# BSC_mini.net
KiCad netlist of a schematic drawn in EAGLE
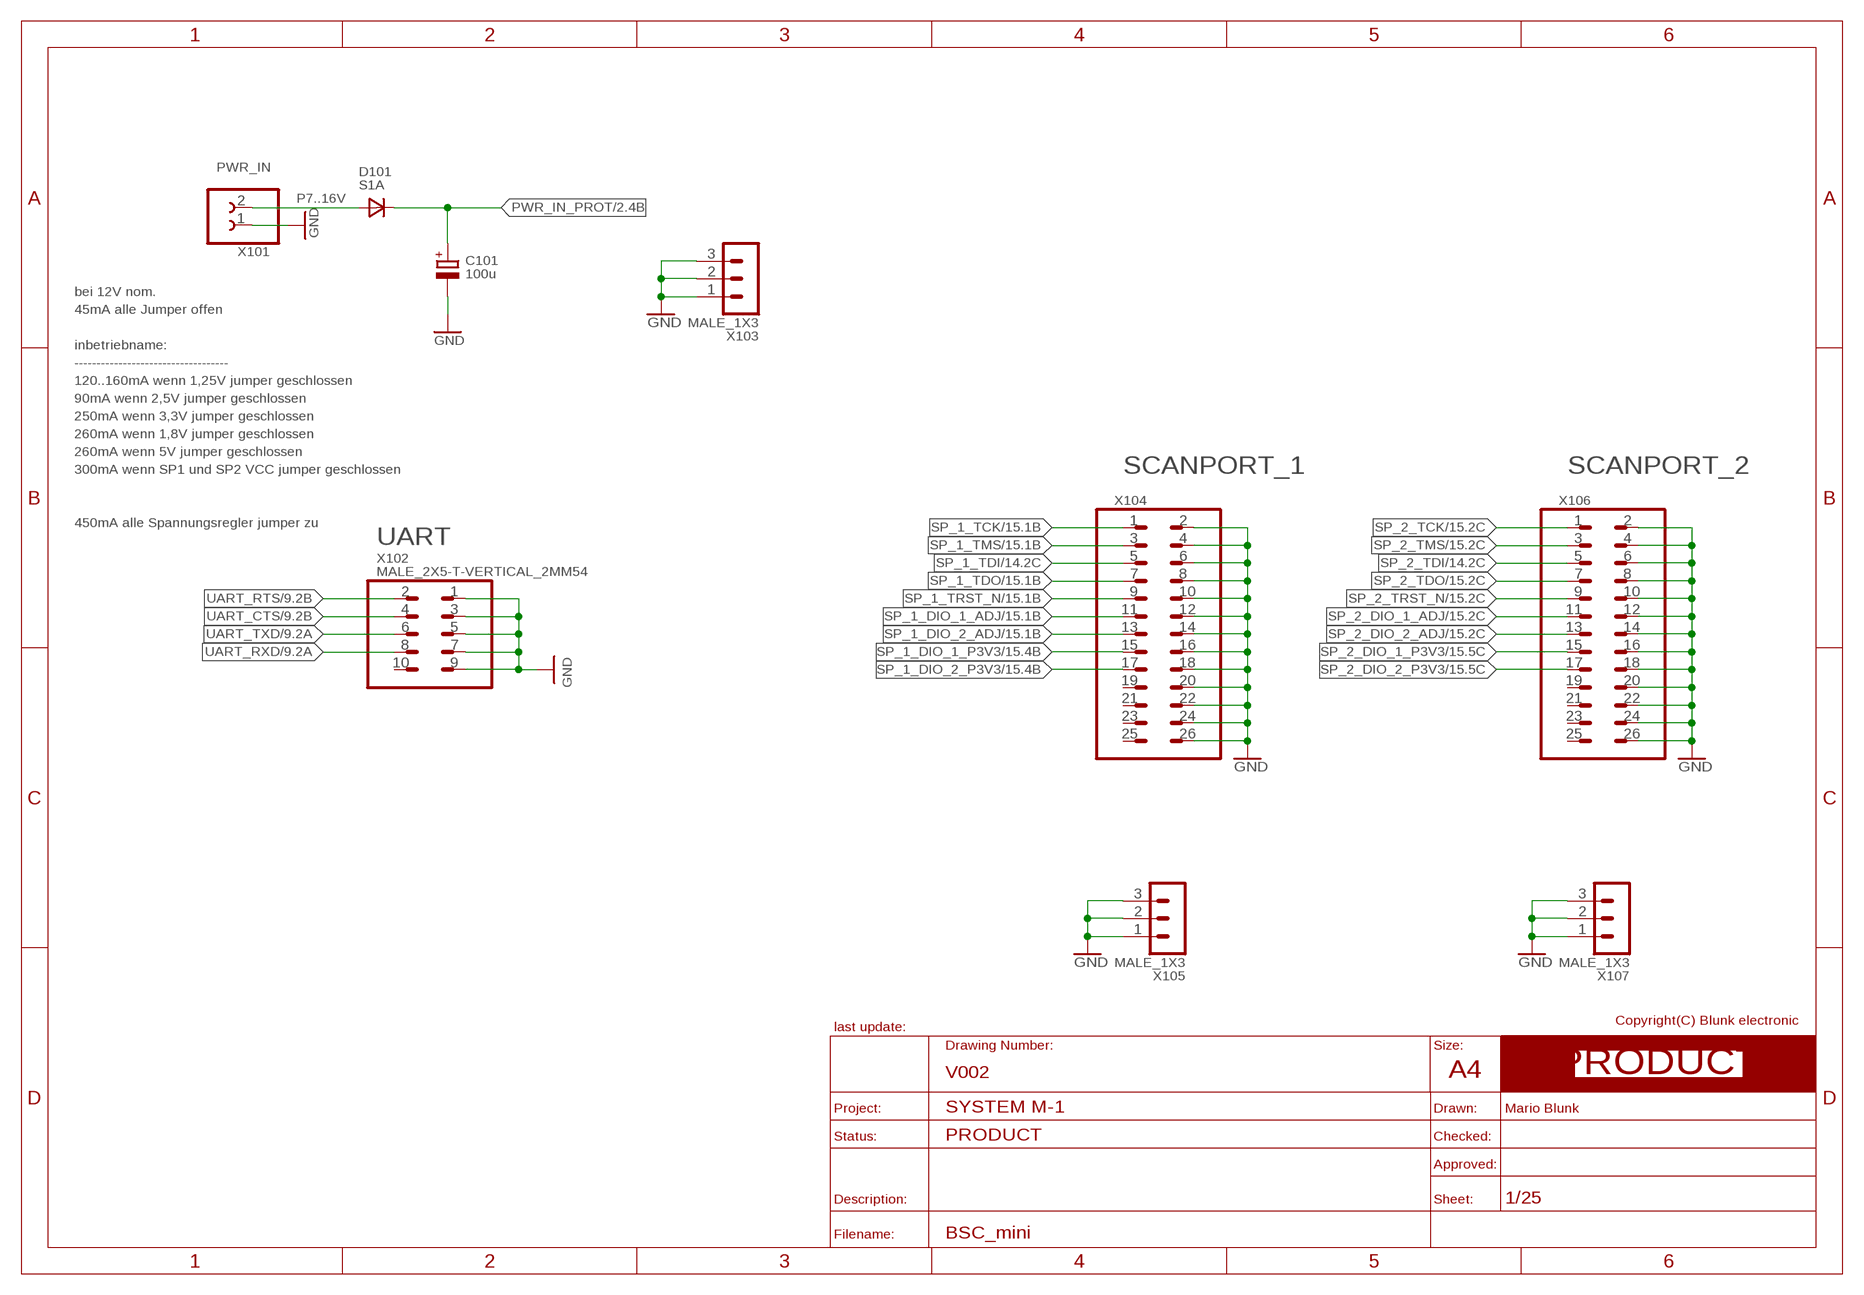
[diagram p0: schematic, sheet 1]
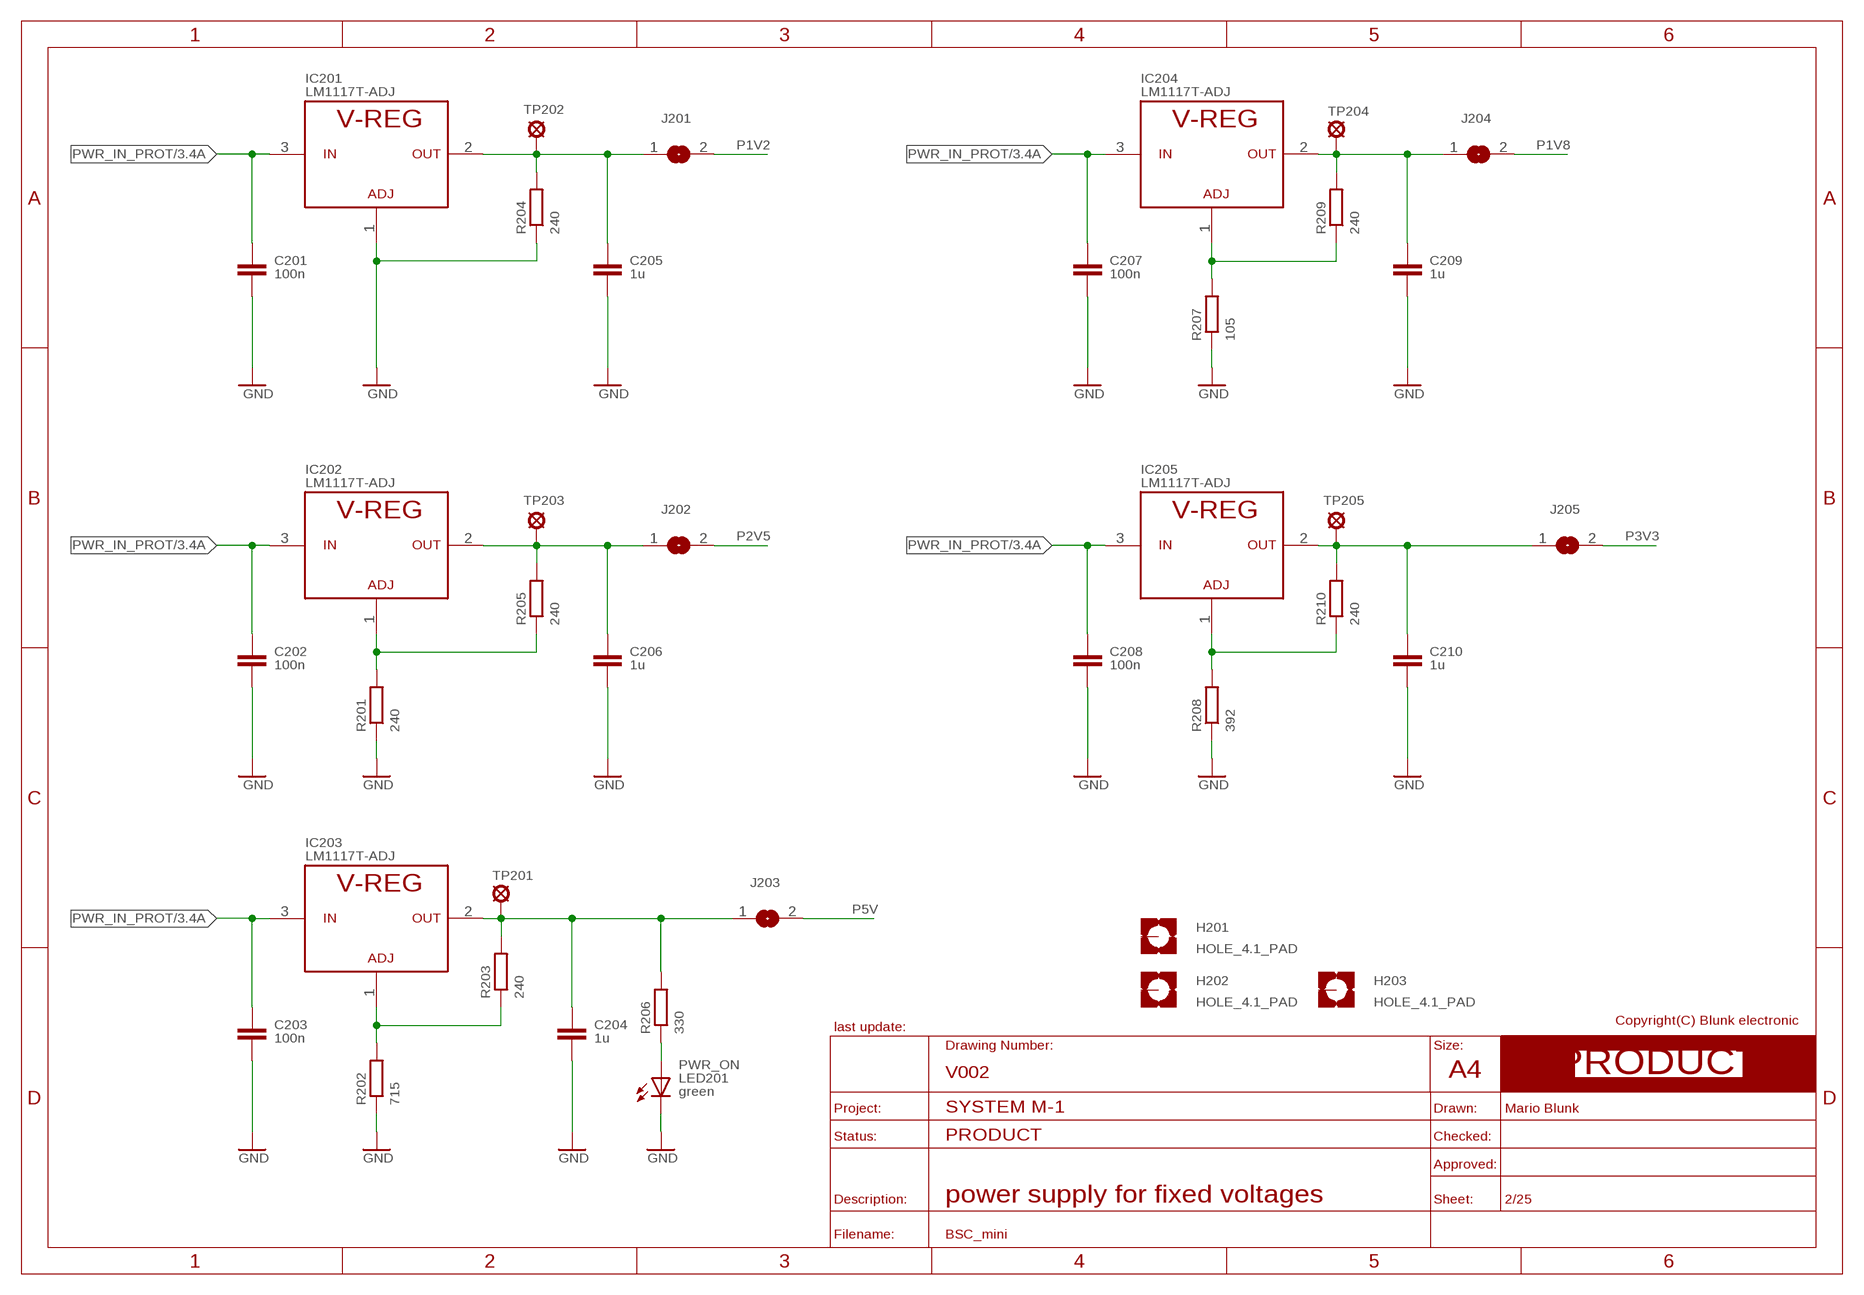
[diagram p1: schematic, sheet 2]
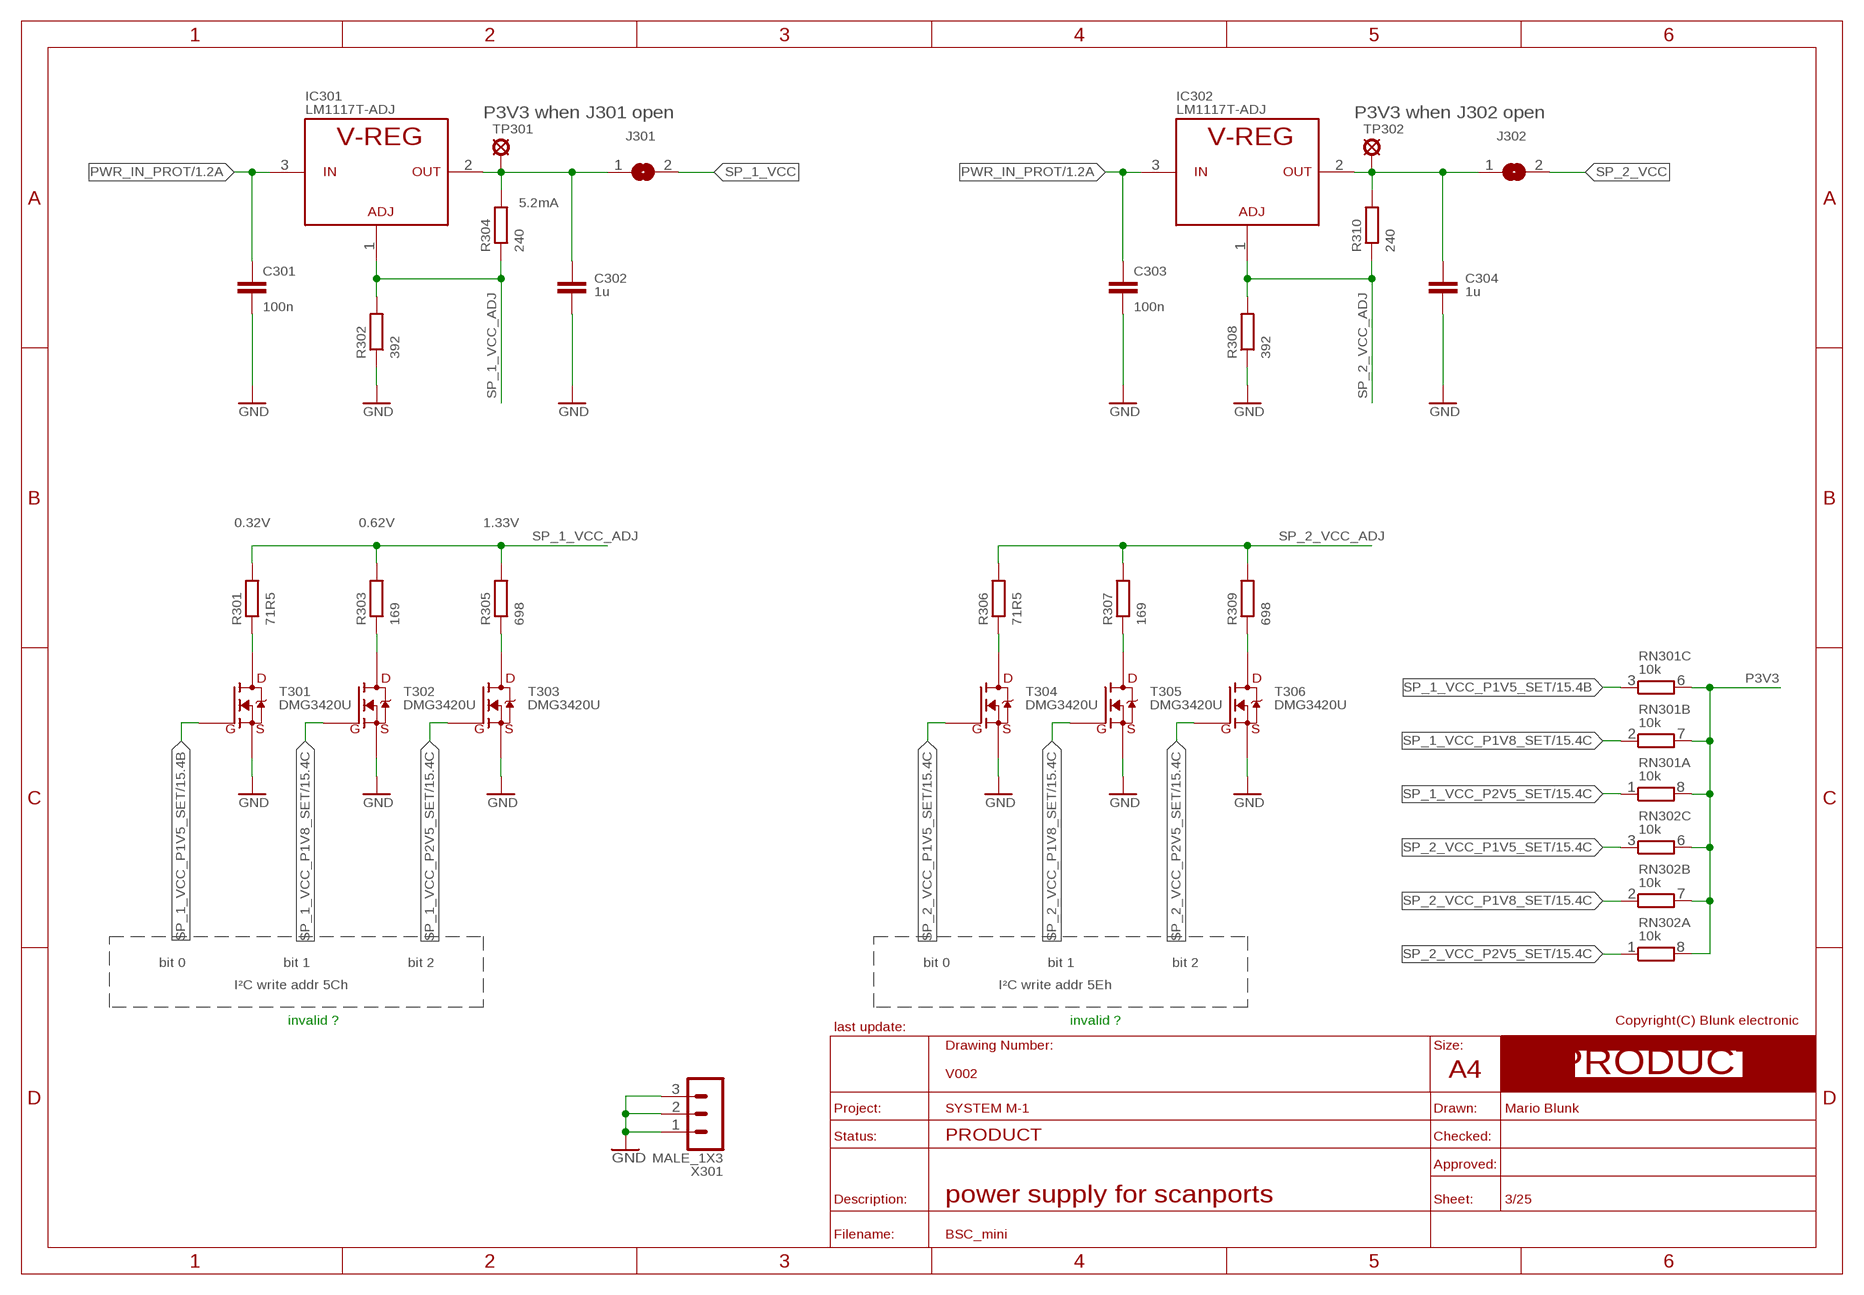
[diagram p2: schematic, sheet 3]
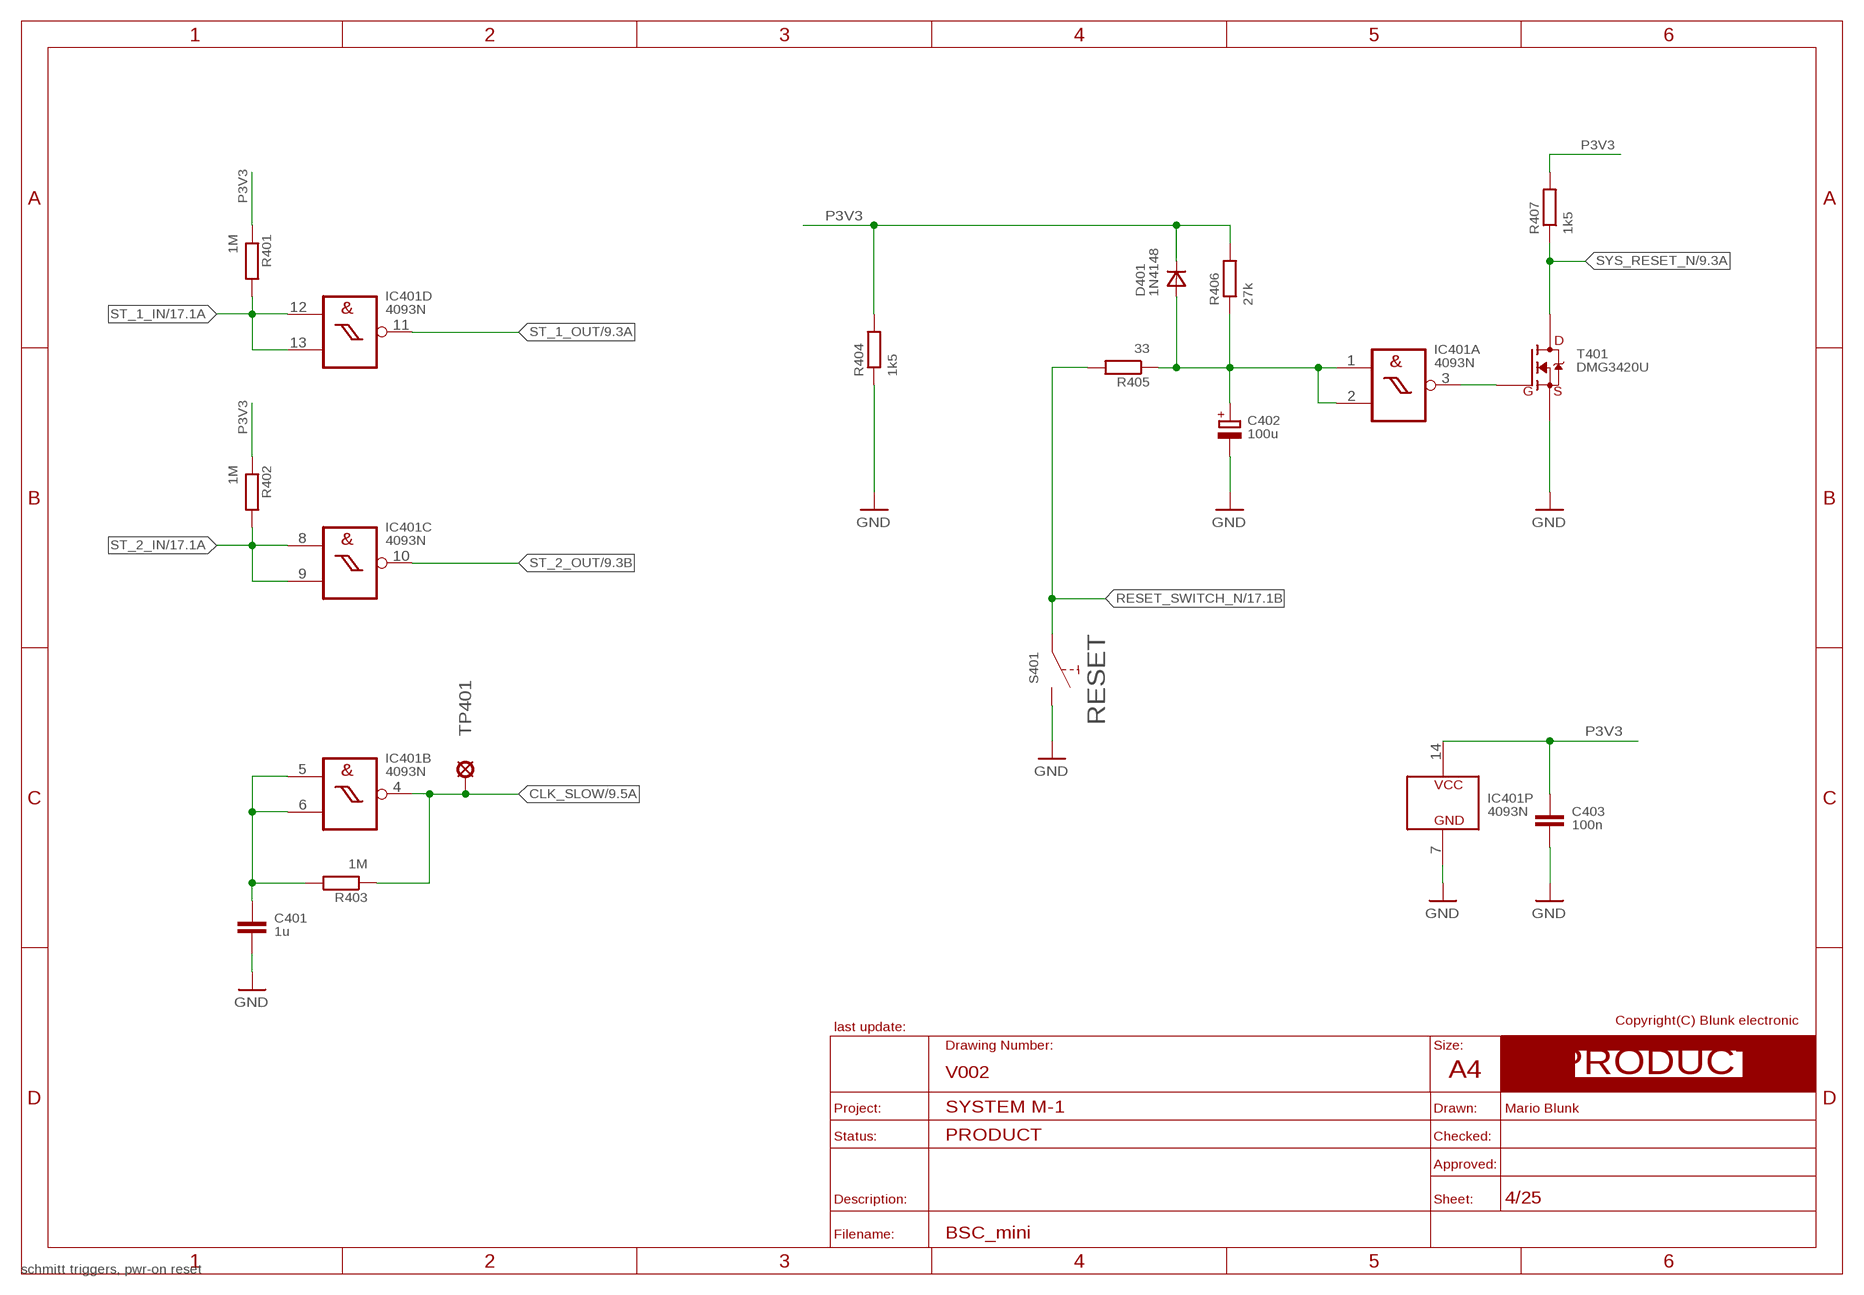
[diagram p3: schematic, sheet 4]
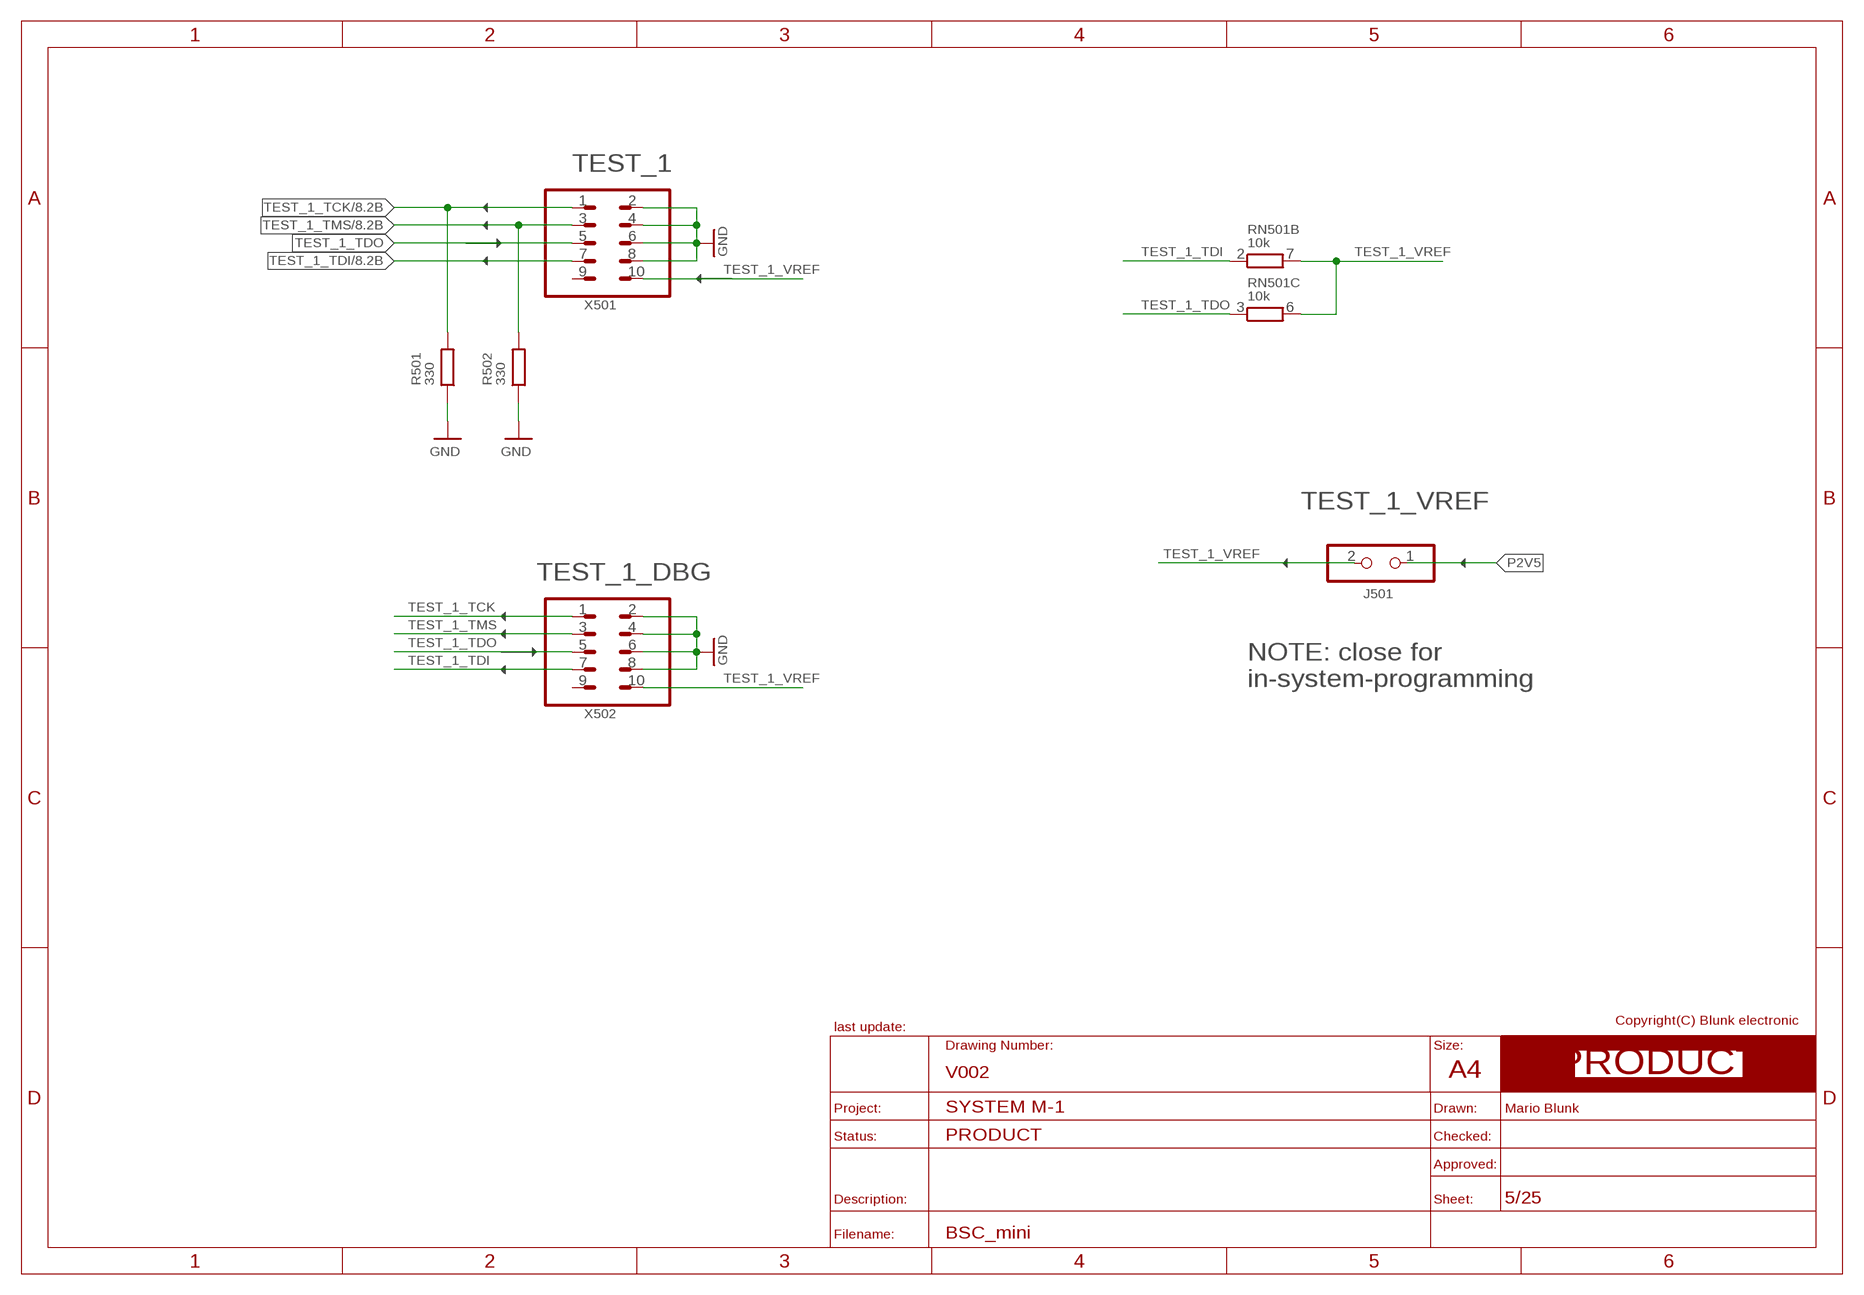
[diagram p4: schematic, sheet 5]
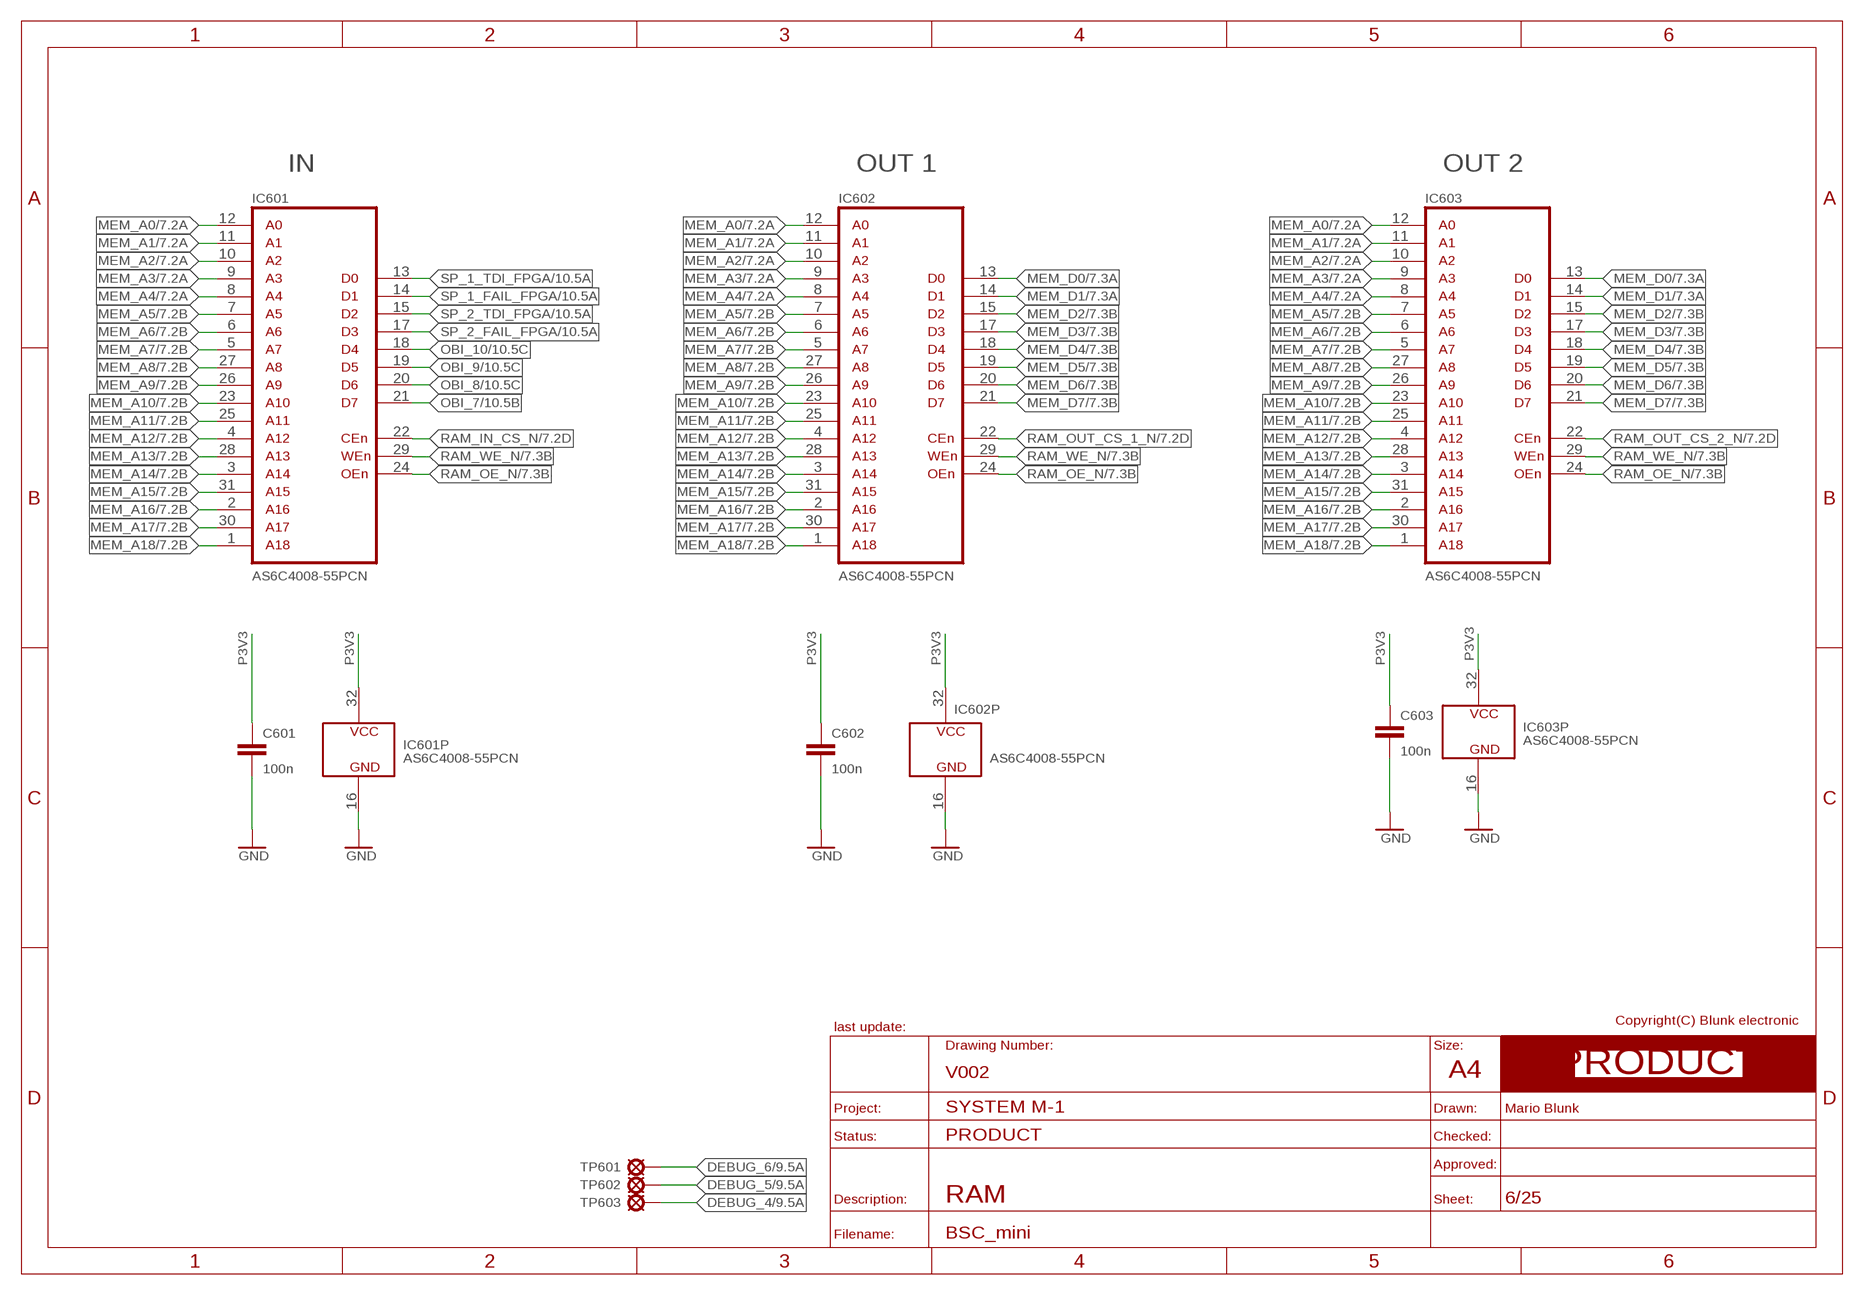
[diagram p5: schematic, sheet 6]
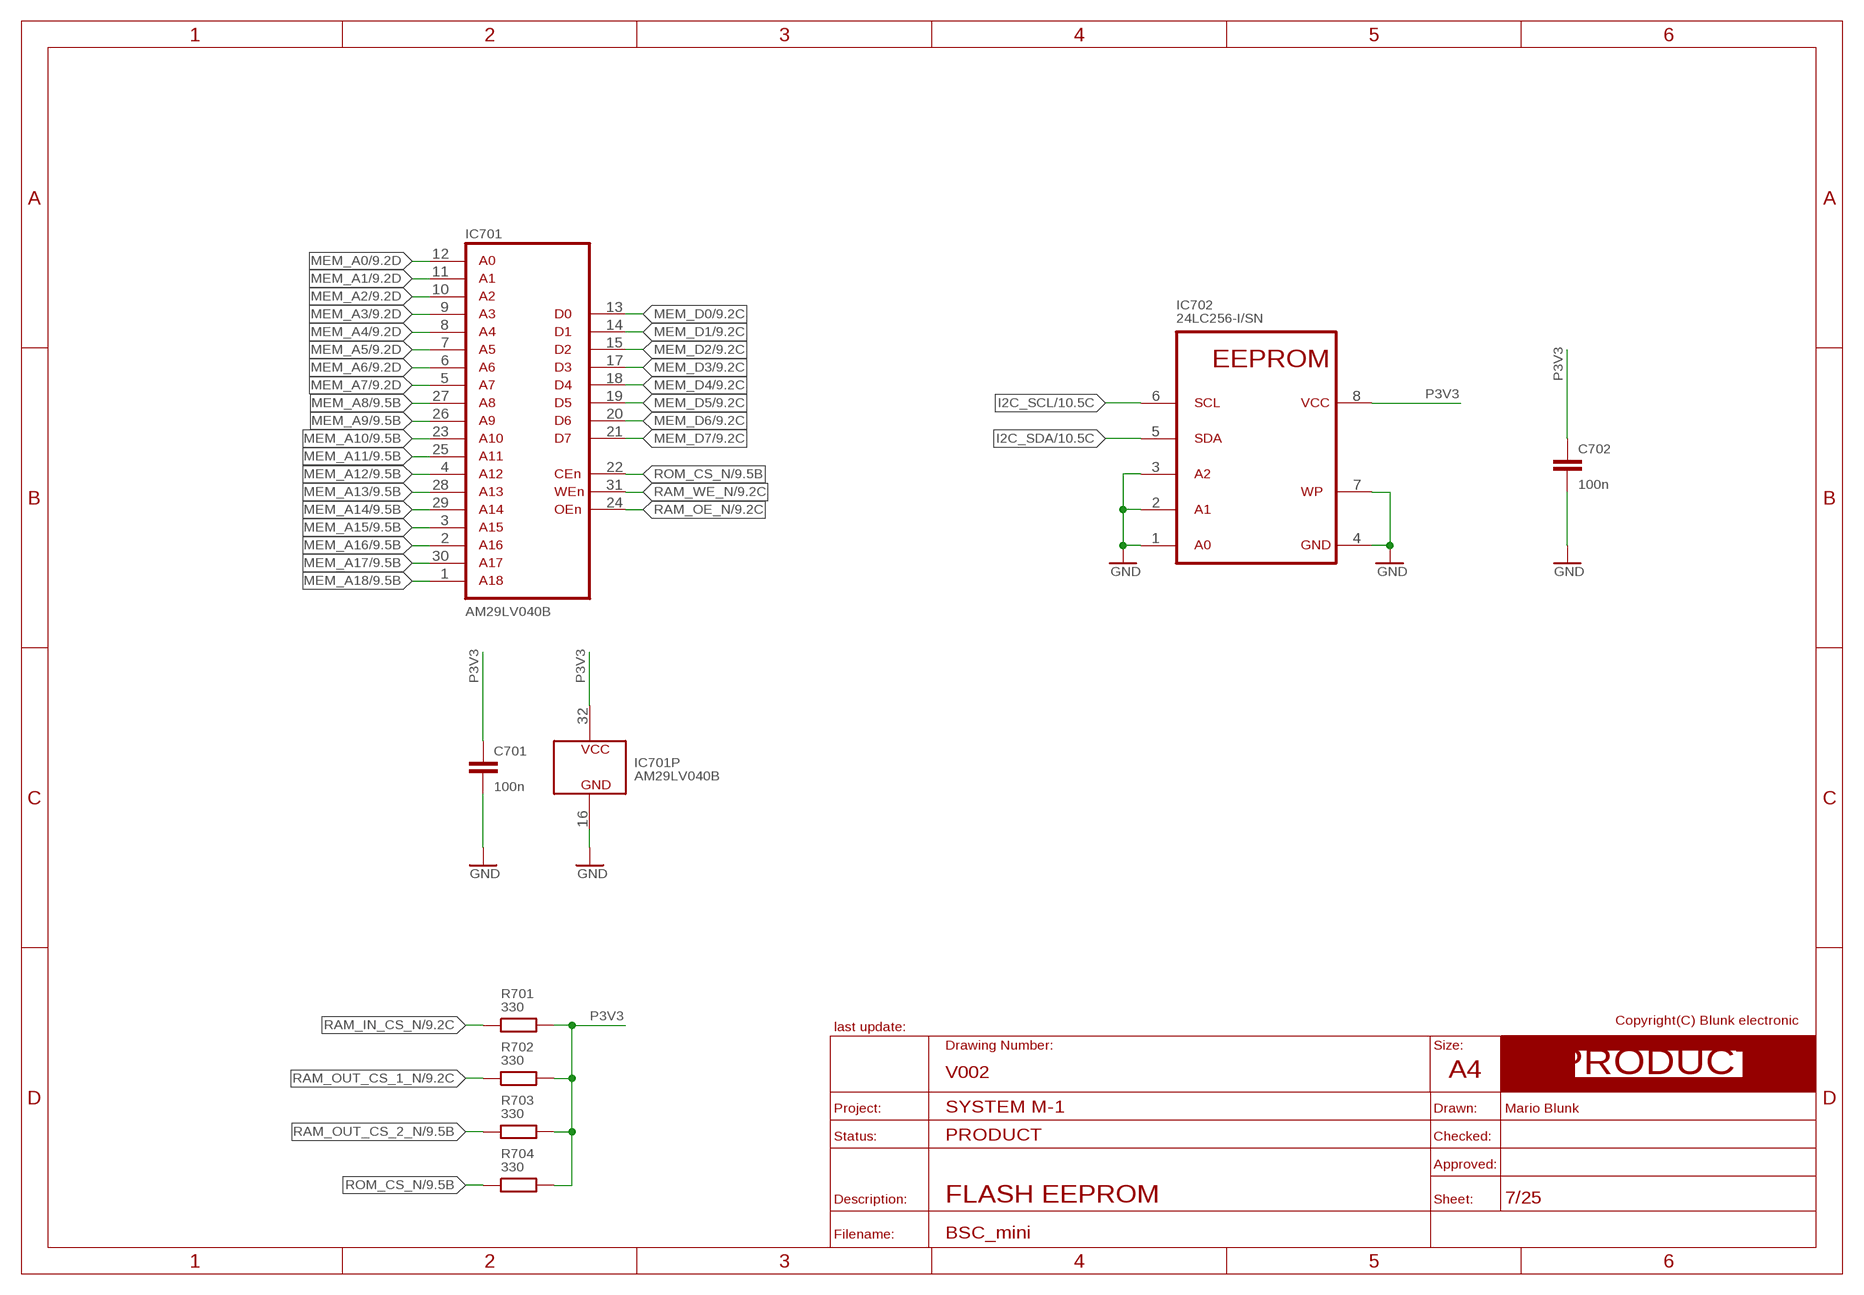
[diagram p6: schematic, sheet 7]
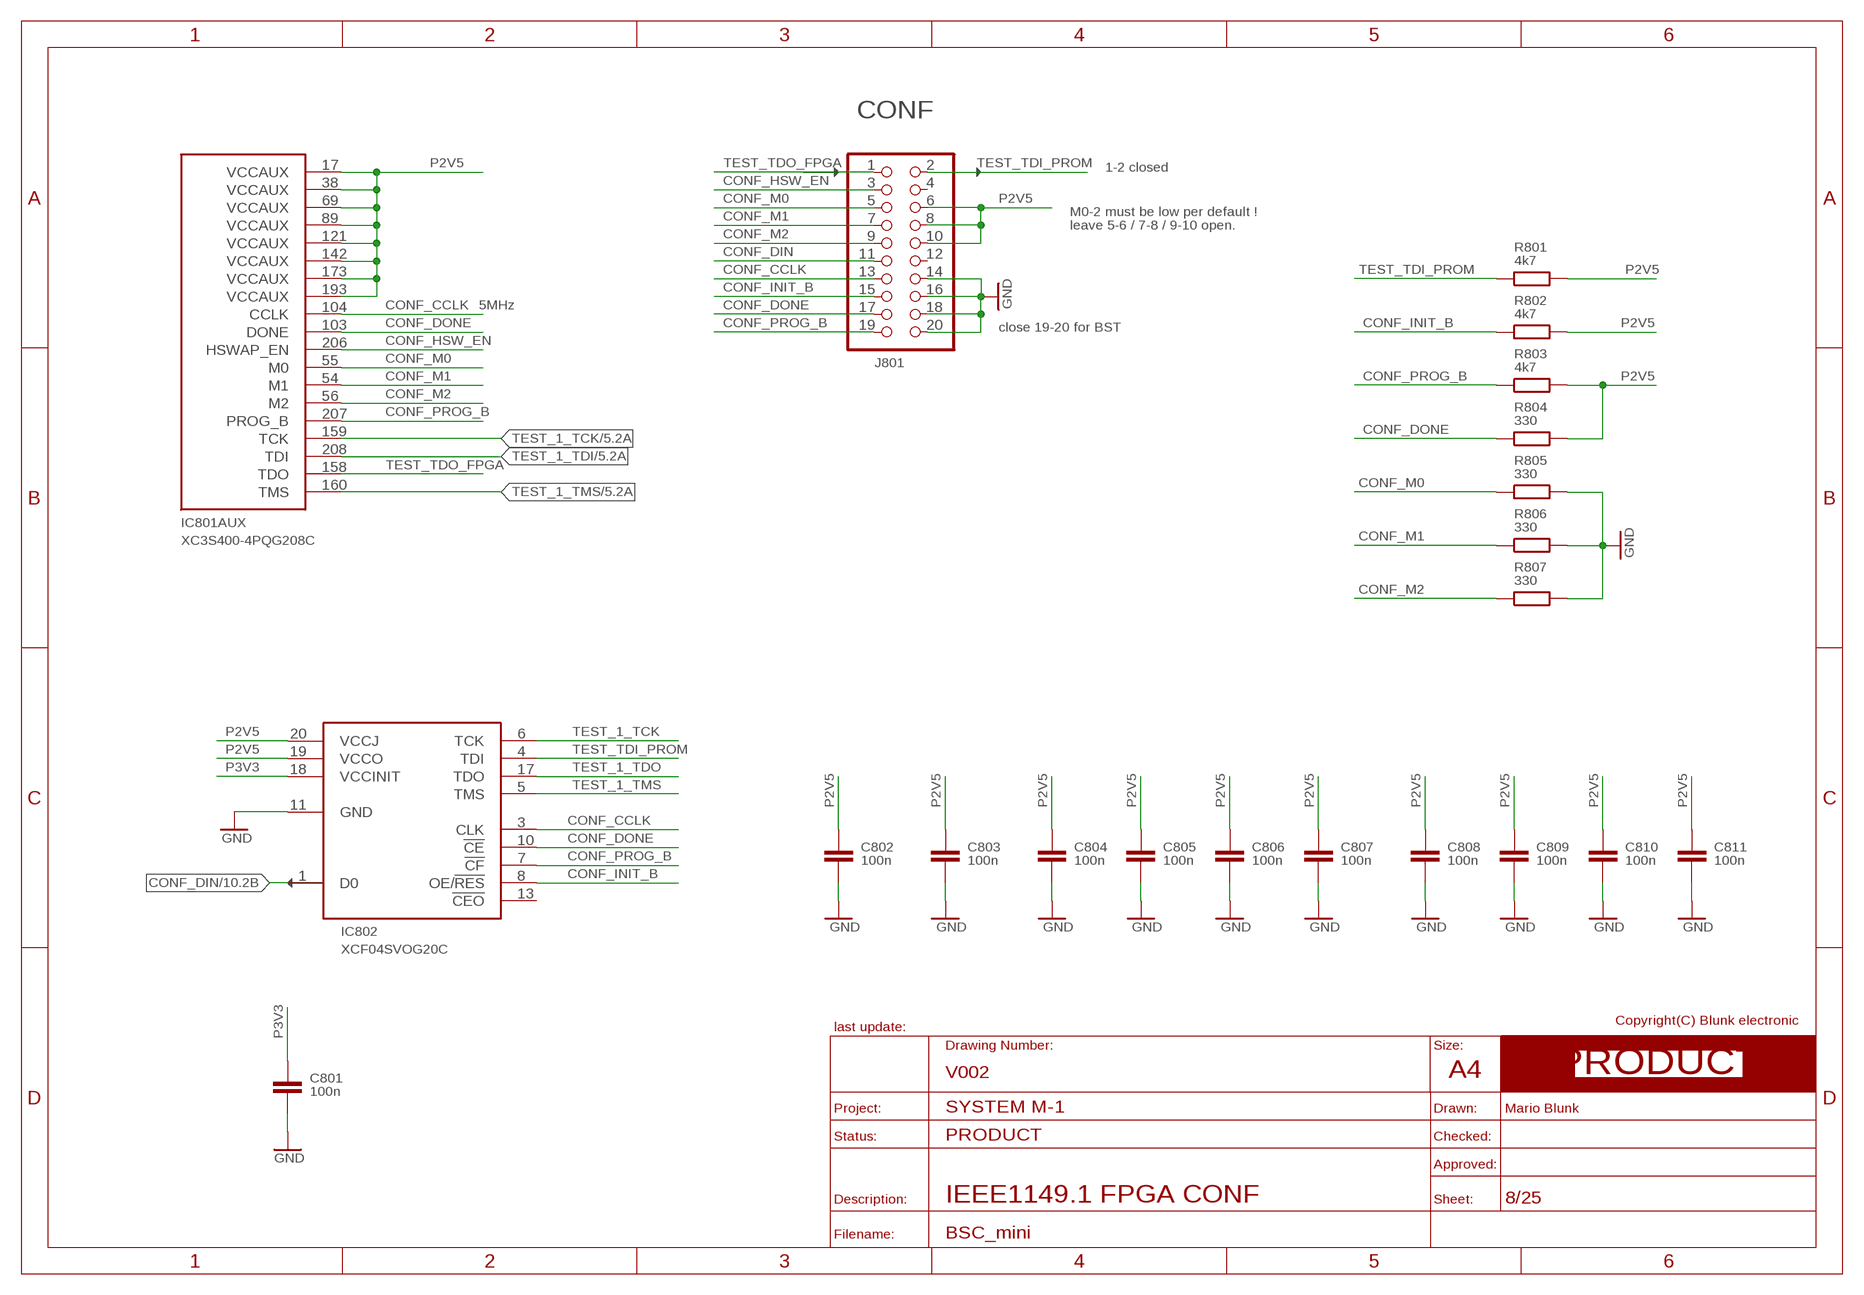
[diagram p7: schematic, sheet 8]
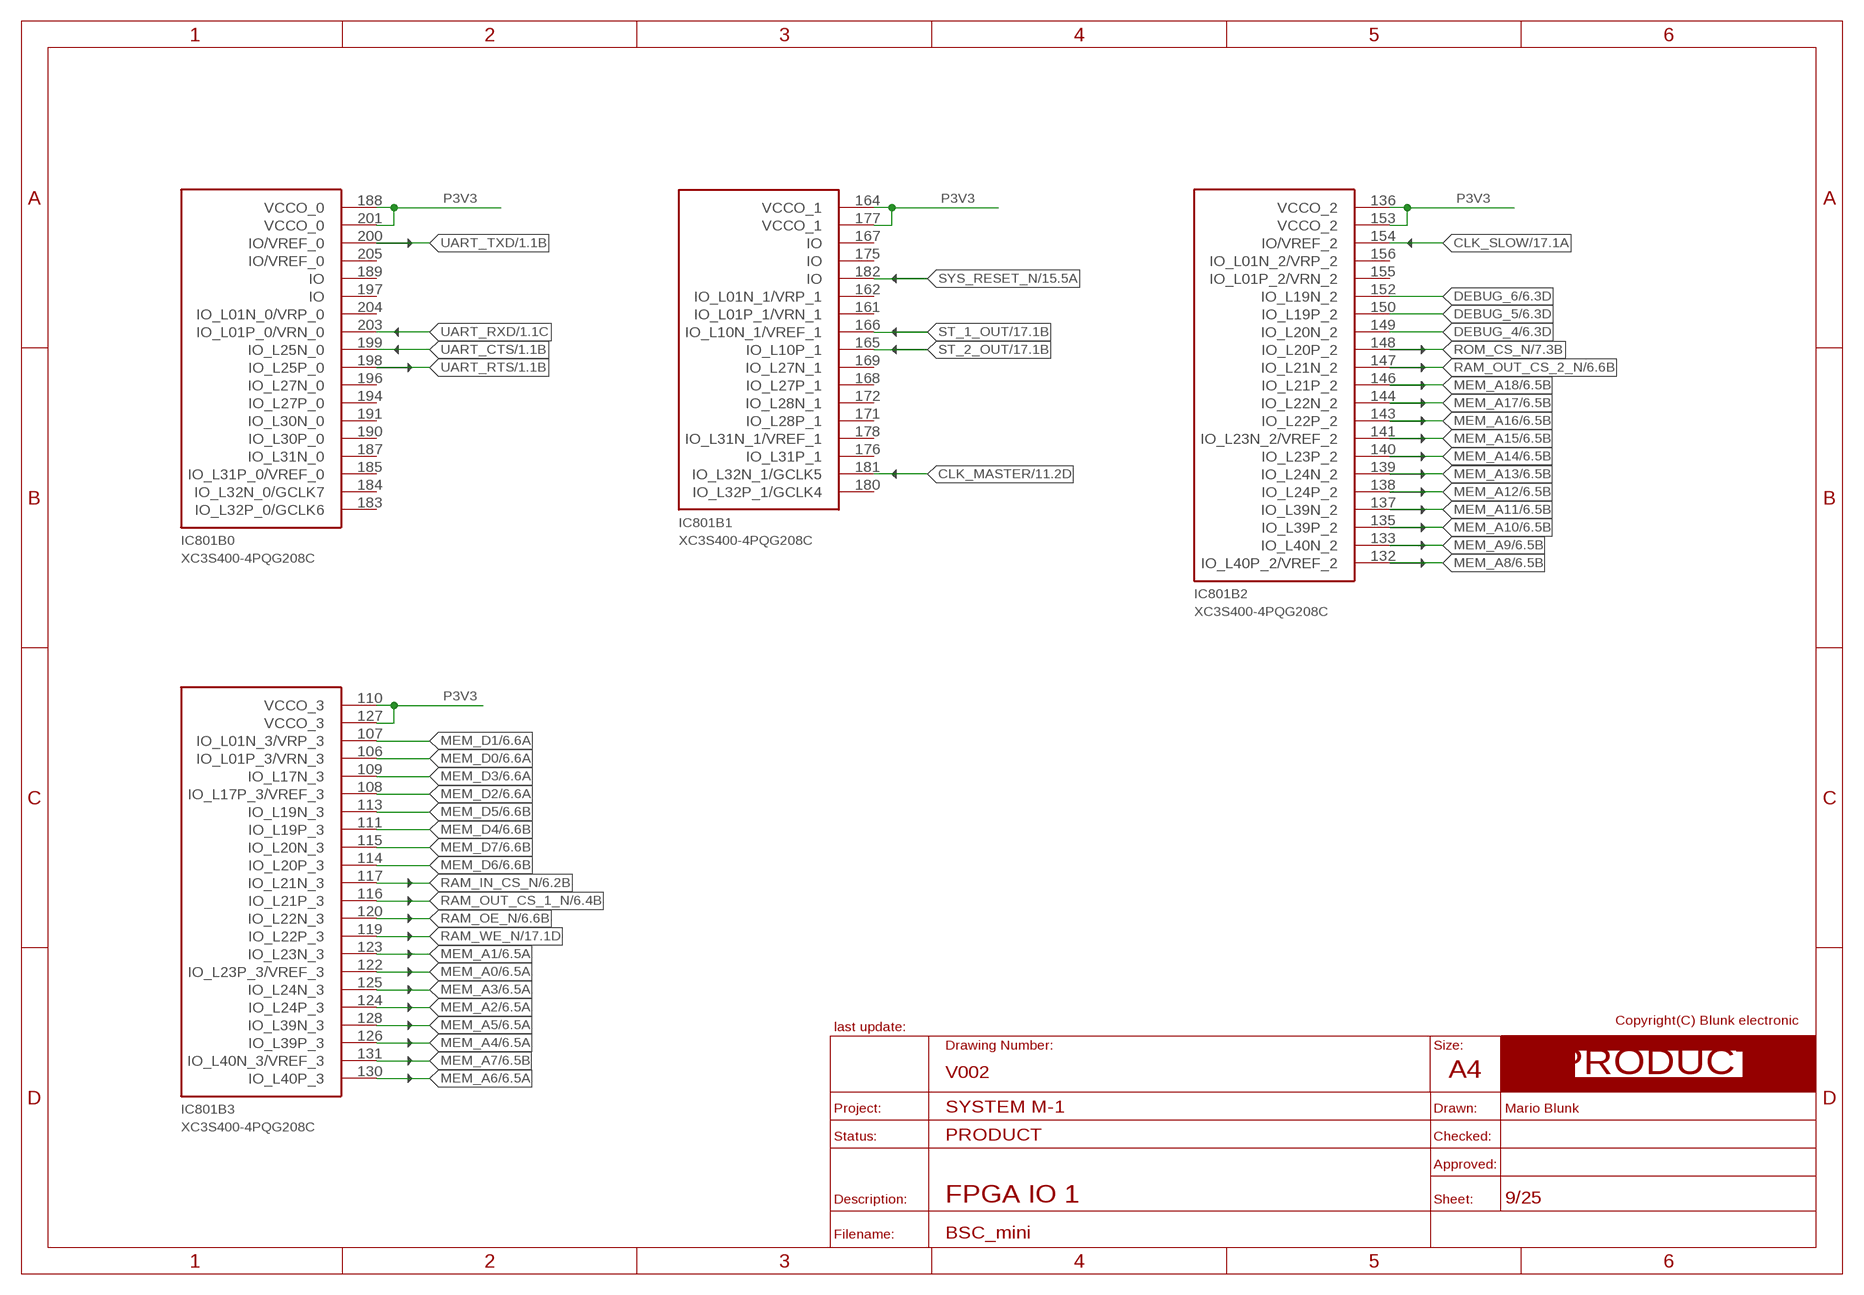
[diagram p8: schematic, sheet 9]
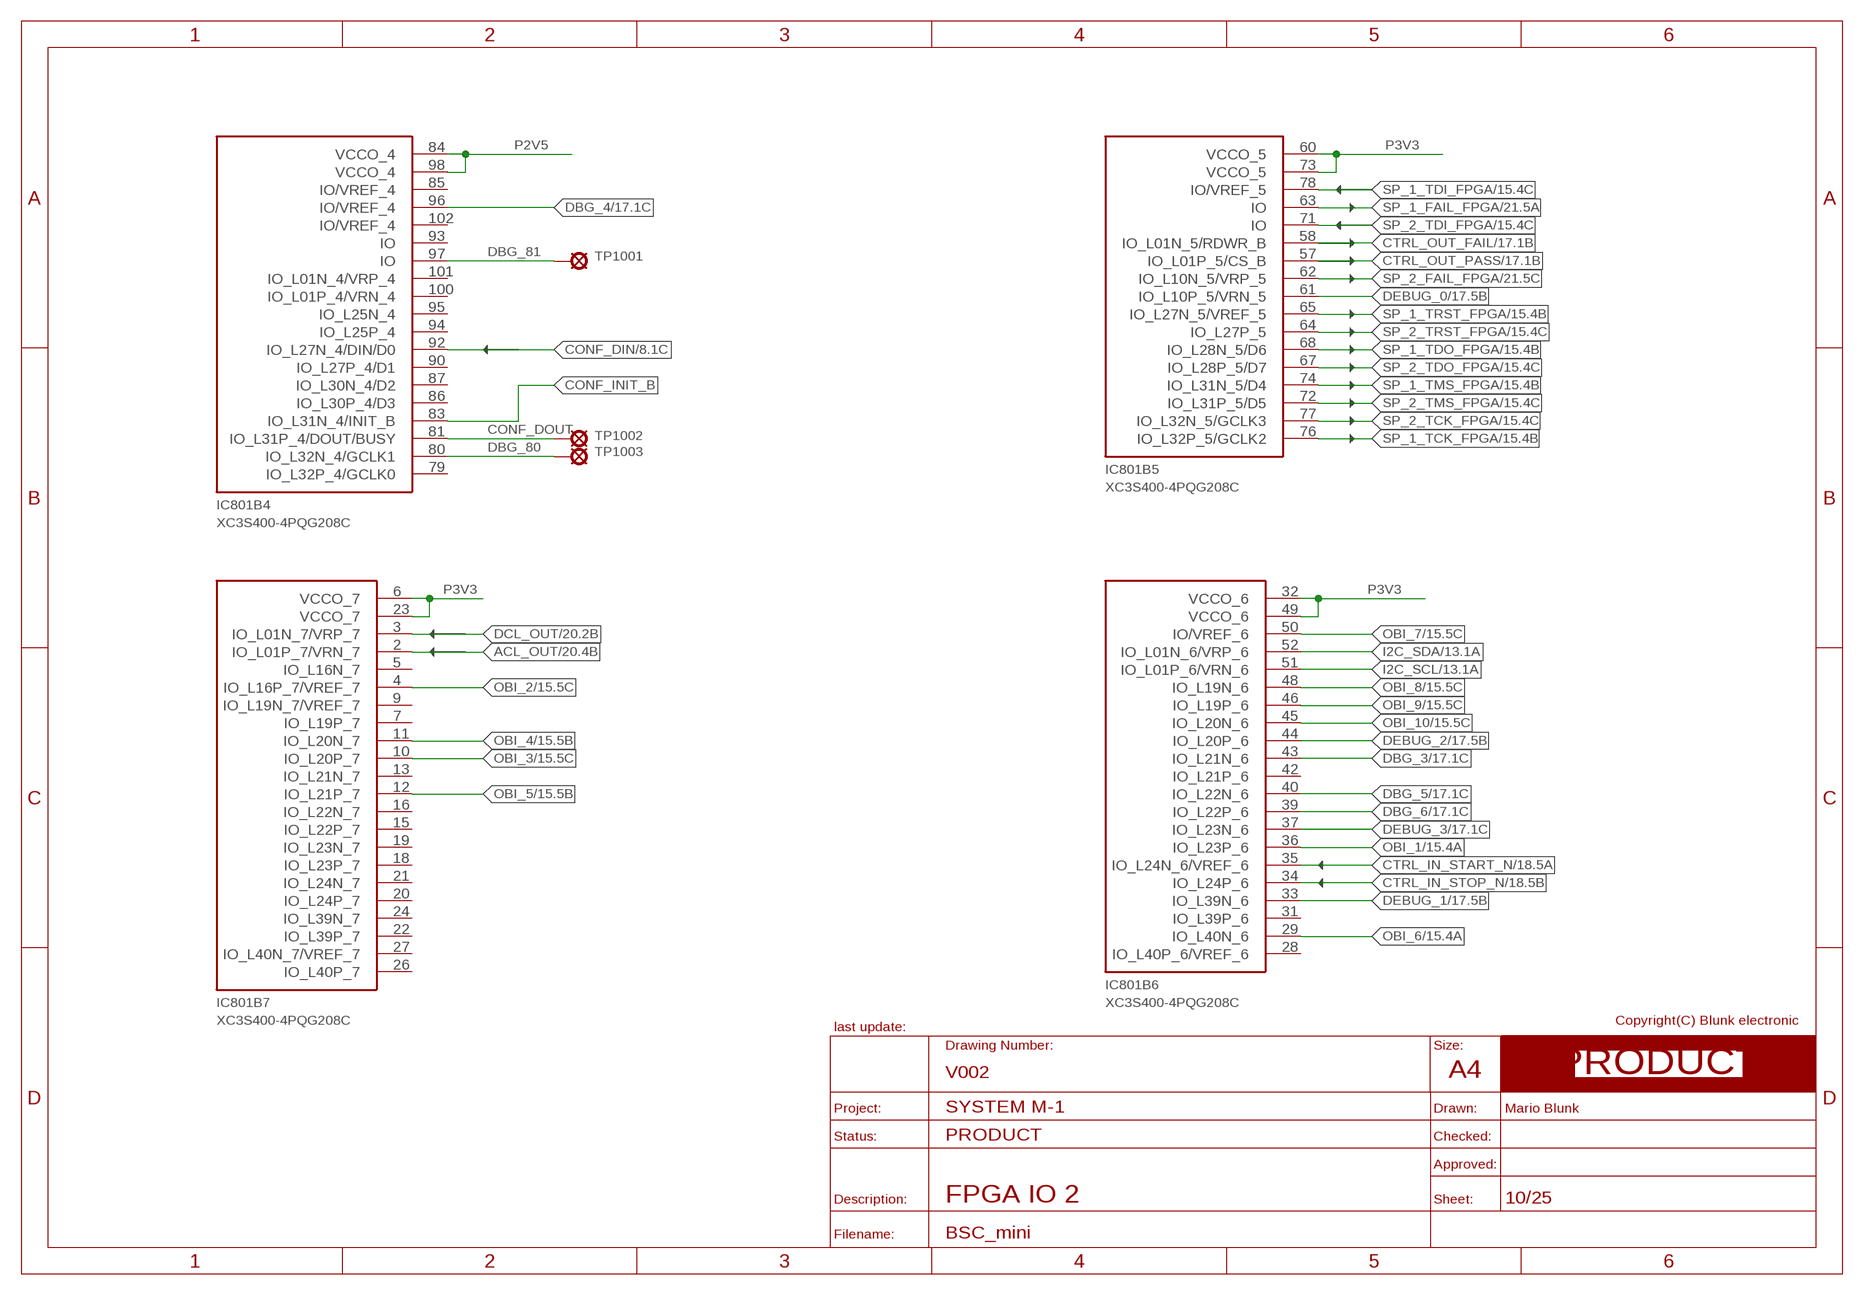
[diagram p9: schematic, sheet 10]
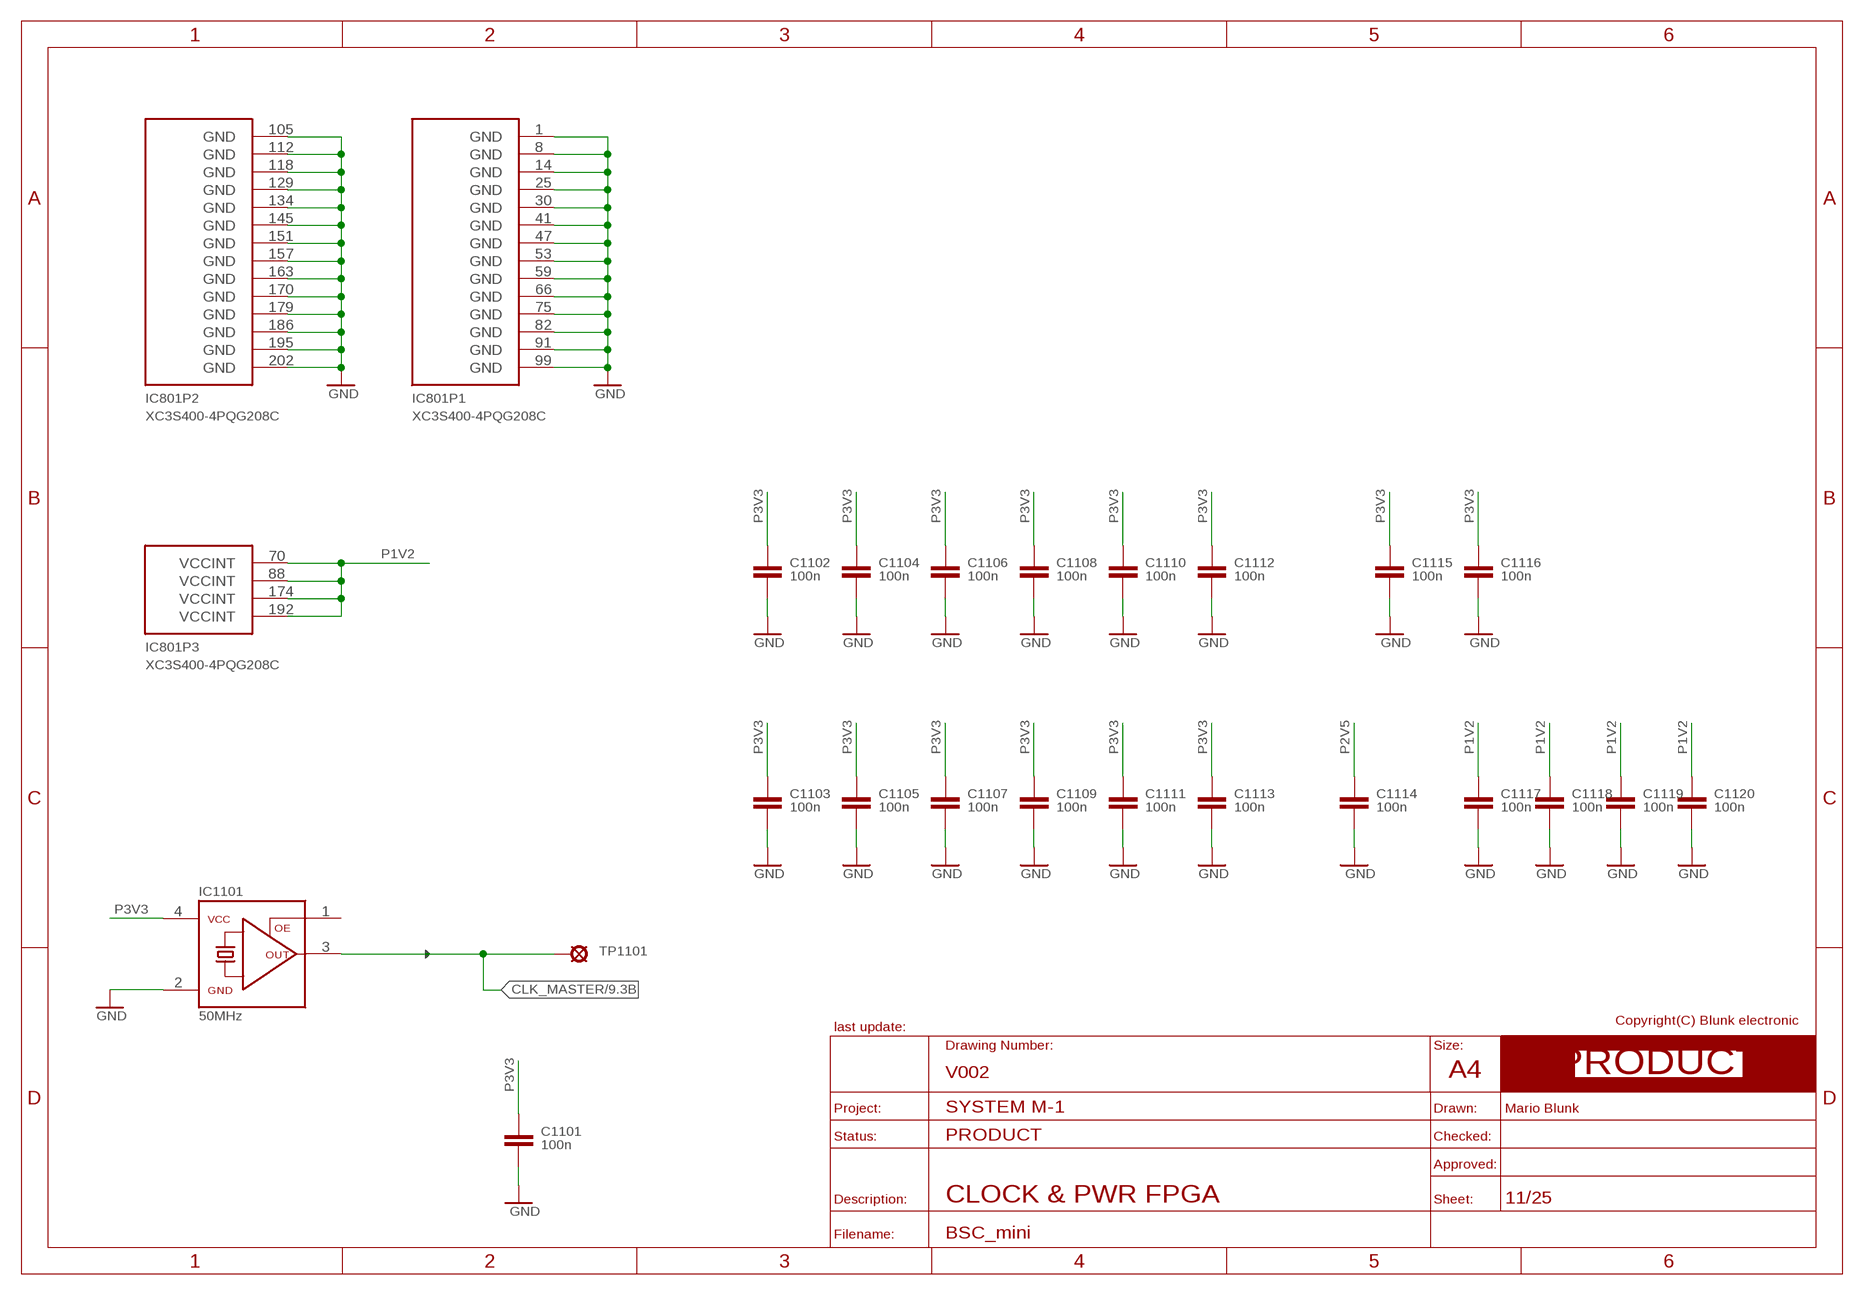
[diagram p10: schematic, sheet 11]
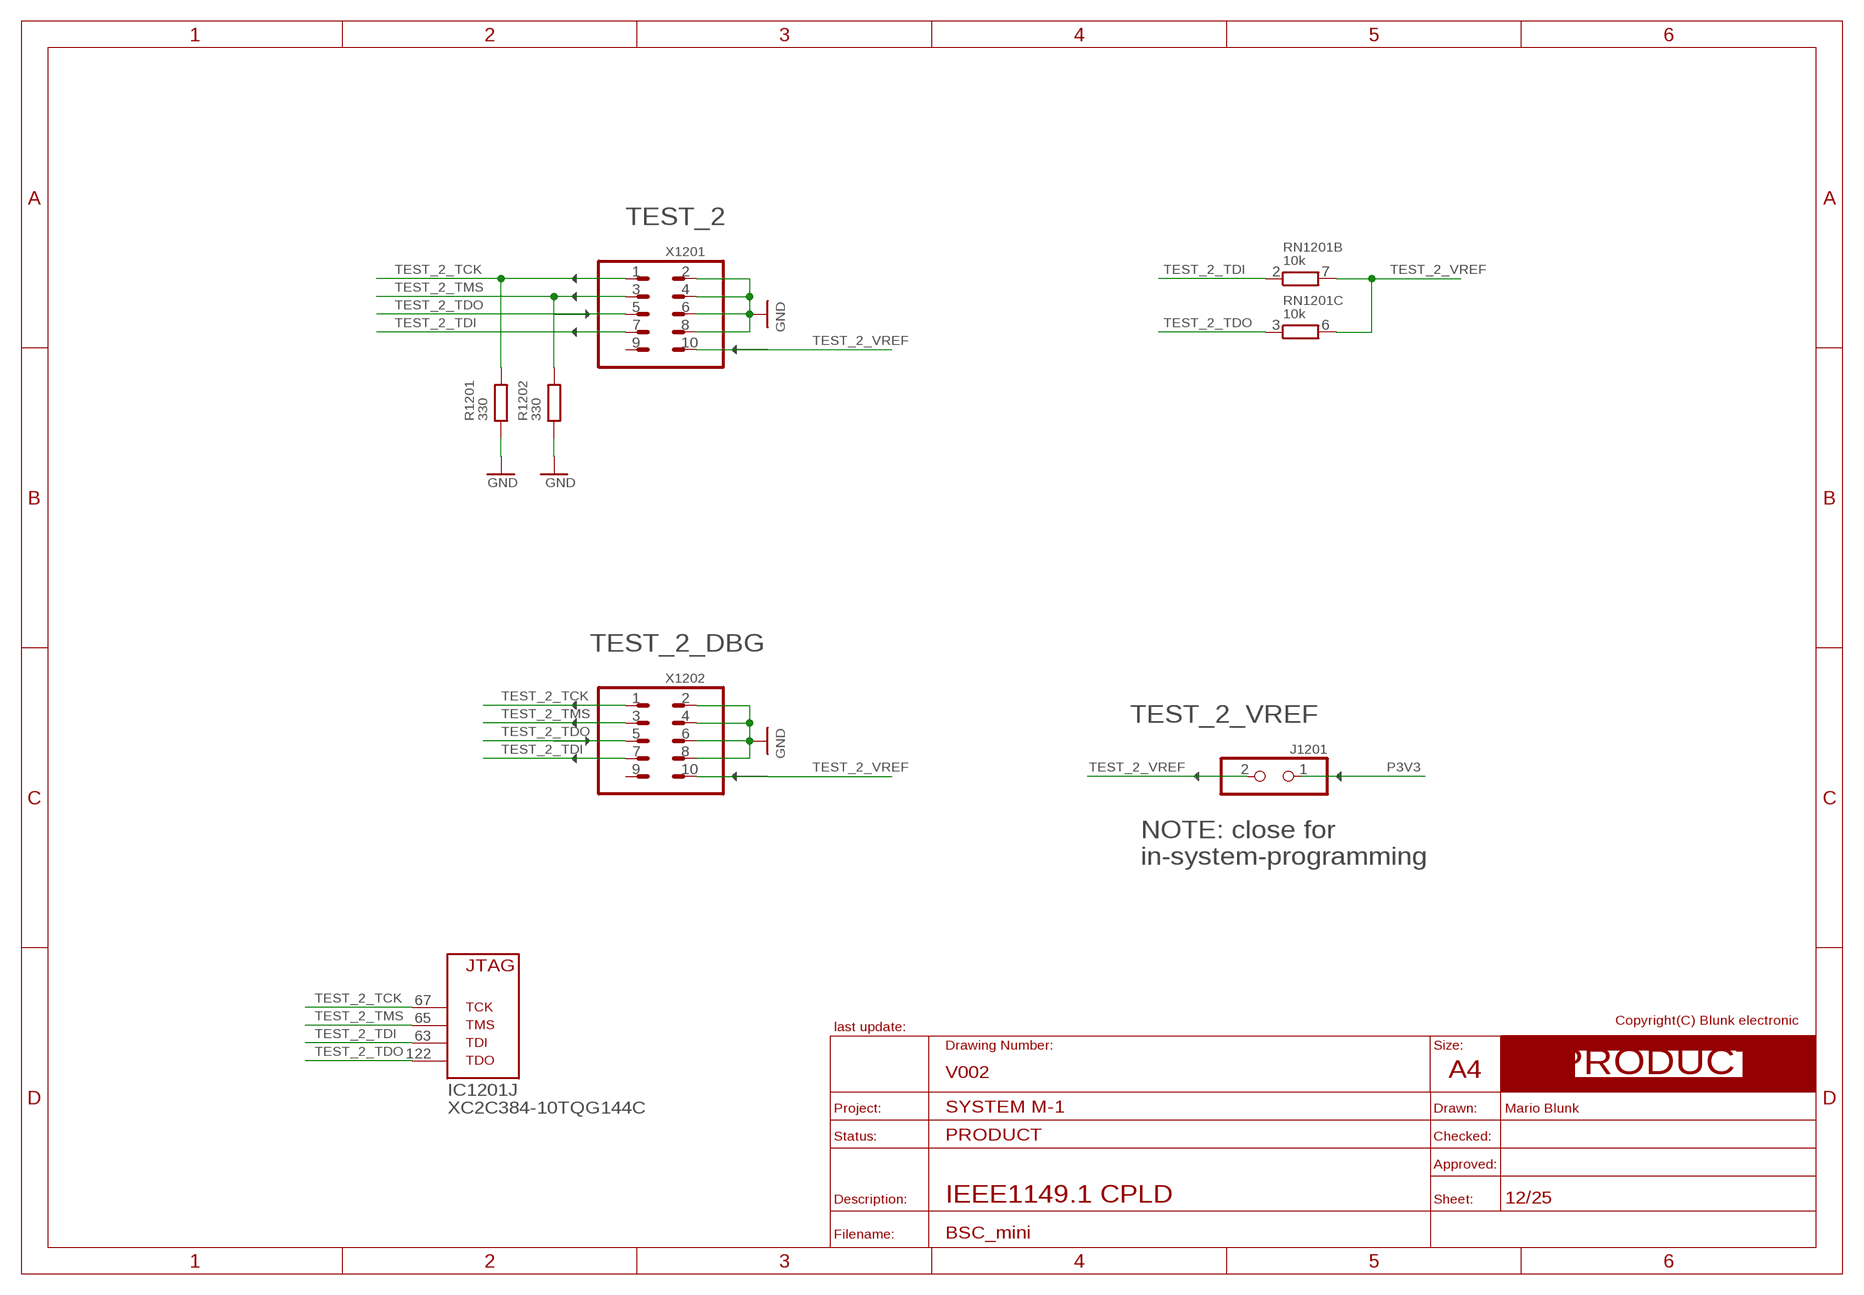
[diagram p11: schematic, sheet 12]
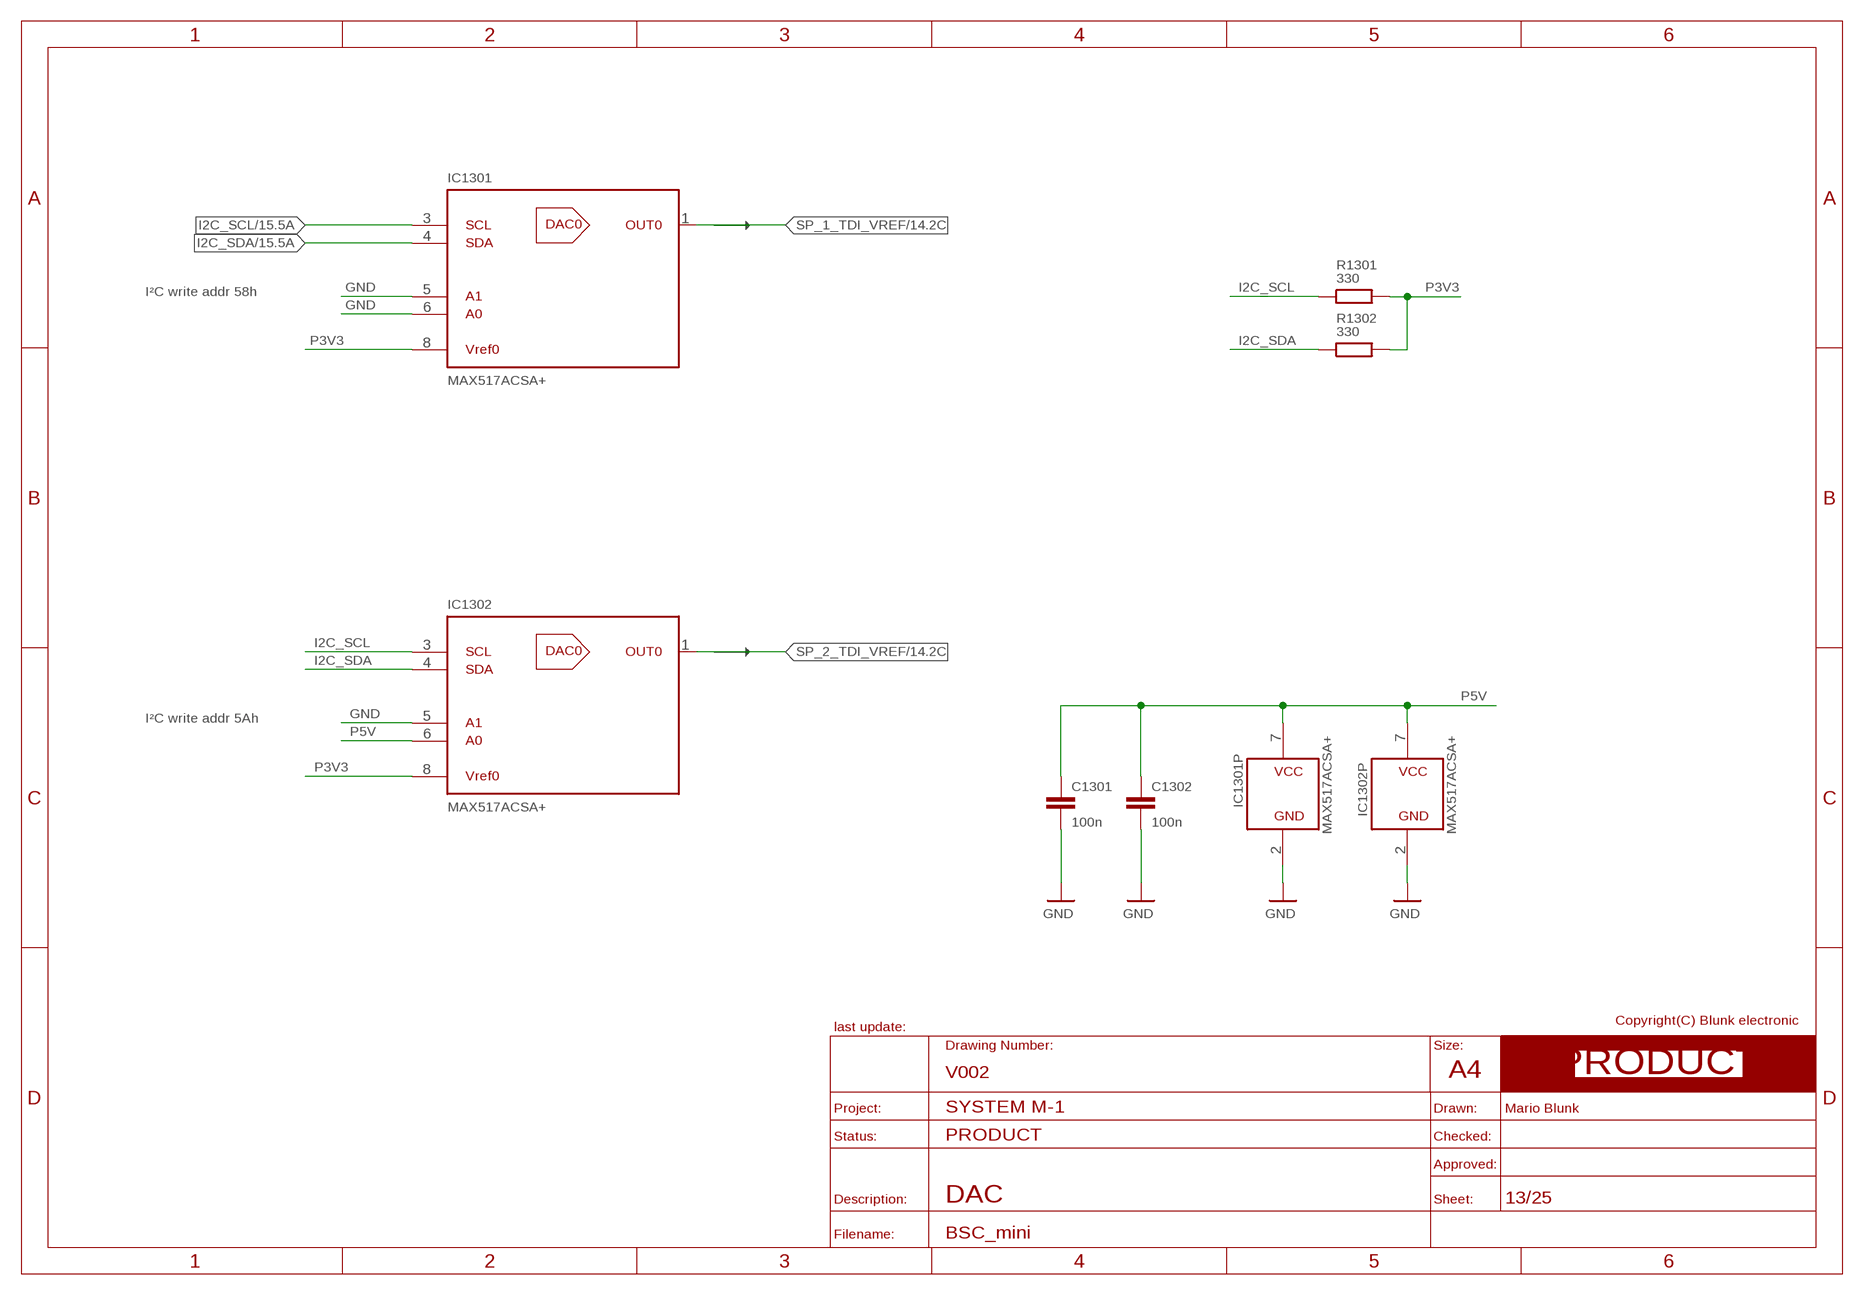
[diagram p12: schematic, sheet 13]
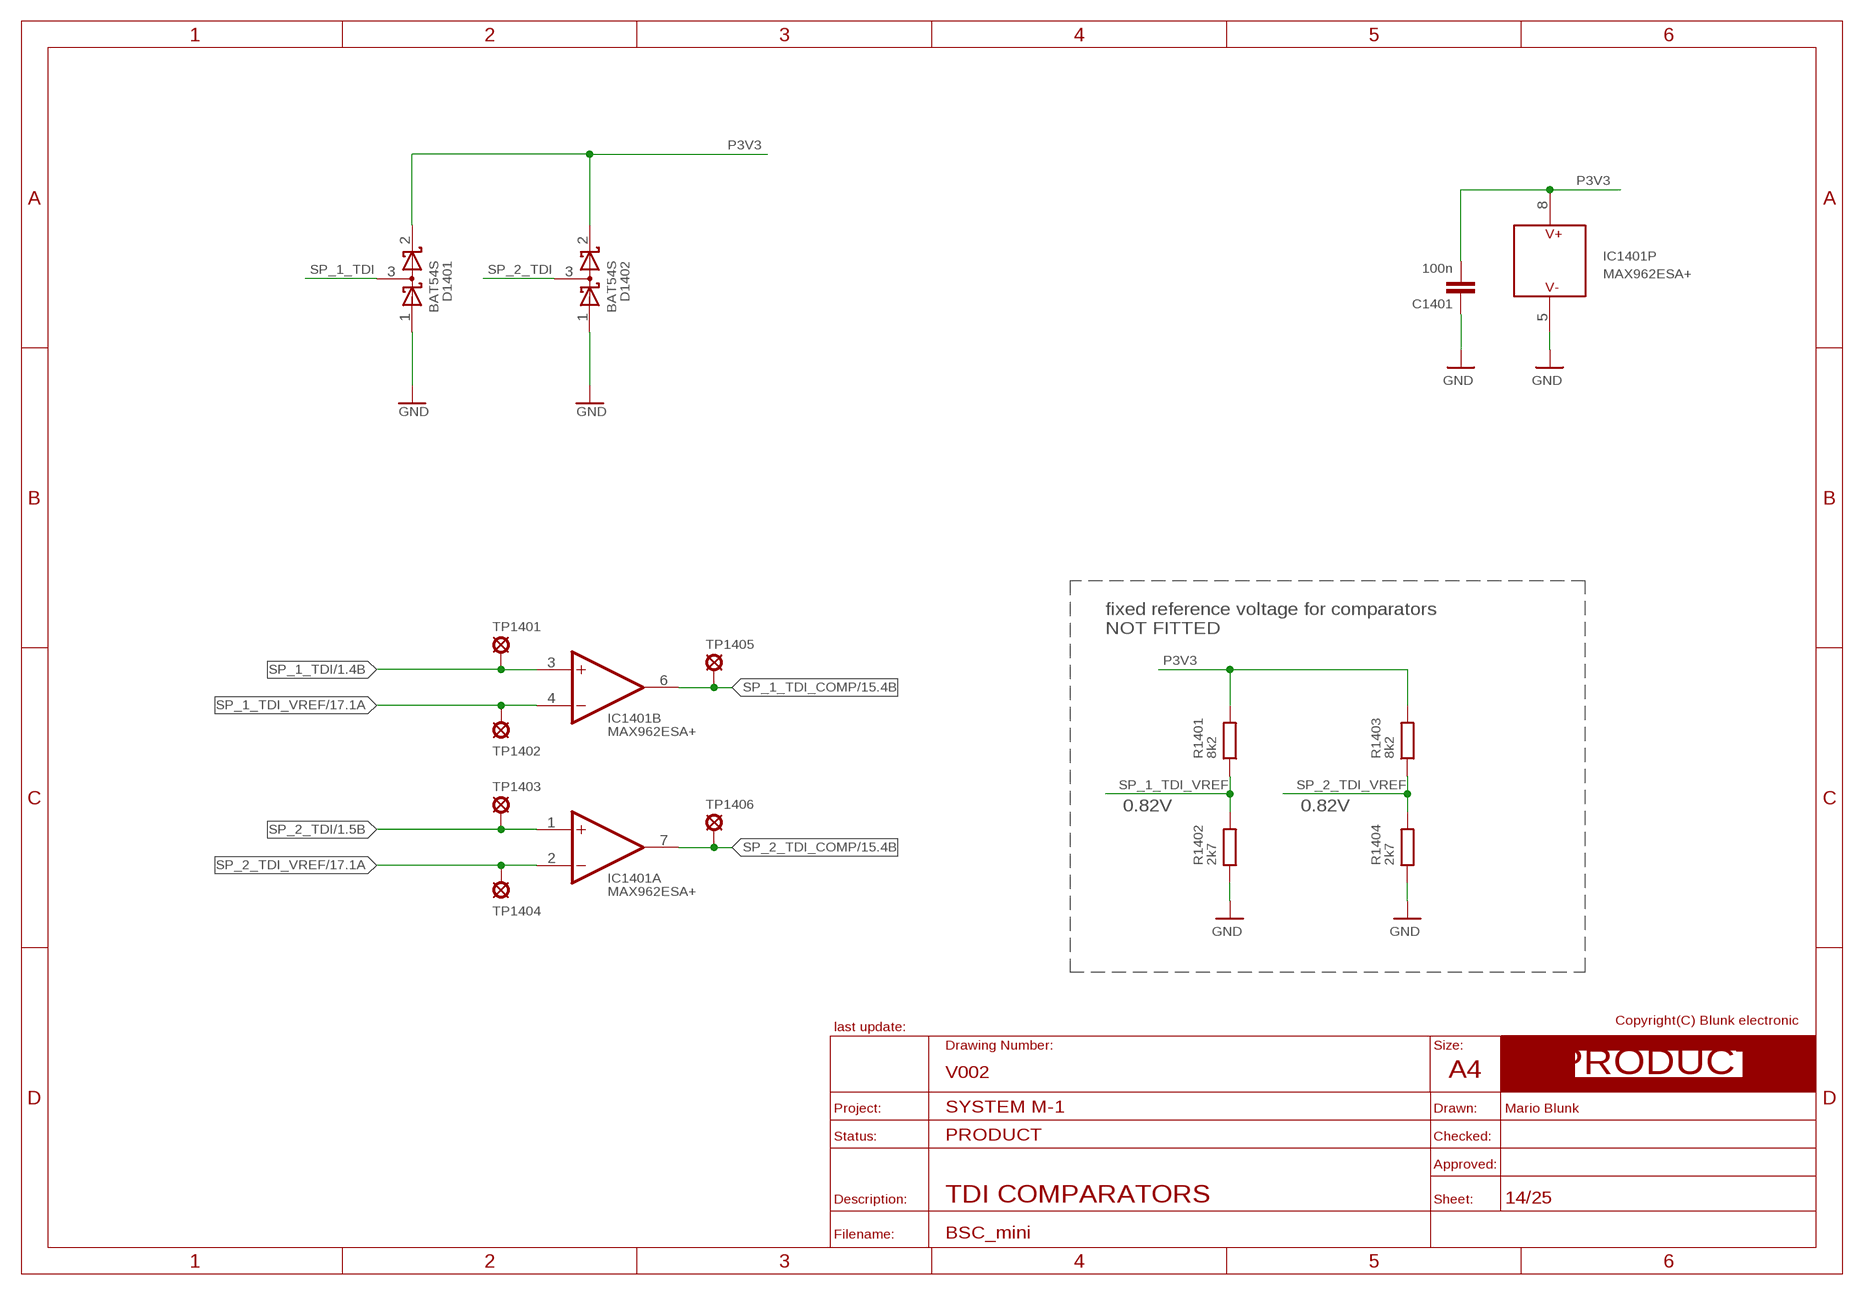
[diagram p13: schematic, sheet 14]
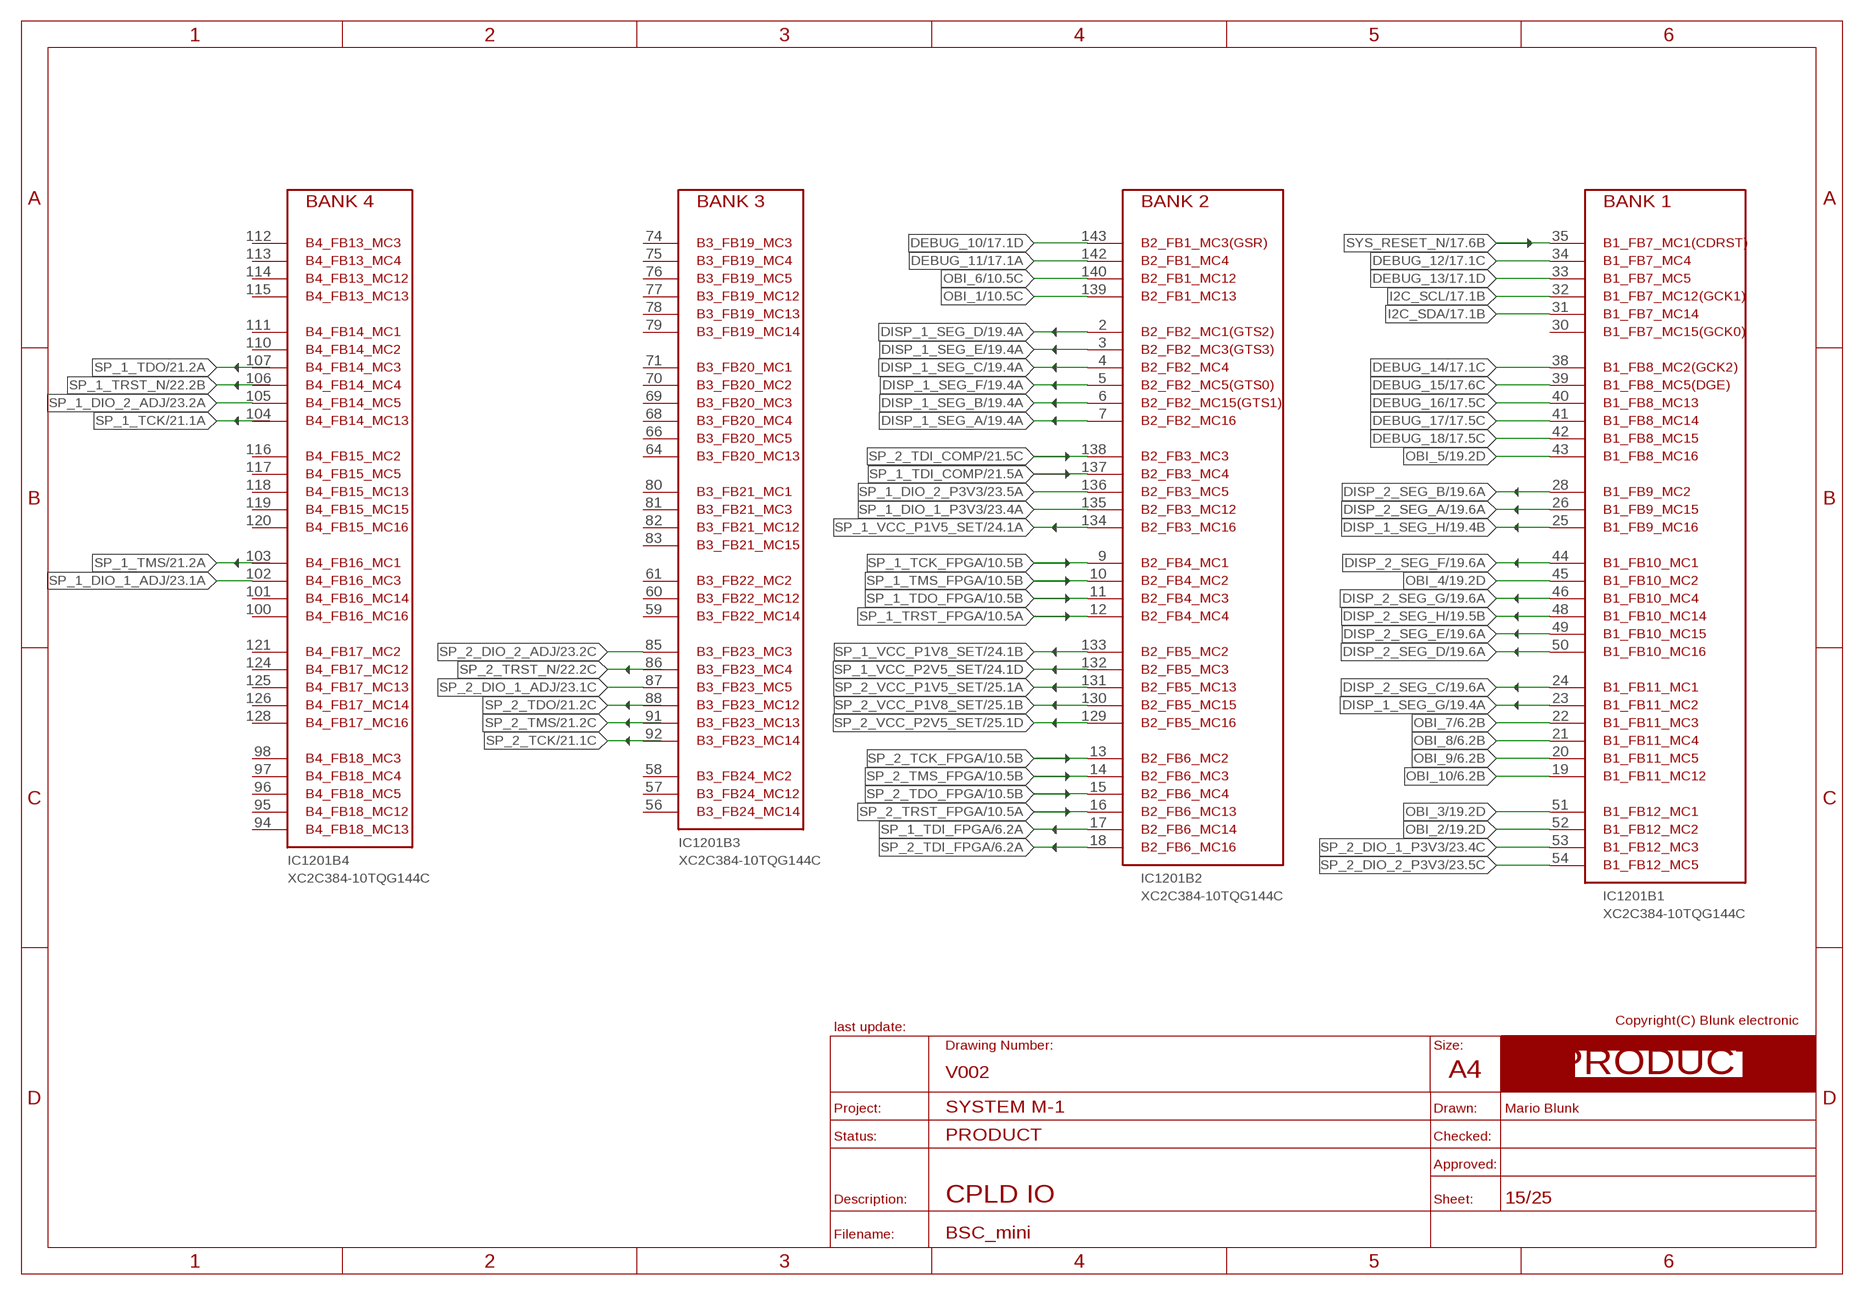
[diagram p14: schematic, sheet 15]
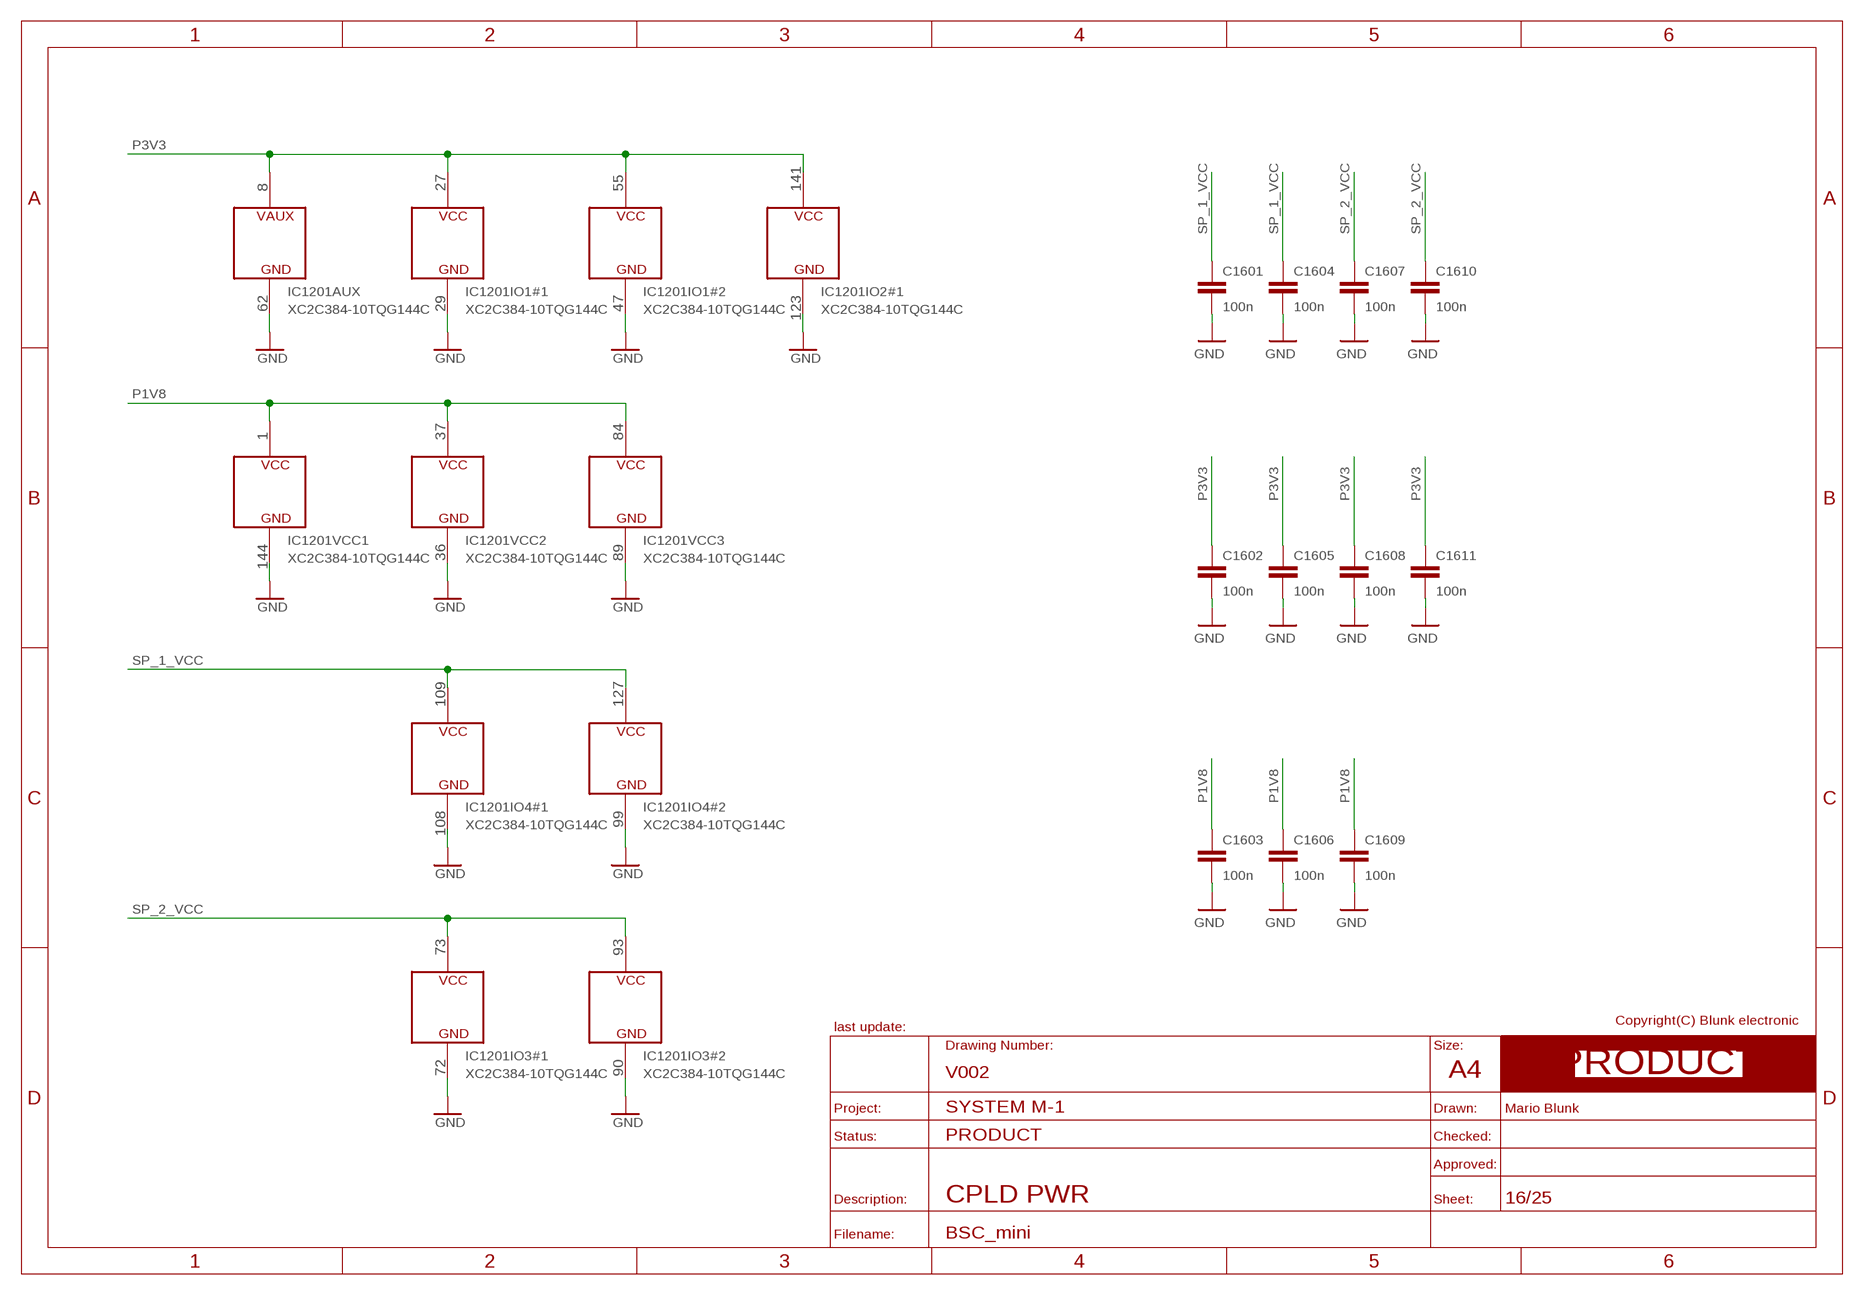
[diagram p15: schematic, sheet 16]
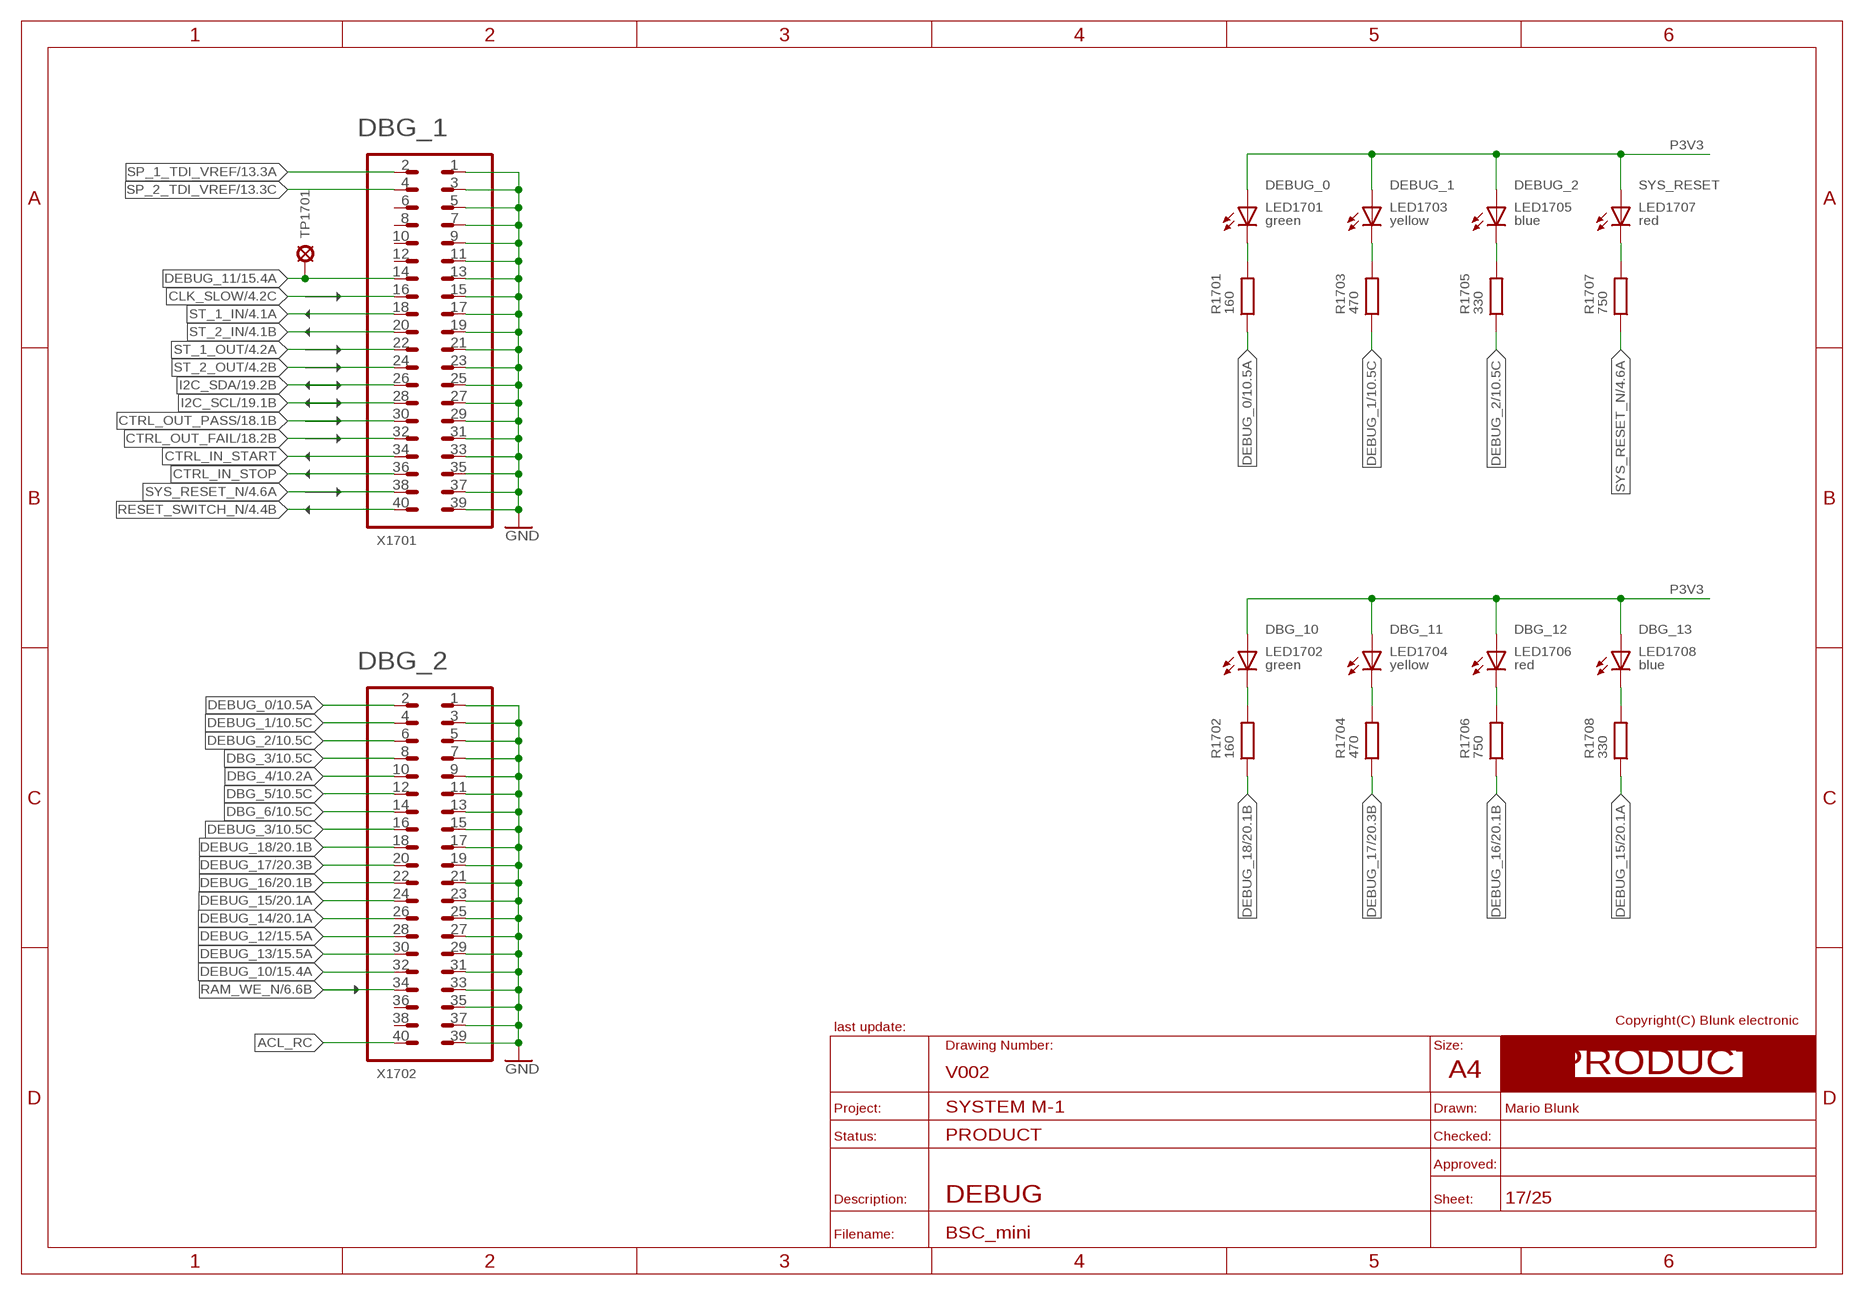
[diagram p16: schematic, sheet 17]
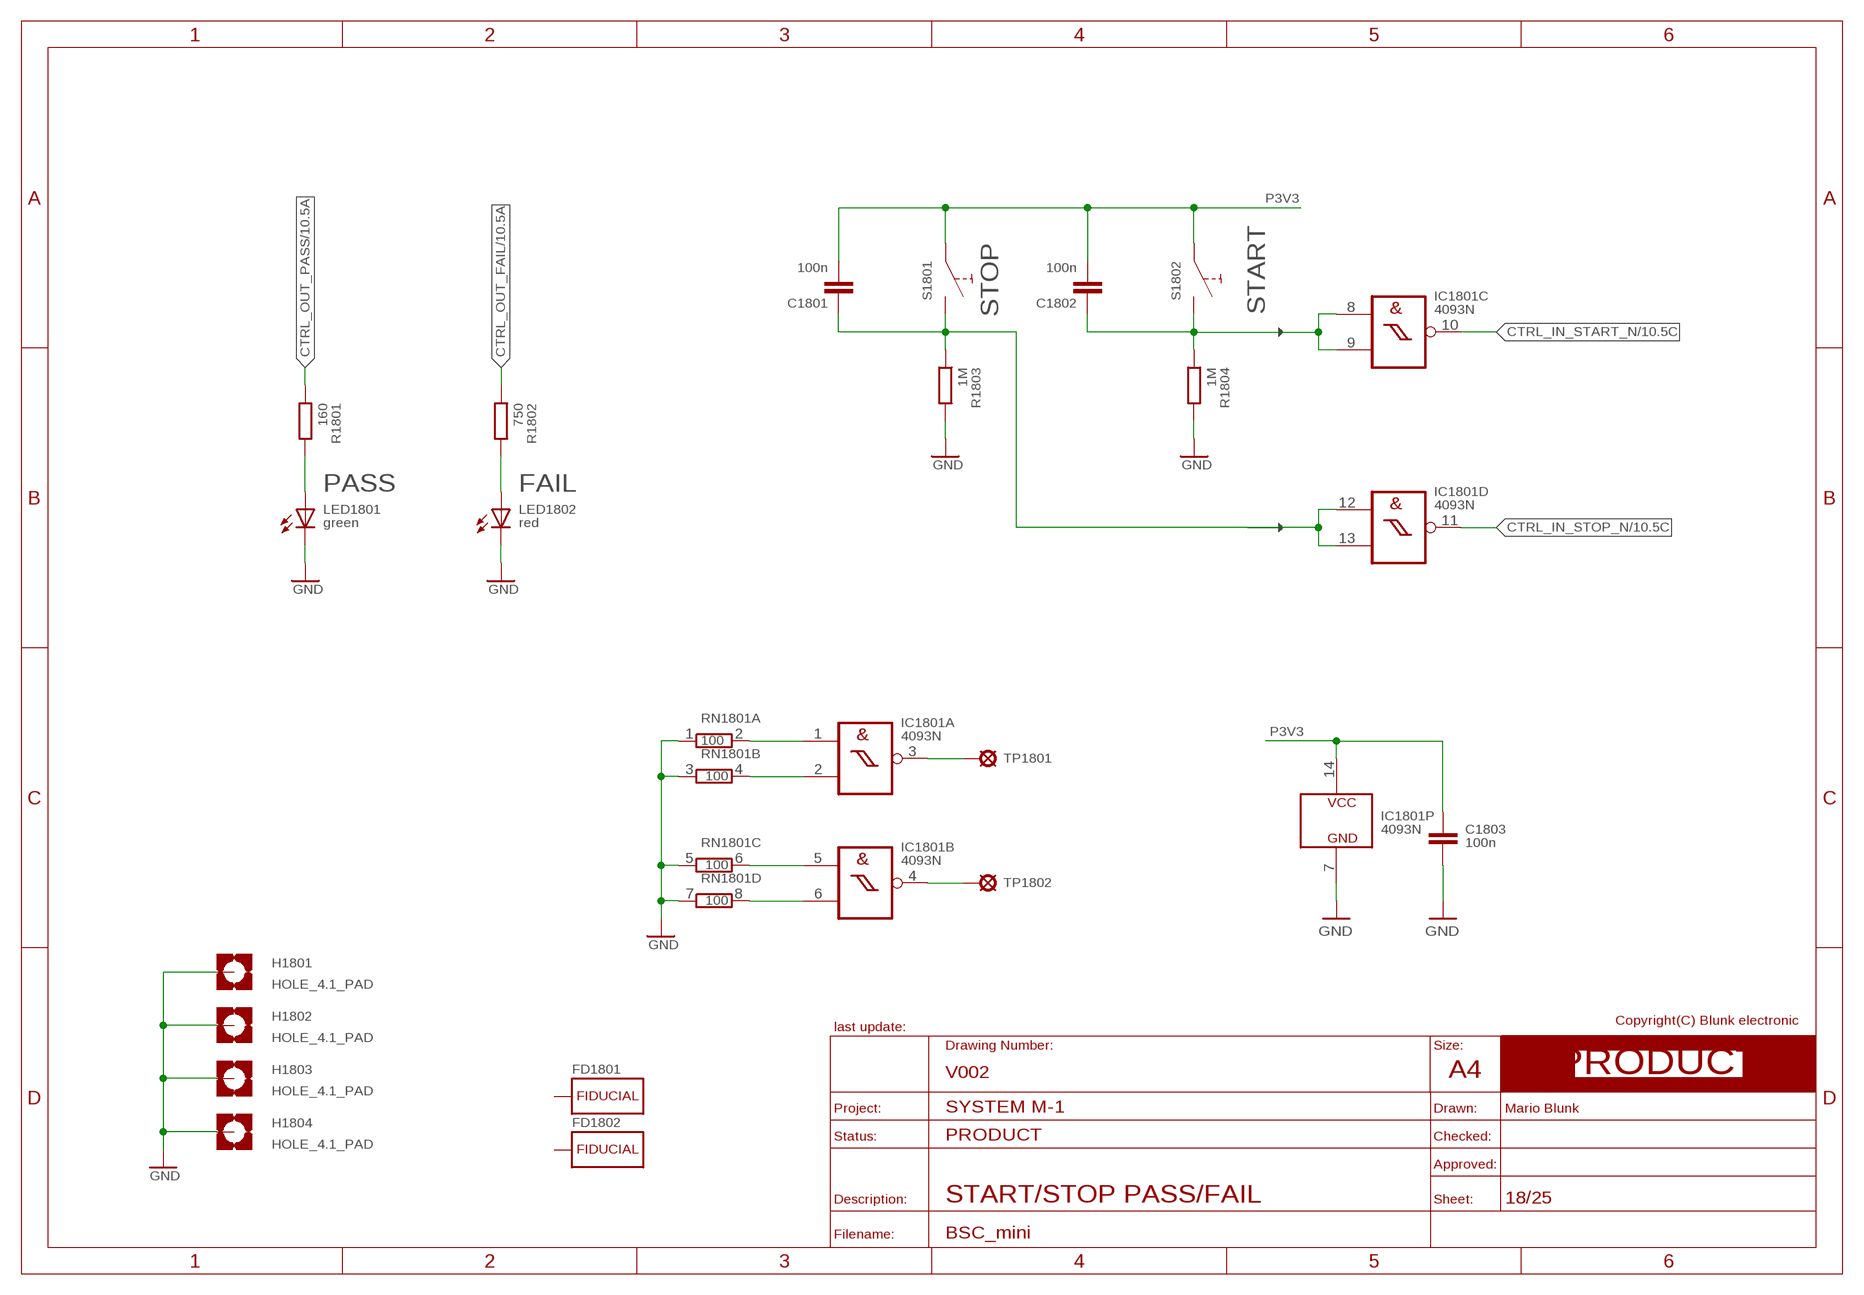
[diagram p17: schematic, sheet 18]
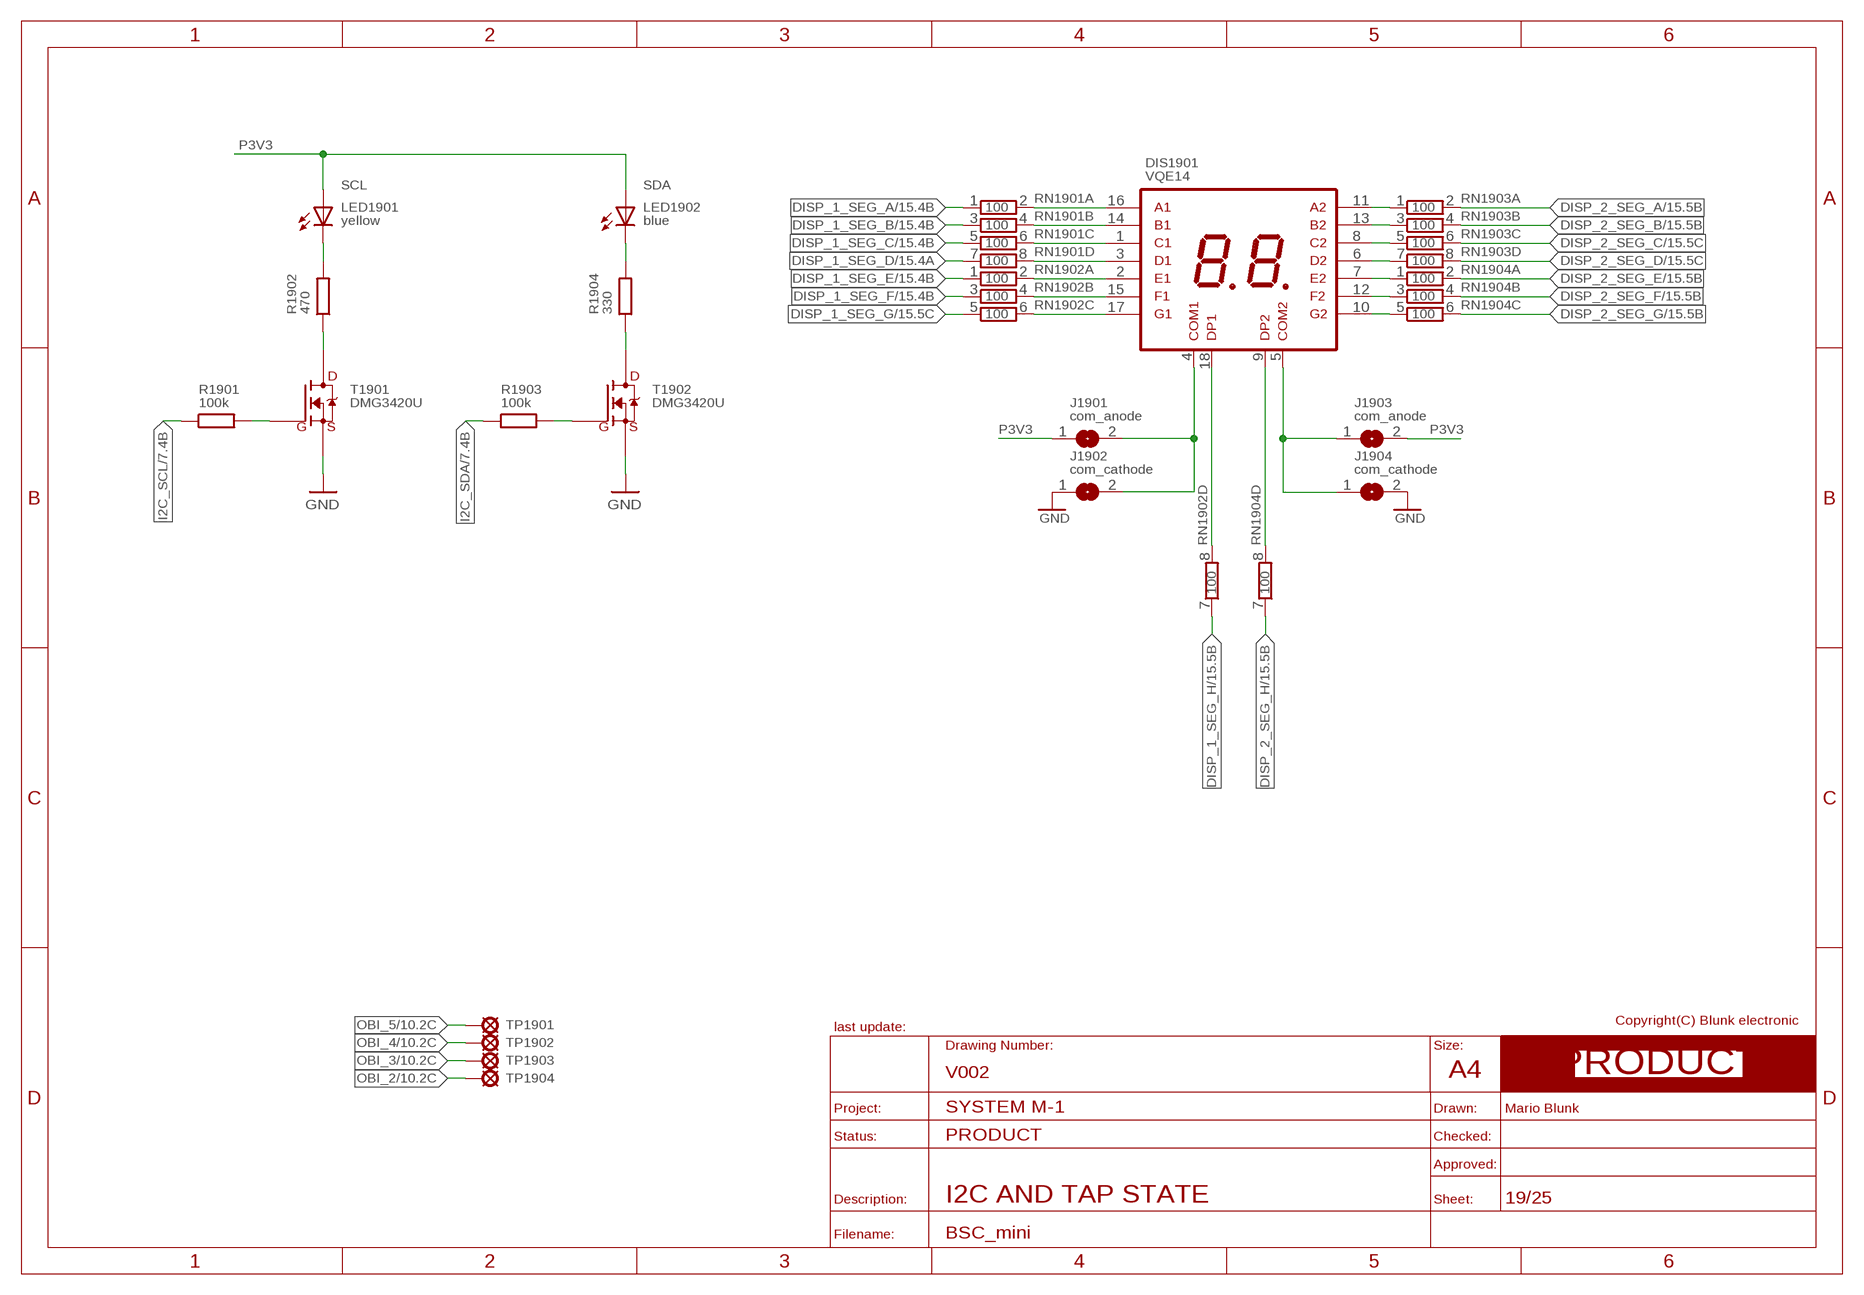
[diagram p18: schematic, sheet 19]
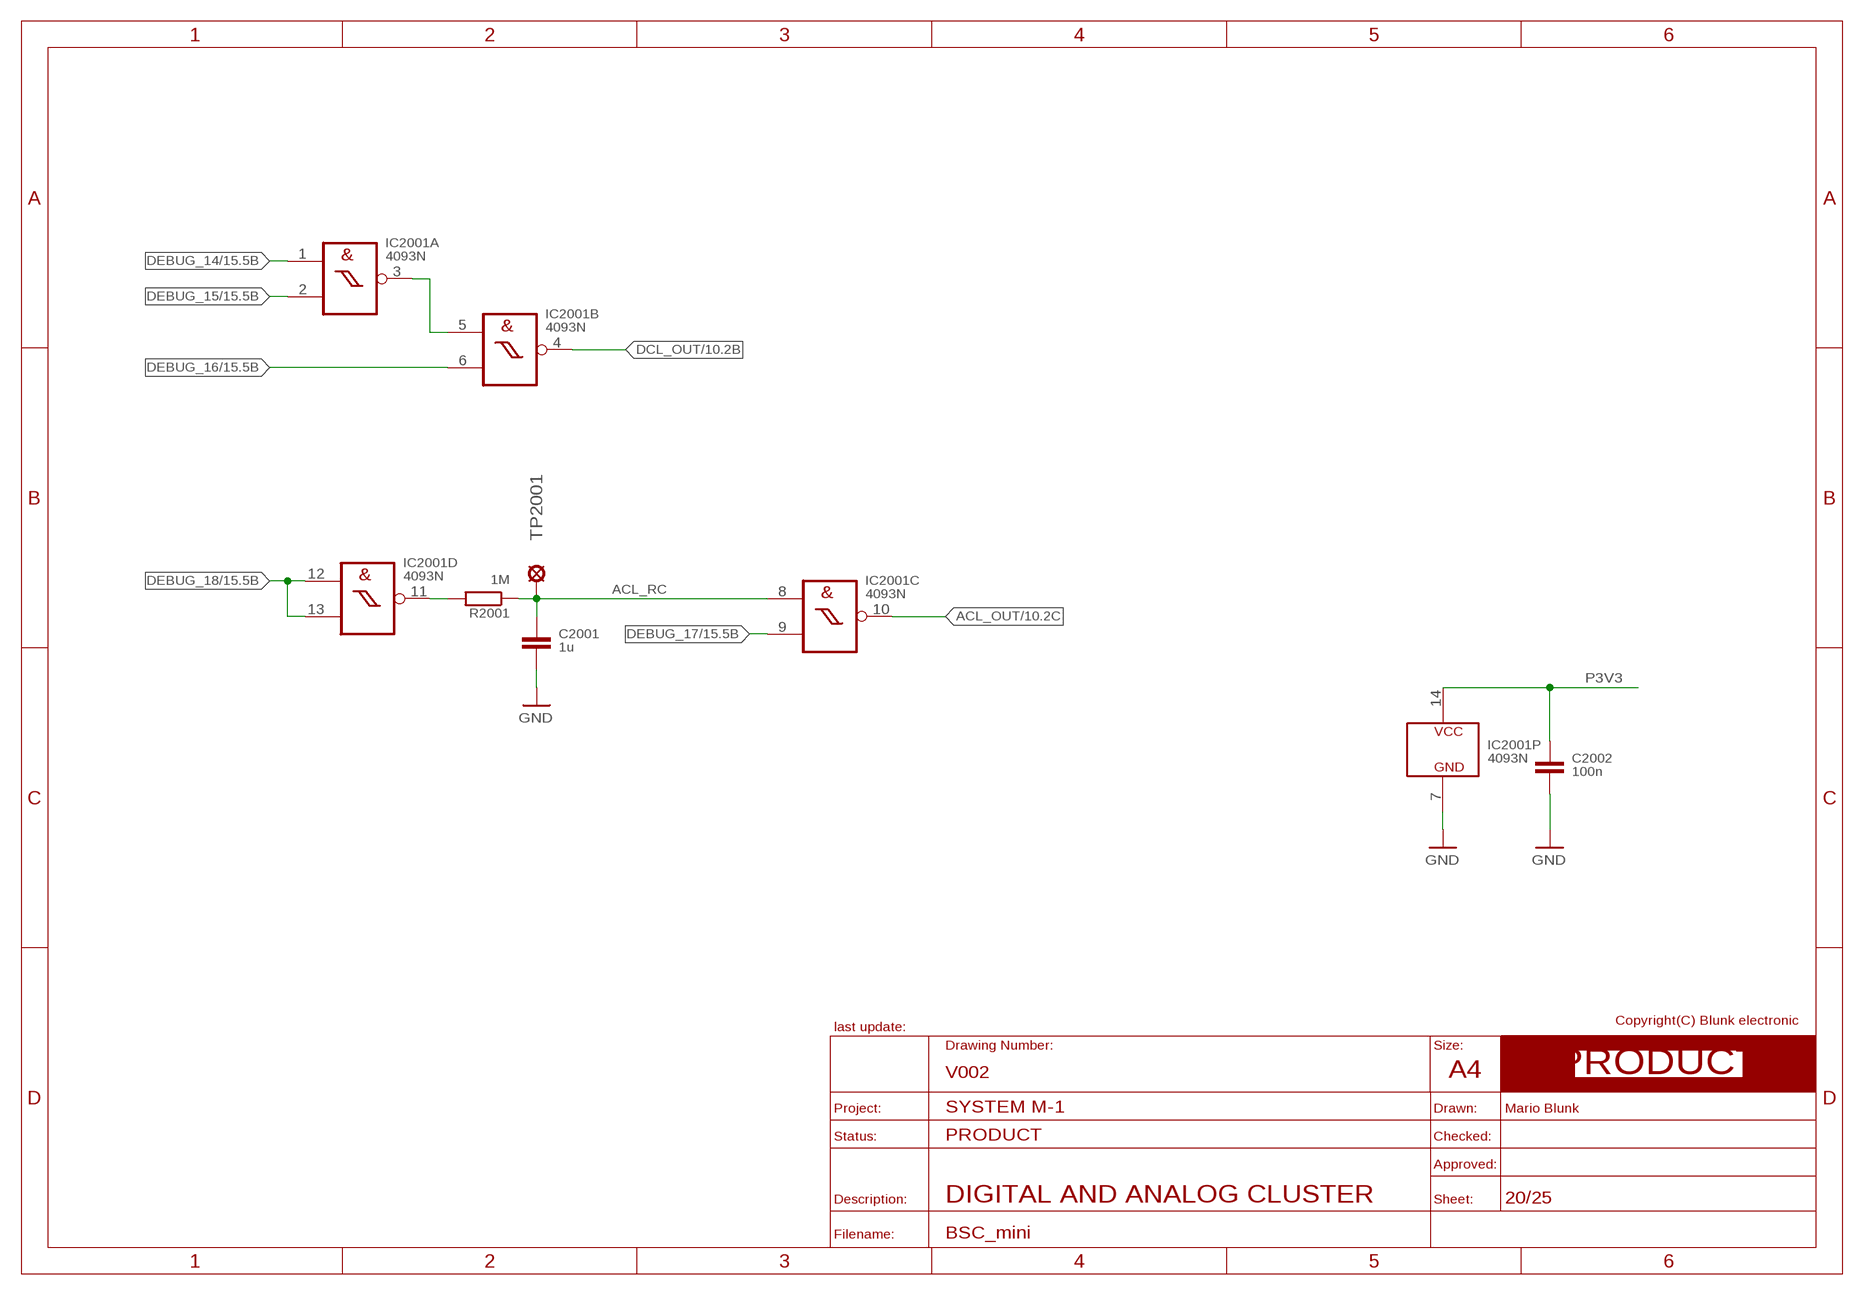
[diagram p19: schematic, sheet 20]
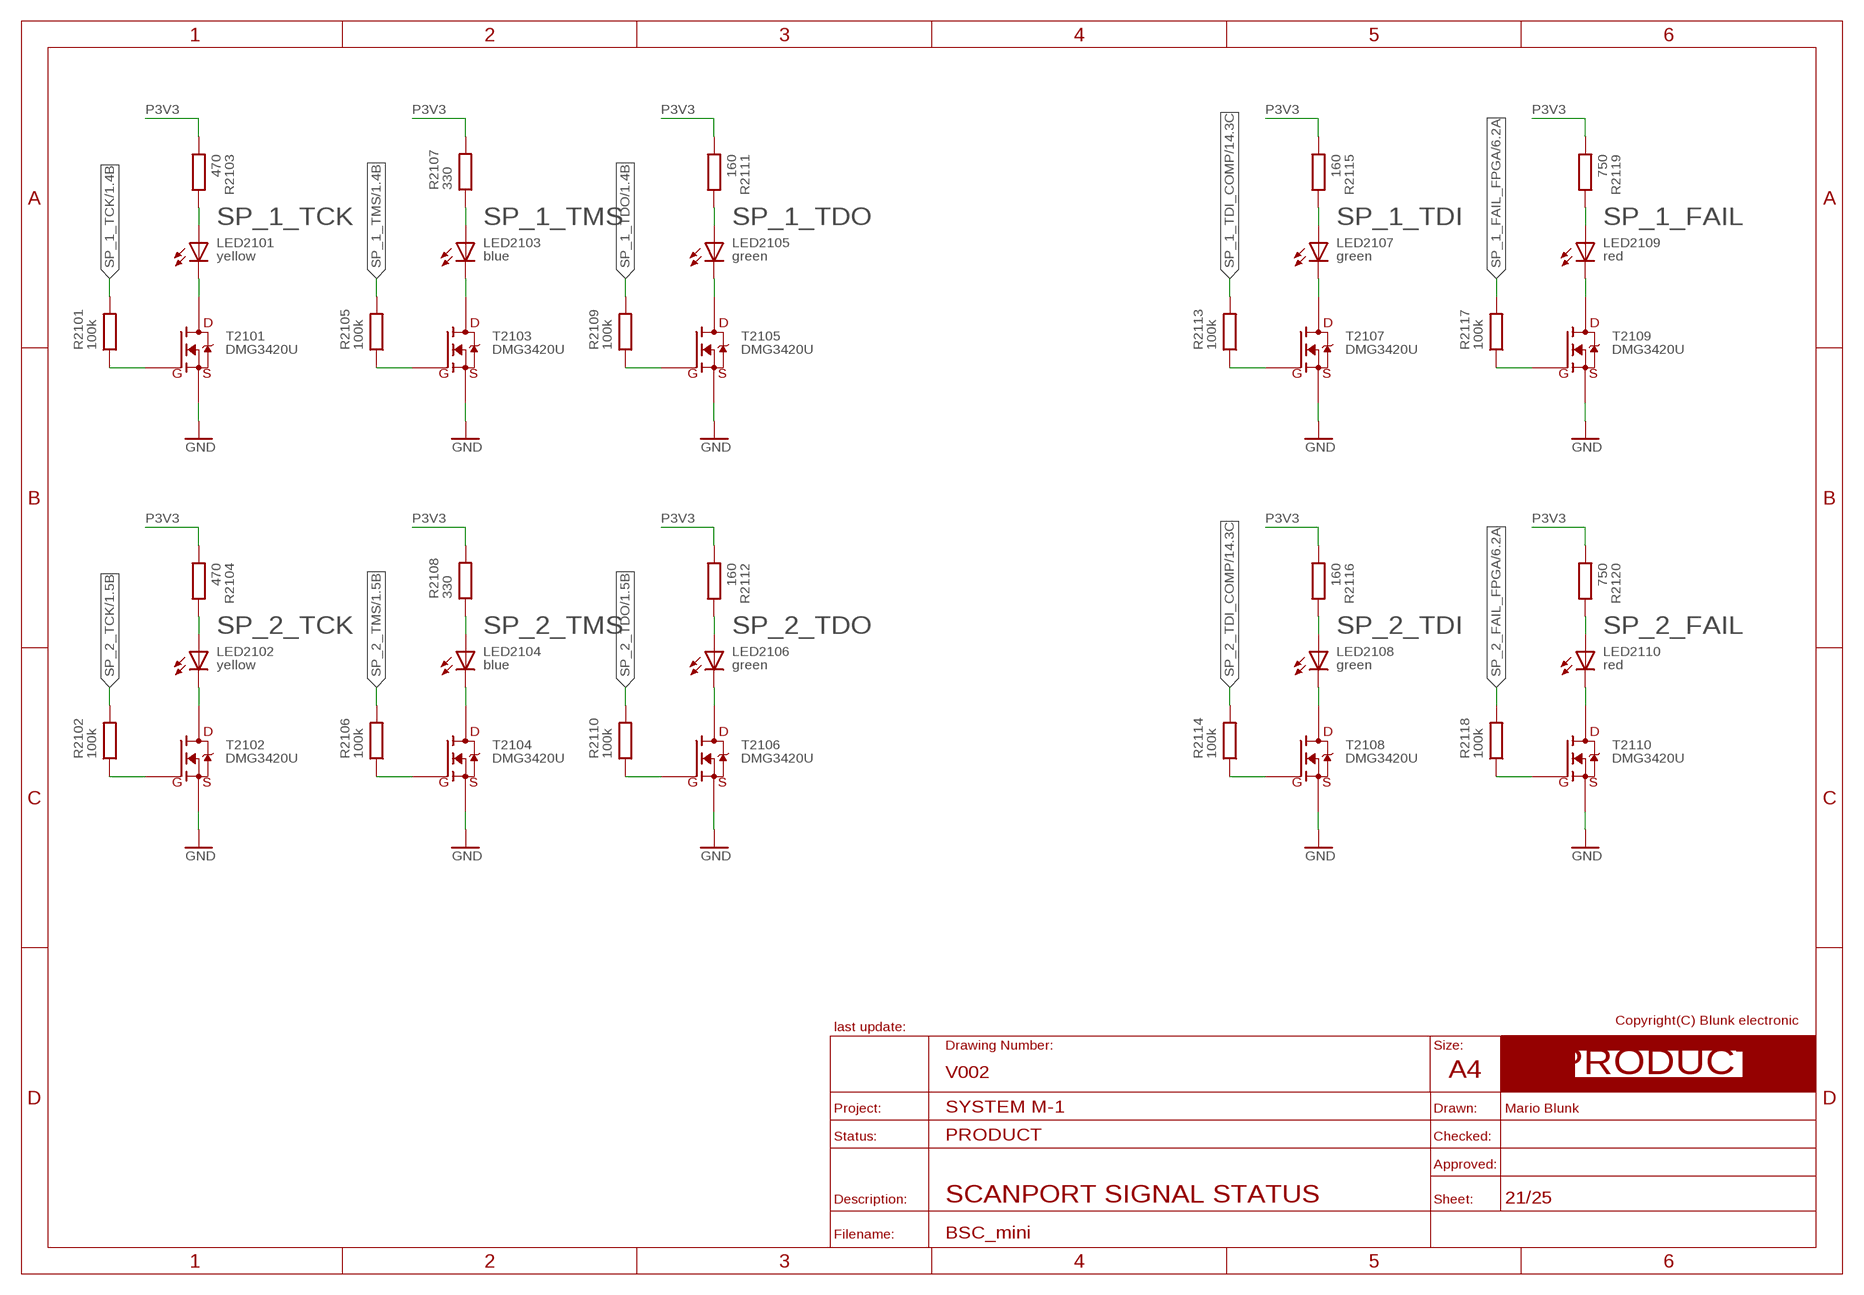
[diagram p20: schematic, sheet 21]
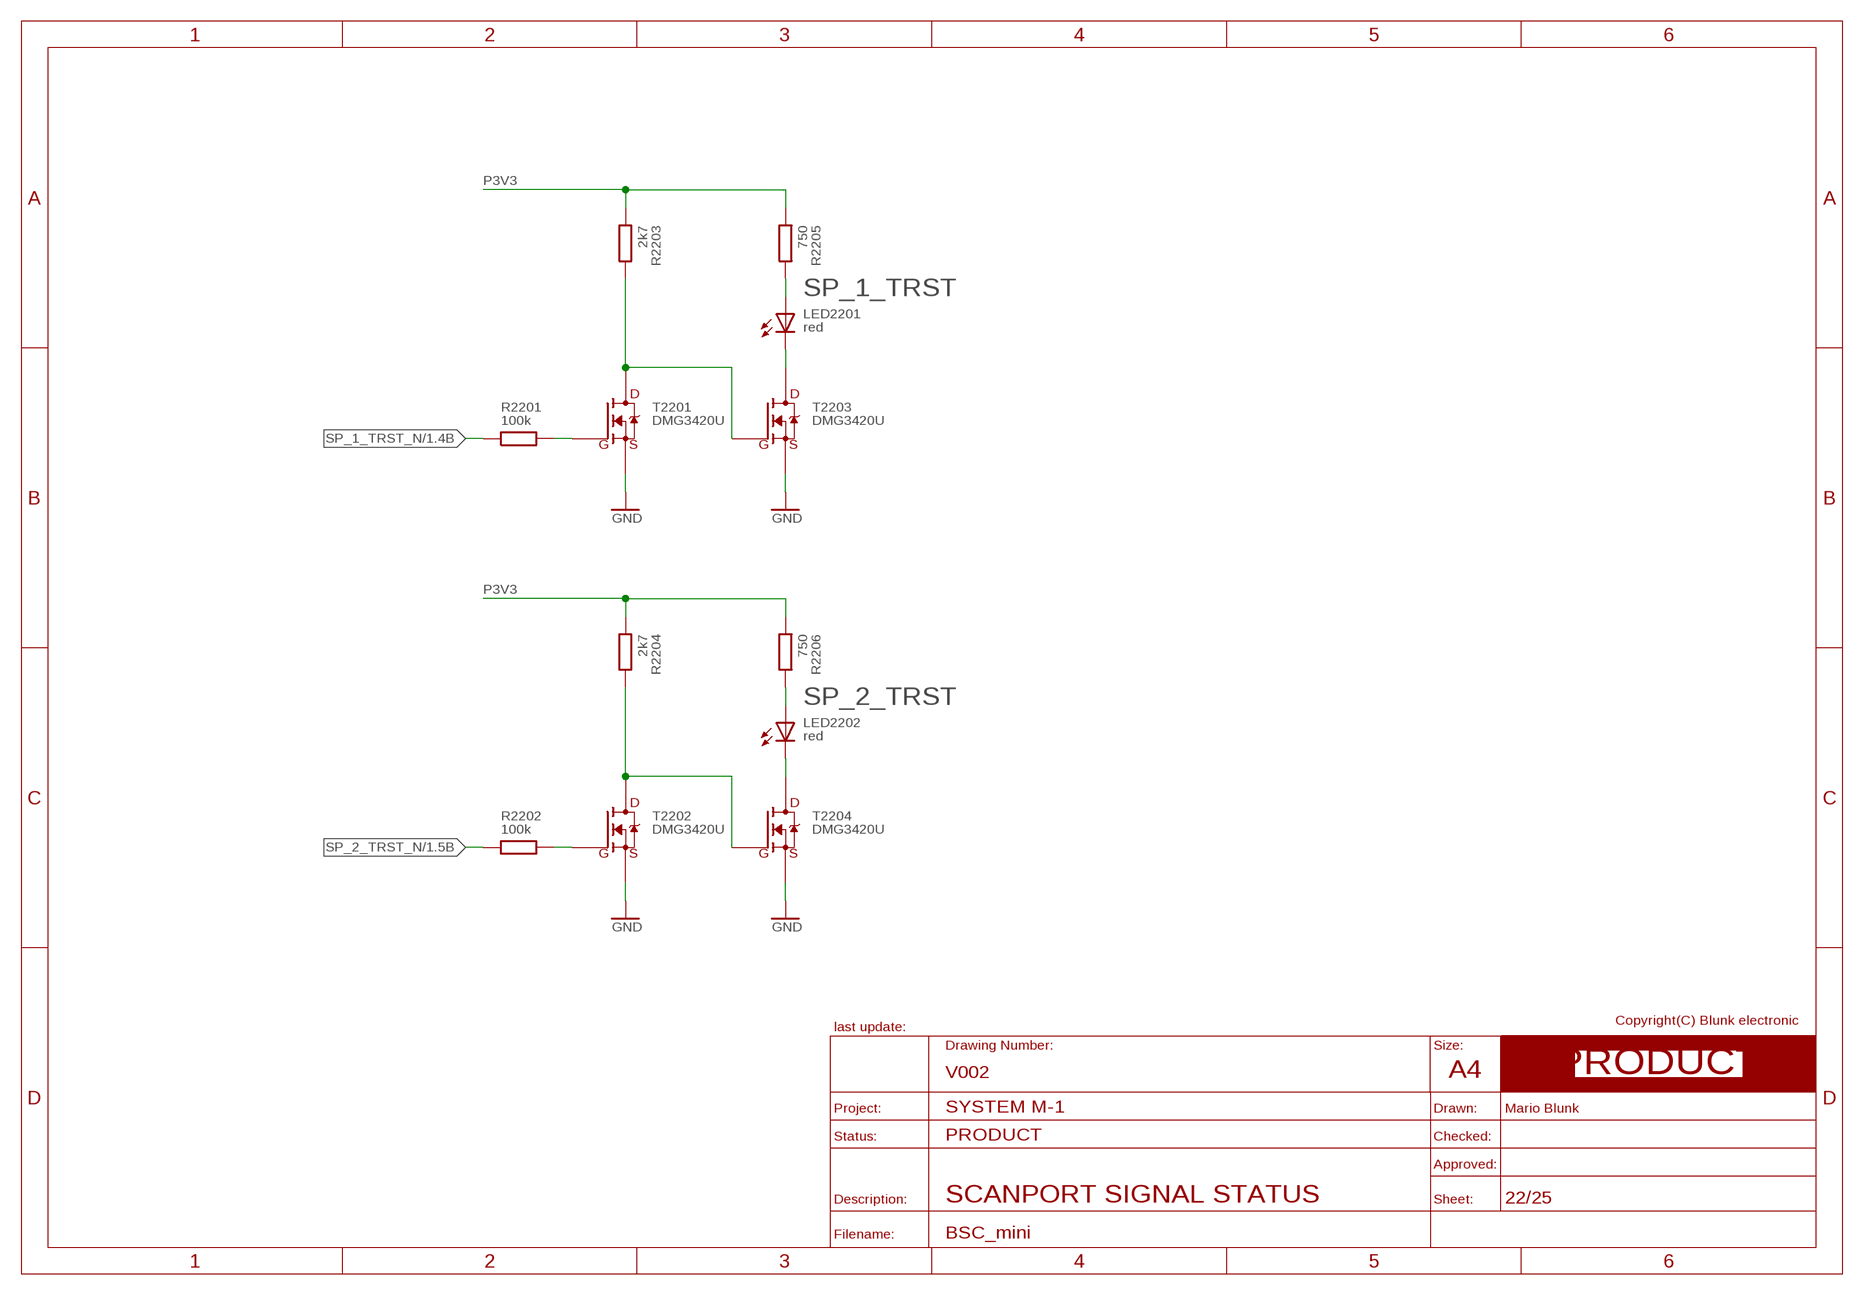
[diagram p21: schematic, sheet 22]
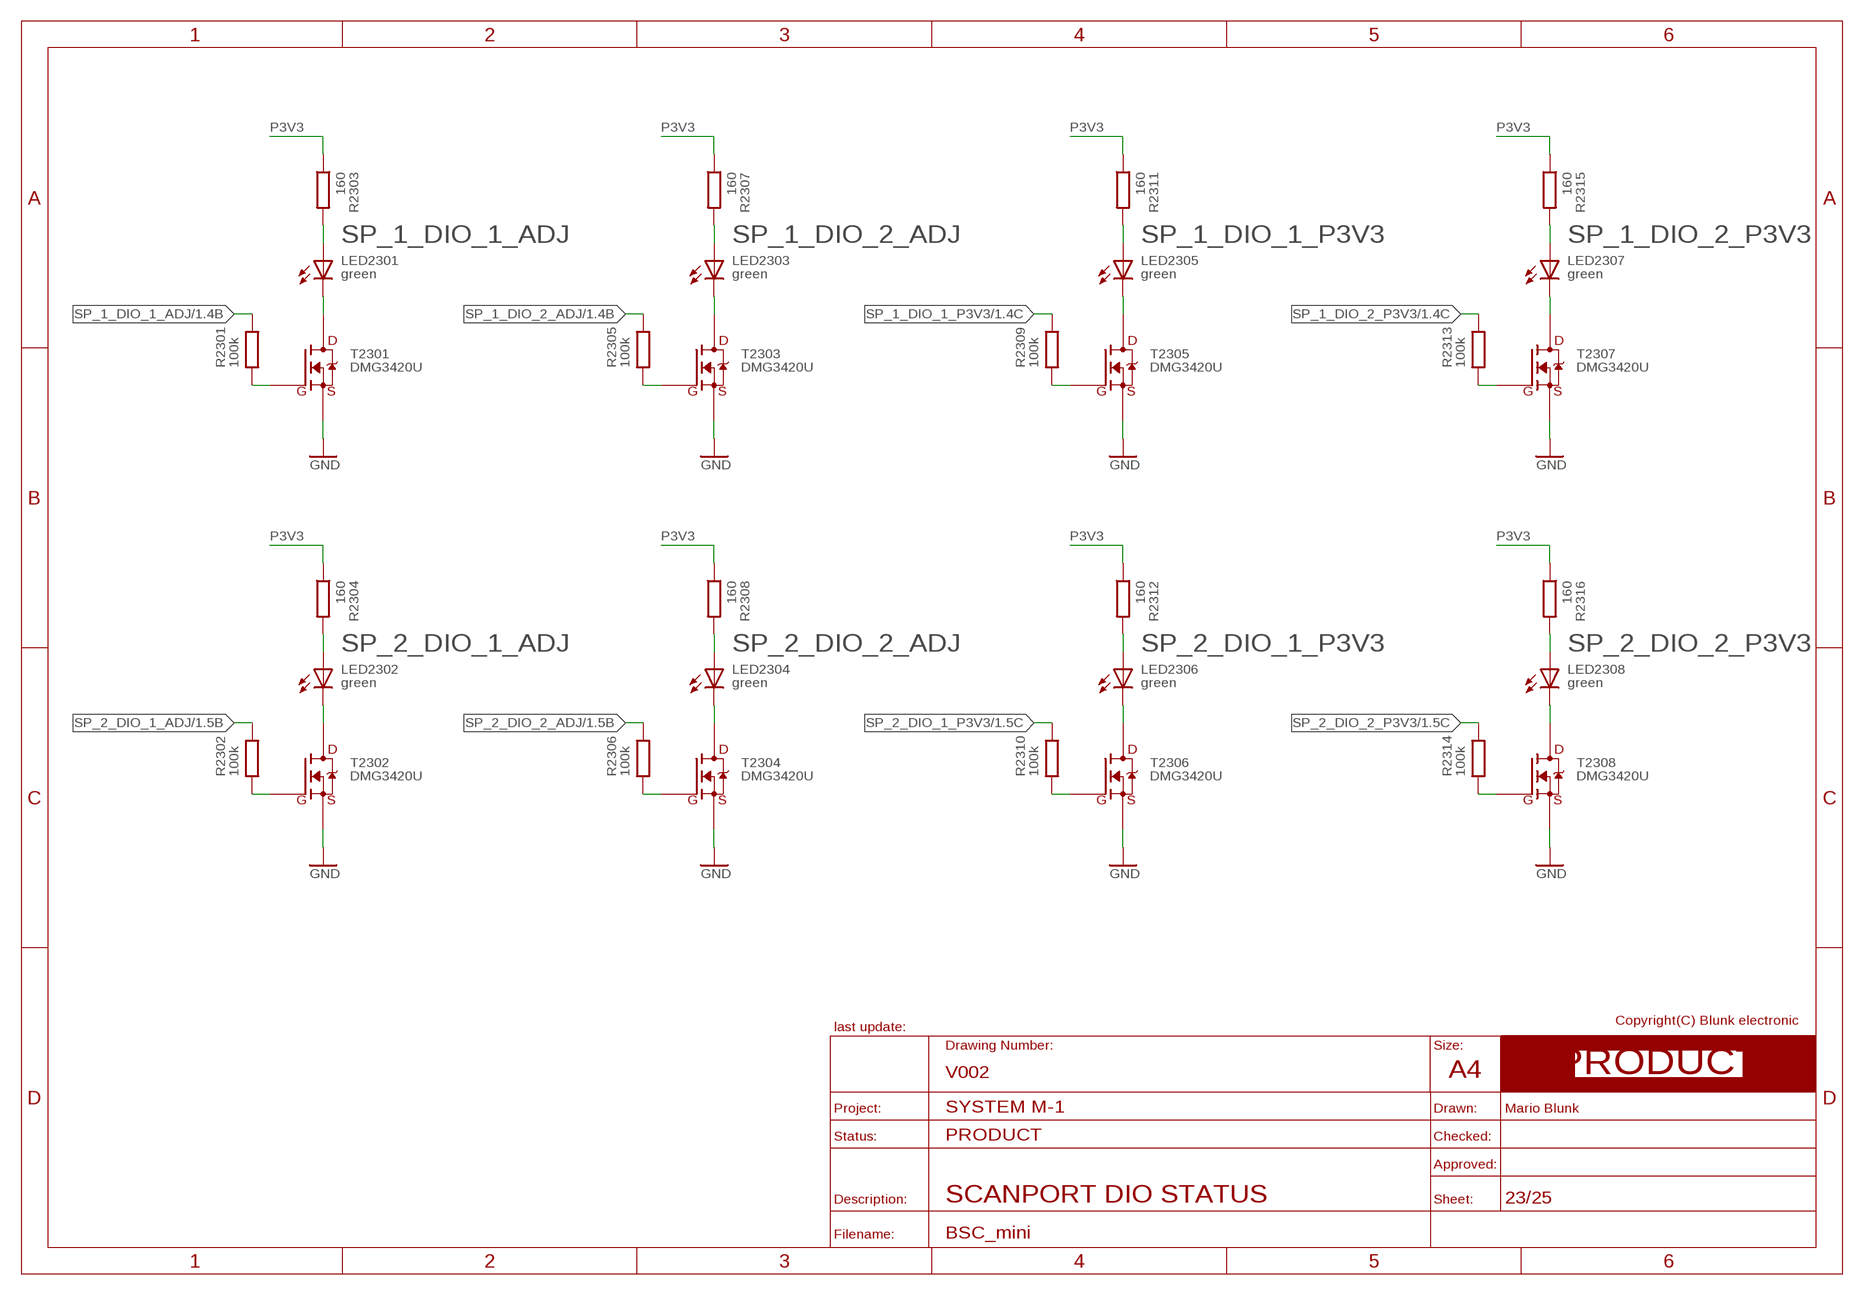
[diagram p22: schematic, sheet 23]
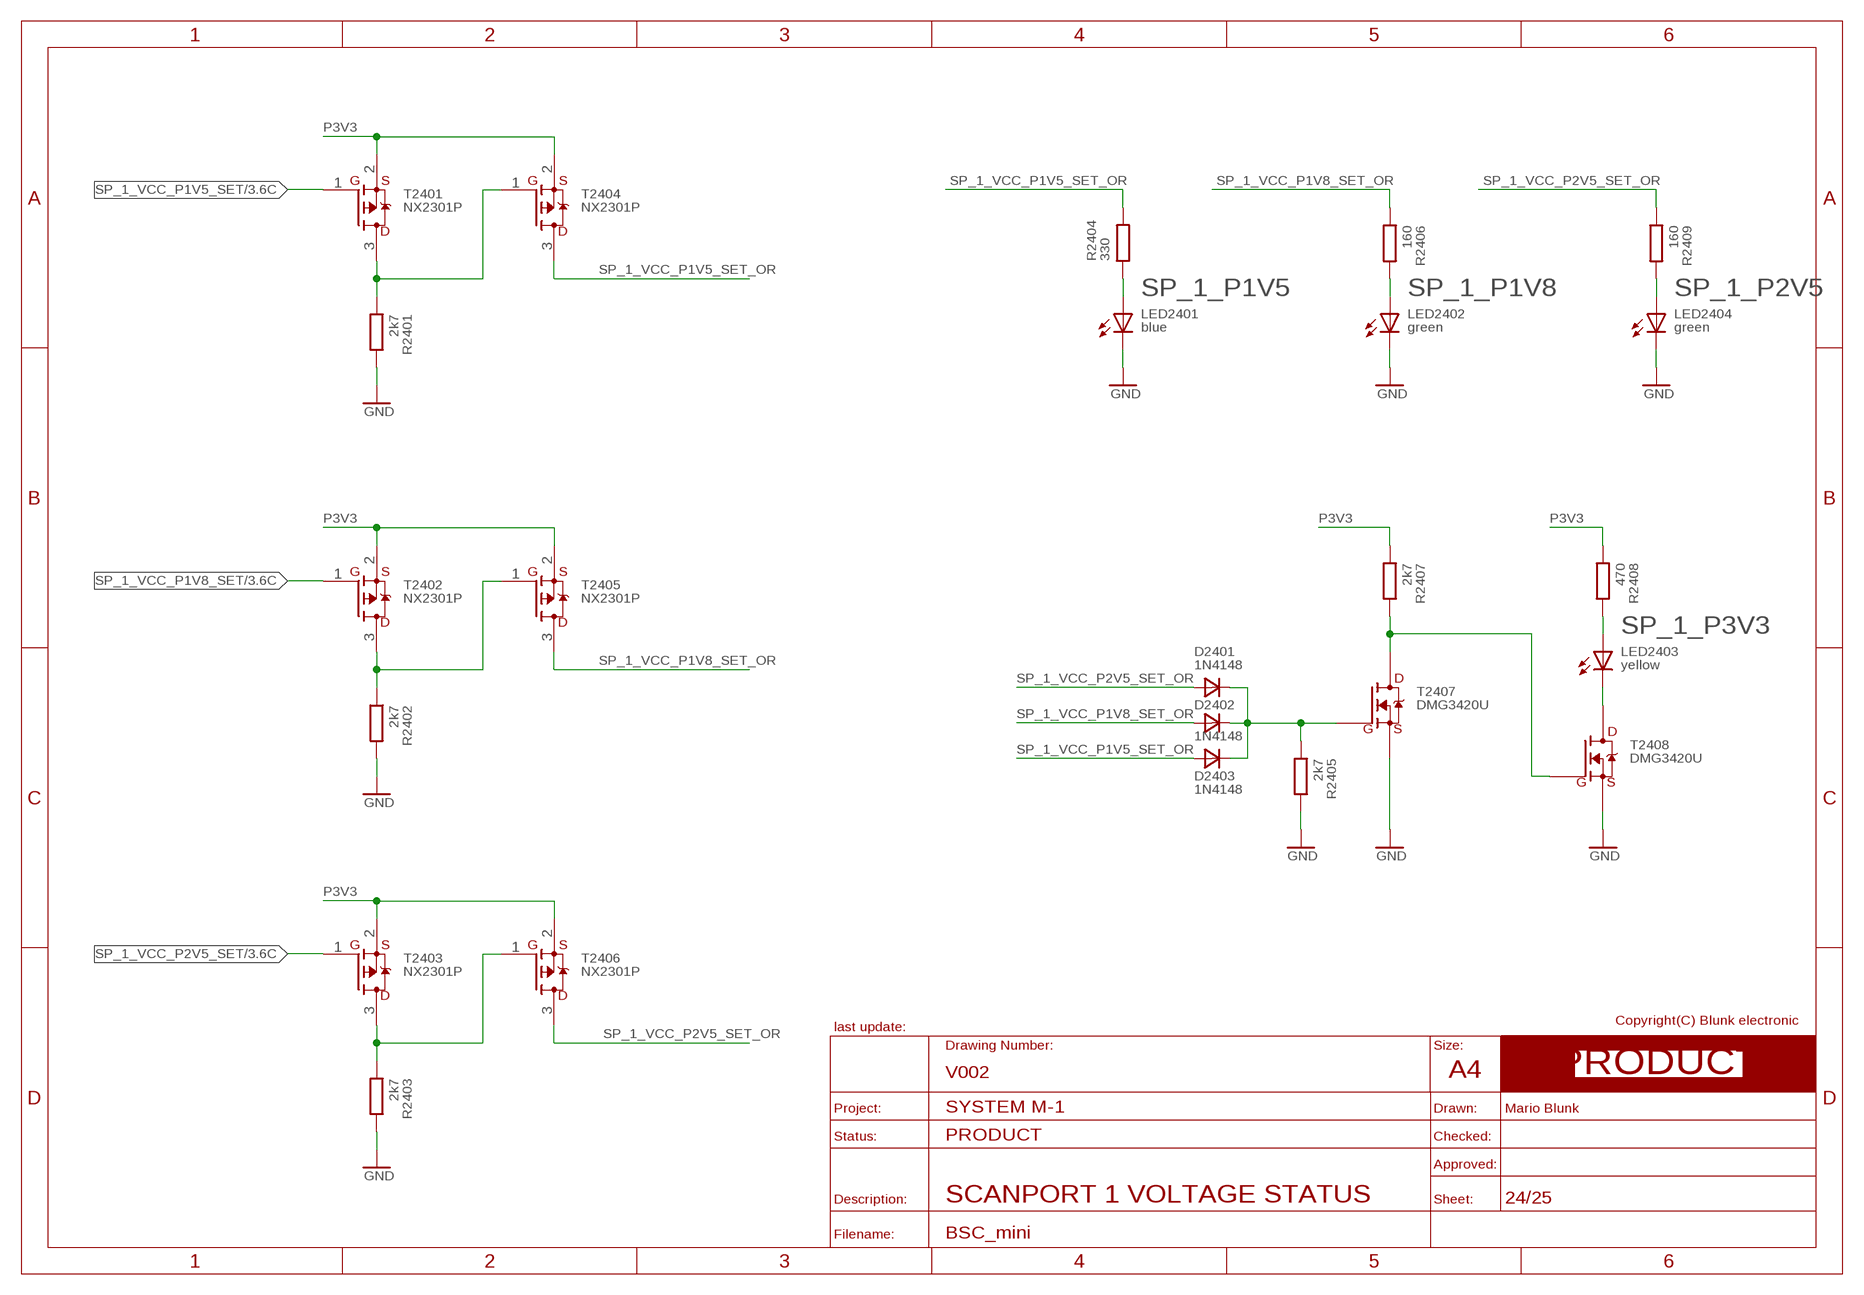
[diagram p23: schematic, sheet 24]
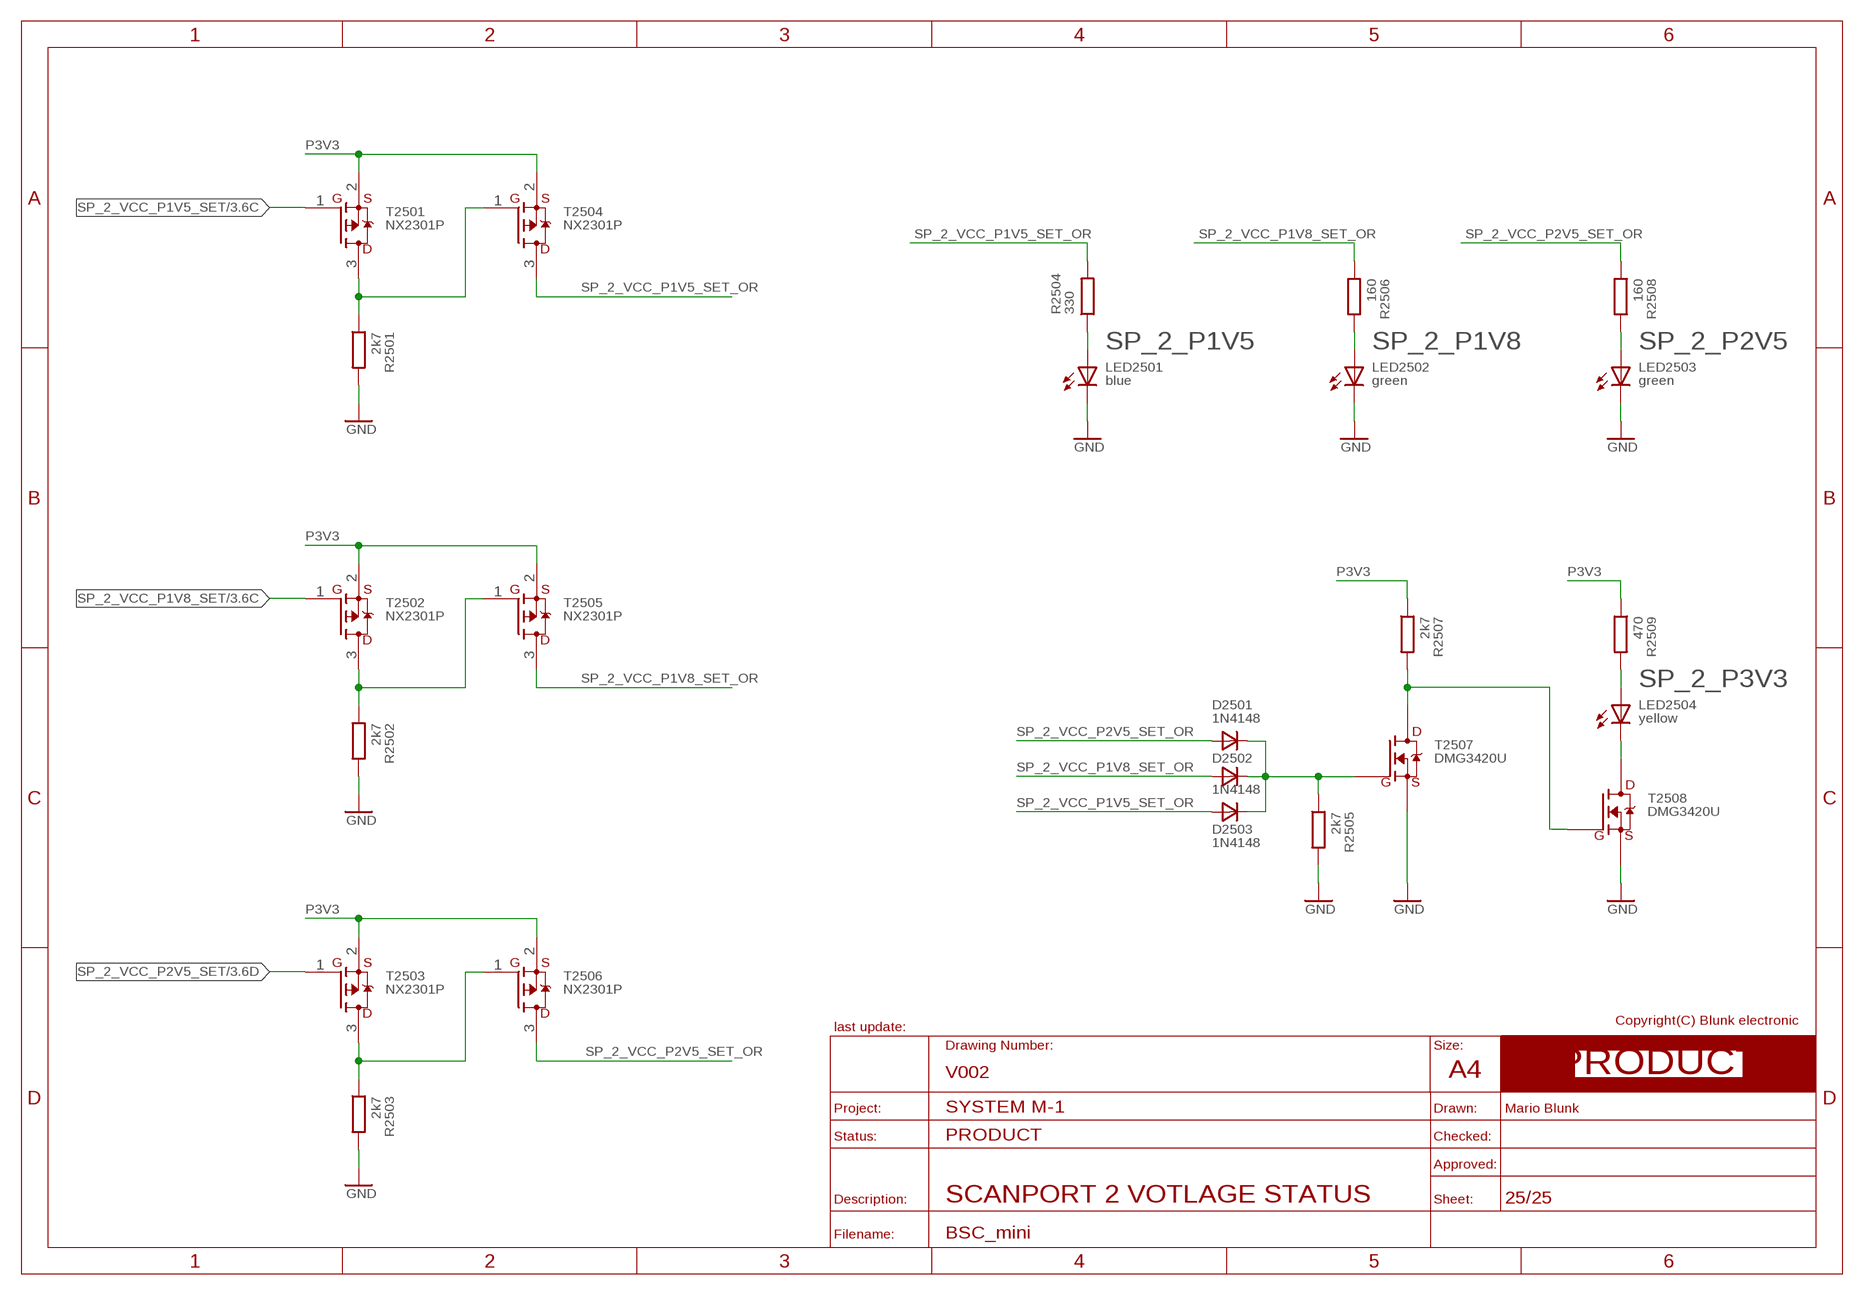
[diagram p24: schematic, sheet 25]

(export (version "E")
  (design (tool "Eeschema 10.0.6"))
  (components
    (comp (ref "IC801")
      (value "XC3S400-4PQG208C")
      (footprint "eagle-import:S_PQ208")
      (libsource (lib "eagle-import") (part "XC3S400-XPQ208C"))
    )
    (comp (ref "C101")
      (value "100u")
      (footprint "eagle-import:S_RADIAL_10MM")
      (fields (field (name "PART_CODE_BEL") "C_PAC_S_RADIAL_10mm_VAL_100u_Vmax_50V"))
      (libsource (lib "eagle-import") (part "C_POL_S_RAD_10MM"))
    )
    (comp (ref "D101")
      (value "S1A")
      (footprint "eagle-import:S_DO214AC")
      (fields (field (name "PART_CODE_BEL") "D_PAC_S_DO214AC_VAL_S1A"))
      (libsource (lib "eagle-import") (part "SINGLE_S_DO214AC"))
    )
    (comp (ref "X101")
      (value "CLAMP_1X2-T-2.5MM")
      (footprint "eagle-import:T_WIRE_CLAMP_1X2_PITCH_2MM5")
      (fields (field (name "FUNCTION") "PWR_IN"))
      (libsource (lib "eagle-import") (part "CLAMP_1X2-T-2.5MM"))
    )
    (comp (ref "X102")
      (value "MALE_2X5-T-VERTICAL_2MM54")
      (footprint "eagle-import:T_MALE_2X5_VERTICAL_PITCH_2MM54")
      (fields (field (name "FUNCTION") "UART"))
      (libsource (lib "eagle-import") (part "MALE_2X5-T-VERTICAL_2MM54"))
    )
    (comp (ref "X103")
      (value "MALE_1X3")
      (footprint "eagle-import:T_MALE_3X1_VERTICAL")
      (fields (field (name "FUNCTION") "GND"))
      (libsource (lib "eagle-import") (part "MALE_1X3"))
    )
    (comp (ref "X104")
      (value "MALE_2X13-T-VERTICAL_PITCH_2MM54")
      (footprint "eagle-import:T_MALE_2X13_VERTICAL_PITCH_2MM54")
      (fields (field (name "FUNCTION") "SCANPORT_1"))
      (libsource (lib "eagle-import") (part "MALE_2X13-T-VERTICAL_PITCH_2MM54"))
    )
    (comp (ref "X105")
      (value "MALE_1X3")
      (footprint "eagle-import:T_MALE_3X1_VERTICAL")
      (fields (field (name "FUNCTION") "GND"))
      (libsource (lib "eagle-import") (part "MALE_1X3"))
    )
    (comp (ref "X106")
      (value "MALE_2X13-T-VERTICAL_PITCH_2MM54")
      (footprint "eagle-import:T_MALE_2X13_VERTICAL_PITCH_2MM54")
      (fields (field (name "FUNCTION") "SCANPORT_2"))
      (libsource (lib "eagle-import") (part "MALE_2X13-T-VERTICAL_PITCH_2MM54"))
    )
    (comp (ref "X107")
      (value "MALE_1X3")
      (footprint "eagle-import:T_MALE_3X1_VERTICAL")
      (fields (field (name "FUNCTION") "GND"))
      (libsource (lib "eagle-import") (part "MALE_1X3"))
    )
    (comp (ref "IC1201")
      (value "XC2C384-10TQG144C")
      (footprint "eagle-import:S_TQFP144")
      (fields (field (name "PART_CODE_BEL") "IC_PAC_S_TQFP144_VAL_XC2C384-10TQG144C"))
      (libsource (lib "eagle-import") (part "XC2C384-XXTQG144X"))
    )
    (comp (ref "C801")
      (value "100n")
      (footprint "eagle-import:S_0805")
      (fields (field (name "PART_CODE_BEL") "C_PAC_S_0805_VAL_100n"))
      (libsource (lib "eagle-import") (part "C_S_0805"))
    )
    (comp (ref "C802")
      (value "100n")
      (footprint "eagle-import:S_0805")
      (fields (field (name "PART_CODE_BEL") "C_PAC_S_0805_VAL_100n"))
      (libsource (lib "eagle-import") (part "C_S_0805"))
    )
    (comp (ref "C803")
      (value "100n")
      (footprint "eagle-import:S_0805")
      (fields (field (name "PART_CODE_BEL") "C_PAC_S_0805_VAL_100n"))
      (libsource (lib "eagle-import") (part "C_S_0805"))
    )
    (comp (ref "C804")
      (value "100n")
      (footprint "eagle-import:S_0805")
      (fields (field (name "PART_CODE_BEL") "C_PAC_S_0805_VAL_100n"))
      (libsource (lib "eagle-import") (part "C_S_0805"))
    )
    (comp (ref "C805")
      (value "100n")
      (footprint "eagle-import:S_0805")
      (fields (field (name "PART_CODE_BEL") "C_PAC_S_0805_VAL_100n"))
      (libsource (lib "eagle-import") (part "C_S_0805"))
    )
    (comp (ref "C806")
      (value "100n")
      (footprint "eagle-import:S_0805")
      (fields (field (name "PART_CODE_BEL") "C_PAC_S_0805_VAL_100n"))
      (libsource (lib "eagle-import") (part "C_S_0805"))
    )
    (comp (ref "C807")
      (value "100n")
      (footprint "eagle-import:S_0805")
      (fields (field (name "PART_CODE_BEL") "C_PAC_S_0805_VAL_100n"))
      (libsource (lib "eagle-import") (part "C_S_0805"))
    )
    (comp (ref "C808")
      (value "100n")
      (footprint "eagle-import:S_0805")
      (fields (field (name "PART_CODE_BEL") "C_PAC_S_0805_VAL_100n"))
      (libsource (lib "eagle-import") (part "C_S_0805"))
    )
    (comp (ref "C809")
      (value "100n")
      (footprint "eagle-import:S_0805")
      (fields (field (name "PART_CODE_BEL") "C_PAC_S_0805_VAL_100n"))
      (libsource (lib "eagle-import") (part "C_S_0805"))
    )
    (comp (ref "C810")
      (value "100n")
      (footprint "eagle-import:S_0805")
      (fields (field (name "PART_CODE_BEL") "C_PAC_S_0805_VAL_100n"))
      (libsource (lib "eagle-import") (part "C_S_0805"))
    )
    (comp (ref "C811")
      (value "100n")
      (footprint "eagle-import:S_0805")
      (fields (field (name "PART_CODE_BEL") "C_PAC_S_0805_VAL_100n"))
      (libsource (lib "eagle-import") (part "C_S_0805"))
    )
    (comp (ref "IC802")
      (value "XCF04SVOG20C")
      (footprint "eagle-import:S_TSSOP20")
      (libsource (lib "eagle-import") (part "XCFXXSVOG20C"))
    )
    (comp (ref "J801")
      (value "JUMPER_2X10-T-VERTICAL")
      (footprint "eagle-import:T_MALE_2X10_VERTICAL_GRID_2.54MM")
      (fields
        (field (name "FUNCTION") "CONF")
        (field (name "PART_CODE_BEL") "J_PAC_T_MALE_2X10_VERTICAL_PITCH_2mm54")
      )
      (libsource (lib "eagle-import") (part "JUMPER_2X10-T-VERTICAL"))
    )
    (comp (ref "R801")
      (value "4k7")
      (footprint "eagle-import:S_0805")
      (fields (field (name "PART_CODE_BEL") "R_PAC_S_0805_VAL_4k7"))
      (libsource (lib "eagle-import") (part "R_S_0805"))
    )
    (comp (ref "R802")
      (value "4k7")
      (footprint "eagle-import:S_0805")
      (fields (field (name "PART_CODE_BEL") "R_PAC_S_0805_VAL_4k7"))
      (libsource (lib "eagle-import") (part "R_S_0805"))
    )
    (comp (ref "R803")
      (value "4k7")
      (footprint "eagle-import:S_0805")
      (fields (field (name "PART_CODE_BEL") "R_PAC_S_0805_VAL_4k7"))
      (libsource (lib "eagle-import") (part "R_S_0805"))
    )
    (comp (ref "R804")
      (value "330")
      (footprint "eagle-import:S_0805")
      (fields (field (name "PART_CODE_BEL") "R_PAC_S_0805_VAL_330"))
      (libsource (lib "eagle-import") (part "R_S_0805"))
    )
    (comp (ref "R805")
      (value "330")
      (footprint "eagle-import:S_0805")
      (fields (field (name "PART_CODE_BEL") "R_PAC_S_0805_VAL_330"))
      (libsource (lib "eagle-import") (part "R_S_0805"))
    )
    (comp (ref "R806")
      (value "330")
      (footprint "eagle-import:S_0805")
      (fields (field (name "PART_CODE_BEL") "R_PAC_S_0805_VAL_330"))
      (libsource (lib "eagle-import") (part "R_S_0805"))
    )
    (comp (ref "R807")
      (value "330")
      (footprint "eagle-import:S_0805")
      (fields (field (name "PART_CODE_BEL") "R_PAC_S_0805_VAL_330"))
      (libsource (lib "eagle-import") (part "R_S_0805"))
    )
    (comp (ref "C2001")
      (value "1u")
      (footprint "eagle-import:S_0805")
      (fields (field (name "PART_CODE_BEL") "C_PAC_S_0805_VAL_1u"))
      (libsource (lib "eagle-import") (part "C_S_0805"))
    )
    (comp (ref "C2002")
      (value "100n")
      (footprint "eagle-import:S_0805")
      (fields (field (name "PART_CODE_BEL") "C_PAC_S_0805_VAL_100n"))
      (libsource (lib "eagle-import") (part "C_S_0805"))
    )
    (comp (ref "IC2001")
      (value "4093N")
      (footprint "eagle-import:T_NDIP14")
      (libsource (lib "eagle-import") (part "4093N"))
    )
    (comp (ref "R2001")
      (value "1M")
      (footprint "eagle-import:S_0805")
      (fields (field (name "PART_CODE_BEL") "R_PAC_S_0805_VAL_1M"))
      (libsource (lib "eagle-import") (part "R_S_0805"))
    )
    (comp (ref "TP2001")
      (value "clk_slow")
      (footprint "eagle-import:T_TEST_POINT_SMALL")
      (libsource (lib "eagle-import") (part "TEST_POINT_T_SMALL"))
    )
    (comp (ref "J501")
      (value "JUMPER_1X2-T-VERTICAL_GRID_2.54MM")
      (footprint "eagle-import:T_MALE_2X1_VERTICAL_PITCH_2MM54")
      (fields (field (name "FUNCTION") "TEST_1_VREF"))
      (libsource (lib "eagle-import") (part "JUMPER_1X2-T-VERTICAL_GRID_2.54MM"))
    )
    (comp (ref "R501")
      (value "330")
      (footprint "eagle-import:S_0805")
      (fields (field (name "PART_CODE_BEL") "R_PAC_S_0805_VAL_330"))
      (libsource (lib "eagle-import") (part "R_S_0805"))
    )
    (comp (ref "R502")
      (value "330")
      (footprint "eagle-import:S_0805")
      (fields (field (name "PART_CODE_BEL") "R_PAC_S_0805_VAL_330"))
      (libsource (lib "eagle-import") (part "R_S_0805"))
    )
    (comp (ref "RN501")
      (value "10k")
      (footprint "eagle-import:S_1206_4X")
      (fields (field (name "PART_CODE_BEL") "RN_PAC_S_1206_4X_VAL_10k"))
      (libsource (lib "eagle-import") (part "RN_4S_1206"))
    )
    (comp (ref "X501")
      (value "MALE_2X5-T-VERTICAL_2MM54")
      (footprint "eagle-import:T_MALE_2X5_VERTICAL_PITCH_2MM54")
      (fields (field (name "FUNCTION") "TEST_1"))
      (libsource (lib "eagle-import") (part "MALE_2X5-T-VERTICAL_2MM54"))
    )
    (comp (ref "X502")
      (value "MALE_2X5-T-VERTICAL_2MM54")
      (footprint "eagle-import:T_MALE_2X5_VERTICAL_PITCH_2MM54")
      (fields (field (name "FUNCTION") "TEST_1_DBG"))
      (libsource (lib "eagle-import") (part "MALE_2X5-T-VERTICAL_2MM54"))
    )
    (comp (ref "C1601")
      (value "100n")
      (footprint "eagle-import:S_0805")
      (fields (field (name "PART_CODE_BEL") "C_PAC_S_0805_VAL_100n"))
      (libsource (lib "eagle-import") (part "C_S_0805"))
    )
    (comp (ref "C1602")
      (value "100n")
      (footprint "eagle-import:S_0805")
      (fields (field (name "PART_CODE_BEL") "C_PAC_S_0805_VAL_100n"))
      (libsource (lib "eagle-import") (part "C_S_0805"))
    )
    (comp (ref "C1603")
      (value "100n")
      (footprint "eagle-import:S_0805")
      (fields (field (name "PART_CODE_BEL") "C_PAC_S_0805_VAL_100n"))
      (libsource (lib "eagle-import") (part "C_S_0805"))
    )
    (comp (ref "C1604")
      (value "100n")
      (footprint "eagle-import:S_0805")
      (fields (field (name "PART_CODE_BEL") "C_PAC_S_0805_VAL_100n"))
      (libsource (lib "eagle-import") (part "C_S_0805"))
    )
    (comp (ref "C1605")
      (value "100n")
      (footprint "eagle-import:S_0805")
      (fields (field (name "PART_CODE_BEL") "C_PAC_S_0805_VAL_100n"))
      (libsource (lib "eagle-import") (part "C_S_0805"))
    )
    (comp (ref "C1606")
      (value "100n")
      (footprint "eagle-import:S_0805")
      (fields (field (name "PART_CODE_BEL") "C_PAC_S_0805_VAL_100n"))
      (libsource (lib "eagle-import") (part "C_S_0805"))
    )
    (comp (ref "C1607")
      (value "100n")
      (footprint "eagle-import:S_0805")
      (fields (field (name "PART_CODE_BEL") "C_PAC_S_0805_VAL_100n"))
      (libsource (lib "eagle-import") (part "C_S_0805"))
    )
    (comp (ref "C1608")
      (value "100n")
      (footprint "eagle-import:S_0805")
      (fields (field (name "PART_CODE_BEL") "C_PAC_S_0805_VAL_100n"))
      (libsource (lib "eagle-import") (part "C_S_0805"))
    )
    (comp (ref "C1609")
      (value "100n")
      (footprint "eagle-import:S_0805")
      (fields (field (name "PART_CODE_BEL") "C_PAC_S_0805_VAL_100n"))
      (libsource (lib "eagle-import") (part "C_S_0805"))
    )
    (comp (ref "C1610")
      (value "100n")
      (footprint "eagle-import:S_0805")
      (fields (field (name "PART_CODE_BEL") "C_PAC_S_0805_VAL_100n"))
      (libsource (lib "eagle-import") (part "C_S_0805"))
    )
    (comp (ref "C1611")
      (value "100n")
      (footprint "eagle-import:S_0805")
      (fields (field (name "PART_CODE_BEL") "C_PAC_S_0805_VAL_100n"))
      (libsource (lib "eagle-import") (part "C_S_0805"))
    )
    (comp (ref "C1101")
      (value "100n")
      (footprint "eagle-import:S_0805")
      (fields (field (name "PART_CODE_BEL") "C_PAC_S_0805_VAL_100n"))
      (libsource (lib "eagle-import") (part "C_S_0805"))
    )
    (comp (ref "C1102")
      (value "100n")
      (footprint "eagle-import:S_0805")
      (fields (field (name "PART_CODE_BEL") "C_PAC_S_0805_VAL_100n"))
      (libsource (lib "eagle-import") (part "C_S_0805"))
    )
    (comp (ref "C1103")
      (value "100n")
      (footprint "eagle-import:S_0805")
      (fields (field (name "PART_CODE_BEL") "C_PAC_S_0805_VAL_100n"))
      (libsource (lib "eagle-import") (part "C_S_0805"))
    )
    (comp (ref "C1104")
      (value "100n")
      (footprint "eagle-import:S_0805")
      (fields (field (name "PART_CODE_BEL") "C_PAC_S_0805_VAL_100n"))
      (libsource (lib "eagle-import") (part "C_S_0805"))
    )
    (comp (ref "C1105")
      (value "100n")
      (footprint "eagle-import:S_0805")
      (fields (field (name "PART_CODE_BEL") "C_PAC_S_0805_VAL_100n"))
      (libsource (lib "eagle-import") (part "C_S_0805"))
    )
    (comp (ref "C1106")
      (value "100n")
      (footprint "eagle-import:S_0805")
      (fields (field (name "PART_CODE_BEL") "C_PAC_S_0805_VAL_100n"))
      (libsource (lib "eagle-import") (part "C_S_0805"))
    )
    (comp (ref "C1107")
      (value "100n")
      (footprint "eagle-import:S_0805")
      (fields (field (name "PART_CODE_BEL") "C_PAC_S_0805_VAL_100n"))
      (libsource (lib "eagle-import") (part "C_S_0805"))
    )
    (comp (ref "C1108")
      (value "100n")
      (footprint "eagle-import:S_0805")
      (fields (field (name "PART_CODE_BEL") "C_PAC_S_0805_VAL_100n"))
      (libsource (lib "eagle-import") (part "C_S_0805"))
    )
    (comp (ref "C1109")
      (value "100n")
      (footprint "eagle-import:S_0805")
      (fields (field (name "PART_CODE_BEL") "C_PAC_S_0805_VAL_100n"))
      (libsource (lib "eagle-import") (part "C_S_0805"))
    )
    (comp (ref "C1110")
      (value "100n")
      (footprint "eagle-import:S_0805")
      (fields (field (name "PART_CODE_BEL") "C_PAC_S_0805_VAL_100n"))
      (libsource (lib "eagle-import") (part "C_S_0805"))
    )
    (comp (ref "C1111")
      (value "100n")
      (footprint "eagle-import:S_0805")
      (fields (field (name "PART_CODE_BEL") "C_PAC_S_0805_VAL_100n"))
      (libsource (lib "eagle-import") (part "C_S_0805"))
    )
    (comp (ref "C1112")
      (value "100n")
      (footprint "eagle-import:S_0805")
      (fields (field (name "PART_CODE_BEL") "C_PAC_S_0805_VAL_100n"))
      (libsource (lib "eagle-import") (part "C_S_0805"))
    )
    (comp (ref "C1113")
      (value "100n")
      (footprint "eagle-import:S_0805")
      (fields (field (name "PART_CODE_BEL") "C_PAC_S_0805_VAL_100n"))
      (libsource (lib "eagle-import") (part "C_S_0805"))
    )
    (comp (ref "C1114")
      (value "100n")
      (footprint "eagle-import:S_0805")
      (fields (field (name "PART_CODE_BEL") "C_PAC_S_0805_VAL_100n"))
      (libsource (lib "eagle-import") (part "C_S_0805"))
    )
    (comp (ref "C1115")
      (value "100n")
      (footprint "eagle-import:S_0805")
      (fields (field (name "PART_CODE_BEL") "C_PAC_S_0805_VAL_100n"))
      (libsource (lib "eagle-import") (part "C_S_0805"))
    )
    (comp (ref "C1116")
      (value "100n")
      (footprint "eagle-import:S_0805")
      (fields (field (name "PART_CODE_BEL") "C_PAC_S_0805_VAL_100n"))
      (libsource (lib "eagle-import") (part "C_S_0805"))
    )
    (comp (ref "C1117")
      (value "100n")
      (footprint "eagle-import:S_0805")
      (fields (field (name "PART_CODE_BEL") "C_PAC_S_0805_VAL_100n"))
      (libsource (lib "eagle-import") (part "C_S_0805"))
    )
    (comp (ref "C1118")
      (value "100n")
      (footprint "eagle-import:S_0805")
      (fields (field (name "PART_CODE_BEL") "C_PAC_S_0805_VAL_100n"))
      (libsource (lib "eagle-import") (part "C_S_0805"))
    )
    (comp (ref "C1119")
      (value "100n")
      (footprint "eagle-import:S_0805")
      (fields (field (name "PART_CODE_BEL") "C_PAC_S_0805_VAL_100n"))
      (libsource (lib "eagle-import") (part "C_S_0805"))
    )
    (comp (ref "C1120")
      (value "100n")
      (footprint "eagle-import:S_0805")
      (fields (field (name "PART_CODE_BEL") "C_PAC_S_0805_VAL_100n"))
      (libsource (lib "eagle-import") (part "C_S_0805"))
    )
    (comp (ref "IC1101")
      (value "50MHz")
      (footprint "eagle-import:S_XO91")
      (fields (field (name "PART_CODE_BEL") "IC_PAC_S_XO91_7x5mm_VAL_50MHz"))
      (libsource (lib "eagle-import") (part "OSC_S_XO91"))
    )
    (comp (ref "TP1101")
      (value "TEST_POINT_T_SMALL")
      (footprint "eagle-import:T_TEST_POINT_SMALL")
      (libsource (lib "eagle-import") (part "TEST_POINT_T_SMALL"))
    )
    (comp (ref "LED2301")
      (value "green")
      (footprint "eagle-import:S_0805")
      (fields
        (field (name "FUNCTION") "SP_1_DIO_1_ADJ")
        (field (name "PART_CODE_BEL") "LED_PAC_S_0805_VAL_green")
      )
      (libsource (lib "eagle-import") (part "LED_S_0805"))
    )
    (comp (ref "LED2302")
      (value "green")
      (footprint "eagle-import:S_0805")
      (fields
        (field (name "FUNCTION") "SP_2_DIO_1_ADJ")
        (field (name "PART_CODE_BEL") "LED_PAC_S_0805_VAL_green")
      )
      (libsource (lib "eagle-import") (part "LED_S_0805"))
    )
    (comp (ref "LED2303")
      (value "green")
      (footprint "eagle-import:S_0805")
      (fields
        (field (name "FUNCTION") "SP_1_DIO_2_ADJ")
        (field (name "PART_CODE_BEL") "LED_PAC_S_0805_VAL_green")
      )
      (libsource (lib "eagle-import") (part "LED_S_0805"))
    )
    (comp (ref "LED2304")
      (value "green")
      (footprint "eagle-import:S_0805")
      (fields
        (field (name "FUNCTION") "SP_2_DIO_2_ADJ")
        (field (name "PART_CODE_BEL") "LED_PAC_S_0805_VAL_green")
      )
      (libsource (lib "eagle-import") (part "LED_S_0805"))
    )
    (comp (ref "LED2305")
      (value "green")
      (footprint "eagle-import:S_0805")
      (fields
        (field (name "FUNCTION") "SP_1_DIO_1_P3V3")
        (field (name "PART_CODE_BEL") "LED_PAC_S_0805_VAL_green")
      )
      (libsource (lib "eagle-import") (part "LED_S_0805"))
    )
    (comp (ref "LED2306")
      (value "green")
      (footprint "eagle-import:S_0805")
      (fields
        (field (name "FUNCTION") "SP_2_DIO_1_P3V3")
        (field (name "PART_CODE_BEL") "LED_PAC_S_0805_VAL_green")
      )
      (libsource (lib "eagle-import") (part "LED_S_0805"))
    )
    (comp (ref "LED2307")
      (value "green")
      (footprint "eagle-import:S_0805")
      (fields
        (field (name "FUNCTION") "SP_1_DIO_2_P3V3")
        (field (name "PART_CODE_BEL") "LED_PAC_S_0805_VAL_green")
      )
      (libsource (lib "eagle-import") (part "LED_S_0805"))
    )
    (comp (ref "LED2308")
      (value "green")
      (footprint "eagle-import:S_0805")
      (fields
        (field (name "FUNCTION") "SP_2_DIO_2_P3V3")
        (field (name "PART_CODE_BEL") "LED_PAC_S_0805_VAL_green")
      )
      (libsource (lib "eagle-import") (part "LED_S_0805"))
    )
    (comp (ref "R2301")
      (value "100k")
      (footprint "eagle-import:S_0805")
      (fields (field (name "PART_CODE_BEL") "R_PAC_S_0805_VAL_100k"))
      (libsource (lib "eagle-import") (part "R_S_0805"))
    )
    (comp (ref "R2302")
      (value "100k")
      (footprint "eagle-import:S_0805")
      (fields (field (name "PART_CODE_BEL") "R_PAC_S_0805_VAL_100k"))
      (libsource (lib "eagle-import") (part "R_S_0805"))
    )
    (comp (ref "R2303")
      (value "160")
      (footprint "eagle-import:S_0805")
      (fields (field (name "PART_CODE_BEL") "R_PAC_S_0805_VAL_160"))
      (libsource (lib "eagle-import") (part "R_S_0805"))
    )
    (comp (ref "R2304")
      (value "160")
      (footprint "eagle-import:S_0805")
      (fields (field (name "PART_CODE_BEL") "R_PAC_S_0805_VAL_160"))
      (libsource (lib "eagle-import") (part "R_S_0805"))
    )
    (comp (ref "R2305")
      (value "100k")
      (footprint "eagle-import:S_0805")
      (fields (field (name "PART_CODE_BEL") "R_PAC_S_0805_VAL_100k"))
      (libsource (lib "eagle-import") (part "R_S_0805"))
    )
    (comp (ref "R2306")
      (value "100k")
      (footprint "eagle-import:S_0805")
      (fields (field (name "PART_CODE_BEL") "R_PAC_S_0805_VAL_100k"))
      (libsource (lib "eagle-import") (part "R_S_0805"))
    )
    (comp (ref "R2307")
      (value "160")
      (footprint "eagle-import:S_0805")
      (fields (field (name "PART_CODE_BEL") "R_PAC_S_0805_VAL_160"))
      (libsource (lib "eagle-import") (part "R_S_0805"))
    )
    (comp (ref "R2308")
      (value "160")
      (footprint "eagle-import:S_0805")
      (fields (field (name "PART_CODE_BEL") "R_PAC_S_0805_VAL_160"))
      (libsource (lib "eagle-import") (part "R_S_0805"))
    )
    (comp (ref "R2309")
      (value "100k")
      (footprint "eagle-import:S_0805")
      (fields (field (name "PART_CODE_BEL") "R_PAC_S_0805_VAL_100k"))
      (libsource (lib "eagle-import") (part "R_S_0805"))
    )
    (comp (ref "R2310")
      (value "100k")
      (footprint "eagle-import:S_0805")
      (fields (field (name "PART_CODE_BEL") "R_PAC_S_0805_VAL_100k"))
      (libsource (lib "eagle-import") (part "R_S_0805"))
    )
    (comp (ref "R2311")
      (value "160")
      (footprint "eagle-import:S_0805")
      (fields (field (name "PART_CODE_BEL") "R_PAC_S_0805_VAL_160"))
      (libsource (lib "eagle-import") (part "R_S_0805"))
    )
    (comp (ref "R2312")
      (value "160")
      (footprint "eagle-import:S_0805")
      (fields (field (name "PART_CODE_BEL") "R_PAC_S_0805_VAL_160"))
      (libsource (lib "eagle-import") (part "R_S_0805"))
    )
    (comp (ref "R2313")
      (value "100k")
      (footprint "eagle-import:S_0805")
      (fields (field (name "PART_CODE_BEL") "R_PAC_S_0805_VAL_100k"))
      (libsource (lib "eagle-import") (part "R_S_0805"))
    )
    (comp (ref "R2314")
      (value "100k")
      (footprint "eagle-import:S_0805")
      (fields (field (name "PART_CODE_BEL") "R_PAC_S_0805_VAL_100k"))
      (libsource (lib "eagle-import") (part "R_S_0805"))
    )
    (comp (ref "R2315")
      (value "160")
      (footprint "eagle-import:S_0805")
      (fields (field (name "PART_CODE_BEL") "R_PAC_S_0805_VAL_160"))
      (libsource (lib "eagle-import") (part "R_S_0805"))
    )
    (comp (ref "R2316")
      (value "160")
      (footprint "eagle-import:S_0805")
      (fields (field (name "PART_CODE_BEL") "R_PAC_S_0805_VAL_160"))
      (libsource (lib "eagle-import") (part "R_S_0805"))
    )
    (comp (ref "T2301")
      (value "DMG3420U")
      (footprint "eagle-import:S_SOT23")
      (fields (field (name "PART_CODE_BEL") "T_PAC_S_SOT23_VAL_DMG3420U"))
      (libsource (lib "eagle-import") (part "N-MOSFET_S_SOT23"))
    )
    (comp (ref "T2302")
      (value "DMG3420U")
      (footprint "eagle-import:S_SOT23")
      (fields (field (name "PART_CODE_BEL") "T_PAC_S_SOT23_VAL_DMG3420U"))
      (libsource (lib "eagle-import") (part "N-MOSFET_S_SOT23"))
    )
    (comp (ref "T2303")
      (value "DMG3420U")
      (footprint "eagle-import:S_SOT23")
      (fields (field (name "PART_CODE_BEL") "T_PAC_S_SOT23_VAL_DMG3420U"))
      (libsource (lib "eagle-import") (part "N-MOSFET_S_SOT23"))
    )
    (comp (ref "T2304")
      (value "DMG3420U")
      (footprint "eagle-import:S_SOT23")
      (fields (field (name "PART_CODE_BEL") "T_PAC_S_SOT23_VAL_DMG3420U"))
      (libsource (lib "eagle-import") (part "N-MOSFET_S_SOT23"))
    )
    (comp (ref "T2305")
      (value "DMG3420U")
      (footprint "eagle-import:S_SOT23")
      (fields (field (name "PART_CODE_BEL") "T_PAC_S_SOT23_VAL_DMG3420U"))
      (libsource (lib "eagle-import") (part "N-MOSFET_S_SOT23"))
    )
    (comp (ref "T2306")
      (value "DMG3420U")
      (footprint "eagle-import:S_SOT23")
      (fields (field (name "PART_CODE_BEL") "T_PAC_S_SOT23_VAL_DMG3420U"))
      (libsource (lib "eagle-import") (part "N-MOSFET_S_SOT23"))
    )
    (comp (ref "T2307")
      (value "DMG3420U")
      (footprint "eagle-import:S_SOT23")
      (fields (field (name "PART_CODE_BEL") "T_PAC_S_SOT23_VAL_DMG3420U"))
      (libsource (lib "eagle-import") (part "N-MOSFET_S_SOT23"))
    )
    (comp (ref "T2308")
      (value "DMG3420U")
      (footprint "eagle-import:S_SOT23")
      (fields (field (name "PART_CODE_BEL") "T_PAC_S_SOT23_VAL_DMG3420U"))
      (libsource (lib "eagle-import") (part "N-MOSFET_S_SOT23"))
    )
    (comp (ref "DIS1901")
      (value "VQE14")
      (footprint "eagle-import:T_VQEXX_2DIGIT")
      (fields
        (field (name "FUNCTION") "TAP_STATES")
        (field (name "PART_CODE_BEL") "DIS_PAC_T_VQExx_2DIGIT_VAL_VQE14")
      )
      (libsource (lib "eagle-import") (part "VQEXX_2DIGIT_T_VQEXX_2DIGIT"))
    )
    (comp (ref "J1901")
      (value "SOLDER_JUMPER-N")
      (footprint "eagle-import:S_SOLDER_JUMPER_NARROW")
      (fields (field (name "FUNCTION") "com_anode"))
      (libsource (lib "eagle-import") (part "SOLDER_JUMPER-N"))
    )
    (comp (ref "J1902")
      (value "SOLDER_JUMPER-N")
      (footprint "eagle-import:S_SOLDER_JUMPER_NARROW")
      (fields (field (name "FUNCTION") "com_cathode"))
      (libsource (lib "eagle-import") (part "SOLDER_JUMPER-N"))
    )
    (comp (ref "J1903")
      (value "SOLDER_JUMPER-N")
      (footprint "eagle-import:S_SOLDER_JUMPER_NARROW")
      (fields (field (name "FUNCTION") "com_anode"))
      (libsource (lib "eagle-import") (part "SOLDER_JUMPER-N"))
    )
    (comp (ref "J1904")
      (value "SOLDER_JUMPER-N")
      (footprint "eagle-import:S_SOLDER_JUMPER_NARROW")
      (fields (field (name "FUNCTION") "com_cathode"))
      (libsource (lib "eagle-import") (part "SOLDER_JUMPER-N"))
    )
    (comp (ref "LED1901")
      (value "yellow")
      (footprint "eagle-import:S_0805")
      (fields (field (name "FUNCTION") "SCL") (field (name "PART_CODE_BEL") "LED_PAC_S_0805_VAL_yellow"))
      (libsource (lib "eagle-import") (part "LED_S_0805"))
    )
    (comp (ref "LED1902")
      (value "blue")
      (footprint "eagle-import:S_0805")
      (fields (field (name "FUNCTION") "SDA") (field (name "PART_CODE_BEL") "LED_PAC_S_0805_VAL_blue"))
      (libsource (lib "eagle-import") (part "LED_S_0805"))
    )
    (comp (ref "R1901")
      (value "100k")
      (footprint "eagle-import:S_0805")
      (fields (field (name "PART_CODE_BEL") "R_PAC_S_0805_VAL_100k"))
      (libsource (lib "eagle-import") (part "R_S_0805"))
    )
    (comp (ref "R1902")
      (value "470")
      (footprint "eagle-import:S_0805")
      (fields (field (name "PART_CODE_BEL") "R_PAC_S_0805_VAL_470"))
      (libsource (lib "eagle-import") (part "R_S_0805"))
    )
    (comp (ref "R1903")
      (value "100k")
      (footprint "eagle-import:S_0805")
      (fields (field (name "PART_CODE_BEL") "R_PAC_S_0805_VAL_100k"))
      (libsource (lib "eagle-import") (part "R_S_0805"))
    )
    (comp (ref "R1904")
      (value "330")
      (footprint "eagle-import:S_0805")
      (fields (field (name "PART_CODE_BEL") "R_PAC_S_0805_VAL_330"))
      (libsource (lib "eagle-import") (part "R_S_0805"))
    )
    (comp (ref "RN1901")
      (value "100")
      (footprint "eagle-import:T_SIL8")
      (fields (field (name "PART_CODE_BEL") "RN_PAC_T_SIL8_VAL_100"))
      (libsource (lib "eagle-import") (part "RN_4T_SIL8"))
    )
    (comp (ref "RN1902")
      (value "100")
      (footprint "eagle-import:T_SIL8")
      (fields (field (name "PART_CODE_BEL") "RN_PAC_T_SIL8_VAL_100"))
      (libsource (lib "eagle-import") (part "RN_4T_SIL8"))
    )
    (comp (ref "RN1903")
      (value "100")
      (footprint "eagle-import:T_SIL8")
      (fields (field (name "PART_CODE_BEL") "RN_PAC_T_SIL8_VAL_100"))
      (libsource (lib "eagle-import") (part "RN_4T_SIL8"))
    )
    (comp (ref "RN1904")
      (value "100")
      (footprint "eagle-import:T_SIL8")
      (fields (field (name "PART_CODE_BEL") "RN_PAC_T_SIL8_VAL_100"))
      (libsource (lib "eagle-import") (part "RN_4T_SIL8"))
    )
    (comp (ref "T1901")
      (value "DMG3420U")
      (footprint "eagle-import:S_SOT23")
      (fields (field (name "PART_CODE_BEL") "T_PAC_S_SOT23_VAL_DMG3420U"))
      (libsource (lib "eagle-import") (part "N-MOSFET_S_SOT23"))
    )
    (comp (ref "T1902")
      (value "DMG3420U")
      (footprint "eagle-import:S_SOT23")
      (fields (field (name "PART_CODE_BEL") "T_PAC_S_SOT23_VAL_DMG3420U"))
      (libsource (lib "eagle-import") (part "N-MOSFET_S_SOT23"))
    )
    (comp (ref "TP1901")
      (value "TEST_POINT_T_SMALL")
      (footprint "eagle-import:T_TEST_POINT_SMALL")
      (libsource (lib "eagle-import") (part "TEST_POINT_T_SMALL"))
    )
    (comp (ref "TP1902")
      (value "TEST_POINT_T_SMALL")
      (footprint "eagle-import:T_TEST_POINT_SMALL")
      (libsource (lib "eagle-import") (part "TEST_POINT_T_SMALL"))
    )
    (comp (ref "TP1903")
      (value "TEST_POINT_T_SMALL")
      (footprint "eagle-import:T_TEST_POINT_SMALL")
      (libsource (lib "eagle-import") (part "TEST_POINT_T_SMALL"))
    )
    (comp (ref "TP1904")
      (value "TEST_POINT_T_SMALL")
      (footprint "eagle-import:T_TEST_POINT_SMALL")
      (libsource (lib "eagle-import") (part "TEST_POINT_T_SMALL"))
    )
    (comp (ref "D2501")
      (value "1N4148")
      (footprint "eagle-import:S_SOD123")
      (libsource (lib "eagle-import") (part "SINGLES_SOD123"))
    )
    (comp (ref "D2502")
      (value "1N4148")
      (footprint "eagle-import:S_SOD123")
      (libsource (lib "eagle-import") (part "SINGLES_SOD123"))
    )
    (comp (ref "D2503")
      (value "1N4148")
      (footprint "eagle-import:S_SOD123")
      (libsource (lib "eagle-import") (part "SINGLES_SOD123"))
    )
    (comp (ref "LED2501")
      (value "blue")
      (footprint "eagle-import:S_0805")
      (fields (field (name "FUNCTION") "SP_2_P1V5") (field (name "PART_CODE_BEL") "LED_PAC_S_0805_VAL_blue"))
      (libsource (lib "eagle-import") (part "LED_S_0805"))
    )
    (comp (ref "LED2502")
      (value "green")
      (footprint "eagle-import:S_0805")
      (fields (field (name "FUNCTION") "SP_2_P1V8") (field (name "PART_CODE_BEL") "LED_PAC_S_0805_VAL_green"))
      (libsource (lib "eagle-import") (part "LED_S_0805"))
    )
    (comp (ref "LED2503")
      (value "green")
      (footprint "eagle-import:S_0805")
      (fields (field (name "FUNCTION") "SP_2_P2V5") (field (name "PART_CODE_BEL") "LED_PAC_S_0805_VAL_green"))
      (libsource (lib "eagle-import") (part "LED_S_0805"))
    )
    (comp (ref "LED2504")
      (value "yellow")
      (footprint "eagle-import:S_0805")
      (fields
        (field (name "FUNCTION") "SP_2_P3V3")
        (field (name "PART_CODE_BEL") "LED_PAC_S_0805_VAL_yellow")
      )
      (libsource (lib "eagle-import") (part "LED_S_0805"))
    )
    (comp (ref "R2501")
      (value "2k7")
      (footprint "eagle-import:S_0805")
      (fields (field (name "PART_CODE_BEL") "R_PAC_S_0805_VAL_2k7"))
      (libsource (lib "eagle-import") (part "R_S_0805"))
    )
    (comp (ref "R2502")
      (value "2k7")
      (footprint "eagle-import:S_0805")
      (fields (field (name "PART_CODE_BEL") "R_PAC_S_0805_VAL_2k7"))
      (libsource (lib "eagle-import") (part "R_S_0805"))
    )
    (comp (ref "R2503")
      (value "2k7")
      (footprint "eagle-import:S_0805")
      (fields (field (name "PART_CODE_BEL") "R_PAC_S_0805_VAL_2k7"))
      (libsource (lib "eagle-import") (part "R_S_0805"))
    )
    (comp (ref "R2504")
      (value "330")
      (footprint "eagle-import:S_0805")
      (fields (field (name "PART_CODE_BEL") "R_PAC_S_0805_VAL_330"))
      (libsource (lib "eagle-import") (part "R_S_0805"))
    )
    (comp (ref "R2505")
      (value "2k7")
      (footprint "eagle-import:S_0805")
      (fields (field (name "PART_CODE_BEL") "R_PAC_S_0805_VAL_2k7"))
      (libsource (lib "eagle-import") (part "R_S_0805"))
    )
    (comp (ref "R2506")
      (value "160")
      (footprint "eagle-import:S_0805")
      (fields (field (name "PART_CODE_BEL") "R_PAC_S_0805_VAL_160"))
      (libsource (lib "eagle-import") (part "R_S_0805"))
    )
    (comp (ref "R2507")
      (value "2k7")
      (footprint "eagle-import:S_0805")
      (fields (field (name "PART_CODE_BEL") "R_PAC_S_0805_VAL_2k7"))
      (libsource (lib "eagle-import") (part "R_S_0805"))
    )
    (comp (ref "R2508")
      (value "160")
      (footprint "eagle-import:S_0805")
      (fields (field (name "PART_CODE_BEL") "R_PAC_S_0805_VAL_160"))
      (libsource (lib "eagle-import") (part "R_S_0805"))
    )
    (comp (ref "R2509")
      (value "470")
      (footprint "eagle-import:S_0805")
      (fields (field (name "PART_CODE_BEL") "R_PAC_S_0805_VAL_470"))
      (libsource (lib "eagle-import") (part "R_S_0805"))
    )
    (comp (ref "T2501")
      (value "NX2301P")
      (footprint "eagle-import:S_SOT23")
      (fields (field (name "PART_CODE_BEL") "T_PAC_S_SOT23_VAL_NX2301P"))
      (libsource (lib "eagle-import") (part "P-MOSFET"))
    )
    (comp (ref "T2502")
      (value "NX2301P")
      (footprint "eagle-import:S_SOT23")
      (fields (field (name "PART_CODE_BEL") "T_PAC_S_SOT23_VAL_NX2301P"))
      (libsource (lib "eagle-import") (part "P-MOSFET"))
    )
    (comp (ref "T2503")
      (value "NX2301P")
      (footprint "eagle-import:S_SOT23")
      (fields (field (name "PART_CODE_BEL") "T_PAC_S_SOT23_VAL_NX2301P"))
      (libsource (lib "eagle-import") (part "P-MOSFET"))
    )
    (comp (ref "T2504")
      (value "NX2301P")
      (footprint "eagle-import:S_SOT23")
      (fields (field (name "PART_CODE_BEL") "T_PAC_S_SOT23_VAL_NX2301P"))
      (libsource (lib "eagle-import") (part "P-MOSFET"))
    )
    (comp (ref "T2505")
      (value "NX2301P")
      (footprint "eagle-import:S_SOT23")
      (fields (field (name "PART_CODE_BEL") "T_PAC_S_SOT23_VAL_NX2301P"))
      (libsource (lib "eagle-import") (part "P-MOSFET"))
    )
    (comp (ref "T2506")
      (value "NX2301P")
      (footprint "eagle-import:S_SOT23")
      (fields (field (name "PART_CODE_BEL") "T_PAC_S_SOT23_VAL_NX2301P"))
      (libsource (lib "eagle-import") (part "P-MOSFET"))
    )
    (comp (ref "T2507")
      (value "DMG3420U")
      (footprint "eagle-import:S_SOT23")
      (fields (field (name "PART_CODE_BEL") "T_PAC_S_SOT23_VAL_DMG3420U"))
      (libsource (lib "eagle-import") (part "N-MOSFET_S_SOT23"))
    )
    (comp (ref "T2508")
      (value "DMG3420U")
      (footprint "eagle-import:S_SOT23")
      (fields (field (name "PART_CODE_BEL") "T_PAC_S_SOT23_VAL_DMG3420U"))
      (libsource (lib "eagle-import") (part "N-MOSFET_S_SOT23"))
    )
    (comp (ref "LED1701")
      (value "green")
      (footprint "eagle-import:S_0805")
      (fields (field (name "FUNCTION") "DEBUG_0") (field (name "PART_CODE_BEL") "LED_PAC_S_0805_VAL_green"))
      (libsource (lib "eagle-import") (part "LED_S_0805"))
    )
    (comp (ref "LED1702")
      (value "green")
      (footprint "eagle-import:S_0805")
      (fields (field (name "FUNCTION") "DBG_10") (field (name "PART_CODE_BEL") "LED_PAC_S_0805_VAL_green"))
      (libsource (lib "eagle-import") (part "LED_S_0805"))
    )
    (comp (ref "LED1703")
      (value "yellow")
      (footprint "eagle-import:S_0805")
      (fields (field (name "FUNCTION") "DEBUG_1") (field (name "PART_CODE_BEL") "LED_PAC_S_0805_VAL_yellow"))
      (libsource (lib "eagle-import") (part "LED_S_0805"))
    )
    (comp (ref "LED1704")
      (value "yellow")
      (footprint "eagle-import:S_0805")
      (fields (field (name "FUNCTION") "DBG_11") (field (name "PART_CODE_BEL") "LED_PAC_S_0805_VAL_yellow"))
      (libsource (lib "eagle-import") (part "LED_S_0805"))
    )
    (comp (ref "LED1705")
      (value "blue")
      (footprint "eagle-import:S_0805")
      (fields (field (name "FUNCTION") "DEBUG_2") (field (name "PART_CODE_BEL") "LED_PAC_S_0805_VAL_blue"))
      (libsource (lib "eagle-import") (part "LED_S_0805"))
    )
    (comp (ref "LED1706")
      (value "red")
      (footprint "eagle-import:S_0805")
      (fields (field (name "FUNCTION") "DBG_12") (field (name "PART_CODE_BEL") "LED_PAC_S_0805_VAL_red"))
      (libsource (lib "eagle-import") (part "LED_S_0805"))
    )
    (comp (ref "LED1707")
      (value "red")
      (footprint "eagle-import:S_0805")
      (fields (field (name "FUNCTION") "SYS_RESET") (field (name "PART_CODE_BEL") "LED_PAC_S_0805_VAL_red"))
      (libsource (lib "eagle-import") (part "LED_S_0805"))
    )
    (comp (ref "LED1708")
      (value "blue")
      (footprint "eagle-import:S_0805")
      (fields (field (name "FUNCTION") "DBG_13") (field (name "PART_CODE_BEL") "LED_PAC_S_0805_VAL_blue"))
      (libsource (lib "eagle-import") (part "LED_S_0805"))
    )
    (comp (ref "R1701")
      (value "160")
      (footprint "eagle-import:S_0805")
      (fields (field (name "PART_CODE_BEL") "R_PAC_S_0805_VAL_160"))
      (libsource (lib "eagle-import") (part "R_S_0805"))
    )
    (comp (ref "R1702")
      (value "160")
      (footprint "eagle-import:S_0805")
      (fields (field (name "PART_CODE_BEL") "R_PAC_S_0805_VAL_160"))
      (libsource (lib "eagle-import") (part "R_S_0805"))
    )
    (comp (ref "R1703")
      (value "470")
      (footprint "eagle-import:S_0805")
      (fields (field (name "PART_CODE_BEL") "R_PAC_S_0805_VAL_470"))
      (libsource (lib "eagle-import") (part "R_S_0805"))
    )
    (comp (ref "R1704")
      (value "470")
      (footprint "eagle-import:S_0805")
      (fields (field (name "PART_CODE_BEL") "R_PAC_S_0805_VAL_470"))
      (libsource (lib "eagle-import") (part "R_S_0805"))
    )
    (comp (ref "R1705")
      (value "330")
      (footprint "eagle-import:S_0805")
      (fields (field (name "PART_CODE_BEL") "R_PAC_S_0805_VAL_330"))
      (libsource (lib "eagle-import") (part "R_S_0805"))
    )
    (comp (ref "R1706")
      (value "750")
      (footprint "eagle-import:S_0805")
      (fields (field (name "PART_CODE_BEL") "R_PAC_S_0805_VAL_750"))
      (libsource (lib "eagle-import") (part "R_S_0805"))
    )
    (comp (ref "R1707")
      (value "750")
      (footprint "eagle-import:S_0805")
      (fields (field (name "PART_CODE_BEL") "R_PAC_S_0805_VAL_750"))
      (libsource (lib "eagle-import") (part "R_S_0805"))
    )
    (comp (ref "R1708")
      (value "330")
      (footprint "eagle-import:S_0805")
      (fields (field (name "PART_CODE_BEL") "R_PAC_S_0805_VAL_330"))
      (libsource (lib "eagle-import") (part "R_S_0805"))
    )
    (comp (ref "TP1701")
      (value "TEST_POINT_T_SMALL")
      (footprint "eagle-import:T_TEST_POINT_SMALL")
      (libsource (lib "eagle-import") (part "TEST_POINT_T_SMALL"))
    )
    (comp (ref "X1701")
      (value "MALE_2X20-T-VERTICAL")
      (footprint "eagle-import:T_MALE_2X20_VERTICAL_GRID_2.54MM")
      (fields (field (name "FUNCTION") "DBG_1"))
      (libsource (lib "eagle-import") (part "MALE_2X20-T-VERTICAL"))
    )
    (comp (ref "X1702")
      (value "MALE_2X20-T-VERTICAL")
      (footprint "eagle-import:T_MALE_2X20_VERTICAL_GRID_2.54MM")
      (fields (field (name "FUNCTION") "DBG_2"))
      (libsource (lib "eagle-import") (part "MALE_2X20-T-VERTICAL"))
    )
    (comp (ref "C301")
      (value "100n")
      (footprint "eagle-import:S_0805")
      (fields (field (name "PART_CODE_BEL") "C_PAC_S_0805_VAL_100n"))
      (libsource (lib "eagle-import") (part "C_S_0805"))
    )
    (comp (ref "C302")
      (value "1u")
      (footprint "eagle-import:S_0805")
      (fields (field (name "PART_CODE_BEL") "C_PAC_S_0805_VAL_1u"))
      (libsource (lib "eagle-import") (part "C_S_0805"))
    )
    (comp (ref "C303")
      (value "100n")
      (footprint "eagle-import:S_0805")
      (fields (field (name "PART_CODE_BEL") "C_PAC_S_0805_VAL_100n"))
      (libsource (lib "eagle-import") (part "C_S_0805"))
    )
    (comp (ref "C304")
      (value "1u")
      (footprint "eagle-import:S_0805")
      (fields (field (name "PART_CODE_BEL") "C_PAC_S_0805_VAL_1u"))
      (libsource (lib "eagle-import") (part "C_S_0805"))
    )
    (comp (ref "IC301")
      (value "LM1117T-ADJ")
      (footprint "eagle-import:T_TO220-3_VERTICAL")
      (fields (field (name "PART_CODE_BEL") "IC_PAC_T_TO220-3_VERTICAL_VAL_LM1117T-ADJ"))
      (libsource (lib "eagle-import") (part "LMXX17-T_VERTICAL"))
    )
    (comp (ref "IC302")
      (value "LM1117T-ADJ")
      (footprint "eagle-import:T_TO220-3_VERTICAL")
      (fields (field (name "PART_CODE_BEL") "IC_PAC_T_TO220-3_VERTICAL_VAL_LM1117T-ADJ"))
      (libsource (lib "eagle-import") (part "LMXX17-T_VERTICAL"))
    )
    (comp (ref "J301")
      (value "SOLDER_JUMPER-N")
      (footprint "eagle-import:S_SOLDER_JUMPER_NARROW")
      (libsource (lib "eagle-import") (part "SOLDER_JUMPER-N"))
    )
    (comp (ref "J302")
      (value "SOLDER_JUMPER-N")
      (footprint "eagle-import:S_SOLDER_JUMPER_NARROW")
      (libsource (lib "eagle-import") (part "SOLDER_JUMPER-N"))
    )
    (comp (ref "R301")
      (value "71R5")
      (footprint "eagle-import:S_0805")
      (fields (field (name "PART_CODE_BEL") "R_PAC_S_0805_VAL_71R5"))
      (libsource (lib "eagle-import") (part "R_S_0805"))
    )
    (comp (ref "R302")
      (value "392")
      (footprint "eagle-import:S_0805")
      (fields (field (name "PART_CODE_BEL") "R_PAC_S_0805_VAL_392"))
      (libsource (lib "eagle-import") (part "R_S_0805"))
    )
    (comp (ref "R303")
      (value "169")
      (footprint "eagle-import:S_0805")
      (fields (field (name "PART_CODE_BEL") "R_PAC_S_0805_VAL_169"))
      (libsource (lib "eagle-import") (part "R_S_0805"))
    )
    (comp (ref "R304")
      (value "240")
      (footprint "eagle-import:S_0805")
      (fields (field (name "PART_CODE_BEL") "R_PAC_S_0805_VAL_240"))
      (libsource (lib "eagle-import") (part "R_S_0805"))
    )
    (comp (ref "R305")
      (value "698")
      (footprint "eagle-import:S_0805")
      (fields (field (name "PART_CODE_BEL") "R_PAC_S_0805_VAL_698"))
      (libsource (lib "eagle-import") (part "R_S_0805"))
    )
    (comp (ref "R306")
      (value "71R5")
      (footprint "eagle-import:S_0805")
      (fields (field (name "PART_CODE_BEL") "R_PAC_S_0805_VAL_71R5"))
      (libsource (lib "eagle-import") (part "R_S_0805"))
    )
    (comp (ref "R307")
      (value "169")
      (footprint "eagle-import:S_0805")
      (fields (field (name "PART_CODE_BEL") "R_PAC_S_0805_VAL_169"))
      (libsource (lib "eagle-import") (part "R_S_0805"))
    )
    (comp (ref "R308")
      (value "392")
      (footprint "eagle-import:S_0805")
      (fields (field (name "PART_CODE_BEL") "R_PAC_S_0805_VAL_392"))
      (libsource (lib "eagle-import") (part "R_S_0805"))
    )
    (comp (ref "R309")
      (value "698")
      (footprint "eagle-import:S_0805")
      (fields (field (name "PART_CODE_BEL") "R_PAC_S_0805_VAL_698"))
      (libsource (lib "eagle-import") (part "R_S_0805"))
    )
    (comp (ref "R310")
      (value "240")
      (footprint "eagle-import:S_0805")
      (fields (field (name "PART_CODE_BEL") "R_PAC_S_0805_VAL_240"))
      (libsource (lib "eagle-import") (part "R_S_0805"))
    )
    (comp (ref "RN301")
      (value "10k")
      (footprint "eagle-import:S_1206_4X")
      (fields (field (name "PART_CODE_BEL") "RN_PAC_S_1206_4X_VAL_10k"))
      (libsource (lib "eagle-import") (part "RN_4S_1206"))
    )
    (comp (ref "RN302")
      (value "10k")
      (footprint "eagle-import:S_1206_4X")
      (fields (field (name "PART_CODE_BEL") "RN_PAC_S_1206_4X_VAL_10k"))
      (libsource (lib "eagle-import") (part "RN_4S_1206"))
    )
    (comp (ref "T301")
      (value "DMG3420U")
      (footprint "eagle-import:S_SOT23")
      (fields (field (name "PART_CODE_BEL") "T_PAC_S_SOT23_VAL_DMG3420U"))
      (libsource (lib "eagle-import") (part "N-MOSFET_S_SOT23"))
    )
    (comp (ref "T302")
      (value "DMG3420U")
      (footprint "eagle-import:S_SOT23")
      (fields (field (name "PART_CODE_BEL") "T_PAC_S_SOT23_VAL_DMG3420U"))
      (libsource (lib "eagle-import") (part "N-MOSFET_S_SOT23"))
    )
    (comp (ref "T303")
      (value "DMG3420U")
      (footprint "eagle-import:S_SOT23")
      (fields (field (name "PART_CODE_BEL") "T_PAC_S_SOT23_VAL_DMG3420U"))
      (libsource (lib "eagle-import") (part "N-MOSFET_S_SOT23"))
    )
    (comp (ref "T304")
      (value "DMG3420U")
      (footprint "eagle-import:S_SOT23")
      (fields (field (name "PART_CODE_BEL") "T_PAC_S_SOT23_VAL_DMG3420U"))
      (libsource (lib "eagle-import") (part "N-MOSFET_S_SOT23"))
    )
    (comp (ref "T305")
      (value "DMG3420U")
      (footprint "eagle-import:S_SOT23")
      (fields (field (name "PART_CODE_BEL") "T_PAC_S_SOT23_VAL_DMG3420U"))
      (libsource (lib "eagle-import") (part "N-MOSFET_S_SOT23"))
    )
    (comp (ref "T306")
      (value "DMG3420U")
      (footprint "eagle-import:S_SOT23")
      (fields (field (name "PART_CODE_BEL") "T_PAC_S_SOT23_VAL_DMG3420U"))
      (libsource (lib "eagle-import") (part "N-MOSFET_S_SOT23"))
    )
    (comp (ref "TP301")
      (value "TEST_POINT_T_SMALL")
      (footprint "eagle-import:T_TEST_POINT_SMALL")
      (libsource (lib "eagle-import") (part "TEST_POINT_T_SMALL"))
    )
    (comp (ref "TP302")
      (value "TEST_POINT_T_SMALL")
      (footprint "eagle-import:T_TEST_POINT_SMALL")
      (libsource (lib "eagle-import") (part "TEST_POINT_T_SMALL"))
    )
    (comp (ref "X301")
      (value "MALE_1X3")
      (footprint "eagle-import:T_MALE_3X1_VERTICAL")
      (fields (field (name "FUNCTION") "GND"))
      (libsource (lib "eagle-import") (part "MALE_1X3"))
    )
    (comp (ref "C1301")
      (value "100n")
      (footprint "eagle-import:S_0805")
      (fields (field (name "PART_CODE_BEL") "C_PAC_S_0805_VAL_100n"))
      (libsource (lib "eagle-import") (part "C_S_0805"))
    )
    (comp (ref "C1302")
      (value "100n")
      (footprint "eagle-import:S_0805")
      (fields (field (name "PART_CODE_BEL") "C_PAC_S_0805_VAL_100n"))
      (libsource (lib "eagle-import") (part "C_S_0805"))
    )
    (comp (ref "IC1301")
      (value "MAX517ACSA+")
      (footprint "eagle-import:S_SO8")
      (fields (field (name "PART_CODE_BEL") "IC_PAC_S_SO8_VAL_MAX517ACSA+"))
      (libsource (lib "eagle-import") (part "MAX517XXSA"))
    )
    (comp (ref "IC1302")
      (value "MAX517ACSA+")
      (footprint "eagle-import:S_SO8")
      (fields (field (name "PART_CODE_BEL") "IC_PAC_S_SO8_VAL_MAX517ACSA+"))
      (libsource (lib "eagle-import") (part "MAX517XXSA"))
    )
    (comp (ref "R1301")
      (value "330")
      (footprint "eagle-import:S_0805")
      (fields (field (name "PART_CODE_BEL") "R_PAC_S_0805_VAL_330"))
      (libsource (lib "eagle-import") (part "R_S_0805"))
    )
    (comp (ref "R1302")
      (value "330")
      (footprint "eagle-import:S_0805")
      (fields (field (name "PART_CODE_BEL") "R_PAC_S_0805_VAL_330"))
      (libsource (lib "eagle-import") (part "R_S_0805"))
    )
    (comp (ref "C701")
      (value "100n")
      (footprint "eagle-import:S_0805")
      (fields (field (name "PART_CODE_BEL") "C_PAC_S_0805_VAL_100n"))
      (libsource (lib "eagle-import") (part "C_S_0805"))
    )
    (comp (ref "C702")
      (value "100n")
      (footprint "eagle-import:S_0805")
      (fields (field (name "PART_CODE_BEL") "C_PAC_S_0805_VAL_100n"))
      (libsource (lib "eagle-import") (part "C_S_0805"))
    )
    (comp (ref "IC701")
      (value "AM29LV040B")
      (footprint "eagle-import:T_PLCC32")
      (fields (field (name "PART_CODE_BEL") "IC_PAC_T_PLCC32_VAL_AM29LV040B-120JC"))
      (libsource (lib "eagle-import") (part "512K_X_8T_PLCC32"))
    )
    (comp (ref "IC702")
      (value "24LC256-I/SN")
      (footprint "eagle-import:S_SOIC8")
      (fields (field (name "PART_CODE_BEL") "IC_PAC_S_SOIC8_VAL_24LC256-I/SN"))
      (libsource (lib "eagle-import") (part "24XXXSN"))
    )
    (comp (ref "R701")
      (value "330")
      (footprint "eagle-import:S_0805")
      (fields (field (name "PART_CODE_BEL") "R_PAC_S_0805_VAL_330"))
      (libsource (lib "eagle-import") (part "R_S_0805"))
    )
    (comp (ref "R702")
      (value "330")
      (footprint "eagle-import:S_0805")
      (fields (field (name "PART_CODE_BEL") "R_PAC_S_0805_VAL_330"))
      (libsource (lib "eagle-import") (part "R_S_0805"))
    )
    (comp (ref "R703")
      (value "330")
      (footprint "eagle-import:S_0805")
      (fields (field (name "PART_CODE_BEL") "R_PAC_S_0805_VAL_330"))
      (libsource (lib "eagle-import") (part "R_S_0805"))
    )
    (comp (ref "R704")
      (value "330")
      (footprint "eagle-import:S_0805")
      (fields (field (name "PART_CODE_BEL") "R_PAC_S_0805_VAL_330"))
      (libsource (lib "eagle-import") (part "R_S_0805"))
    )
    (comp (ref "D2401")
      (value "1N4148")
      (footprint "eagle-import:S_SOD123")
      (libsource (lib "eagle-import") (part "SINGLES_SOD123"))
    )
    (comp (ref "D2402")
      (value "1N4148")
      (footprint "eagle-import:S_SOD123")
      (libsource (lib "eagle-import") (part "SINGLES_SOD123"))
    )
    (comp (ref "D2403")
      (value "1N4148")
      (footprint "eagle-import:S_SOD123")
      (libsource (lib "eagle-import") (part "SINGLES_SOD123"))
    )
    (comp (ref "LED2401")
      (value "blue")
      (footprint "eagle-import:S_0805")
      (fields (field (name "FUNCTION") "SP_1_P1V5") (field (name "PART_CODE_BEL") "LED_PAC_S_0805_VAL_blue"))
      (libsource (lib "eagle-import") (part "LED_S_0805"))
    )
    (comp (ref "LED2402")
      (value "green")
      (footprint "eagle-import:S_0805")
      (fields (field (name "FUNCTION") "SP_1_P1V8") (field (name "PART_CODE_BEL") "LED_PAC_S_0805_VAL_green"))
      (libsource (lib "eagle-import") (part "LED_S_0805"))
    )
    (comp (ref "LED2403")
      (value "yellow")
      (footprint "eagle-import:S_0805")
      (fields
        (field (name "FUNCTION") "SP_1_P3V3")
        (field (name "PART_CODE_BEL") "LED_PAC_S_0805_VAL_yellow")
      )
      (libsource (lib "eagle-import") (part "LED_S_0805"))
    )
    (comp (ref "LED2404")
      (value "green")
      (footprint "eagle-import:S_0805")
      (fields (field (name "FUNCTION") "SP_1_P2V5") (field (name "PART_CODE_BEL") "LED_PAC_S_0805_VAL_green"))
      (libsource (lib "eagle-import") (part "LED_S_0805"))
    )
    (comp (ref "R2401")
      (value "2k7")
      (footprint "eagle-import:S_0805")
      (fields (field (name "PART_CODE_BEL") "R_PAC_S_0805_VAL_2k7"))
      (libsource (lib "eagle-import") (part "R_S_0805"))
    )
    (comp (ref "R2402")
      (value "2k7")
      (footprint "eagle-import:S_0805")
      (fields (field (name "PART_CODE_BEL") "R_PAC_S_0805_VAL_2k7"))
      (libsource (lib "eagle-import") (part "R_S_0805"))
    )
    (comp (ref "R2403")
      (value "2k7")
      (footprint "eagle-import:S_0805")
      (fields (field (name "PART_CODE_BEL") "R_PAC_S_0805_VAL_2k7"))
      (libsource (lib "eagle-import") (part "R_S_0805"))
    )
    (comp (ref "R2404")
      (value "330")
      (footprint "eagle-import:S_0805")
      (fields (field (name "PART_CODE_BEL") "R_PAC_S_0805_VAL_330"))
      (libsource (lib "eagle-import") (part "R_S_0805"))
    )
    (comp (ref "R2405")
      (value "2k7")
      (footprint "eagle-import:S_0805")
      (fields (field (name "PART_CODE_BEL") "R_PAC_S_0805_VAL_2k7"))
      (libsource (lib "eagle-import") (part "R_S_0805"))
    )
    (comp (ref "R2406")
      (value "160")
      (footprint "eagle-import:S_0805")
      (fields (field (name "PART_CODE_BEL") "R_PAC_S_0805_VAL_160"))
      (libsource (lib "eagle-import") (part "R_S_0805"))
    )
    (comp (ref "R2407")
      (value "2k7")
      (footprint "eagle-import:S_0805")
      (fields (field (name "PART_CODE_BEL") "R_PAC_S_0805_VAL_2k7"))
      (libsource (lib "eagle-import") (part "R_S_0805"))
    )
    (comp (ref "R2408")
      (value "470")
      (footprint "eagle-import:S_0805")
      (fields (field (name "PART_CODE_BEL") "R_PAC_S_0805_VAL_470"))
      (libsource (lib "eagle-import") (part "R_S_0805"))
    )
    (comp (ref "R2409")
      (value "160")
      (footprint "eagle-import:S_0805")
      (fields (field (name "PART_CODE_BEL") "R_PAC_S_0805_VAL_160"))
      (libsource (lib "eagle-import") (part "R_S_0805"))
    )
    (comp (ref "T2401")
      (value "NX2301P")
      (footprint "eagle-import:S_SOT23")
      (fields (field (name "PART_CODE_BEL") "T_PAC_S_SOT23_VAL_NX2301P"))
      (libsource (lib "eagle-import") (part "P-MOSFET"))
    )
    (comp (ref "T2402")
      (value "NX2301P")
      (footprint "eagle-import:S_SOT23")
      (fields (field (name "PART_CODE_BEL") "T_PAC_S_SOT23_VAL_NX2301P"))
      (libsource (lib "eagle-import") (part "P-MOSFET"))
    )
    (comp (ref "T2403")
      (value "NX2301P")
      (footprint "eagle-import:S_SOT23")
      (fields (field (name "PART_CODE_BEL") "T_PAC_S_SOT23_VAL_NX2301P"))
      (libsource (lib "eagle-import") (part "P-MOSFET"))
    )
    (comp (ref "T2404")
      (value "NX2301P")
      (footprint "eagle-import:S_SOT23")
      (fields (field (name "PART_CODE_BEL") "T_PAC_S_SOT23_VAL_NX2301P"))
      (libsource (lib "eagle-import") (part "P-MOSFET"))
    )
    (comp (ref "T2405")
      (value "NX2301P")
      (footprint "eagle-import:S_SOT23")
      (fields (field (name "PART_CODE_BEL") "T_PAC_S_SOT23_VAL_NX2301P"))
      (libsource (lib "eagle-import") (part "P-MOSFET"))
    )
    (comp (ref "T2406")
      (value "NX2301P")
      (footprint "eagle-import:S_SOT23")
      (fields (field (name "PART_CODE_BEL") "T_PAC_S_SOT23_VAL_NX2301P"))
      (libsource (lib "eagle-import") (part "P-MOSFET"))
    )
    (comp (ref "T2407")
      (value "DMG3420U")
      (footprint "eagle-import:S_SOT23")
      (fields (field (name "PART_CODE_BEL") "T_PAC_S_SOT23_VAL_DMG3420U"))
      (libsource (lib "eagle-import") (part "N-MOSFET_S_SOT23"))
    )
    (comp (ref "T2408")
      (value "DMG3420U")
      (footprint "eagle-import:S_SOT23")
      (fields (field (name "PART_CODE_BEL") "T_PAC_S_SOT23_VAL_DMG3420U"))
      (libsource (lib "eagle-import") (part "N-MOSFET_S_SOT23"))
    )
    (comp (ref "C601")
      (value "100n")
      (footprint "eagle-import:S_0805")
      (fields (field (name "PART_CODE_BEL") "C_PAC_S_0805_VAL_100n"))
      (libsource (lib "eagle-import") (part "C_S_0805"))
    )
    (comp (ref "C602")
      (value "100n")
      (footprint "eagle-import:S_0805")
      (fields (field (name "PART_CODE_BEL") "C_PAC_S_0805_VAL_100n"))
      (libsource (lib "eagle-import") (part "C_S_0805"))
    )
    (comp (ref "C603")
      (value "100n")
      (footprint "eagle-import:S_0805")
      (fields (field (name "PART_CODE_BEL") "C_PAC_S_0805_VAL_100n"))
      (libsource (lib "eagle-import") (part "C_S_0805"))
    )
    (comp (ref "IC601")
      (value "AS6C4008-55PCN")
      (footprint "eagle-import:T_NDIP32")
      (fields (field (name "PART_CODE_BEL") "IC_PAC_T_NDIP32_VAL_AS6C4008-55PCN"))
      (libsource (lib "eagle-import") (part "512K_X_8_T_NDIP32"))
    )
    (comp (ref "IC602")
      (value "AS6C4008-55PCN")
      (footprint "eagle-import:T_NDIP32")
      (fields (field (name "PART_CODE_BEL") "IC_PAC_T_NDIP32_VAL_AS6C4008-55PCN"))
      (libsource (lib "eagle-import") (part "512K_X_8_T_NDIP32"))
    )
    (comp (ref "IC603")
      (value "AS6C4008-55PCN")
      (footprint "eagle-import:T_NDIP32")
      (fields (field (name "PART_CODE_BEL") "IC_PAC_T_NDIP32_VAL_AS6C4008-55PCN"))
      (libsource (lib "eagle-import") (part "512K_X_8_T_NDIP32"))
    )
    (comp (ref "TP601")
      (value "TEST_POINT_T_SMALL")
      (footprint "eagle-import:T_TEST_POINT_SMALL")
      (libsource (lib "eagle-import") (part "TEST_POINT_T_SMALL"))
    )
    (comp (ref "TP602")
      (value "TEST_POINT_T_SMALL")
      (footprint "eagle-import:T_TEST_POINT_SMALL")
      (libsource (lib "eagle-import") (part "TEST_POINT_T_SMALL"))
    )
    (comp (ref "TP603")
      (value "TEST_POINT_T_SMALL")
      (footprint "eagle-import:T_TEST_POINT_SMALL")
      (libsource (lib "eagle-import") (part "TEST_POINT_T_SMALL"))
    )
    (comp (ref "LED2101")
      (value "yellow")
      (footprint "eagle-import:S_0805")
      (fields (field (name "FUNCTION") "SP_1_TCK") (field (name "PART_CODE_BEL") "LED_PAC_S_0805_VAL_yellow"))
      (libsource (lib "eagle-import") (part "LED_S_0805"))
    )
    (comp (ref "LED2102")
      (value "yellow")
      (footprint "eagle-import:S_0805")
      (fields (field (name "FUNCTION") "SP_2_TCK") (field (name "PART_CODE_BEL") "LED_PAC_S_0805_VAL_yellow"))
      (libsource (lib "eagle-import") (part "LED_S_0805"))
    )
    (comp (ref "LED2103")
      (value "blue")
      (footprint "eagle-import:S_0805")
      (fields (field (name "FUNCTION") "SP_1_TMS") (field (name "PART_CODE_BEL") "LED_PAC_S_0805_VAL_blue"))
      (libsource (lib "eagle-import") (part "LED_S_0805"))
    )
    (comp (ref "LED2104")
      (value "blue")
      (footprint "eagle-import:S_0805")
      (fields (field (name "FUNCTION") "SP_2_TMS") (field (name "PART_CODE_BEL") "LED_PAC_S_0805_VAL_blue"))
      (libsource (lib "eagle-import") (part "LED_S_0805"))
    )
    (comp (ref "LED2105")
      (value "green")
      (footprint "eagle-import:S_0805")
      (fields (field (name "FUNCTION") "SP_1_TDO") (field (name "PART_CODE_BEL") "LED_PAC_S_0805_VAL_green"))
      (libsource (lib "eagle-import") (part "LED_S_0805"))
    )
    (comp (ref "LED2106")
      (value "green")
      (footprint "eagle-import:S_0805")
      (fields (field (name "FUNCTION") "SP_2_TDO") (field (name "PART_CODE_BEL") "LED_PAC_S_0805_VAL_green"))
      (libsource (lib "eagle-import") (part "LED_S_0805"))
    )
    (comp (ref "LED2107")
      (value "green")
      (footprint "eagle-import:S_0805")
      (fields (field (name "FUNCTION") "SP_1_TDI") (field (name "PART_CODE_BEL") "LED_PAC_S_0805_VAL_green"))
      (libsource (lib "eagle-import") (part "LED_S_0805"))
    )
    (comp (ref "LED2108")
      (value "green")
      (footprint "eagle-import:S_0805")
      (fields (field (name "FUNCTION") "SP_2_TDI") (field (name "PART_CODE_BEL") "LED_PAC_S_0805_VAL_green"))
      (libsource (lib "eagle-import") (part "LED_S_0805"))
    )
    (comp (ref "LED2109")
      (value "red")
      (footprint "eagle-import:S_0805")
      (fields (field (name "FUNCTION") "SP_1_FAIL") (field (name "PART_CODE_BEL") "LED_PAC_S_0805_VAL_red"))
      (libsource (lib "eagle-import") (part "LED_S_0805"))
    )
    (comp (ref "LED2110")
      (value "red")
      (footprint "eagle-import:S_0805")
      (fields (field (name "FUNCTION") "SP_2_FAIL") (field (name "PART_CODE_BEL") "LED_PAC_S_0805_VAL_red"))
      (libsource (lib "eagle-import") (part "LED_S_0805"))
    )
    (comp (ref "R2101")
      (value "100k")
      (footprint "eagle-import:S_0805")
      (fields (field (name "PART_CODE_BEL") "R_PAC_S_0805_VAL_100k"))
      (libsource (lib "eagle-import") (part "R_S_0805"))
    )
    (comp (ref "R2102")
      (value "100k")
      (footprint "eagle-import:S_0805")
      (fields (field (name "PART_CODE_BEL") "R_PAC_S_0805_VAL_100k"))
      (libsource (lib "eagle-import") (part "R_S_0805"))
    )
    (comp (ref "R2103")
      (value "470")
      (footprint "eagle-import:S_0805")
      (fields (field (name "PART_CODE_BEL") "R_PAC_S_0805_VAL_470"))
      (libsource (lib "eagle-import") (part "R_S_0805"))
    )
    (comp (ref "R2104")
      (value "470")
      (footprint "eagle-import:S_0805")
      (fields (field (name "PART_CODE_BEL") "R_PAC_S_0805_VAL_470"))
      (libsource (lib "eagle-import") (part "R_S_0805"))
    )
    (comp (ref "R2105")
      (value "100k")
      (footprint "eagle-import:S_0805")
      (fields (field (name "PART_CODE_BEL") "R_PAC_S_0805_VAL_100k"))
      (libsource (lib "eagle-import") (part "R_S_0805"))
    )
    (comp (ref "R2106")
      (value "100k")
      (footprint "eagle-import:S_0805")
      (fields (field (name "PART_CODE_BEL") "R_PAC_S_0805_VAL_100k"))
      (libsource (lib "eagle-import") (part "R_S_0805"))
    )
    (comp (ref "R2107")
      (value "330")
      (footprint "eagle-import:S_0805")
      (fields (field (name "PART_CODE_BEL") "R_PAC_S_0805_VAL_330"))
      (libsource (lib "eagle-import") (part "R_S_0805"))
    )
    (comp (ref "R2108")
      (value "330")
      (footprint "eagle-import:S_0805")
      (fields (field (name "PART_CODE_BEL") "R_PAC_S_0805_VAL_330"))
      (libsource (lib "eagle-import") (part "R_S_0805"))
    )
    (comp (ref "R2109")
      (value "100k")
      (footprint "eagle-import:S_0805")
      (fields (field (name "PART_CODE_BEL") "R_PAC_S_0805_VAL_100k"))
      (libsource (lib "eagle-import") (part "R_S_0805"))
    )
    (comp (ref "R2110")
      (value "100k")
      (footprint "eagle-import:S_0805")
      (fields (field (name "PART_CODE_BEL") "R_PAC_S_0805_VAL_100k"))
      (libsource (lib "eagle-import") (part "R_S_0805"))
    )
    (comp (ref "R2111")
      (value "160")
      (footprint "eagle-import:S_0805")
      (fields (field (name "PART_CODE_BEL") "R_PAC_S_0805_VAL_160"))
      (libsource (lib "eagle-import") (part "R_S_0805"))
    )
    (comp (ref "R2112")
      (value "160")
      (footprint "eagle-import:S_0805")
      (fields (field (name "PART_CODE_BEL") "R_PAC_S_0805_VAL_160"))
      (libsource (lib "eagle-import") (part "R_S_0805"))
    )
    (comp (ref "R2113")
      (value "100k")
      (footprint "eagle-import:S_0805")
      (fields (field (name "PART_CODE_BEL") "R_PAC_S_0805_VAL_100k"))
      (libsource (lib "eagle-import") (part "R_S_0805"))
    )
    (comp (ref "R2114")
      (value "100k")
      (footprint "eagle-import:S_0805")
      (fields (field (name "PART_CODE_BEL") "R_PAC_S_0805_VAL_100k"))
      (libsource (lib "eagle-import") (part "R_S_0805"))
    )
    (comp (ref "R2115")
      (value "160")
      (footprint "eagle-import:S_0805")
      (fields (field (name "PART_CODE_BEL") "R_PAC_S_0805_VAL_160"))
      (libsource (lib "eagle-import") (part "R_S_0805"))
    )
    (comp (ref "R2116")
      (value "160")
      (footprint "eagle-import:S_0805")
      (fields (field (name "PART_CODE_BEL") "R_PAC_S_0805_VAL_160"))
      (libsource (lib "eagle-import") (part "R_S_0805"))
    )
    (comp (ref "R2117")
      (value "100k")
      (footprint "eagle-import:S_0805")
      (fields (field (name "PART_CODE_BEL") "R_PAC_S_0805_VAL_100k"))
      (libsource (lib "eagle-import") (part "R_S_0805"))
    )
    (comp (ref "R2118")
      (value "100k")
      (footprint "eagle-import:S_0805")
      (fields (field (name "PART_CODE_BEL") "R_PAC_S_0805_VAL_100k"))
      (libsource (lib "eagle-import") (part "R_S_0805"))
    )
    (comp (ref "R2119")
      (value "750")
      (footprint "eagle-import:S_0805")
      (fields (field (name "PART_CODE_BEL") "R_PAC_S_0805_VAL_750"))
      (libsource (lib "eagle-import") (part "R_S_0805"))
    )
    (comp (ref "R2120")
      (value "750")
      (footprint "eagle-import:S_0805")
      (fields (field (name "PART_CODE_BEL") "R_PAC_S_0805_VAL_750"))
      (libsource (lib "eagle-import") (part "R_S_0805"))
    )
    (comp (ref "T2101")
      (value "DMG3420U")
      (footprint "eagle-import:S_SOT23")
      (fields (field (name "PART_CODE_BEL") "T_PAC_S_SOT23_VAL_DMG3420U"))
      (libsource (lib "eagle-import") (part "N-MOSFET_S_SOT23"))
    )
    (comp (ref "T2102")
      (value "DMG3420U")
      (footprint "eagle-import:S_SOT23")
      (fields (field (name "PART_CODE_BEL") "T_PAC_S_SOT23_VAL_DMG3420U"))
      (libsource (lib "eagle-import") (part "N-MOSFET_S_SOT23"))
    )
    (comp (ref "T2103")
      (value "DMG3420U")
      (footprint "eagle-import:S_SOT23")
      (fields (field (name "PART_CODE_BEL") "T_PAC_S_SOT23_VAL_DMG3420U"))
      (libsource (lib "eagle-import") (part "N-MOSFET_S_SOT23"))
    )
    (comp (ref "T2104")
      (value "DMG3420U")
      (footprint "eagle-import:S_SOT23")
      (fields (field (name "PART_CODE_BEL") "T_PAC_S_SOT23_VAL_DMG3420U"))
      (libsource (lib "eagle-import") (part "N-MOSFET_S_SOT23"))
    )
    (comp (ref "T2105")
      (value "DMG3420U")
      (footprint "eagle-import:S_SOT23")
      (fields (field (name "PART_CODE_BEL") "T_PAC_S_SOT23_VAL_DMG3420U"))
      (libsource (lib "eagle-import") (part "N-MOSFET_S_SOT23"))
    )
    (comp (ref "T2106")
      (value "DMG3420U")
      (footprint "eagle-import:S_SOT23")
      (fields (field (name "PART_CODE_BEL") "T_PAC_S_SOT23_VAL_DMG3420U"))
      (libsource (lib "eagle-import") (part "N-MOSFET_S_SOT23"))
    )
    (comp (ref "T2107")
      (value "DMG3420U")
      (footprint "eagle-import:S_SOT23")
      (fields (field (name "PART_CODE_BEL") "T_PAC_S_SOT23_VAL_DMG3420U"))
      (libsource (lib "eagle-import") (part "N-MOSFET_S_SOT23"))
    )
    (comp (ref "T2108")
      (value "DMG3420U")
      (footprint "eagle-import:S_SOT23")
      (fields (field (name "PART_CODE_BEL") "T_PAC_S_SOT23_VAL_DMG3420U"))
      (libsource (lib "eagle-import") (part "N-MOSFET_S_SOT23"))
    )
    (comp (ref "T2109")
      (value "DMG3420U")
      (footprint "eagle-import:S_SOT23")
      (fields (field (name "PART_CODE_BEL") "T_PAC_S_SOT23_VAL_DMG3420U"))
      (libsource (lib "eagle-import") (part "N-MOSFET_S_SOT23"))
    )
    (comp (ref "T2110")
      (value "DMG3420U")
      (footprint "eagle-import:S_SOT23")
      (fields (field (name "PART_CODE_BEL") "T_PAC_S_SOT23_VAL_DMG3420U"))
      (libsource (lib "eagle-import") (part "N-MOSFET_S_SOT23"))
    )
    (comp (ref "C201")
      (value "100n")
      (footprint "eagle-import:S_0805")
      (fields (field (name "PART_CODE_BEL") "C_PAC_S_0805_VAL_100n"))
      (libsource (lib "eagle-import") (part "C_S_0805"))
    )
    (comp (ref "C202")
      (value "100n")
      (footprint "eagle-import:S_0805")
      (fields (field (name "PART_CODE_BEL") "C_PAC_S_0805_VAL_100n"))
      (libsource (lib "eagle-import") (part "C_S_0805"))
    )
    (comp (ref "C203")
      (value "100n")
      (footprint "eagle-import:S_0805")
      (fields (field (name "PART_CODE_BEL") "C_PAC_S_0805_VAL_100n"))
      (libsource (lib "eagle-import") (part "C_S_0805"))
    )
    (comp (ref "C204")
      (value "1u")
      (footprint "eagle-import:S_0805")
      (fields (field (name "PART_CODE_BEL") "C_PAC_S_0805_VAL_1u"))
      (libsource (lib "eagle-import") (part "C_S_0805"))
    )
    (comp (ref "C205")
      (value "1u")
      (footprint "eagle-import:S_0805")
      (fields (field (name "PART_CODE_BEL") "C_PAC_S_0805_VAL_1u"))
      (libsource (lib "eagle-import") (part "C_S_0805"))
    )
    (comp (ref "C206")
      (value "1u")
      (footprint "eagle-import:S_0805")
      (fields (field (name "PART_CODE_BEL") "C_PAC_S_0805_VAL_1u"))
      (libsource (lib "eagle-import") (part "C_S_0805"))
    )
    (comp (ref "C207")
      (value "100n")
      (footprint "eagle-import:S_0805")
      (fields (field (name "PART_CODE_BEL") "C_PAC_S_0805_VAL_100n"))
      (libsource (lib "eagle-import") (part "C_S_0805"))
    )
    (comp (ref "C208")
      (value "100n")
      (footprint "eagle-import:S_0805")
      (fields (field (name "PART_CODE_BEL") "C_PAC_S_0805_VAL_100n"))
      (libsource (lib "eagle-import") (part "C_S_0805"))
    )
    (comp (ref "C209")
      (value "1u")
      (footprint "eagle-import:S_0805")
      (fields (field (name "PART_CODE_BEL") "C_PAC_S_0805_VAL_1u"))
      (libsource (lib "eagle-import") (part "C_S_0805"))
    )
    (comp (ref "C210")
      (value "1u")
      (footprint "eagle-import:S_0805")
      (fields (field (name "PART_CODE_BEL") "C_PAC_S_0805_VAL_1u"))
      (libsource (lib "eagle-import") (part "C_S_0805"))
    )
    (comp (ref "H201")
      (value "HOLE_4.1_PAD")
      (footprint "eagle-import:4.1_PAD")
      (libsource (lib "eagle-import") (part "HOLE_4.1_PAD"))
    )
    (comp (ref "H202")
      (value "HOLE_4.1_PAD")
      (footprint "eagle-import:4.1_PAD")
      (libsource (lib "eagle-import") (part "HOLE_4.1_PAD"))
    )
    (comp (ref "H203")
      (value "HOLE_4.1_PAD")
      (footprint "eagle-import:4.1_PAD")
      (libsource (lib "eagle-import") (part "HOLE_4.1_PAD"))
    )
    (comp (ref "IC201")
      (value "LM1117T-ADJ")
      (footprint "eagle-import:T_TO220-3_VERTICAL")
      (fields (field (name "PART_CODE_BEL") "IC_PAC_T_TO220-3_VERTICAL_VAL_LM1117T-ADJ"))
      (libsource (lib "eagle-import") (part "LMXX17-T_VERTICAL"))
    )
    (comp (ref "IC202")
      (value "LM1117T-ADJ")
      (footprint "eagle-import:T_TO220-3_VERTICAL")
      (fields (field (name "PART_CODE_BEL") "IC_PAC_T_TO220-3_VERTICAL_VAL_LM1117T-ADJ"))
      (libsource (lib "eagle-import") (part "LMXX17-T_VERTICAL"))
    )
    (comp (ref "IC203")
      (value "LM1117T-ADJ")
      (footprint "eagle-import:T_TO220-3_VERTICAL")
      (fields (field (name "PART_CODE_BEL") "IC_PAC_T_TO220-3_VERTICAL_VAL_LM1117T-ADJ"))
      (libsource (lib "eagle-import") (part "LMXX17-T_VERTICAL"))
    )
    (comp (ref "IC204")
      (value "LM1117T-ADJ")
      (footprint "eagle-import:T_TO220-3_VERTICAL")
      (fields (field (name "PART_CODE_BEL") "IC_PAC_T_TO220-3_VERTICAL_VAL_LM1117T-ADJ"))
      (libsource (lib "eagle-import") (part "LMXX17-T_VERTICAL"))
    )
    (comp (ref "IC205")
      (value "LM1117T-ADJ")
      (footprint "eagle-import:T_TO220-3_HORIZONTAL")
      (fields (field (name "PART_CODE_BEL") "IC_PAC_T_TO220-3_HORIZONTAL_VAL_LM1117T-ADJ"))
      (libsource (lib "eagle-import") (part "LMXX17-T_HORIZONTAL"))
    )
    (comp (ref "J201")
      (value "SOLDER_JUMPER-N")
      (footprint "eagle-import:S_SOLDER_JUMPER_NARROW")
      (libsource (lib "eagle-import") (part "SOLDER_JUMPER-N"))
    )
    (comp (ref "J202")
      (value "SOLDER_JUMPER-N")
      (footprint "eagle-import:S_SOLDER_JUMPER_NARROW")
      (libsource (lib "eagle-import") (part "SOLDER_JUMPER-N"))
    )
    (comp (ref "J203")
      (value "SOLDER_JUMPER-N")
      (footprint "eagle-import:S_SOLDER_JUMPER_NARROW")
      (libsource (lib "eagle-import") (part "SOLDER_JUMPER-N"))
    )
    (comp (ref "J204")
      (value "SOLDER_JUMPER-N")
      (footprint "eagle-import:S_SOLDER_JUMPER_NARROW")
      (libsource (lib "eagle-import") (part "SOLDER_JUMPER-N"))
    )
    (comp (ref "J205")
      (value "SOLDER_JUMPER-N")
      (footprint "eagle-import:S_SOLDER_JUMPER_NARROW")
      (libsource (lib "eagle-import") (part "SOLDER_JUMPER-N"))
    )
    (comp (ref "LED201")
      (value "green")
      (footprint "eagle-import:S_0805")
      (fields (field (name "FUNCTION") "PWR_ON") (field (name "PART_CODE_BEL") "LED_PAC_S_0805_VAL_green"))
      (libsource (lib "eagle-import") (part "LED_S_0805"))
    )
    (comp (ref "R201")
      (value "240")
      (footprint "eagle-import:S_0805")
      (fields (field (name "PART_CODE_BEL") "R_PAC_S_0805_VAL_240"))
      (libsource (lib "eagle-import") (part "R_S_0805"))
    )
    (comp (ref "R202")
      (value "715")
      (footprint "eagle-import:S_0805")
      (fields (field (name "PART_CODE_BEL") "R_PAC_S_0805_VAL_715"))
      (libsource (lib "eagle-import") (part "R_S_0805"))
    )
    (comp (ref "R203")
      (value "240")
      (footprint "eagle-import:S_0805")
      (fields (field (name "PART_CODE_BEL") "R_PAC_S_0805_VAL_240"))
      (libsource (lib "eagle-import") (part "R_S_0805"))
    )
    (comp (ref "R204")
      (value "240")
      (footprint "eagle-import:S_0805")
      (fields (field (name "PART_CODE_BEL") "R_PAC_S_0805_VAL_240"))
      (libsource (lib "eagle-import") (part "R_S_0805"))
    )
    (comp (ref "R205")
      (value "240")
      (footprint "eagle-import:S_0805")
      (fields (field (name "PART_CODE_BEL") "R_PAC_S_0805_VAL_240"))
      (libsource (lib "eagle-import") (part "R_S_0805"))
    )
    (comp (ref "R206")
      (value "330")
      (footprint "eagle-import:S_0805")
      (fields (field (name "PART_CODE_BEL") "R_PAC_S_0805_VAL_330"))
      (libsource (lib "eagle-import") (part "R_S_0805"))
    )
    (comp (ref "R207")
      (value "105")
      (footprint "eagle-import:S_0805")
      (fields (field (name "PART_CODE_BEL") "R_PAC_S_0805_VAL_105"))
      (libsource (lib "eagle-import") (part "R_S_0805"))
    )
    (comp (ref "R208")
      (value "392")
      (footprint "eagle-import:S_0805")
      (fields (field (name "PART_CODE_BEL") "R_PAC_S_0805_VAL_392"))
      (libsource (lib "eagle-import") (part "R_S_0805"))
    )
    (comp (ref "R209")
      (value "240")
      (footprint "eagle-import:S_0805")
      (fields (field (name "PART_CODE_BEL") "R_PAC_S_0805_VAL_240"))
      (libsource (lib "eagle-import") (part "R_S_0805"))
    )
    (comp (ref "R210")
      (value "240")
      (footprint "eagle-import:S_0805")
      (fields (field (name "PART_CODE_BEL") "R_PAC_S_0805_VAL_240"))
      (libsource (lib "eagle-import") (part "R_S_0805"))
    )
    (comp (ref "TP201")
      (value "TEST_POINT_T_SMALL")
      (footprint "eagle-import:T_TEST_POINT_SMALL")
      (libsource (lib "eagle-import") (part "TEST_POINT_T_SMALL"))
    )
    (comp (ref "TP202")
      (value "+1V2")
      (footprint "eagle-import:T_TEST_POINT_SMALL")
      (libsource (lib "eagle-import") (part "TEST_POINT_T_SMALL"))
    )
    (comp (ref "TP203")
      (value "+2V5")
      (footprint "eagle-import:T_TEST_POINT_SMALL")
      (libsource (lib "eagle-import") (part "TEST_POINT_T_SMALL"))
    )
    (comp (ref "TP204")
      (value "TEST_POINT_T_SMALL")
      (footprint "eagle-import:T_TEST_POINT_SMALL")
      (libsource (lib "eagle-import") (part "TEST_POINT_T_SMALL"))
    )
    (comp (ref "TP205")
      (value "+2V5")
      (footprint "eagle-import:T_TEST_POINT_SMALL")
      (libsource (lib "eagle-import") (part "TEST_POINT_T_SMALL"))
    )
    (comp (ref "C1801")
      (value "100n")
      (footprint "eagle-import:S_0805")
      (fields (field (name "PART_CODE_BEL") "C_PAC_S_0805_VAL_100n"))
      (libsource (lib "eagle-import") (part "C_S_0805"))
    )
    (comp (ref "C1802")
      (value "100n")
      (footprint "eagle-import:S_0805")
      (fields (field (name "PART_CODE_BEL") "C_PAC_S_0805_VAL_100n"))
      (libsource (lib "eagle-import") (part "C_S_0805"))
    )
    (comp (ref "C1803")
      (value "100n")
      (footprint "eagle-import:S_0805")
      (fields (field (name "PART_CODE_BEL") "C_PAC_S_0805_VAL_100n"))
      (libsource (lib "eagle-import") (part "C_S_0805"))
    )
    (comp (ref "FD1801")
      (value "FIDUCIAL_CROSSHAIR")
      (footprint "eagle-import:CROSSHAIR")
      (libsource (lib "eagle-import") (part "FIDUCIAL_CROSSHAIR"))
    )
    (comp (ref "FD1802")
      (value "FIDUCIAL_CROSSHAIR")
      (footprint "eagle-import:CROSSHAIR")
      (libsource (lib "eagle-import") (part "FIDUCIAL_CROSSHAIR"))
    )
    (comp (ref "H1801")
      (value "HOLE_4.1_PAD")
      (footprint "eagle-import:4.1_PAD")
      (libsource (lib "eagle-import") (part "HOLE_4.1_PAD"))
    )
    (comp (ref "H1802")
      (value "HOLE_4.1_PAD")
      (footprint "eagle-import:4.1_PAD")
      (libsource (lib "eagle-import") (part "HOLE_4.1_PAD"))
    )
    (comp (ref "H1803")
      (value "HOLE_4.1_PAD")
      (footprint "eagle-import:4.1_PAD")
      (libsource (lib "eagle-import") (part "HOLE_4.1_PAD"))
    )
    (comp (ref "H1804")
      (value "HOLE_4.1_PAD")
      (footprint "eagle-import:4.1_PAD")
      (libsource (lib "eagle-import") (part "HOLE_4.1_PAD"))
    )
    (comp (ref "IC1801")
      (value "4093N")
      (footprint "eagle-import:T_NDIP14")
      (libsource (lib "eagle-import") (part "4093N"))
    )
    (comp (ref "LED1801")
      (value "green")
      (footprint "eagle-import:S_0805")
      (fields (field (name "FUNCTION") "PASS") (field (name "PART_CODE_BEL") "LED_PAC_S_0805_VAL_green"))
      (libsource (lib "eagle-import") (part "LED_S_0805"))
    )
    (comp (ref "LED1802")
      (value "red")
      (footprint "eagle-import:S_0805")
      (fields (field (name "FUNCTION") "FAIL") (field (name "PART_CODE_BEL") "LED_PAC_S_0805_VAL_red"))
      (libsource (lib "eagle-import") (part "LED_S_0805"))
    )
    (comp (ref "R1801")
      (value "160")
      (footprint "eagle-import:S_0805")
      (fields (field (name "PART_CODE_BEL") "R_PAC_S_0805_VAL_160"))
      (libsource (lib "eagle-import") (part "R_S_0805"))
    )
    (comp (ref "R1802")
      (value "750")
      (footprint "eagle-import:S_0805")
      (fields (field (name "PART_CODE_BEL") "R_PAC_S_0805_VAL_750"))
      (libsource (lib "eagle-import") (part "R_S_0805"))
    )
    (comp (ref "R1803")
      (value "1M")
      (footprint "eagle-import:S_0805")
      (fields (field (name "PART_CODE_BEL") "R_PAC_S_0805_VAL_1M"))
      (libsource (lib "eagle-import") (part "R_S_0805"))
    )
    (comp (ref "R1804")
      (value "1M")
      (footprint "eagle-import:S_0805")
      (fields (field (name "PART_CODE_BEL") "R_PAC_S_0805_VAL_1M"))
      (libsource (lib "eagle-import") (part "R_S_0805"))
    )
    (comp (ref "RN1801")
      (value "100")
      (footprint "eagle-import:T_SIL8")
      (fields (field (name "PART_CODE_BEL") "RN_PAC_T_SIL8_VAL_100"))
      (libsource (lib "eagle-import") (part "RN_4T_SIL8"))
    )
    (comp (ref "S1801")
      (value "PUSH_BUTTON_T_6X6MM")
      (footprint "eagle-import:T_PUSH_BUTTON_6X6")
      (fields (field (name "FUNCTION") "STOP") (field (name "PART_CODE_BEL") "S_PAC_T_PUSH_BUTTON_6X6mm"))
      (libsource (lib "eagle-import") (part "PUSH_BUTTON_T_6X6MM"))
    )
    (comp (ref "S1802")
      (value "PUSH_BUTTON_T_6X6MM")
      (footprint "eagle-import:T_PUSH_BUTTON_6X6")
      (fields (field (name "FUNCTION") "START") (field (name "PART_CODE_BEL") "S_PAC_T_PUSH_BUTTON_6X6mm"))
      (libsource (lib "eagle-import") (part "PUSH_BUTTON_T_6X6MM"))
    )
    (comp (ref "TP1801")
      (value "TEST_POINT_T_SMALL")
      (footprint "eagle-import:T_TEST_POINT_SMALL")
      (libsource (lib "eagle-import") (part "TEST_POINT_T_SMALL"))
    )
    (comp (ref "TP1802")
      (value "TEST_POINT_T_SMALL")
      (footprint "eagle-import:T_TEST_POINT_SMALL")
      (libsource (lib "eagle-import") (part "TEST_POINT_T_SMALL"))
    )
    (comp (ref "TP1001")
      (value "TEST_POINT_T_SMALL")
      (footprint "eagle-import:T_TEST_POINT_SMALL")
      (libsource (lib "eagle-import") (part "TEST_POINT_T_SMALL"))
    )
    (comp (ref "TP1002")
      (value "TEST_POINT_T_SMALL")
      (footprint "eagle-import:T_TEST_POINT_SMALL")
      (libsource (lib "eagle-import") (part "TEST_POINT_T_SMALL"))
    )
    (comp (ref "TP1003")
      (value "TEST_POINT_T_SMALL")
      (footprint "eagle-import:T_TEST_POINT_SMALL")
      (libsource (lib "eagle-import") (part "TEST_POINT_T_SMALL"))
    )
    (comp (ref "C401")
      (value "1u")
      (footprint "eagle-import:S_0805")
      (fields (field (name "PART_CODE_BEL") "C_PAC_S_0805_VAL_1u"))
      (libsource (lib "eagle-import") (part "C_S_0805"))
    )
    (comp (ref "C402")
      (value "100u")
      (footprint "eagle-import:S_6032")
      (fields (field (name "PART_CODE_BEL") "C_PAC_S_6032_VAL_100u_Vmax_16V"))
      (libsource (lib "eagle-import") (part "C_POL_S_6032"))
    )
    (comp (ref "C403")
      (value "100n")
      (footprint "eagle-import:S_0805")
      (fields (field (name "PART_CODE_BEL") "C_PAC_S_0805_VAL_100n"))
      (libsource (lib "eagle-import") (part "C_S_0805"))
    )
    (comp (ref "D401")
      (value "1N4148")
      (footprint "eagle-import:S_SOD123")
      (libsource (lib "eagle-import") (part "SINGLES_SOD123"))
    )
    (comp (ref "IC401")
      (value "4093N")
      (footprint "eagle-import:T_NDIP14")
      (libsource (lib "eagle-import") (part "4093N"))
    )
    (comp (ref "R401")
      (value "1M")
      (footprint "eagle-import:S_0805")
      (fields (field (name "PART_CODE_BEL") "R_PAC_S_0805_VAL_1M"))
      (libsource (lib "eagle-import") (part "R_S_0805"))
    )
    (comp (ref "R402")
      (value "1M")
      (footprint "eagle-import:S_0805")
      (fields (field (name "PART_CODE_BEL") "R_PAC_S_0805_VAL_1M"))
      (libsource (lib "eagle-import") (part "R_S_0805"))
    )
    (comp (ref "R403")
      (value "1M")
      (footprint "eagle-import:S_0805")
      (fields (field (name "PART_CODE_BEL") "R_PAC_S_0805_VAL_1M"))
      (libsource (lib "eagle-import") (part "R_S_0805"))
    )
    (comp (ref "R404")
      (value "1k5")
      (footprint "eagle-import:S_0805")
      (fields (field (name "PART_CODE_BEL") "R_PAC_S_0805_VAL_1k5"))
      (libsource (lib "eagle-import") (part "R_S_0805"))
    )
    (comp (ref "R405")
      (value "33")
      (footprint "eagle-import:S_0805")
      (fields (field (name "PART_CODE_BEL") "R_PAC_S_0805_VAL_33"))
      (libsource (lib "eagle-import") (part "R_S_0805"))
    )
    (comp (ref "R406")
      (value "27k")
      (footprint "eagle-import:S_0805")
      (fields (field (name "PART_CODE_BEL") "R_PAC_S_0805_VAL_27k"))
      (libsource (lib "eagle-import") (part "R_S_0805"))
    )
    (comp (ref "R407")
      (value "1k5")
      (footprint "eagle-import:S_0805")
      (fields (field (name "PART_CODE_BEL") "R_PAC_S_0805_VAL_1k5"))
      (libsource (lib "eagle-import") (part "R_S_0805"))
    )
    (comp (ref "S401")
      (value "PUSH_BUTTON_T_6X6MM")
      (footprint "eagle-import:T_PUSH_BUTTON_6X6")
      (fields (field (name "FUNCTION") "RESET") (field (name "PART_CODE_BEL") "S_PAC_T_PUSH_BUTTON_6X6mm"))
      (libsource (lib "eagle-import") (part "PUSH_BUTTON_T_6X6MM"))
    )
    (comp (ref "T401")
      (value "DMG3420U")
      (footprint "eagle-import:S_SOT23")
      (fields (field (name "PART_CODE_BEL") "T_PAC_S_SOT23_VAL_DMG3420U"))
      (libsource (lib "eagle-import") (part "N-MOSFET_S_SOT23"))
    )
    (comp (ref "TP401")
      (value "clk_slow")
      (footprint "eagle-import:T_TEST_POINT_SMALL")
      (libsource (lib "eagle-import") (part "TEST_POINT_T_SMALL"))
    )
    (comp (ref "C1401")
      (value "100n")
      (footprint "eagle-import:S_0805")
      (fields (field (name "PART_CODE_BEL") "C_PAC_S_0805_VAL_100n"))
      (libsource (lib "eagle-import") (part "C_S_0805"))
    )
    (comp (ref "D1401")
      (value "BAT54S")
      (footprint "eagle-import:S_SOT23")
      (fields (field (name "PART_CODE_BEL") "D_PAC_S_SOT23_VAL_BAT54S"))
      (libsource (lib "eagle-import") (part "DUAL_COMMON_AC_SCHOTTKY"))
    )
    (comp (ref "D1402")
      (value "BAT54S")
      (footprint "eagle-import:S_SOT23")
      (fields (field (name "PART_CODE_BEL") "D_PAC_S_SOT23_VAL_BAT54S"))
      (libsource (lib "eagle-import") (part "DUAL_COMMON_AC_SCHOTTKY"))
    )
    (comp (ref "IC1401")
      (value "MAX962ESA+")
      (footprint "eagle-import:S_SO8")
      (fields (field (name "PART_CODE_BEL") "IC_PAC_S_SO8_VAL_MAX962ESA+"))
      (libsource (lib "eagle-import") (part "MAX962ESA"))
    )
    (comp (ref "R1401")
      (value "8k2")
      (footprint "eagle-import:S_0805")
      (fields (field (name "BOM") "NO") (field (name "PART_CODE_BEL") "R_PAC_S_0805_VAL_8k2"))
      (libsource (lib "eagle-import") (part "R_S_0805"))
    )
    (comp (ref "R1402")
      (value "2k7")
      (footprint "eagle-import:S_0805")
      (fields (field (name "BOM") "NO") (field (name "PART_CODE_BEL") "R_PAC_S_0805_VAL_2k7"))
      (libsource (lib "eagle-import") (part "R_S_0805"))
    )
    (comp (ref "R1403")
      (value "8k2")
      (footprint "eagle-import:S_0805")
      (fields (field (name "BOM") "NO") (field (name "PART_CODE_BEL") "R_PAC_S_0805_VAL_8k2"))
      (libsource (lib "eagle-import") (part "R_S_0805"))
    )
    (comp (ref "R1404")
      (value "2k7")
      (footprint "eagle-import:S_0805")
      (fields (field (name "BOM") "NO") (field (name "PART_CODE_BEL") "R_PAC_S_0805_VAL_2k7"))
      (libsource (lib "eagle-import") (part "R_S_0805"))
    )
    (comp (ref "TP1401")
      (value "TEST_POINT_T_SMALL")
      (footprint "eagle-import:T_TEST_POINT_SMALL")
      (libsource (lib "eagle-import") (part "TEST_POINT_T_SMALL"))
    )
    (comp (ref "TP1402")
      (value "TEST_POINT_T_SMALL")
      (footprint "eagle-import:T_TEST_POINT_SMALL")
      (libsource (lib "eagle-import") (part "TEST_POINT_T_SMALL"))
    )
    (comp (ref "TP1403")
      (value "TEST_POINT_T_SMALL")
      (footprint "eagle-import:T_TEST_POINT_SMALL")
      (libsource (lib "eagle-import") (part "TEST_POINT_T_SMALL"))
    )
    (comp (ref "TP1404")
      (value "TEST_POINT_T_SMALL")
      (footprint "eagle-import:T_TEST_POINT_SMALL")
      (libsource (lib "eagle-import") (part "TEST_POINT_T_SMALL"))
    )
    (comp (ref "TP1405")
      (value "TEST_POINT_T_SMALL")
      (footprint "eagle-import:T_TEST_POINT_SMALL")
      (libsource (lib "eagle-import") (part "TEST_POINT_T_SMALL"))
    )
    (comp (ref "TP1406")
      (value "TEST_POINT_T_SMALL")
      (footprint "eagle-import:T_TEST_POINT_SMALL")
      (libsource (lib "eagle-import") (part "TEST_POINT_T_SMALL"))
    )
    (comp (ref "LED2201")
      (value "red")
      (footprint "eagle-import:S_0805")
      (fields (field (name "FUNCTION") "SP_1_TRST") (field (name "PART_CODE_BEL") "LED_PAC_S_0805_VAL_red"))
      (libsource (lib "eagle-import") (part "LED_S_0805"))
    )
    (comp (ref "LED2202")
      (value "red")
      (footprint "eagle-import:S_0805")
      (fields (field (name "FUNCTION") "SP_2_TRST") (field (name "PART_CODE_BEL") "LED_PAC_S_0805_VAL_red"))
      (libsource (lib "eagle-import") (part "LED_S_0805"))
    )
    (comp (ref "R2201")
      (value "100k")
      (footprint "eagle-import:S_0805")
      (fields (field (name "PART_CODE_BEL") "R_PAC_S_0805_VAL_100k"))
      (libsource (lib "eagle-import") (part "R_S_0805"))
    )
    (comp (ref "R2202")
      (value "100k")
      (footprint "eagle-import:S_0805")
      (fields (field (name "PART_CODE_BEL") "R_PAC_S_0805_VAL_100k"))
      (libsource (lib "eagle-import") (part "R_S_0805"))
    )
    (comp (ref "R2203")
      (value "2k7")
      (footprint "eagle-import:S_0805")
      (fields (field (name "PART_CODE_BEL") "R_PAC_S_0805_VAL_2k7"))
      (libsource (lib "eagle-import") (part "R_S_0805"))
    )
    (comp (ref "R2204")
      (value "2k7")
      (footprint "eagle-import:S_0805")
      (fields (field (name "PART_CODE_BEL") "R_PAC_S_0805_VAL_2k7"))
      (libsource (lib "eagle-import") (part "R_S_0805"))
    )
    (comp (ref "R2205")
      (value "750")
      (footprint "eagle-import:S_0805")
      (fields (field (name "PART_CODE_BEL") "R_PAC_S_0805_VAL_750"))
      (libsource (lib "eagle-import") (part "R_S_0805"))
    )
    (comp (ref "R2206")
      (value "750")
      (footprint "eagle-import:S_0805")
      (fields (field (name "PART_CODE_BEL") "R_PAC_S_0805_VAL_750"))
      (libsource (lib "eagle-import") (part "R_S_0805"))
    )
    (comp (ref "T2201")
      (value "DMG3420U")
      (footprint "eagle-import:S_SOT23")
      (fields (field (name "PART_CODE_BEL") "T_PAC_S_SOT23_VAL_DMG3420U"))
      (libsource (lib "eagle-import") (part "N-MOSFET_S_SOT23"))
    )
    (comp (ref "T2202")
      (value "DMG3420U")
      (footprint "eagle-import:S_SOT23")
      (fields (field (name "PART_CODE_BEL") "T_PAC_S_SOT23_VAL_DMG3420U"))
      (libsource (lib "eagle-import") (part "N-MOSFET_S_SOT23"))
    )
    (comp (ref "T2203")
      (value "DMG3420U")
      (footprint "eagle-import:S_SOT23")
      (fields (field (name "PART_CODE_BEL") "T_PAC_S_SOT23_VAL_DMG3420U"))
      (libsource (lib "eagle-import") (part "N-MOSFET_S_SOT23"))
    )
    (comp (ref "T2204")
      (value "DMG3420U")
      (footprint "eagle-import:S_SOT23")
      (fields (field (name "PART_CODE_BEL") "T_PAC_S_SOT23_VAL_DMG3420U"))
      (libsource (lib "eagle-import") (part "N-MOSFET_S_SOT23"))
    )
    (comp (ref "J1201")
      (value "JUMPER_1X2-T-VERTICAL_GRID_2.54MM")
      (footprint "eagle-import:T_MALE_2X1_VERTICAL_PITCH_2MM54")
      (fields (field (name "FUNCTION") "TEST_2_VREF"))
      (libsource (lib "eagle-import") (part "JUMPER_1X2-T-VERTICAL_GRID_2.54MM"))
    )
    (comp (ref "R1201")
      (value "330")
      (footprint "eagle-import:S_0805")
      (fields (field (name "PART_CODE_BEL") "R_PAC_S_0805_VAL_330"))
      (libsource (lib "eagle-import") (part "R_S_0805"))
    )
    (comp (ref "R1202")
      (value "330")
      (footprint "eagle-import:S_0805")
      (fields (field (name "PART_CODE_BEL") "R_PAC_S_0805_VAL_330"))
      (libsource (lib "eagle-import") (part "R_S_0805"))
    )
    (comp (ref "RN1201")
      (value "10k")
      (footprint "eagle-import:S_1206_4X")
      (fields (field (name "PART_CODE_BEL") "RN_PAC_S_1206_4X_VAL_10k"))
      (libsource (lib "eagle-import") (part "RN_4S_1206"))
    )
    (comp (ref "X1201")
      (value "MALE_2X5-T-VERTICAL_2MM54")
      (footprint "eagle-import:T_MALE_2X5_VERTICAL_PITCH_2MM54")
      (fields (field (name "FUNCTION") "TEST_2"))
      (libsource (lib "eagle-import") (part "MALE_2X5-T-VERTICAL_2MM54"))
    )
    (comp (ref "X1202")
      (value "MALE_2X5-T-VERTICAL_2MM54")
      (footprint "eagle-import:T_MALE_2X5_VERTICAL_PITCH_2MM54")
      (fields (field (name "FUNCTION") "TEST_2_DBG"))
      (libsource (lib "eagle-import") (part "MALE_2X5-T-VERTICAL_2MM54"))
    )
  )
  (nets
    (net (code "1") (name "ACL_OUT") (class "Default")
      (node (ref "IC2001") (pin "10") (pinfunction "O_10") (pintype "output"))
      (node (ref "IC801") (pin "2") (pinfunction "IO_L01P_7/VRN_7_2") (pintype "bidirectional"))
    )
    (net (code "2") (name "ACL_RC") (class "Default")
      (node (ref "C2001") (pin "1") (pinfunction "1_1") (pintype "passive"))
      (node (ref "IC2001") (pin "8") (pinfunction "I0_8") (pintype "input"))
      (node (ref "R2001") (pin "1") (pinfunction "1_1") (pintype "passive"))
      (node (ref "TP2001") (pin "1") (pinfunction "TP_1") (pintype "passive"))
      (node (ref "X1702") (pin "40") (pinfunction "40_40") (pintype "passive"))
    )
    (net (code "3") (name "CLK_MASTER") (class "Default")
      (node (ref "IC1101") (pin "3") (pinfunction "FO_3") (pintype "output"))
      (node (ref "IC801") (pin "181") (pinfunction "IO_L32N_1/GCLK5_181") (pintype "bidirectional"))
      (node (ref "TP1101") (pin "1") (pinfunction "TP_1") (pintype "passive"))
    )
    (net (code "4") (name "CLK_SLOW") (class "Default")
      (node (ref "IC401") (pin "4") (pinfunction "O_4") (pintype "output"))
      (node (ref "IC801") (pin "154") (pinfunction "IO/VREF_2_154") (pintype "bidirectional"))
      (node (ref "R403") (pin "1") (pinfunction "1_1") (pintype "passive"))
      (node (ref "TP401") (pin "1") (pinfunction "TP_1") (pintype "passive"))
      (node (ref "X1701") (pin "16") (pinfunction "16_16") (pintype "passive"))
    )
    (net (code "5") (name "CONF_CCLK") (class "Default")
      (node (ref "IC801") (pin "104") (pinfunction "CCLK_104") (pintype "bidirectional"))
      (node (ref "IC802") (pin "3") (pinfunction "CLK_3") (pintype "input"))
      (node (ref "J801") (pin "13") (pinfunction "13_13") (pintype "passive"))
    )
    (net (code "6") (name "CONF_DIN") (class "Default")
      (node (ref "IC801") (pin "92") (pinfunction "IO_L27N_4/DIN/D0_92") (pintype "bidirectional"))
      (node (ref "IC802") (pin "1") (pinfunction "D0_1") (pintype "output"))
      (node (ref "J801") (pin "11") (pinfunction "11_11") (pintype "passive"))
    )
    (net (code "7") (name "CONF_DONE") (class "Default")
      (node (ref "IC801") (pin "103") (pinfunction "DONE_103") (pintype "bidirectional"))
      (node (ref "IC802") (pin "10") (pinfunction "~{CE}_10") (pintype "input"))
      (node (ref "J801") (pin "17") (pinfunction "17_17") (pintype "passive"))
      (node (ref "R804") (pin "1") (pinfunction "1_1") (pintype "passive"))
    )
    (net (code "8") (name "CONF_DOUT") (class "Default")
      (node (ref "IC801") (pin "81") (pinfunction "IO_L31P_4/DOUT/BUSY_81") (pintype "bidirectional"))
      (node (ref "TP1002") (pin "1") (pinfunction "TP_1") (pintype "passive"))
    )
    (net (code "9") (name "CONF_HSW_EN") (class "Default")
      (node (ref "IC801") (pin "206") (pinfunction "HSWAP_EN_206") (pintype "input"))
      (node (ref "J801") (pin "3") (pinfunction "3_3") (pintype "passive"))
    )
    (net (code "10") (name "CONF_INIT_B") (class "Default")
      (node (ref "IC801") (pin "83") (pinfunction "IO_L31N_4/INIT_B_83") (pintype "bidirectional"))
      (node (ref "IC802") (pin "8") (pinfunction "OE/~{RES}_8") (pintype "bidirectional"))
      (node (ref "J801") (pin "15") (pinfunction "15_15") (pintype "passive"))
      (node (ref "R802") (pin "1") (pinfunction "1_1") (pintype "passive"))
    )
    (net (code "11") (name "CONF_M0") (class "Default")
      (node (ref "IC801") (pin "55") (pinfunction "M0_55") (pintype "input"))
      (node (ref "J801") (pin "5") (pinfunction "5_5") (pintype "passive"))
      (node (ref "R805") (pin "1") (pinfunction "1_1") (pintype "passive"))
    )
    (net (code "12") (name "CONF_M1") (class "Default")
      (node (ref "IC801") (pin "54") (pinfunction "M1_54") (pintype "input"))
      (node (ref "J801") (pin "7") (pinfunction "7_7") (pintype "passive"))
      (node (ref "R806") (pin "1") (pinfunction "1_1") (pintype "passive"))
    )
    (net (code "13") (name "CONF_M2") (class "Default")
      (node (ref "IC801") (pin "56") (pinfunction "M2_56") (pintype "input"))
      (node (ref "J801") (pin "9") (pinfunction "9_9") (pintype "passive"))
      (node (ref "R807") (pin "1") (pinfunction "1_1") (pintype "passive"))
    )
    (net (code "14") (name "CONF_PROG_B") (class "Default")
      (node (ref "IC801") (pin "207") (pinfunction "PROG_B_207") (pintype "input"))
      (node (ref "IC802") (pin "7") (pinfunction "~{CF}_7") (pintype "open_collector"))
      (node (ref "J801") (pin "19") (pinfunction "19_19") (pintype "passive"))
      (node (ref "R803") (pin "1") (pinfunction "1_1") (pintype "passive"))
    )
    (net (code "15") (name "CTRL_IN_START") (class "Default")
      (node (ref "C1802") (pin "1") (pinfunction "1_1") (pintype "passive"))
      (node (ref "IC1801") (pin "8") (pinfunction "I0_8") (pintype "input"))
      (node (ref "IC1801") (pin "9") (pinfunction "I1_9") (pintype "input"))
      (node (ref "R1804") (pin "1") (pinfunction "1_1") (pintype "passive"))
      (node (ref "S1802") (pin "2") (pinfunction "B1_2") (pintype "passive"))
      (node (ref "S1802") (pin "4") (pinfunction "B1_4") (pintype "passive"))
      (node (ref "X1701") (pin "34") (pinfunction "34_34") (pintype "passive"))
    )
    (net (code "16") (name "CTRL_IN_START_N") (class "Default")
      (node (ref "IC1801") (pin "10") (pinfunction "O_10") (pintype "output"))
      (node (ref "IC801") (pin "35") (pinfunction "IO_L24N_6/VREF_6_35") (pintype "bidirectional"))
    )
    (net (code "17") (name "CTRL_IN_STOP") (class "Default")
      (node (ref "C1801") (pin "1") (pinfunction "1_1") (pintype "passive"))
      (node (ref "IC1801") (pin "12") (pinfunction "I0_12") (pintype "input"))
      (node (ref "IC1801") (pin "13") (pinfunction "I1_13") (pintype "input"))
      (node (ref "R1803") (pin "1") (pinfunction "1_1") (pintype "passive"))
      (node (ref "S1801") (pin "2") (pinfunction "B1_2") (pintype "passive"))
      (node (ref "S1801") (pin "4") (pinfunction "B1_4") (pintype "passive"))
      (node (ref "X1701") (pin "36") (pinfunction "36_36") (pintype "passive"))
    )
    (net (code "18") (name "CTRL_IN_STOP_N") (class "Default")
      (node (ref "IC1801") (pin "11") (pinfunction "O_11") (pintype "output"))
      (node (ref "IC801") (pin "34") (pinfunction "IO_L24P_6_34") (pintype "bidirectional"))
    )
    (net (code "19") (name "CTRL_OUT_FAIL") (class "Default")
      (node (ref "IC801") (pin "58") (pinfunction "IO_L01N_5/RDWR_B_58") (pintype "bidirectional"))
      (node (ref "R1802") (pin "1") (pinfunction "1_1") (pintype "passive"))
      (node (ref "X1701") (pin "32") (pinfunction "32_32") (pintype "passive"))
    )
    (net (code "20") (name "CTRL_OUT_PASS") (class "Default")
      (node (ref "IC801") (pin "57") (pinfunction "IO_L01P_5/CS_B_57") (pintype "bidirectional"))
      (node (ref "R1801") (pin "1") (pinfunction "1_1") (pintype "passive"))
      (node (ref "X1701") (pin "30") (pinfunction "30_30") (pintype "passive"))
    )
    (net (code "21") (name "DBG_3") (class "Default")
      (node (ref "IC801") (pin "43") (pinfunction "IO_L21N_6_43") (pintype "bidirectional"))
      (node (ref "X1702") (pin "8") (pinfunction "8_8") (pintype "passive"))
    )
    (net (code "22") (name "DBG_4") (class "Default")
      (node (ref "IC801") (pin "96") (pinfunction "IO/VREF_4_96") (pintype "bidirectional"))
      (node (ref "X1702") (pin "10") (pinfunction "10_10") (pintype "passive"))
    )
    (net (code "23") (name "DBG_5") (class "Default")
      (node (ref "IC801") (pin "40") (pinfunction "IO_L22N_6_40") (pintype "bidirectional"))
      (node (ref "X1702") (pin "12") (pinfunction "12_12") (pintype "passive"))
    )
    (net (code "24") (name "DBG_6") (class "Default")
      (node (ref "IC801") (pin "39") (pinfunction "IO_L22P_6_39") (pintype "bidirectional"))
      (node (ref "X1702") (pin "14") (pinfunction "14_14") (pintype "passive"))
    )
    (net (code "25") (name "DBG_80") (class "Default")
      (node (ref "IC801") (pin "80") (pinfunction "IO_L32N_4/GCLK1_80") (pintype "bidirectional"))
      (node (ref "TP1003") (pin "1") (pinfunction "TP_1") (pintype "passive"))
    )
    (net (code "26") (name "DBG_81") (class "Default")
      (node (ref "IC801") (pin "97") (pinfunction "IO_97") (pintype "bidirectional"))
      (node (ref "TP1001") (pin "1") (pinfunction "TP_1") (pintype "passive"))
    )
    (net (code "27") (name "DCL_OUT") (class "Default")
      (node (ref "IC2001") (pin "4") (pinfunction "O_4") (pintype "output"))
      (node (ref "IC801") (pin "3") (pinfunction "IO_L01N_7/VRP_7_3") (pintype "bidirectional"))
    )
    (net (code "28") (name "DEBUG_0") (class "Default")
      (node (ref "IC801") (pin "61") (pinfunction "IO_L10P_5/VRN_5_61") (pintype "bidirectional"))
      (node (ref "R1701") (pin "1") (pinfunction "1_1") (pintype "passive"))
      (node (ref "X1702") (pin "2") (pinfunction "2_2") (pintype "passive"))
    )
    (net (code "29") (name "DEBUG_1") (class "Default")
      (node (ref "IC801") (pin "33") (pinfunction "IO_L39N_6_33") (pintype "bidirectional"))
      (node (ref "R1703") (pin "1") (pinfunction "1_1") (pintype "passive"))
      (node (ref "X1702") (pin "4") (pinfunction "4_4") (pintype "passive"))
    )
    (net (code "30") (name "DEBUG_2") (class "Default")
      (node (ref "IC801") (pin "44") (pinfunction "IO_L20P_6_44") (pintype "bidirectional"))
      (node (ref "R1705") (pin "1") (pinfunction "1_1") (pintype "passive"))
      (node (ref "X1702") (pin "6") (pinfunction "6_6") (pintype "passive"))
    )
    (net (code "31") (name "DEBUG_3") (class "Default")
      (node (ref "IC801") (pin "37") (pinfunction "IO_L23N_6_37") (pintype "bidirectional"))
      (node (ref "X1702") (pin "16") (pinfunction "16_16") (pintype "passive"))
    )
    (net (code "32") (name "DEBUG_4") (class "Default")
      (node (ref "IC801") (pin "149") (pinfunction "IO_L20N_2_149") (pintype "bidirectional"))
      (node (ref "TP603") (pin "1") (pinfunction "TP_1") (pintype "passive"))
    )
    (net (code "33") (name "DEBUG_5") (class "Default")
      (node (ref "IC801") (pin "150") (pinfunction "IO_L19P_2_150") (pintype "bidirectional"))
      (node (ref "TP602") (pin "1") (pinfunction "TP_1") (pintype "passive"))
    )
    (net (code "34") (name "DEBUG_6") (class "Default")
      (node (ref "IC801") (pin "152") (pinfunction "IO_L19N_2_152") (pintype "bidirectional"))
      (node (ref "TP601") (pin "1") (pinfunction "TP_1") (pintype "passive"))
    )
    (net (code "35") (name "DEBUG_10") (class "Default")
      (node (ref "IC1201") (pin "143") (pinfunction "B2_FB1_MC3(GSR)_143") (pintype "bidirectional"))
      (node (ref "X1702") (pin "32") (pinfunction "32_32") (pintype "passive"))
    )
    (net (code "36") (name "DEBUG_11") (class "Default")
      (node (ref "IC1201") (pin "142") (pinfunction "B2_FB1_MC4_142") (pintype "bidirectional"))
      (node (ref "TP1701") (pin "1") (pinfunction "TP_1") (pintype "passive"))
      (node (ref "X1701") (pin "14") (pinfunction "14_14") (pintype "passive"))
    )
    (net (code "37") (name "DEBUG_12") (class "Default")
      (node (ref "IC1201") (pin "34") (pinfunction "B1_FB7_MC4_34") (pintype "bidirectional"))
      (node (ref "X1702") (pin "28") (pinfunction "28_28") (pintype "passive"))
    )
    (net (code "38") (name "DEBUG_13") (class "Default")
      (node (ref "IC1201") (pin "33") (pinfunction "B1_FB7_MC5_33") (pintype "bidirectional"))
      (node (ref "X1702") (pin "30") (pinfunction "30_30") (pintype "passive"))
    )
    (net (code "39") (name "DEBUG_14") (class "Default")
      (node (ref "IC1201") (pin "38") (pinfunction "B1_FB8_MC2(GCK2)_38") (pintype "bidirectional"))
      (node (ref "IC2001") (pin "1") (pinfunction "I0_1") (pintype "input"))
      (node (ref "X1702") (pin "26") (pinfunction "26_26") (pintype "passive"))
    )
    (net (code "40") (name "DEBUG_15") (class "Default")
      (node (ref "IC1201") (pin "39") (pinfunction "B1_FB8_MC5(DGE)_39") (pintype "bidirectional"))
      (node (ref "IC2001") (pin "2") (pinfunction "I1_2") (pintype "input"))
      (node (ref "R1708") (pin "1") (pinfunction "1_1") (pintype "passive"))
      (node (ref "X1702") (pin "24") (pinfunction "24_24") (pintype "passive"))
    )
    (net (code "41") (name "DEBUG_16") (class "Default")
      (node (ref "IC1201") (pin "40") (pinfunction "B1_FB8_MC13_40") (pintype "bidirectional"))
      (node (ref "IC2001") (pin "6") (pinfunction "I1_6") (pintype "input"))
      (node (ref "R1706") (pin "1") (pinfunction "1_1") (pintype "passive"))
      (node (ref "X1702") (pin "22") (pinfunction "22_22") (pintype "passive"))
    )
    (net (code "42") (name "DEBUG_17") (class "Default")
      (node (ref "IC1201") (pin "41") (pinfunction "B1_FB8_MC14_41") (pintype "bidirectional"))
      (node (ref "IC2001") (pin "9") (pinfunction "I1_9") (pintype "input"))
      (node (ref "R1704") (pin "1") (pinfunction "1_1") (pintype "passive"))
      (node (ref "X1702") (pin "20") (pinfunction "20_20") (pintype "passive"))
    )
    (net (code "43") (name "DEBUG_18") (class "Default")
      (node (ref "IC1201") (pin "42") (pinfunction "B1_FB8_MC15_42") (pintype "bidirectional"))
      (node (ref "IC2001") (pin "12") (pinfunction "I0_12") (pintype "input"))
      (node (ref "IC2001") (pin "13") (pinfunction "I1_13") (pintype "input"))
      (node (ref "R1702") (pin "1") (pinfunction "1_1") (pintype "passive"))
      (node (ref "X1702") (pin "18") (pinfunction "18_18") (pintype "passive"))
    )
    (net (code "44") (name "DISP_1_SEG_A") (class "Default")
      (node (ref "IC1201") (pin "7") (pinfunction "B2_FB2_MC16_7") (pintype "bidirectional"))
      (node (ref "RN1901") (pin "1") (pinfunction "1_1") (pintype "passive"))
    )
    (net (code "45") (name "DISP_1_SEG_B") (class "Default")
      (node (ref "IC1201") (pin "6") (pinfunction "B2_FB2_MC15(GTS1)_6") (pintype "bidirectional"))
      (node (ref "RN1901") (pin "3") (pinfunction "1_3") (pintype "passive"))
    )
    (net (code "46") (name "DISP_1_SEG_C") (class "Default")
      (node (ref "IC1201") (pin "4") (pinfunction "B2_FB2_MC4_4") (pintype "bidirectional"))
      (node (ref "RN1901") (pin "5") (pinfunction "1_5") (pintype "passive"))
    )
    (net (code "47") (name "DISP_1_SEG_D") (class "Default")
      (node (ref "IC1201") (pin "2") (pinfunction "B2_FB2_MC1(GTS2)_2") (pintype "bidirectional"))
      (node (ref "RN1901") (pin "7") (pinfunction "1_7") (pintype "passive"))
    )
    (net (code "48") (name "DISP_1_SEG_E") (class "Default")
      (node (ref "IC1201") (pin "3") (pinfunction "B2_FB2_MC3(GTS3)_3") (pintype "bidirectional"))
      (node (ref "RN1902") (pin "1") (pinfunction "1_1") (pintype "passive"))
    )
    (net (code "49") (name "DISP_1_SEG_F") (class "Default")
      (node (ref "IC1201") (pin "5") (pinfunction "B2_FB2_MC5(GTS0)_5") (pintype "bidirectional"))
      (node (ref "RN1902") (pin "3") (pinfunction "1_3") (pintype "passive"))
    )
    (net (code "50") (name "DISP_1_SEG_G") (class "Default")
      (node (ref "IC1201") (pin "23") (pinfunction "B1_FB11_MC2_23") (pintype "bidirectional"))
      (node (ref "RN1902") (pin "5") (pinfunction "1_5") (pintype "passive"))
    )
    (net (code "51") (name "DISP_1_SEG_H") (class "Default")
      (node (ref "IC1201") (pin "25") (pinfunction "B1_FB9_MC16_25") (pintype "bidirectional"))
      (node (ref "RN1902") (pin "7") (pinfunction "1_7") (pintype "passive"))
    )
    (net (code "52") (name "DISP_2_SEG_A") (class "Default")
      (node (ref "IC1201") (pin "26") (pinfunction "B1_FB9_MC15_26") (pintype "bidirectional"))
      (node (ref "RN1903") (pin "2") (pinfunction "2_2") (pintype "passive"))
    )
    (net (code "53") (name "DISP_2_SEG_B") (class "Default")
      (node (ref "IC1201") (pin "28") (pinfunction "B1_FB9_MC2_28") (pintype "bidirectional"))
      (node (ref "RN1903") (pin "4") (pinfunction "2_4") (pintype "passive"))
    )
    (net (code "54") (name "DISP_2_SEG_C") (class "Default")
      (node (ref "IC1201") (pin "24") (pinfunction "B1_FB11_MC1_24") (pintype "bidirectional"))
      (node (ref "RN1903") (pin "6") (pinfunction "2_6") (pintype "passive"))
    )
    (net (code "55") (name "DISP_2_SEG_D") (class "Default")
      (node (ref "IC1201") (pin "50") (pinfunction "B1_FB10_MC16_50") (pintype "bidirectional"))
      (node (ref "RN1903") (pin "8") (pinfunction "2_8") (pintype "passive"))
    )
    (net (code "56") (name "DISP_2_SEG_E") (class "Default")
      (node (ref "IC1201") (pin "49") (pinfunction "B1_FB10_MC15_49") (pintype "bidirectional"))
      (node (ref "RN1904") (pin "2") (pinfunction "2_2") (pintype "passive"))
    )
    (net (code "57") (name "DISP_2_SEG_F") (class "Default")
      (node (ref "IC1201") (pin "44") (pinfunction "B1_FB10_MC1_44") (pintype "bidirectional"))
      (node (ref "RN1904") (pin "4") (pinfunction "2_4") (pintype "passive"))
    )
    (net (code "58") (name "DISP_2_SEG_G") (class "Default")
      (node (ref "IC1201") (pin "46") (pinfunction "B1_FB10_MC4_46") (pintype "bidirectional"))
      (node (ref "RN1904") (pin "6") (pinfunction "2_6") (pintype "passive"))
    )
    (net (code "59") (name "DISP_2_SEG_H") (class "Default")
      (node (ref "IC1201") (pin "48") (pinfunction "B1_FB10_MC14_48") (pintype "bidirectional"))
      (node (ref "RN1904") (pin "7") (pinfunction "1_7") (pintype "passive"))
    )
    (net (code "60") (name "GND") (class "Default")
      (node (ref "C101") (pin "-") (pinfunction "-_-") (pintype "passive"))
      (node (ref "C1101") (pin "2") (pinfunction "2_2") (pintype "passive"))
      (node (ref "C1102") (pin "2") (pinfunction "2_2") (pintype "passive"))
      (node (ref "C1103") (pin "2") (pinfunction "2_2") (pintype "passive"))
      (node (ref "C1104") (pin "2") (pinfunction "2_2") (pintype "passive"))
      (node (ref "C1105") (pin "2") (pinfunction "2_2") (pintype "passive"))
      (node (ref "C1106") (pin "2") (pinfunction "2_2") (pintype "passive"))
      (node (ref "C1107") (pin "2") (pinfunction "2_2") (pintype "passive"))
      (node (ref "C1108") (pin "2") (pinfunction "2_2") (pintype "passive"))
      (node (ref "C1109") (pin "2") (pinfunction "2_2") (pintype "passive"))
      (node (ref "C1110") (pin "2") (pinfunction "2_2") (pintype "passive"))
      (node (ref "C1111") (pin "2") (pinfunction "2_2") (pintype "passive"))
      (node (ref "C1112") (pin "2") (pinfunction "2_2") (pintype "passive"))
      (node (ref "C1113") (pin "2") (pinfunction "2_2") (pintype "passive"))
      (node (ref "C1114") (pin "2") (pinfunction "2_2") (pintype "passive"))
      (node (ref "C1115") (pin "2") (pinfunction "2_2") (pintype "passive"))
      (node (ref "C1116") (pin "2") (pinfunction "2_2") (pintype "passive"))
      (node (ref "C1117") (pin "2") (pinfunction "2_2") (pintype "passive"))
      (node (ref "C1118") (pin "2") (pinfunction "2_2") (pintype "passive"))
      (node (ref "C1119") (pin "2") (pinfunction "2_2") (pintype "passive"))
      (node (ref "C1120") (pin "2") (pinfunction "2_2") (pintype "passive"))
      (node (ref "C1301") (pin "2") (pinfunction "2_2") (pintype "passive"))
      (node (ref "C1302") (pin "2") (pinfunction "2_2") (pintype "passive"))
      (node (ref "C1401") (pin "1") (pinfunction "1_1") (pintype "passive"))
      (node (ref "C1601") (pin "2") (pinfunction "2_2") (pintype "passive"))
      (node (ref "C1602") (pin "2") (pinfunction "2_2") (pintype "passive"))
      (node (ref "C1603") (pin "2") (pinfunction "2_2") (pintype "passive"))
      (node (ref "C1604") (pin "2") (pinfunction "2_2") (pintype "passive"))
      (node (ref "C1605") (pin "2") (pinfunction "2_2") (pintype "passive"))
      (node (ref "C1606") (pin "2") (pinfunction "2_2") (pintype "passive"))
      (node (ref "C1607") (pin "2") (pinfunction "2_2") (pintype "passive"))
      (node (ref "C1608") (pin "2") (pinfunction "2_2") (pintype "passive"))
      (node (ref "C1609") (pin "2") (pinfunction "2_2") (pintype "passive"))
      (node (ref "C1610") (pin "2") (pinfunction "2_2") (pintype "passive"))
      (node (ref "C1611") (pin "2") (pinfunction "2_2") (pintype "passive"))
      (node (ref "C1803") (pin "2") (pinfunction "2_2") (pintype "passive"))
      (node (ref "C2001") (pin "2") (pinfunction "2_2") (pintype "passive"))
      (node (ref "C2002") (pin "2") (pinfunction "2_2") (pintype "passive"))
      (node (ref "C201") (pin "2") (pinfunction "2_2") (pintype "passive"))
      (node (ref "C202") (pin "2") (pinfunction "2_2") (pintype "passive"))
      (node (ref "C203") (pin "2") (pinfunction "2_2") (pintype "passive"))
      (node (ref "C204") (pin "2") (pinfunction "2_2") (pintype "passive"))
      (node (ref "C205") (pin "2") (pinfunction "2_2") (pintype "passive"))
      (node (ref "C206") (pin "2") (pinfunction "2_2") (pintype "passive"))
      (node (ref "C207") (pin "2") (pinfunction "2_2") (pintype "passive"))
      (node (ref "C208") (pin "2") (pinfunction "2_2") (pintype "passive"))
      (node (ref "C209") (pin "2") (pinfunction "2_2") (pintype "passive"))
      (node (ref "C210") (pin "2") (pinfunction "2_2") (pintype "passive"))
      (node (ref "C301") (pin "2") (pinfunction "2_2") (pintype "passive"))
      (node (ref "C302") (pin "2") (pinfunction "2_2") (pintype "passive"))
      (node (ref "C303") (pin "2") (pinfunction "2_2") (pintype "passive"))
      (node (ref "C304") (pin "2") (pinfunction "2_2") (pintype "passive"))
      (node (ref "C401") (pin "2") (pinfunction "2_2") (pintype "passive"))
      (node (ref "C402") (pin "-") (pinfunction "-_-") (pintype "passive"))
      (node (ref "C403") (pin "2") (pinfunction "2_2") (pintype "passive"))
      (node (ref "C601") (pin "2") (pinfunction "2_2") (pintype "passive"))
      (node (ref "C602") (pin "2") (pinfunction "2_2") (pintype "passive"))
      (node (ref "C603") (pin "2") (pinfunction "2_2") (pintype "passive"))
      (node (ref "C701") (pin "2") (pinfunction "2_2") (pintype "passive"))
      (node (ref "C702") (pin "2") (pinfunction "2_2") (pintype "passive"))
      (node (ref "C801") (pin "2") (pinfunction "2_2") (pintype "passive"))
      (node (ref "C802") (pin "2") (pinfunction "2_2") (pintype "passive"))
      (node (ref "C803") (pin "2") (pinfunction "2_2") (pintype "passive"))
      (node (ref "C804") (pin "2") (pinfunction "2_2") (pintype "passive"))
      (node (ref "C805") (pin "2") (pinfunction "2_2") (pintype "passive"))
      (node (ref "C806") (pin "2") (pinfunction "2_2") (pintype "passive"))
      (node (ref "C807") (pin "2") (pinfunction "2_2") (pintype "passive"))
      (node (ref "C808") (pin "2") (pinfunction "2_2") (pintype "passive"))
      (node (ref "C809") (pin "2") (pinfunction "2_2") (pintype "passive"))
      (node (ref "C810") (pin "2") (pinfunction "2_2") (pintype "passive"))
      (node (ref "C811") (pin "2") (pinfunction "2_2") (pintype "passive"))
      (node (ref "D1401") (pin "1") (pinfunction "A2_1") (pintype "passive"))
      (node (ref "D1402") (pin "1") (pinfunction "A2_1") (pintype "passive"))
      (node (ref "H1801") (pin "H1") (pinfunction "MOUNT_H1") (pintype "passive"))
      (node (ref "H1802") (pin "H1") (pinfunction "MOUNT_H1") (pintype "passive"))
      (node (ref "H1803") (pin "H1") (pinfunction "MOUNT_H1") (pintype "passive"))
      (node (ref "H1804") (pin "H1") (pinfunction "MOUNT_H1") (pintype "passive"))
      (node (ref "IC1101") (pin "2") (pinfunction "GND_2") (pintype "power_in"))
      (node (ref "IC1201") (pin "108") (pinfunction "GND_108") (pintype "power_in"))
      (node (ref "IC1201") (pin "123") (pinfunction "GND_123") (pintype "power_in"))
      (node (ref "IC1201") (pin "144") (pinfunction "GND_144") (pintype "power_in"))
      (node (ref "IC1201") (pin "29") (pinfunction "GND_29") (pintype "power_in"))
      (node (ref "IC1201") (pin "36") (pinfunction "GND_36") (pintype "power_in"))
      (node (ref "IC1201") (pin "47") (pinfunction "GND_47") (pintype "power_in"))
      (node (ref "IC1201") (pin "62") (pinfunction "GND_62") (pintype "power_in"))
      (node (ref "IC1201") (pin "72") (pinfunction "GND_72") (pintype "power_in"))
      (node (ref "IC1201") (pin "89") (pinfunction "GND_89") (pintype "power_in"))
      (node (ref "IC1201") (pin "90") (pinfunction "GND_90") (pintype "power_in"))
      (node (ref "IC1201") (pin "99") (pinfunction "GND_99") (pintype "power_in"))
      (node (ref "IC1301") (pin "2") (pinfunction "GND_2") (pintype "power_in"))
      (node (ref "IC1301") (pin "5") (pinfunction "A1_5") (pintype "input"))
      (node (ref "IC1301") (pin "6") (pinfunction "A0_6") (pintype "input"))
      (node (ref "IC1302") (pin "2") (pinfunction "GND_2") (pintype "power_in"))
      (node (ref "IC1302") (pin "5") (pinfunction "A1_5") (pintype "input"))
      (node (ref "IC1401") (pin "5") (pinfunction "V-_5") (pintype "power_in"))
      (node (ref "IC1801") (pin "7") (pinfunction "GND_7") (pintype "power_in"))
      (node (ref "IC2001") (pin "7") (pinfunction "GND_7") (pintype "power_in"))
      (node (ref "IC201") (pin "1") (pinfunction "AJD_1") (pintype "passive"))
      (node (ref "IC401") (pin "7") (pinfunction "GND_7") (pintype "power_in"))
      (node (ref "IC601") (pin "16") (pinfunction "GND_16") (pintype "power_in"))
      (node (ref "IC602") (pin "16") (pinfunction "GND_16") (pintype "power_in"))
      (node (ref "IC603") (pin "16") (pinfunction "GND_16") (pintype "power_in"))
      (node (ref "IC701") (pin "16") (pinfunction "GND_16") (pintype "power_in"))
      (node (ref "IC702") (pin "1") (pinfunction "A0_1") (pintype "input"))
      (node (ref "IC702") (pin "2") (pinfunction "A1_2") (pintype "input"))
      (node (ref "IC702") (pin "3") (pinfunction "A2_3") (pintype "input"))
      (node (ref "IC702") (pin "4") (pinfunction "GND_4") (pintype "power_in"))
      (node (ref "IC702") (pin "7") (pinfunction "WP_7") (pintype "input"))
      (node (ref "IC801") (pin "1") (pinfunction "GND_1") (pintype "power_in"))
      (node (ref "IC801") (pin "105") (pinfunction "GND_105") (pintype "power_in"))
      (node (ref "IC801") (pin "112") (pinfunction "GND_112") (pintype "power_in"))
      (node (ref "IC801") (pin "118") (pinfunction "GND_118") (pintype "power_in"))
      (node (ref "IC801") (pin "129") (pinfunction "GND_129") (pintype "power_in"))
      (node (ref "IC801") (pin "134") (pinfunction "GND_134") (pintype "power_in"))
      (node (ref "IC801") (pin "14") (pinfunction "GND_14") (pintype "power_in"))
      (node (ref "IC801") (pin "145") (pinfunction "GND_145") (pintype "power_in"))
      (node (ref "IC801") (pin "151") (pinfunction "GND_151") (pintype "power_in"))
      (node (ref "IC801") (pin "157") (pinfunction "GND_157") (pintype "power_in"))
      (node (ref "IC801") (pin "163") (pinfunction "GND_163") (pintype "power_in"))
      (node (ref "IC801") (pin "170") (pinfunction "GND_170") (pintype "power_in"))
      (node (ref "IC801") (pin "179") (pinfunction "GND_179") (pintype "power_in"))
      (node (ref "IC801") (pin "186") (pinfunction "GND_186") (pintype "power_in"))
      (node (ref "IC801") (pin "195") (pinfunction "GND_195") (pintype "power_in"))
      (node (ref "IC801") (pin "202") (pinfunction "GND_202") (pintype "power_in"))
      (node (ref "IC801") (pin "25") (pinfunction "GND_25") (pintype "power_in"))
      (node (ref "IC801") (pin "30") (pinfunction "GND_30") (pintype "power_in"))
      (node (ref "IC801") (pin "41") (pinfunction "GND_41") (pintype "power_in"))
      (node (ref "IC801") (pin "47") (pinfunction "GND_47") (pintype "power_in"))
      (node (ref "IC801") (pin "53") (pinfunction "GND_53") (pintype "power_in"))
      (node (ref "IC801") (pin "59") (pinfunction "GND_59") (pintype "power_in"))
      (node (ref "IC801") (pin "66") (pinfunction "GND_66") (pintype "power_in"))
      (node (ref "IC801") (pin "75") (pinfunction "GND_75") (pintype "power_in"))
      (node (ref "IC801") (pin "8") (pinfunction "GND_8") (pintype "power_in"))
      (node (ref "IC801") (pin "82") (pinfunction "GND_82") (pintype "power_in"))
      (node (ref "IC801") (pin "91") (pinfunction "GND_91") (pintype "power_in"))
      (node (ref "IC801") (pin "99") (pinfunction "GND_99") (pintype "power_in"))
      (node (ref "IC802") (pin "11") (pinfunction "GND_11") (pintype "power_in"))
      (node (ref "J1902") (pin "1") (pinfunction "1_1") (pintype "passive"))
      (node (ref "J1904") (pin "2") (pinfunction "2_2") (pintype "passive"))
      (node (ref "J801") (pin "14") (pinfunction "14_14") (pintype "passive"))
      (node (ref "J801") (pin "16") (pinfunction "16_16") (pintype "passive"))
      (node (ref "J801") (pin "18") (pinfunction "18_18") (pintype "passive"))
      (node (ref "J801") (pin "20") (pinfunction "20_20") (pintype "passive"))
      (node (ref "LED1801") (pin "C") (pinfunction "C_C") (pintype "passive"))
      (node (ref "LED1802") (pin "C") (pinfunction "C_C") (pintype "passive"))
      (node (ref "LED201") (pin "C") (pinfunction "C_C") (pintype "passive"))
      (node (ref "LED2401") (pin "C") (pinfunction "C_C") (pintype "passive"))
      (node (ref "LED2402") (pin "C") (pinfunction "C_C") (pintype "passive"))
      (node (ref "LED2404") (pin "C") (pinfunction "C_C") (pintype "passive"))
      (node (ref "LED2501") (pin "C") (pinfunction "C_C") (pintype "passive"))
      (node (ref "LED2502") (pin "C") (pinfunction "C_C") (pintype "passive"))
      (node (ref "LED2503") (pin "C") (pinfunction "C_C") (pintype "passive"))
      (node (ref "R1201") (pin "1") (pinfunction "1_1") (pintype "passive"))
      (node (ref "R1202") (pin "1") (pinfunction "1_1") (pintype "passive"))
      (node (ref "R1402") (pin "1") (pinfunction "1_1") (pintype "passive"))
      (node (ref "R1404") (pin "1") (pinfunction "1_1") (pintype "passive"))
      (node (ref "R1803") (pin "2") (pinfunction "2_2") (pintype "passive"))
      (node (ref "R1804") (pin "2") (pinfunction "2_2") (pintype "passive"))
      (node (ref "R201") (pin "1") (pinfunction "1_1") (pintype "passive"))
      (node (ref "R202") (pin "1") (pinfunction "1_1") (pintype "passive"))
      (node (ref "R204") (pin "1") (pinfunction "1_1") (pintype "passive"))
      (node (ref "R207") (pin "1") (pinfunction "1_1") (pintype "passive"))
      (node (ref "R208") (pin "1") (pinfunction "1_1") (pintype "passive"))
      (node (ref "R2401") (pin "2") (pinfunction "2_2") (pintype "passive"))
      (node (ref "R2402") (pin "2") (pinfunction "2_2") (pintype "passive"))
      (node (ref "R2403") (pin "2") (pinfunction "2_2") (pintype "passive"))
      (node (ref "R2405") (pin "2") (pinfunction "2_2") (pintype "passive"))
      (node (ref "R2501") (pin "2") (pinfunction "2_2") (pintype "passive"))
      (node (ref "R2502") (pin "2") (pinfunction "2_2") (pintype "passive"))
      (node (ref "R2503") (pin "2") (pinfunction "2_2") (pintype "passive"))
      (node (ref "R2505") (pin "2") (pinfunction "2_2") (pintype "passive"))
      (node (ref "R302") (pin "1") (pinfunction "1_1") (pintype "passive"))
      (node (ref "R308") (pin "1") (pinfunction "1_1") (pintype "passive"))
      (node (ref "R404") (pin "1") (pinfunction "1_1") (pintype "passive"))
      (node (ref "R501") (pin "1") (pinfunction "1_1") (pintype "passive"))
      (node (ref "R502") (pin "1") (pinfunction "1_1") (pintype "passive"))
      (node (ref "R805") (pin "2") (pinfunction "2_2") (pintype "passive"))
      (node (ref "R806") (pin "2") (pinfunction "2_2") (pintype "passive"))
      (node (ref "R807") (pin "2") (pinfunction "2_2") (pintype "passive"))
      (node (ref "RN1801") (pin "1") (pinfunction "1_1") (pintype "passive"))
      (node (ref "RN1801") (pin "3") (pinfunction "1_3") (pintype "passive"))
      (node (ref "RN1801") (pin "5") (pinfunction "1_5") (pintype "passive"))
      (node (ref "RN1801") (pin "7") (pinfunction "1_7") (pintype "passive"))
      (node (ref "S401") (pin "2") (pinfunction "B1_2") (pintype "passive"))
      (node (ref "S401") (pin "4") (pinfunction "B1_4") (pintype "passive"))
      (node (ref "T1901") (pin "2") (pinfunction "S_2") (pintype "passive"))
      (node (ref "T1902") (pin "2") (pinfunction "S_2") (pintype "passive"))
      (node (ref "T2101") (pin "2") (pinfunction "S_2") (pintype "passive"))
      (node (ref "T2102") (pin "2") (pinfunction "S_2") (pintype "passive"))
      (node (ref "T2103") (pin "2") (pinfunction "S_2") (pintype "passive"))
      (node (ref "T2104") (pin "2") (pinfunction "S_2") (pintype "passive"))
      (node (ref "T2105") (pin "2") (pinfunction "S_2") (pintype "passive"))
      (node (ref "T2106") (pin "2") (pinfunction "S_2") (pintype "passive"))
      (node (ref "T2107") (pin "2") (pinfunction "S_2") (pintype "passive"))
      (node (ref "T2108") (pin "2") (pinfunction "S_2") (pintype "passive"))
      (node (ref "T2109") (pin "2") (pinfunction "S_2") (pintype "passive"))
      (node (ref "T2110") (pin "2") (pinfunction "S_2") (pintype "passive"))
      (node (ref "T2201") (pin "2") (pinfunction "S_2") (pintype "passive"))
      (node (ref "T2202") (pin "2") (pinfunction "S_2") (pintype "passive"))
      (node (ref "T2203") (pin "2") (pinfunction "S_2") (pintype "passive"))
      (node (ref "T2204") (pin "2") (pinfunction "S_2") (pintype "passive"))
      (node (ref "T2301") (pin "2") (pinfunction "S_2") (pintype "passive"))
      (node (ref "T2302") (pin "2") (pinfunction "S_2") (pintype "passive"))
      (node (ref "T2303") (pin "2") (pinfunction "S_2") (pintype "passive"))
      (node (ref "T2304") (pin "2") (pinfunction "S_2") (pintype "passive"))
      (node (ref "T2305") (pin "2") (pinfunction "S_2") (pintype "passive"))
      (node (ref "T2306") (pin "2") (pinfunction "S_2") (pintype "passive"))
      (node (ref "T2307") (pin "2") (pinfunction "S_2") (pintype "passive"))
      (node (ref "T2308") (pin "2") (pinfunction "S_2") (pintype "passive"))
      (node (ref "T2407") (pin "2") (pinfunction "S_2") (pintype "passive"))
      (node (ref "T2408") (pin "2") (pinfunction "S_2") (pintype "passive"))
      (node (ref "T2507") (pin "2") (pinfunction "S_2") (pintype "passive"))
      (node (ref "T2508") (pin "2") (pinfunction "S_2") (pintype "passive"))
      (node (ref "T301") (pin "2") (pinfunction "S_2") (pintype "passive"))
      (node (ref "T302") (pin "2") (pinfunction "S_2") (pintype "passive"))
      (node (ref "T303") (pin "2") (pinfunction "S_2") (pintype "passive"))
      (node (ref "T304") (pin "2") (pinfunction "S_2") (pintype "passive"))
      (node (ref "T305") (pin "2") (pinfunction "S_2") (pintype "passive"))
      (node (ref "T306") (pin "2") (pinfunction "S_2") (pintype "passive"))
      (node (ref "T401") (pin "2") (pinfunction "S_2") (pintype "passive"))
      (node (ref "X101") (pin "1") (pinfunction "1_1") (pintype "passive"))
      (node (ref "X102") (pin "1") (pinfunction "1_1") (pintype "passive"))
      (node (ref "X102") (pin "3") (pinfunction "3_3") (pintype "passive"))
      (node (ref "X102") (pin "5") (pinfunction "5_5") (pintype "passive"))
      (node (ref "X102") (pin "7") (pinfunction "7_7") (pintype "passive"))
      (node (ref "X102") (pin "9") (pinfunction "9_9") (pintype "passive"))
      (node (ref "X103") (pin "1") (pinfunction "1_1") (pintype "passive"))
      (node (ref "X103") (pin "2") (pinfunction "2_2") (pintype "passive"))
      (node (ref "X103") (pin "3") (pinfunction "3_3") (pintype "passive"))
      (node (ref "X104") (pin "10") (pinfunction "10_10") (pintype "passive"))
      (node (ref "X104") (pin "12") (pinfunction "12_12") (pintype "passive"))
      (node (ref "X104") (pin "14") (pinfunction "14_14") (pintype "passive"))
      (node (ref "X104") (pin "16") (pinfunction "16_16") (pintype "passive"))
      (node (ref "X104") (pin "18") (pinfunction "18_18") (pintype "passive"))
      (node (ref "X104") (pin "2") (pinfunction "2_2") (pintype "passive"))
      (node (ref "X104") (pin "20") (pinfunction "20_20") (pintype "passive"))
      (node (ref "X104") (pin "22") (pinfunction "22_22") (pintype "passive"))
      (node (ref "X104") (pin "24") (pinfunction "24_24") (pintype "passive"))
      (node (ref "X104") (pin "26") (pinfunction "26_26") (pintype "passive"))
      (node (ref "X104") (pin "4") (pinfunction "4_4") (pintype "passive"))
      (node (ref "X104") (pin "6") (pinfunction "6_6") (pintype "passive"))
      (node (ref "X104") (pin "8") (pinfunction "8_8") (pintype "passive"))
      (node (ref "X105") (pin "1") (pinfunction "1_1") (pintype "passive"))
      (node (ref "X105") (pin "2") (pinfunction "2_2") (pintype "passive"))
      (node (ref "X105") (pin "3") (pinfunction "3_3") (pintype "passive"))
      (node (ref "X106") (pin "10") (pinfunction "10_10") (pintype "passive"))
      (node (ref "X106") (pin "12") (pinfunction "12_12") (pintype "passive"))
      (node (ref "X106") (pin "14") (pinfunction "14_14") (pintype "passive"))
      (node (ref "X106") (pin "16") (pinfunction "16_16") (pintype "passive"))
      (node (ref "X106") (pin "18") (pinfunction "18_18") (pintype "passive"))
      (node (ref "X106") (pin "2") (pinfunction "2_2") (pintype "passive"))
      (node (ref "X106") (pin "20") (pinfunction "20_20") (pintype "passive"))
      (node (ref "X106") (pin "22") (pinfunction "22_22") (pintype "passive"))
      (node (ref "X106") (pin "24") (pinfunction "24_24") (pintype "passive"))
      (node (ref "X106") (pin "26") (pinfunction "26_26") (pintype "passive"))
      (node (ref "X106") (pin "4") (pinfunction "4_4") (pintype "passive"))
      (node (ref "X106") (pin "6") (pinfunction "6_6") (pintype "passive"))
      (node (ref "X106") (pin "8") (pinfunction "8_8") (pintype "passive"))
      (node (ref "X107") (pin "1") (pinfunction "1_1") (pintype "passive"))
      (node (ref "X107") (pin "2") (pinfunction "2_2") (pintype "passive"))
      (node (ref "X107") (pin "3") (pinfunction "3_3") (pintype "passive"))
      (node (ref "X1201") (pin "2") (pinfunction "2_2") (pintype "passive"))
      (node (ref "X1201") (pin "4") (pinfunction "4_4") (pintype "passive"))
      (node (ref "X1201") (pin "6") (pinfunction "6_6") (pintype "passive"))
      (node (ref "X1201") (pin "8") (pinfunction "8_8") (pintype "passive"))
      (node (ref "X1202") (pin "2") (pinfunction "2_2") (pintype "passive"))
      (node (ref "X1202") (pin "4") (pinfunction "4_4") (pintype "passive"))
      (node (ref "X1202") (pin "6") (pinfunction "6_6") (pintype "passive"))
      (node (ref "X1202") (pin "8") (pinfunction "8_8") (pintype "passive"))
      (node (ref "X1701") (pin "1") (pinfunction "1_1") (pintype "passive"))
      (node (ref "X1701") (pin "11") (pinfunction "11_11") (pintype "passive"))
      (node (ref "X1701") (pin "13") (pinfunction "13_13") (pintype "passive"))
      (node (ref "X1701") (pin "15") (pinfunction "15_15") (pintype "passive"))
      (node (ref "X1701") (pin "17") (pinfunction "17_17") (pintype "passive"))
      (node (ref "X1701") (pin "19") (pinfunction "19_19") (pintype "passive"))
      (node (ref "X1701") (pin "21") (pinfunction "21_21") (pintype "passive"))
      (node (ref "X1701") (pin "23") (pinfunction "23_23") (pintype "passive"))
      (node (ref "X1701") (pin "25") (pinfunction "25_25") (pintype "passive"))
      (node (ref "X1701") (pin "27") (pinfunction "27_27") (pintype "passive"))
      (node (ref "X1701") (pin "29") (pinfunction "29_29") (pintype "passive"))
      (node (ref "X1701") (pin "3") (pinfunction "3_3") (pintype "passive"))
      (node (ref "X1701") (pin "31") (pinfunction "31_31") (pintype "passive"))
      (node (ref "X1701") (pin "33") (pinfunction "33_33") (pintype "passive"))
      (node (ref "X1701") (pin "35") (pinfunction "35_35") (pintype "passive"))
      (node (ref "X1701") (pin "37") (pinfunction "37_37") (pintype "passive"))
      (node (ref "X1701") (pin "39") (pinfunction "39_39") (pintype "passive"))
      (node (ref "X1701") (pin "5") (pinfunction "5_5") (pintype "passive"))
      (node (ref "X1701") (pin "7") (pinfunction "7_7") (pintype "passive"))
      (node (ref "X1701") (pin "9") (pinfunction "9_9") (pintype "passive"))
      (node (ref "X1702") (pin "1") (pinfunction "1_1") (pintype "passive"))
      (node (ref "X1702") (pin "11") (pinfunction "11_11") (pintype "passive"))
      (node (ref "X1702") (pin "13") (pinfunction "13_13") (pintype "passive"))
      (node (ref "X1702") (pin "15") (pinfunction "15_15") (pintype "passive"))
      (node (ref "X1702") (pin "17") (pinfunction "17_17") (pintype "passive"))
      (node (ref "X1702") (pin "19") (pinfunction "19_19") (pintype "passive"))
      (node (ref "X1702") (pin "21") (pinfunction "21_21") (pintype "passive"))
      (node (ref "X1702") (pin "23") (pinfunction "23_23") (pintype "passive"))
      (node (ref "X1702") (pin "25") (pinfunction "25_25") (pintype "passive"))
      (node (ref "X1702") (pin "27") (pinfunction "27_27") (pintype "passive"))
      (node (ref "X1702") (pin "29") (pinfunction "29_29") (pintype "passive"))
      (node (ref "X1702") (pin "3") (pinfunction "3_3") (pintype "passive"))
      (node (ref "X1702") (pin "31") (pinfunction "31_31") (pintype "passive"))
      (node (ref "X1702") (pin "33") (pinfunction "33_33") (pintype "passive"))
      (node (ref "X1702") (pin "35") (pinfunction "35_35") (pintype "passive"))
      (node (ref "X1702") (pin "37") (pinfunction "37_37") (pintype "passive"))
      (node (ref "X1702") (pin "39") (pinfunction "39_39") (pintype "passive"))
      (node (ref "X1702") (pin "5") (pinfunction "5_5") (pintype "passive"))
      (node (ref "X1702") (pin "7") (pinfunction "7_7") (pintype "passive"))
      (node (ref "X1702") (pin "9") (pinfunction "9_9") (pintype "passive"))
      (node (ref "X301") (pin "1") (pinfunction "1_1") (pintype "passive"))
      (node (ref "X301") (pin "2") (pinfunction "2_2") (pintype "passive"))
      (node (ref "X301") (pin "3") (pinfunction "3_3") (pintype "passive"))
      (node (ref "X501") (pin "2") (pinfunction "2_2") (pintype "passive"))
      (node (ref "X501") (pin "4") (pinfunction "4_4") (pintype "passive"))
      (node (ref "X501") (pin "6") (pinfunction "6_6") (pintype "passive"))
      (node (ref "X501") (pin "8") (pinfunction "8_8") (pintype "passive"))
      (node (ref "X502") (pin "2") (pinfunction "2_2") (pintype "passive"))
      (node (ref "X502") (pin "4") (pinfunction "4_4") (pintype "passive"))
      (node (ref "X502") (pin "6") (pinfunction "6_6") (pintype "passive"))
      (node (ref "X502") (pin "8") (pinfunction "8_8") (pintype "passive"))
    )
    (net (code "61") (name "I2C_SCL") (class "Default")
      (node (ref "IC1201") (pin "32") (pinfunction "B1_FB7_MC12(GCK1)_32") (pintype "bidirectional"))
      (node (ref "IC1301") (pin "3") (pinfunction "SCL_3") (pintype "bidirectional"))
      (node (ref "IC1302") (pin "3") (pinfunction "SCL_3") (pintype "bidirectional"))
      (node (ref "IC702") (pin "6") (pinfunction "SCL_6") (pintype "bidirectional"))
      (node (ref "IC801") (pin "51") (pinfunction "IO_L01P_6/VRN_6_51") (pintype "bidirectional"))
      (node (ref "R1301") (pin "1") (pinfunction "1_1") (pintype "passive"))
      (node (ref "R1901") (pin "1") (pinfunction "1_1") (pintype "passive"))
      (node (ref "X1701") (pin "28") (pinfunction "28_28") (pintype "passive"))
    )
    (net (code "62") (name "I2C_SDA") (class "Default")
      (node (ref "IC1201") (pin "31") (pinfunction "B1_FB7_MC14_31") (pintype "bidirectional"))
      (node (ref "IC1301") (pin "4") (pinfunction "SDA_4") (pintype "bidirectional"))
      (node (ref "IC1302") (pin "4") (pinfunction "SDA_4") (pintype "bidirectional"))
      (node (ref "IC702") (pin "5") (pinfunction "SDA_5") (pintype "bidirectional"))
      (node (ref "IC801") (pin "52") (pinfunction "IO_L01N_6/VRP_6_52") (pintype "bidirectional"))
      (node (ref "R1302") (pin "1") (pinfunction "1_1") (pintype "passive"))
      (node (ref "R1903") (pin "1") (pinfunction "1_1") (pintype "passive"))
      (node (ref "X1701") (pin "26") (pinfunction "26_26") (pintype "passive"))
    )
    (net (code "63") (name "MEM_A0") (class "Default")
      (node (ref "IC601") (pin "12") (pinfunction "A0_12") (pintype "input"))
      (node (ref "IC602") (pin "12") (pinfunction "A0_12") (pintype "input"))
      (node (ref "IC603") (pin "12") (pinfunction "A0_12") (pintype "input"))
      (node (ref "IC701") (pin "12") (pinfunction "A0_12") (pintype "input"))
      (node (ref "IC801") (pin "122") (pinfunction "IO_L23P_3/VREF_3_122") (pintype "bidirectional"))
    )
    (net (code "64") (name "MEM_A1") (class "Default")
      (node (ref "IC601") (pin "11") (pinfunction "A1_11") (pintype "input"))
      (node (ref "IC602") (pin "11") (pinfunction "A1_11") (pintype "input"))
      (node (ref "IC603") (pin "11") (pinfunction "A1_11") (pintype "input"))
      (node (ref "IC701") (pin "11") (pinfunction "A1_11") (pintype "input"))
      (node (ref "IC801") (pin "123") (pinfunction "IO_L23N_3_123") (pintype "bidirectional"))
    )
    (net (code "65") (name "MEM_A2") (class "Default")
      (node (ref "IC601") (pin "10") (pinfunction "A2_10") (pintype "input"))
      (node (ref "IC602") (pin "10") (pinfunction "A2_10") (pintype "input"))
      (node (ref "IC603") (pin "10") (pinfunction "A2_10") (pintype "input"))
      (node (ref "IC701") (pin "10") (pinfunction "A2_10") (pintype "input"))
      (node (ref "IC801") (pin "124") (pinfunction "IO_L24P_3_124") (pintype "bidirectional"))
    )
    (net (code "66") (name "MEM_A3") (class "Default")
      (node (ref "IC601") (pin "9") (pinfunction "A3_9") (pintype "input"))
      (node (ref "IC602") (pin "9") (pinfunction "A3_9") (pintype "input"))
      (node (ref "IC603") (pin "9") (pinfunction "A3_9") (pintype "input"))
      (node (ref "IC701") (pin "9") (pinfunction "A3_9") (pintype "input"))
      (node (ref "IC801") (pin "125") (pinfunction "IO_L24N_3_125") (pintype "bidirectional"))
    )
    (net (code "67") (name "MEM_A4") (class "Default")
      (node (ref "IC601") (pin "8") (pinfunction "A4_8") (pintype "input"))
      (node (ref "IC602") (pin "8") (pinfunction "A4_8") (pintype "input"))
      (node (ref "IC603") (pin "8") (pinfunction "A4_8") (pintype "input"))
      (node (ref "IC701") (pin "8") (pinfunction "A4_8") (pintype "input"))
      (node (ref "IC801") (pin "126") (pinfunction "IO_L39P_3_126") (pintype "bidirectional"))
    )
    (net (code "68") (name "MEM_A5") (class "Default")
      (node (ref "IC601") (pin "7") (pinfunction "A5_7") (pintype "input"))
      (node (ref "IC602") (pin "7") (pinfunction "A5_7") (pintype "input"))
      (node (ref "IC603") (pin "7") (pinfunction "A5_7") (pintype "input"))
      (node (ref "IC701") (pin "7") (pinfunction "A5_7") (pintype "input"))
      (node (ref "IC801") (pin "128") (pinfunction "IO_L39N_3_128") (pintype "bidirectional"))
    )
    (net (code "69") (name "MEM_A6") (class "Default")
      (node (ref "IC601") (pin "6") (pinfunction "A6_6") (pintype "input"))
      (node (ref "IC602") (pin "6") (pinfunction "A6_6") (pintype "input"))
      (node (ref "IC603") (pin "6") (pinfunction "A6_6") (pintype "input"))
      (node (ref "IC701") (pin "6") (pinfunction "A6_6") (pintype "input"))
      (node (ref "IC801") (pin "130") (pinfunction "IO_L40P_3_130") (pintype "bidirectional"))
    )
    (net (code "70") (name "MEM_A7") (class "Default")
      (node (ref "IC601") (pin "5") (pinfunction "A7_5") (pintype "input"))
      (node (ref "IC602") (pin "5") (pinfunction "A7_5") (pintype "input"))
      (node (ref "IC603") (pin "5") (pinfunction "A7_5") (pintype "input"))
      (node (ref "IC701") (pin "5") (pinfunction "A7_5") (pintype "input"))
      (node (ref "IC801") (pin "131") (pinfunction "IO_L40N_3/VREF_3_131") (pintype "bidirectional"))
    )
    (net (code "71") (name "MEM_A8") (class "Default")
      (node (ref "IC601") (pin "27") (pinfunction "A8_27") (pintype "input"))
      (node (ref "IC602") (pin "27") (pinfunction "A8_27") (pintype "input"))
      (node (ref "IC603") (pin "27") (pinfunction "A8_27") (pintype "input"))
      (node (ref "IC701") (pin "27") (pinfunction "A8_27") (pintype "input"))
      (node (ref "IC801") (pin "132") (pinfunction "IO_L40P_2/VREF_2_132") (pintype "bidirectional"))
    )
    (net (code "72") (name "MEM_A9") (class "Default")
      (node (ref "IC601") (pin "26") (pinfunction "A9_26") (pintype "input"))
      (node (ref "IC602") (pin "26") (pinfunction "A9_26") (pintype "input"))
      (node (ref "IC603") (pin "26") (pinfunction "A9_26") (pintype "input"))
      (node (ref "IC701") (pin "26") (pinfunction "A9_26") (pintype "input"))
      (node (ref "IC801") (pin "133") (pinfunction "IO_L40N_2_133") (pintype "bidirectional"))
    )
    (net (code "73") (name "MEM_A10") (class "Default")
      (node (ref "IC601") (pin "23") (pinfunction "A10_23") (pintype "input"))
      (node (ref "IC602") (pin "23") (pinfunction "A10_23") (pintype "input"))
      (node (ref "IC603") (pin "23") (pinfunction "A10_23") (pintype "input"))
      (node (ref "IC701") (pin "23") (pinfunction "A10_23") (pintype "input"))
      (node (ref "IC801") (pin "135") (pinfunction "IO_L39P_2_135") (pintype "bidirectional"))
    )
    (net (code "74") (name "MEM_A11") (class "Default")
      (node (ref "IC601") (pin "25") (pinfunction "A11_25") (pintype "input"))
      (node (ref "IC602") (pin "25") (pinfunction "A11_25") (pintype "input"))
      (node (ref "IC603") (pin "25") (pinfunction "A11_25") (pintype "input"))
      (node (ref "IC701") (pin "25") (pinfunction "A11_25") (pintype "input"))
      (node (ref "IC801") (pin "137") (pinfunction "IO_L39N_2_137") (pintype "bidirectional"))
    )
    (net (code "75") (name "MEM_A12") (class "Default")
      (node (ref "IC601") (pin "4") (pinfunction "A12_4") (pintype "input"))
      (node (ref "IC602") (pin "4") (pinfunction "A12_4") (pintype "input"))
      (node (ref "IC603") (pin "4") (pinfunction "A12_4") (pintype "input"))
      (node (ref "IC701") (pin "4") (pinfunction "A12_4") (pintype "input"))
      (node (ref "IC801") (pin "138") (pinfunction "IO_L24P_2_138") (pintype "bidirectional"))
    )
    (net (code "76") (name "MEM_A13") (class "Default")
      (node (ref "IC601") (pin "28") (pinfunction "A13_28") (pintype "input"))
      (node (ref "IC602") (pin "28") (pinfunction "A13_28") (pintype "input"))
      (node (ref "IC603") (pin "28") (pinfunction "A13_28") (pintype "input"))
      (node (ref "IC701") (pin "28") (pinfunction "A13_28") (pintype "input"))
      (node (ref "IC801") (pin "139") (pinfunction "IO_L24N_2_139") (pintype "bidirectional"))
    )
    (net (code "77") (name "MEM_A14") (class "Default")
      (node (ref "IC601") (pin "3") (pinfunction "A14_3") (pintype "input"))
      (node (ref "IC602") (pin "3") (pinfunction "A14_3") (pintype "input"))
      (node (ref "IC603") (pin "3") (pinfunction "A14_3") (pintype "input"))
      (node (ref "IC701") (pin "29") (pinfunction "A14_29") (pintype "input"))
      (node (ref "IC801") (pin "140") (pinfunction "IO_L23P_2_140") (pintype "bidirectional"))
    )
    (net (code "78") (name "MEM_A15") (class "Default")
      (node (ref "IC601") (pin "31") (pinfunction "A15_31") (pintype "input"))
      (node (ref "IC602") (pin "31") (pinfunction "A15_31") (pintype "input"))
      (node (ref "IC603") (pin "31") (pinfunction "A15_31") (pintype "input"))
      (node (ref "IC701") (pin "3") (pinfunction "A15_3") (pintype "input"))
      (node (ref "IC801") (pin "141") (pinfunction "IO_L23N_2/VREF_2_141") (pintype "bidirectional"))
    )
    (net (code "79") (name "MEM_A16") (class "Default")
      (node (ref "IC601") (pin "2") (pinfunction "A16_2") (pintype "input"))
      (node (ref "IC602") (pin "2") (pinfunction "A16_2") (pintype "input"))
      (node (ref "IC603") (pin "2") (pinfunction "A16_2") (pintype "input"))
      (node (ref "IC701") (pin "2") (pinfunction "A16_2") (pintype "input"))
      (node (ref "IC801") (pin "143") (pinfunction "IO_L22P_2_143") (pintype "bidirectional"))
    )
    (net (code "80") (name "MEM_A17") (class "Default")
      (node (ref "IC601") (pin "30") (pinfunction "A17_30") (pintype "input"))
      (node (ref "IC602") (pin "30") (pinfunction "A17_30") (pintype "input"))
      (node (ref "IC603") (pin "30") (pinfunction "A17_30") (pintype "input"))
      (node (ref "IC701") (pin "30") (pinfunction "A17_30") (pintype "input"))
      (node (ref "IC801") (pin "144") (pinfunction "IO_L22N_2_144") (pintype "bidirectional"))
    )
    (net (code "81") (name "MEM_A18") (class "Default")
      (node (ref "IC601") (pin "1") (pinfunction "A18_1") (pintype "input"))
      (node (ref "IC602") (pin "1") (pinfunction "A18_1") (pintype "input"))
      (node (ref "IC603") (pin "1") (pinfunction "A18_1") (pintype "input"))
      (node (ref "IC701") (pin "1") (pinfunction "A18_1") (pintype "input"))
      (node (ref "IC801") (pin "146") (pinfunction "IO_L21P_2_146") (pintype "bidirectional"))
    )
    (net (code "82") (name "MEM_D0") (class "Default")
      (node (ref "IC602") (pin "13") (pinfunction "D0_13") (pintype "bidirectional"))
      (node (ref "IC603") (pin "13") (pinfunction "D0_13") (pintype "bidirectional"))
      (node (ref "IC701") (pin "13") (pinfunction "D0_13") (pintype "bidirectional"))
      (node (ref "IC801") (pin "106") (pinfunction "IO_L01P_3/VRN_3_106") (pintype "bidirectional"))
    )
    (net (code "83") (name "MEM_D1") (class "Default")
      (node (ref "IC602") (pin "14") (pinfunction "D1_14") (pintype "bidirectional"))
      (node (ref "IC603") (pin "14") (pinfunction "D1_14") (pintype "bidirectional"))
      (node (ref "IC701") (pin "14") (pinfunction "D1_14") (pintype "bidirectional"))
      (node (ref "IC801") (pin "107") (pinfunction "IO_L01N_3/VRP_3_107") (pintype "bidirectional"))
    )
    (net (code "84") (name "MEM_D2") (class "Default")
      (node (ref "IC602") (pin "15") (pinfunction "D2_15") (pintype "bidirectional"))
      (node (ref "IC603") (pin "15") (pinfunction "D2_15") (pintype "bidirectional"))
      (node (ref "IC701") (pin "15") (pinfunction "D2_15") (pintype "bidirectional"))
      (node (ref "IC801") (pin "108") (pinfunction "IO_L17P_3/VREF_3_108") (pintype "bidirectional"))
    )
    (net (code "85") (name "MEM_D3") (class "Default")
      (node (ref "IC602") (pin "17") (pinfunction "D3_17") (pintype "bidirectional"))
      (node (ref "IC603") (pin "17") (pinfunction "D3_17") (pintype "bidirectional"))
      (node (ref "IC701") (pin "17") (pinfunction "D3_17") (pintype "bidirectional"))
      (node (ref "IC801") (pin "109") (pinfunction "IO_L17N_3_109") (pintype "bidirectional"))
    )
    (net (code "86") (name "MEM_D4") (class "Default")
      (node (ref "IC602") (pin "18") (pinfunction "D4_18") (pintype "bidirectional"))
      (node (ref "IC603") (pin "18") (pinfunction "D4_18") (pintype "bidirectional"))
      (node (ref "IC701") (pin "18") (pinfunction "D4_18") (pintype "bidirectional"))
      (node (ref "IC801") (pin "111") (pinfunction "IO_L19P_3_111") (pintype "bidirectional"))
    )
    (net (code "87") (name "MEM_D5") (class "Default")
      (node (ref "IC602") (pin "19") (pinfunction "D5_19") (pintype "bidirectional"))
      (node (ref "IC603") (pin "19") (pinfunction "D5_19") (pintype "bidirectional"))
      (node (ref "IC701") (pin "19") (pinfunction "D5_19") (pintype "bidirectional"))
      (node (ref "IC801") (pin "113") (pinfunction "IO_L19N_3_113") (pintype "bidirectional"))
    )
    (net (code "88") (name "MEM_D6") (class "Default")
      (node (ref "IC602") (pin "20") (pinfunction "D6_20") (pintype "bidirectional"))
      (node (ref "IC603") (pin "20") (pinfunction "D6_20") (pintype "bidirectional"))
      (node (ref "IC701") (pin "20") (pinfunction "D6_20") (pintype "bidirectional"))
      (node (ref "IC801") (pin "114") (pinfunction "IO_L20P_3_114") (pintype "bidirectional"))
    )
    (net (code "89") (name "MEM_D7") (class "Default")
      (node (ref "IC602") (pin "21") (pinfunction "D7_21") (pintype "bidirectional"))
      (node (ref "IC603") (pin "21") (pinfunction "D7_21") (pintype "bidirectional"))
      (node (ref "IC701") (pin "21") (pinfunction "D7_21") (pintype "bidirectional"))
      (node (ref "IC801") (pin "115") (pinfunction "IO_L20N_3_115") (pintype "bidirectional"))
    )
    (net (code "90") (name "Net-(D101-PadA)") (class "Default")
      (node (ref "D101") (pin "A") (pinfunction "A_A") (pintype "passive"))
      (node (ref "X101") (pin "2") (pinfunction "2_2") (pintype "passive"))
    )
    (net (code "91") (name "Net-(DIS1901-A1)") (class "Default")
      (node (ref "DIS1901") (pin "16") (pinfunction "A1_16") (pintype "passive"))
      (node (ref "RN1901") (pin "2") (pinfunction "2_2") (pintype "passive"))
    )
    (net (code "92") (name "Net-(DIS1901-A2)") (class "Default")
      (node (ref "DIS1901") (pin "11") (pinfunction "A2_11") (pintype "passive"))
      (node (ref "RN1903") (pin "1") (pinfunction "1_1") (pintype "passive"))
    )
    (net (code "93") (name "Net-(DIS1901-B1)") (class "Default")
      (node (ref "DIS1901") (pin "14") (pinfunction "B1_14") (pintype "passive"))
      (node (ref "RN1901") (pin "4") (pinfunction "2_4") (pintype "passive"))
    )
    (net (code "94") (name "Net-(DIS1901-B2)") (class "Default")
      (node (ref "DIS1901") (pin "13") (pinfunction "B2_13") (pintype "passive"))
      (node (ref "RN1903") (pin "3") (pinfunction "1_3") (pintype "passive"))
    )
    (net (code "95") (name "Net-(DIS1901-C1)") (class "Default")
      (node (ref "DIS1901") (pin "1") (pinfunction "C1_1") (pintype "passive"))
      (node (ref "RN1901") (pin "6") (pinfunction "2_6") (pintype "passive"))
    )
    (net (code "96") (name "Net-(DIS1901-C2)") (class "Default")
      (node (ref "DIS1901") (pin "8") (pinfunction "C2_8") (pintype "passive"))
      (node (ref "RN1903") (pin "5") (pinfunction "1_5") (pintype "passive"))
    )
    (net (code "97") (name "Net-(DIS1901-COM1)") (class "Default")
      (node (ref "DIS1901") (pin "4") (pinfunction "COM1_4") (pintype "passive"))
      (node (ref "J1901") (pin "2") (pinfunction "2_2") (pintype "passive"))
      (node (ref "J1902") (pin "2") (pinfunction "2_2") (pintype "passive"))
    )
    (net (code "98") (name "Net-(DIS1901-COM2)") (class "Default")
      (node (ref "DIS1901") (pin "5") (pinfunction "COM2_5") (pintype "passive"))
      (node (ref "J1903") (pin "1") (pinfunction "1_1") (pintype "passive"))
      (node (ref "J1904") (pin "1") (pinfunction "1_1") (pintype "passive"))
    )
    (net (code "99") (name "Net-(DIS1901-D1)") (class "Default")
      (node (ref "DIS1901") (pin "3") (pinfunction "D1_3") (pintype "passive"))
      (node (ref "RN1901") (pin "8") (pinfunction "2_8") (pintype "passive"))
    )
    (net (code "100") (name "Net-(DIS1901-D2)") (class "Default")
      (node (ref "DIS1901") (pin "6") (pinfunction "D2_6") (pintype "passive"))
      (node (ref "RN1903") (pin "7") (pinfunction "1_7") (pintype "passive"))
    )
    (net (code "101") (name "Net-(DIS1901-DP1)") (class "Default")
      (node (ref "DIS1901") (pin "18") (pinfunction "DP1_18") (pintype "passive"))
      (node (ref "RN1902") (pin "8") (pinfunction "2_8") (pintype "passive"))
    )
    (net (code "102") (name "Net-(DIS1901-DP2)") (class "Default")
      (node (ref "DIS1901") (pin "9") (pinfunction "DP2_9") (pintype "passive"))
      (node (ref "RN1904") (pin "8") (pinfunction "2_8") (pintype "passive"))
    )
    (net (code "103") (name "Net-(DIS1901-E1)") (class "Default")
      (node (ref "DIS1901") (pin "2") (pinfunction "E1_2") (pintype "passive"))
      (node (ref "RN1902") (pin "2") (pinfunction "2_2") (pintype "passive"))
    )
    (net (code "104") (name "Net-(DIS1901-E2)") (class "Default")
      (node (ref "DIS1901") (pin "7") (pinfunction "E2_7") (pintype "passive"))
      (node (ref "RN1904") (pin "1") (pinfunction "1_1") (pintype "passive"))
    )
    (net (code "105") (name "Net-(DIS1901-F1)") (class "Default")
      (node (ref "DIS1901") (pin "15") (pinfunction "F1_15") (pintype "passive"))
      (node (ref "RN1902") (pin "4") (pinfunction "2_4") (pintype "passive"))
    )
    (net (code "106") (name "Net-(DIS1901-F2)") (class "Default")
      (node (ref "DIS1901") (pin "12") (pinfunction "F2_12") (pintype "passive"))
      (node (ref "RN1904") (pin "3") (pinfunction "1_3") (pintype "passive"))
    )
    (net (code "107") (name "Net-(DIS1901-G1)") (class "Default")
      (node (ref "DIS1901") (pin "17") (pinfunction "G1_17") (pintype "passive"))
      (node (ref "RN1902") (pin "6") (pinfunction "2_6") (pintype "passive"))
    )
    (net (code "108") (name "Net-(DIS1901-G2)") (class "Default")
      (node (ref "DIS1901") (pin "10") (pinfunction "G2_10") (pintype "passive"))
      (node (ref "RN1904") (pin "5") (pinfunction "1_5") (pintype "passive"))
    )
    (net (code "109") (name "Net-(IC201-OUT)") (class "Default")
      (node (ref "C205") (pin "1") (pinfunction "1_1") (pintype "passive"))
      (node (ref "IC201") (pin "2") (pinfunction "OUT_2") (pintype "power_in"))
      (node (ref "J201") (pin "1") (pinfunction "1_1") (pintype "passive"))
      (node (ref "R204") (pin "2") (pinfunction "2_2") (pintype "passive"))
      (node (ref "TP202") (pin "1") (pinfunction "TP_1") (pintype "passive"))
    )
    (net (code "110") (name "Net-(IC202-AJD)") (class "Default")
      (node (ref "IC202") (pin "1") (pinfunction "AJD_1") (pintype "passive"))
      (node (ref "R201") (pin "2") (pinfunction "2_2") (pintype "passive"))
      (node (ref "R205") (pin "1") (pinfunction "1_1") (pintype "passive"))
    )
    (net (code "111") (name "Net-(IC202-OUT)") (class "Default")
      (node (ref "C206") (pin "1") (pinfunction "1_1") (pintype "passive"))
      (node (ref "IC202") (pin "2") (pinfunction "OUT_2") (pintype "power_in"))
      (node (ref "J202") (pin "1") (pinfunction "1_1") (pintype "passive"))
      (node (ref "R205") (pin "2") (pinfunction "2_2") (pintype "passive"))
      (node (ref "TP203") (pin "1") (pinfunction "TP_1") (pintype "passive"))
    )
    (net (code "112") (name "Net-(IC203-AJD)") (class "Default")
      (node (ref "IC203") (pin "1") (pinfunction "AJD_1") (pintype "passive"))
      (node (ref "R202") (pin "2") (pinfunction "2_2") (pintype "passive"))
      (node (ref "R203") (pin "1") (pinfunction "1_1") (pintype "passive"))
    )
    (net (code "113") (name "Net-(IC203-OUT)") (class "Default")
      (node (ref "C204") (pin "1") (pinfunction "1_1") (pintype "passive"))
      (node (ref "IC203") (pin "2") (pinfunction "OUT_2") (pintype "power_in"))
      (node (ref "J203") (pin "1") (pinfunction "1_1") (pintype "passive"))
      (node (ref "R203") (pin "2") (pinfunction "2_2") (pintype "passive"))
      (node (ref "R206") (pin "2") (pinfunction "2_2") (pintype "passive"))
      (node (ref "TP201") (pin "1") (pinfunction "TP_1") (pintype "passive"))
    )
    (net (code "114") (name "Net-(IC204-AJD)") (class "Default")
      (node (ref "IC204") (pin "1") (pinfunction "AJD_1") (pintype "passive"))
      (node (ref "R207") (pin "2") (pinfunction "2_2") (pintype "passive"))
      (node (ref "R209") (pin "1") (pinfunction "1_1") (pintype "passive"))
    )
    (net (code "115") (name "Net-(IC204-OUT)") (class "Default")
      (node (ref "C209") (pin "1") (pinfunction "1_1") (pintype "passive"))
      (node (ref "IC204") (pin "2") (pinfunction "OUT_2") (pintype "power_in"))
      (node (ref "J204") (pin "1") (pinfunction "1_1") (pintype "passive"))
      (node (ref "R209") (pin "2") (pinfunction "2_2") (pintype "passive"))
      (node (ref "TP204") (pin "1") (pinfunction "TP_1") (pintype "passive"))
    )
    (net (code "116") (name "Net-(IC205-AJD)") (class "Default")
      (node (ref "IC205") (pin "1") (pinfunction "AJD_1") (pintype "passive"))
      (node (ref "R208") (pin "2") (pinfunction "2_2") (pintype "passive"))
      (node (ref "R210") (pin "1") (pinfunction "1_1") (pintype "passive"))
    )
    (net (code "117") (name "Net-(IC205-OUT)") (class "Default")
      (node (ref "C210") (pin "1") (pinfunction "1_1") (pintype "passive"))
      (node (ref "IC205") (pin "2") (pinfunction "OUT_2") (pintype "power_in"))
      (node (ref "J205") (pin "1") (pinfunction "1_1") (pintype "passive"))
      (node (ref "R210") (pin "2") (pinfunction "2_2") (pintype "passive"))
      (node (ref "TP205") (pin "1") (pinfunction "TP_1") (pintype "passive"))
    )
    (net (code "118") (name "Net-(IC301-OUT)") (class "Default")
      (node (ref "C302") (pin "1") (pinfunction "1_1") (pintype "passive"))
      (node (ref "IC301") (pin "2") (pinfunction "OUT_2") (pintype "power_in"))
      (node (ref "J301") (pin "1") (pinfunction "1_1") (pintype "passive"))
      (node (ref "R304") (pin "2") (pinfunction "2_2") (pintype "passive"))
      (node (ref "TP301") (pin "1") (pinfunction "TP_1") (pintype "passive"))
    )
    (net (code "119") (name "Net-(IC302-OUT)") (class "Default")
      (node (ref "C304") (pin "1") (pinfunction "1_1") (pintype "passive"))
      (node (ref "IC302") (pin "2") (pinfunction "OUT_2") (pintype "power_in"))
      (node (ref "J302") (pin "1") (pinfunction "1_1") (pintype "passive"))
      (node (ref "R310") (pin "2") (pinfunction "2_2") (pintype "passive"))
      (node (ref "TP302") (pin "1") (pinfunction "TP_1") (pintype "passive"))
    )
    (net (code "120") (name "Net-(IC401A-I0)") (class "Default")
      (node (ref "C402") (pin "+") (pinfunction "+_+") (pintype "passive"))
      (node (ref "D401") (pin "A") (pinfunction "A_A") (pintype "passive"))
      (node (ref "IC401") (pin "1") (pinfunction "I0_1") (pintype "input"))
      (node (ref "IC401") (pin "2") (pinfunction "I1_2") (pintype "input"))
      (node (ref "R405") (pin "1") (pinfunction "1_1") (pintype "passive"))
      (node (ref "R406") (pin "1") (pinfunction "1_1") (pintype "passive"))
    )
    (net (code "121") (name "Net-(IC401A-O)") (class "Default")
      (node (ref "IC401") (pin "3") (pinfunction "O_3") (pintype "output"))
      (node (ref "T401") (pin "1") (pinfunction "G_1") (pintype "passive"))
    )
    (net (code "122") (name "Net-(IC401B-I0)") (class "Default")
      (node (ref "C401") (pin "1") (pinfunction "1_1") (pintype "passive"))
      (node (ref "IC401") (pin "5") (pinfunction "I0_5") (pintype "input"))
      (node (ref "IC401") (pin "6") (pinfunction "I1_6") (pintype "input"))
      (node (ref "R403") (pin "2") (pinfunction "2_2") (pintype "passive"))
    )
    (net (code "123") (name "Net-(IC1801A-I0)") (class "Default")
      (node (ref "IC1801") (pin "1") (pinfunction "I0_1") (pintype "input"))
      (node (ref "RN1801") (pin "2") (pinfunction "2_2") (pintype "passive"))
    )
    (net (code "124") (name "Net-(IC1801A-I1)") (class "Default")
      (node (ref "IC1801") (pin "2") (pinfunction "I1_2") (pintype "input"))
      (node (ref "RN1801") (pin "4") (pinfunction "2_4") (pintype "passive"))
    )
    (net (code "125") (name "Net-(IC1801A-O)") (class "Default")
      (node (ref "IC1801") (pin "3") (pinfunction "O_3") (pintype "output"))
      (node (ref "TP1801") (pin "1") (pinfunction "TP_1") (pintype "passive"))
    )
    (net (code "126") (name "Net-(IC1801B-I0)") (class "Default")
      (node (ref "IC1801") (pin "5") (pinfunction "I0_5") (pintype "input"))
      (node (ref "RN1801") (pin "6") (pinfunction "2_6") (pintype "passive"))
    )
    (net (code "127") (name "Net-(IC1801B-I1)") (class "Default")
      (node (ref "IC1801") (pin "6") (pinfunction "I1_6") (pintype "input"))
      (node (ref "RN1801") (pin "8") (pinfunction "2_8") (pintype "passive"))
    )
    (net (code "128") (name "Net-(IC1801B-O)") (class "Default")
      (node (ref "IC1801") (pin "4") (pinfunction "O_4") (pintype "output"))
      (node (ref "TP1802") (pin "1") (pinfunction "TP_1") (pintype "passive"))
    )
    (net (code "129") (name "Net-(IC2001A-O)") (class "Default")
      (node (ref "IC2001") (pin "3") (pinfunction "O_3") (pintype "output"))
      (node (ref "IC2001") (pin "5") (pinfunction "I0_5") (pintype "input"))
    )
    (net (code "130") (name "Net-(IC2001D-O)") (class "Default")
      (node (ref "IC2001") (pin "11") (pinfunction "O_11") (pintype "output"))
      (node (ref "R2001") (pin "2") (pinfunction "2_2") (pintype "passive"))
    )
    (net (code "131") (name "Net-(LED201-PadA)") (class "Default")
      (node (ref "LED201") (pin "A") (pinfunction "A_A") (pintype "passive"))
      (node (ref "R206") (pin "1") (pinfunction "1_1") (pintype "passive"))
    )
    (net (code "132") (name "Net-(LED1701-PadC)") (class "Default")
      (node (ref "LED1701") (pin "C") (pinfunction "C_C") (pintype "passive"))
      (node (ref "R1701") (pin "2") (pinfunction "2_2") (pintype "passive"))
    )
    (net (code "133") (name "Net-(LED1702-PadC)") (class "Default")
      (node (ref "LED1702") (pin "C") (pinfunction "C_C") (pintype "passive"))
      (node (ref "R1702") (pin "2") (pinfunction "2_2") (pintype "passive"))
    )
    (net (code "134") (name "Net-(LED1703-PadC)") (class "Default")
      (node (ref "LED1703") (pin "C") (pinfunction "C_C") (pintype "passive"))
      (node (ref "R1703") (pin "2") (pinfunction "2_2") (pintype "passive"))
    )
    (net (code "135") (name "Net-(LED1704-PadC)") (class "Default")
      (node (ref "LED1704") (pin "C") (pinfunction "C_C") (pintype "passive"))
      (node (ref "R1704") (pin "2") (pinfunction "2_2") (pintype "passive"))
    )
    (net (code "136") (name "Net-(LED1705-PadC)") (class "Default")
      (node (ref "LED1705") (pin "C") (pinfunction "C_C") (pintype "passive"))
      (node (ref "R1705") (pin "2") (pinfunction "2_2") (pintype "passive"))
    )
    (net (code "137") (name "Net-(LED1706-PadC)") (class "Default")
      (node (ref "LED1706") (pin "C") (pinfunction "C_C") (pintype "passive"))
      (node (ref "R1706") (pin "2") (pinfunction "2_2") (pintype "passive"))
    )
    (net (code "138") (name "Net-(LED1707-PadC)") (class "Default")
      (node (ref "LED1707") (pin "C") (pinfunction "C_C") (pintype "passive"))
      (node (ref "R1707") (pin "2") (pinfunction "2_2") (pintype "passive"))
    )
    (net (code "139") (name "Net-(LED1708-PadC)") (class "Default")
      (node (ref "LED1708") (pin "C") (pinfunction "C_C") (pintype "passive"))
      (node (ref "R1708") (pin "2") (pinfunction "2_2") (pintype "passive"))
    )
    (net (code "140") (name "Net-(LED1801-PadA)") (class "Default")
      (node (ref "LED1801") (pin "A") (pinfunction "A_A") (pintype "passive"))
      (node (ref "R1801") (pin "2") (pinfunction "2_2") (pintype "passive"))
    )
    (net (code "141") (name "Net-(LED1802-PadA)") (class "Default")
      (node (ref "LED1802") (pin "A") (pinfunction "A_A") (pintype "passive"))
      (node (ref "R1802") (pin "2") (pinfunction "2_2") (pintype "passive"))
    )
    (net (code "142") (name "Net-(LED1901-PadC)") (class "Default")
      (node (ref "LED1901") (pin "C") (pinfunction "C_C") (pintype "passive"))
      (node (ref "R1902") (pin "2") (pinfunction "2_2") (pintype "passive"))
    )
    (net (code "143") (name "Net-(LED1902-PadC)") (class "Default")
      (node (ref "LED1902") (pin "C") (pinfunction "C_C") (pintype "passive"))
      (node (ref "R1904") (pin "2") (pinfunction "2_2") (pintype "passive"))
    )
    (net (code "144") (name "Net-(LED2101-PadA)") (class "Default")
      (node (ref "LED2101") (pin "A") (pinfunction "A_A") (pintype "passive"))
      (node (ref "R2103") (pin "2") (pinfunction "2_2") (pintype "passive"))
    )
    (net (code "145") (name "Net-(LED2102-PadA)") (class "Default")
      (node (ref "LED2102") (pin "A") (pinfunction "A_A") (pintype "passive"))
      (node (ref "R2104") (pin "2") (pinfunction "2_2") (pintype "passive"))
    )
    (net (code "146") (name "Net-(LED2103-PadA)") (class "Default")
      (node (ref "LED2103") (pin "A") (pinfunction "A_A") (pintype "passive"))
      (node (ref "R2107") (pin "1") (pinfunction "1_1") (pintype "passive"))
    )
    (net (code "147") (name "Net-(LED2104-PadA)") (class "Default")
      (node (ref "LED2104") (pin "A") (pinfunction "A_A") (pintype "passive"))
      (node (ref "R2108") (pin "1") (pinfunction "1_1") (pintype "passive"))
    )
    (net (code "148") (name "Net-(LED2105-PadA)") (class "Default")
      (node (ref "LED2105") (pin "A") (pinfunction "A_A") (pintype "passive"))
      (node (ref "R2111") (pin "2") (pinfunction "2_2") (pintype "passive"))
    )
    (net (code "149") (name "Net-(LED2106-PadA)") (class "Default")
      (node (ref "LED2106") (pin "A") (pinfunction "A_A") (pintype "passive"))
      (node (ref "R2112") (pin "2") (pinfunction "2_2") (pintype "passive"))
    )
    (net (code "150") (name "Net-(LED2107-PadA)") (class "Default")
      (node (ref "LED2107") (pin "A") (pinfunction "A_A") (pintype "passive"))
      (node (ref "R2115") (pin "2") (pinfunction "2_2") (pintype "passive"))
    )
    (net (code "151") (name "Net-(LED2108-PadA)") (class "Default")
      (node (ref "LED2108") (pin "A") (pinfunction "A_A") (pintype "passive"))
      (node (ref "R2116") (pin "2") (pinfunction "2_2") (pintype "passive"))
    )
    (net (code "152") (name "Net-(LED2109-PadA)") (class "Default")
      (node (ref "LED2109") (pin "A") (pinfunction "A_A") (pintype "passive"))
      (node (ref "R2119") (pin "2") (pinfunction "2_2") (pintype "passive"))
    )
    (net (code "153") (name "Net-(LED2110-PadA)") (class "Default")
      (node (ref "LED2110") (pin "A") (pinfunction "A_A") (pintype "passive"))
      (node (ref "R2120") (pin "2") (pinfunction "2_2") (pintype "passive"))
    )
    (net (code "154") (name "Net-(LED2201-PadA)") (class "Default")
      (node (ref "LED2201") (pin "A") (pinfunction "A_A") (pintype "passive"))
      (node (ref "R2205") (pin "2") (pinfunction "2_2") (pintype "passive"))
    )
    (net (code "155") (name "Net-(LED2202-PadA)") (class "Default")
      (node (ref "LED2202") (pin "A") (pinfunction "A_A") (pintype "passive"))
      (node (ref "R2206") (pin "2") (pinfunction "2_2") (pintype "passive"))
    )
    (net (code "156") (name "Net-(LED2301-PadA)") (class "Default")
      (node (ref "LED2301") (pin "A") (pinfunction "A_A") (pintype "passive"))
      (node (ref "R2303") (pin "2") (pinfunction "2_2") (pintype "passive"))
    )
    (net (code "157") (name "Net-(LED2302-PadA)") (class "Default")
      (node (ref "LED2302") (pin "A") (pinfunction "A_A") (pintype "passive"))
      (node (ref "R2304") (pin "2") (pinfunction "2_2") (pintype "passive"))
    )
    (net (code "158") (name "Net-(LED2303-PadA)") (class "Default")
      (node (ref "LED2303") (pin "A") (pinfunction "A_A") (pintype "passive"))
      (node (ref "R2307") (pin "2") (pinfunction "2_2") (pintype "passive"))
    )
    (net (code "159") (name "Net-(LED2304-PadA)") (class "Default")
      (node (ref "LED2304") (pin "A") (pinfunction "A_A") (pintype "passive"))
      (node (ref "R2308") (pin "2") (pinfunction "2_2") (pintype "passive"))
    )
    (net (code "160") (name "Net-(LED2305-PadA)") (class "Default")
      (node (ref "LED2305") (pin "A") (pinfunction "A_A") (pintype "passive"))
      (node (ref "R2311") (pin "2") (pinfunction "2_2") (pintype "passive"))
    )
    (net (code "161") (name "Net-(LED2306-PadA)") (class "Default")
      (node (ref "LED2306") (pin "A") (pinfunction "A_A") (pintype "passive"))
      (node (ref "R2312") (pin "2") (pinfunction "2_2") (pintype "passive"))
    )
    (net (code "162") (name "Net-(LED2307-PadA)") (class "Default")
      (node (ref "LED2307") (pin "A") (pinfunction "A_A") (pintype "passive"))
      (node (ref "R2315") (pin "2") (pinfunction "2_2") (pintype "passive"))
    )
    (net (code "163") (name "Net-(LED2308-PadA)") (class "Default")
      (node (ref "LED2308") (pin "A") (pinfunction "A_A") (pintype "passive"))
      (node (ref "R2316") (pin "2") (pinfunction "2_2") (pintype "passive"))
    )
    (net (code "164") (name "Net-(LED2401-PadA)") (class "Default")
      (node (ref "LED2401") (pin "A") (pinfunction "A_A") (pintype "passive"))
      (node (ref "R2404") (pin "1") (pinfunction "1_1") (pintype "passive"))
    )
    (net (code "165") (name "Net-(LED2402-PadA)") (class "Default")
      (node (ref "LED2402") (pin "A") (pinfunction "A_A") (pintype "passive"))
      (node (ref "R2406") (pin "2") (pinfunction "2_2") (pintype "passive"))
    )
    (net (code "166") (name "Net-(LED2403-PadA)") (class "Default")
      (node (ref "LED2403") (pin "A") (pinfunction "A_A") (pintype "passive"))
      (node (ref "R2408") (pin "2") (pinfunction "2_2") (pintype "passive"))
    )
    (net (code "167") (name "Net-(LED2404-PadA)") (class "Default")
      (node (ref "LED2404") (pin "A") (pinfunction "A_A") (pintype "passive"))
      (node (ref "R2409") (pin "2") (pinfunction "2_2") (pintype "passive"))
    )
    (net (code "168") (name "Net-(LED2501-PadA)") (class "Default")
      (node (ref "LED2501") (pin "A") (pinfunction "A_A") (pintype "passive"))
      (node (ref "R2504") (pin "1") (pinfunction "1_1") (pintype "passive"))
    )
    (net (code "169") (name "Net-(LED2502-PadA)") (class "Default")
      (node (ref "LED2502") (pin "A") (pinfunction "A_A") (pintype "passive"))
      (node (ref "R2506") (pin "2") (pinfunction "2_2") (pintype "passive"))
    )
    (net (code "170") (name "Net-(LED2503-PadA)") (class "Default")
      (node (ref "LED2503") (pin "A") (pinfunction "A_A") (pintype "passive"))
      (node (ref "R2508") (pin "2") (pinfunction "2_2") (pintype "passive"))
    )
    (net (code "171") (name "Net-(LED2504-PadA)") (class "Default")
      (node (ref "LED2504") (pin "A") (pinfunction "A_A") (pintype "passive"))
      (node (ref "R2509") (pin "2") (pinfunction "2_2") (pintype "passive"))
    )
    (net (code "172") (name "Net-(T301-D)") (class "Default")
      (node (ref "R301") (pin "1") (pinfunction "1_1") (pintype "passive"))
      (node (ref "T301") (pin "3") (pinfunction "D_3") (pintype "passive"))
    )
    (net (code "173") (name "Net-(T302-D)") (class "Default")
      (node (ref "R303") (pin "1") (pinfunction "1_1") (pintype "passive"))
      (node (ref "T302") (pin "3") (pinfunction "D_3") (pintype "passive"))
    )
    (net (code "174") (name "Net-(T303-D)") (class "Default")
      (node (ref "R305") (pin "1") (pinfunction "1_1") (pintype "passive"))
      (node (ref "T303") (pin "3") (pinfunction "D_3") (pintype "passive"))
    )
    (net (code "175") (name "Net-(T304-D)") (class "Default")
      (node (ref "R306") (pin "1") (pinfunction "1_1") (pintype "passive"))
      (node (ref "T304") (pin "3") (pinfunction "D_3") (pintype "passive"))
    )
    (net (code "176") (name "Net-(T305-D)") (class "Default")
      (node (ref "R307") (pin "1") (pinfunction "1_1") (pintype "passive"))
      (node (ref "T305") (pin "3") (pinfunction "D_3") (pintype "passive"))
    )
    (net (code "177") (name "Net-(T306-D)") (class "Default")
      (node (ref "R309") (pin "1") (pinfunction "1_1") (pintype "passive"))
      (node (ref "T306") (pin "3") (pinfunction "D_3") (pintype "passive"))
    )
    (net (code "178") (name "Net-(T1901-D)") (class "Default")
      (node (ref "R1902") (pin "1") (pinfunction "1_1") (pintype "passive"))
      (node (ref "T1901") (pin "3") (pinfunction "D_3") (pintype "passive"))
    )
    (net (code "179") (name "Net-(T1901-G)") (class "Default")
      (node (ref "R1901") (pin "2") (pinfunction "2_2") (pintype "passive"))
      (node (ref "T1901") (pin "1") (pinfunction "G_1") (pintype "passive"))
    )
    (net (code "180") (name "Net-(T1902-D)") (class "Default")
      (node (ref "R1904") (pin "1") (pinfunction "1_1") (pintype "passive"))
      (node (ref "T1902") (pin "3") (pinfunction "D_3") (pintype "passive"))
    )
    (net (code "181") (name "Net-(T1902-G)") (class "Default")
      (node (ref "R1903") (pin "2") (pinfunction "2_2") (pintype "passive"))
      (node (ref "T1902") (pin "1") (pinfunction "G_1") (pintype "passive"))
    )
    (net (code "182") (name "Net-(T2101-D)") (class "Default")
      (node (ref "LED2101") (pin "C") (pinfunction "C_C") (pintype "passive"))
      (node (ref "T2101") (pin "3") (pinfunction "D_3") (pintype "passive"))
    )
    (net (code "183") (name "Net-(T2101-G)") (class "Default")
      (node (ref "R2101") (pin "1") (pinfunction "1_1") (pintype "passive"))
      (node (ref "T2101") (pin "1") (pinfunction "G_1") (pintype "passive"))
    )
    (net (code "184") (name "Net-(T2102-D)") (class "Default")
      (node (ref "LED2102") (pin "C") (pinfunction "C_C") (pintype "passive"))
      (node (ref "T2102") (pin "3") (pinfunction "D_3") (pintype "passive"))
    )
    (net (code "185") (name "Net-(T2102-G)") (class "Default")
      (node (ref "R2102") (pin "1") (pinfunction "1_1") (pintype "passive"))
      (node (ref "T2102") (pin "1") (pinfunction "G_1") (pintype "passive"))
    )
    (net (code "186") (name "Net-(T2103-D)") (class "Default")
      (node (ref "LED2103") (pin "C") (pinfunction "C_C") (pintype "passive"))
      (node (ref "T2103") (pin "3") (pinfunction "D_3") (pintype "passive"))
    )
    (net (code "187") (name "Net-(T2103-G)") (class "Default")
      (node (ref "R2105") (pin "1") (pinfunction "1_1") (pintype "passive"))
      (node (ref "T2103") (pin "1") (pinfunction "G_1") (pintype "passive"))
    )
    (net (code "188") (name "Net-(T2104-D)") (class "Default")
      (node (ref "LED2104") (pin "C") (pinfunction "C_C") (pintype "passive"))
      (node (ref "T2104") (pin "3") (pinfunction "D_3") (pintype "passive"))
    )
    (net (code "189") (name "Net-(T2104-G)") (class "Default")
      (node (ref "R2106") (pin "1") (pinfunction "1_1") (pintype "passive"))
      (node (ref "T2104") (pin "1") (pinfunction "G_1") (pintype "passive"))
    )
    (net (code "190") (name "Net-(T2105-D)") (class "Default")
      (node (ref "LED2105") (pin "C") (pinfunction "C_C") (pintype "passive"))
      (node (ref "T2105") (pin "3") (pinfunction "D_3") (pintype "passive"))
    )
    (net (code "191") (name "Net-(T2105-G)") (class "Default")
      (node (ref "R2109") (pin "1") (pinfunction "1_1") (pintype "passive"))
      (node (ref "T2105") (pin "1") (pinfunction "G_1") (pintype "passive"))
    )
    (net (code "192") (name "Net-(T2106-D)") (class "Default")
      (node (ref "LED2106") (pin "C") (pinfunction "C_C") (pintype "passive"))
      (node (ref "T2106") (pin "3") (pinfunction "D_3") (pintype "passive"))
    )
    (net (code "193") (name "Net-(T2106-G)") (class "Default")
      (node (ref "R2110") (pin "1") (pinfunction "1_1") (pintype "passive"))
      (node (ref "T2106") (pin "1") (pinfunction "G_1") (pintype "passive"))
    )
    (net (code "194") (name "Net-(T2107-D)") (class "Default")
      (node (ref "LED2107") (pin "C") (pinfunction "C_C") (pintype "passive"))
      (node (ref "T2107") (pin "3") (pinfunction "D_3") (pintype "passive"))
    )
    (net (code "195") (name "Net-(T2107-G)") (class "Default")
      (node (ref "R2113") (pin "1") (pinfunction "1_1") (pintype "passive"))
      (node (ref "T2107") (pin "1") (pinfunction "G_1") (pintype "passive"))
    )
    (net (code "196") (name "Net-(T2108-D)") (class "Default")
      (node (ref "LED2108") (pin "C") (pinfunction "C_C") (pintype "passive"))
      (node (ref "T2108") (pin "3") (pinfunction "D_3") (pintype "passive"))
    )
    (net (code "197") (name "Net-(T2108-G)") (class "Default")
      (node (ref "R2114") (pin "1") (pinfunction "1_1") (pintype "passive"))
      (node (ref "T2108") (pin "1") (pinfunction "G_1") (pintype "passive"))
    )
    (net (code "198") (name "Net-(T2109-D)") (class "Default")
      (node (ref "LED2109") (pin "C") (pinfunction "C_C") (pintype "passive"))
      (node (ref "T2109") (pin "3") (pinfunction "D_3") (pintype "passive"))
    )
    (net (code "199") (name "Net-(T2109-G)") (class "Default")
      (node (ref "R2117") (pin "1") (pinfunction "1_1") (pintype "passive"))
      (node (ref "T2109") (pin "1") (pinfunction "G_1") (pintype "passive"))
    )
    (net (code "200") (name "Net-(T2110-D)") (class "Default")
      (node (ref "LED2110") (pin "C") (pinfunction "C_C") (pintype "passive"))
      (node (ref "T2110") (pin "3") (pinfunction "D_3") (pintype "passive"))
    )
    (net (code "201") (name "Net-(T2110-G)") (class "Default")
      (node (ref "R2118") (pin "1") (pinfunction "1_1") (pintype "passive"))
      (node (ref "T2110") (pin "1") (pinfunction "G_1") (pintype "passive"))
    )
    (net (code "202") (name "Net-(T2201-D)") (class "Default")
      (node (ref "R2203") (pin "2") (pinfunction "2_2") (pintype "passive"))
      (node (ref "T2201") (pin "3") (pinfunction "D_3") (pintype "passive"))
      (node (ref "T2203") (pin "1") (pinfunction "G_1") (pintype "passive"))
    )
    (net (code "203") (name "Net-(T2201-G)") (class "Default")
      (node (ref "R2201") (pin "2") (pinfunction "2_2") (pintype "passive"))
      (node (ref "T2201") (pin "1") (pinfunction "G_1") (pintype "passive"))
    )
    (net (code "204") (name "Net-(T2202-D)") (class "Default")
      (node (ref "R2204") (pin "2") (pinfunction "2_2") (pintype "passive"))
      (node (ref "T2202") (pin "3") (pinfunction "D_3") (pintype "passive"))
      (node (ref "T2204") (pin "1") (pinfunction "G_1") (pintype "passive"))
    )
    (net (code "205") (name "Net-(T2202-G)") (class "Default")
      (node (ref "R2202") (pin "2") (pinfunction "2_2") (pintype "passive"))
      (node (ref "T2202") (pin "1") (pinfunction "G_1") (pintype "passive"))
    )
    (net (code "206") (name "Net-(T2203-D)") (class "Default")
      (node (ref "LED2201") (pin "C") (pinfunction "C_C") (pintype "passive"))
      (node (ref "T2203") (pin "3") (pinfunction "D_3") (pintype "passive"))
    )
    (net (code "207") (name "Net-(T2204-D)") (class "Default")
      (node (ref "LED2202") (pin "C") (pinfunction "C_C") (pintype "passive"))
      (node (ref "T2204") (pin "3") (pinfunction "D_3") (pintype "passive"))
    )
    (net (code "208") (name "Net-(T2301-D)") (class "Default")
      (node (ref "LED2301") (pin "C") (pinfunction "C_C") (pintype "passive"))
      (node (ref "T2301") (pin "3") (pinfunction "D_3") (pintype "passive"))
    )
    (net (code "209") (name "Net-(T2301-G)") (class "Default")
      (node (ref "R2301") (pin "1") (pinfunction "1_1") (pintype "passive"))
      (node (ref "T2301") (pin "1") (pinfunction "G_1") (pintype "passive"))
    )
    (net (code "210") (name "Net-(T2302-D)") (class "Default")
      (node (ref "LED2302") (pin "C") (pinfunction "C_C") (pintype "passive"))
      (node (ref "T2302") (pin "3") (pinfunction "D_3") (pintype "passive"))
    )
    (net (code "211") (name "Net-(T2302-G)") (class "Default")
      (node (ref "R2302") (pin "1") (pinfunction "1_1") (pintype "passive"))
      (node (ref "T2302") (pin "1") (pinfunction "G_1") (pintype "passive"))
    )
    (net (code "212") (name "Net-(T2303-D)") (class "Default")
      (node (ref "LED2303") (pin "C") (pinfunction "C_C") (pintype "passive"))
      (node (ref "T2303") (pin "3") (pinfunction "D_3") (pintype "passive"))
    )
    (net (code "213") (name "Net-(T2303-G)") (class "Default")
      (node (ref "R2305") (pin "1") (pinfunction "1_1") (pintype "passive"))
      (node (ref "T2303") (pin "1") (pinfunction "G_1") (pintype "passive"))
    )
    (net (code "214") (name "Net-(T2304-D)") (class "Default")
      (node (ref "LED2304") (pin "C") (pinfunction "C_C") (pintype "passive"))
      (node (ref "T2304") (pin "3") (pinfunction "D_3") (pintype "passive"))
    )
    (net (code "215") (name "Net-(T2304-G)") (class "Default")
      (node (ref "R2306") (pin "1") (pinfunction "1_1") (pintype "passive"))
      (node (ref "T2304") (pin "1") (pinfunction "G_1") (pintype "passive"))
    )
    (net (code "216") (name "Net-(T2305-D)") (class "Default")
      (node (ref "LED2305") (pin "C") (pinfunction "C_C") (pintype "passive"))
      (node (ref "T2305") (pin "3") (pinfunction "D_3") (pintype "passive"))
    )
    (net (code "217") (name "Net-(T2305-G)") (class "Default")
      (node (ref "R2309") (pin "1") (pinfunction "1_1") (pintype "passive"))
      (node (ref "T2305") (pin "1") (pinfunction "G_1") (pintype "passive"))
    )
    (net (code "218") (name "Net-(T2306-D)") (class "Default")
      (node (ref "LED2306") (pin "C") (pinfunction "C_C") (pintype "passive"))
      (node (ref "T2306") (pin "3") (pinfunction "D_3") (pintype "passive"))
    )
    (net (code "219") (name "Net-(T2306-G)") (class "Default")
      (node (ref "R2310") (pin "1") (pinfunction "1_1") (pintype "passive"))
      (node (ref "T2306") (pin "1") (pinfunction "G_1") (pintype "passive"))
    )
    (net (code "220") (name "Net-(T2307-D)") (class "Default")
      (node (ref "LED2307") (pin "C") (pinfunction "C_C") (pintype "passive"))
      (node (ref "T2307") (pin "3") (pinfunction "D_3") (pintype "passive"))
    )
    (net (code "221") (name "Net-(T2307-G)") (class "Default")
      (node (ref "R2313") (pin "1") (pinfunction "1_1") (pintype "passive"))
      (node (ref "T2307") (pin "1") (pinfunction "G_1") (pintype "passive"))
    )
    (net (code "222") (name "Net-(T2308-D)") (class "Default")
      (node (ref "LED2308") (pin "C") (pinfunction "C_C") (pintype "passive"))
      (node (ref "T2308") (pin "3") (pinfunction "D_3") (pintype "passive"))
    )
    (net (code "223") (name "Net-(T2308-G)") (class "Default")
      (node (ref "R2314") (pin "1") (pinfunction "1_1") (pintype "passive"))
      (node (ref "T2308") (pin "1") (pinfunction "G_1") (pintype "passive"))
    )
    (net (code "224") (name "Net-(T2401-D)") (class "Default")
      (node (ref "R2401") (pin "1") (pinfunction "1_1") (pintype "passive"))
      (node (ref "T2401") (pin "3") (pinfunction "D_3") (pintype "passive"))
      (node (ref "T2404") (pin "1") (pinfunction "G_1") (pintype "passive"))
    )
    (net (code "225") (name "Net-(T2402-D)") (class "Default")
      (node (ref "R2402") (pin "1") (pinfunction "1_1") (pintype "passive"))
      (node (ref "T2402") (pin "3") (pinfunction "D_3") (pintype "passive"))
      (node (ref "T2405") (pin "1") (pinfunction "G_1") (pintype "passive"))
    )
    (net (code "226") (name "Net-(T2403-D)") (class "Default")
      (node (ref "R2403") (pin "1") (pinfunction "1_1") (pintype "passive"))
      (node (ref "T2403") (pin "3") (pinfunction "D_3") (pintype "passive"))
      (node (ref "T2406") (pin "1") (pinfunction "G_1") (pintype "passive"))
    )
    (net (code "227") (name "Net-(T2407-D)") (class "Default")
      (node (ref "R2407") (pin "2") (pinfunction "2_2") (pintype "passive"))
      (node (ref "T2407") (pin "3") (pinfunction "D_3") (pintype "passive"))
      (node (ref "T2408") (pin "1") (pinfunction "G_1") (pintype "passive"))
    )
    (net (code "228") (name "Net-(T2407-G)") (class "Default")
      (node (ref "D2401") (pin "C") (pinfunction "C_C") (pintype "passive"))
      (node (ref "D2402") (pin "C") (pinfunction "C_C") (pintype "passive"))
      (node (ref "D2403") (pin "C") (pinfunction "C_C") (pintype "passive"))
      (node (ref "R2405") (pin "1") (pinfunction "1_1") (pintype "passive"))
      (node (ref "T2407") (pin "1") (pinfunction "G_1") (pintype "passive"))
    )
    (net (code "229") (name "Net-(T2408-D)") (class "Default")
      (node (ref "LED2403") (pin "C") (pinfunction "C_C") (pintype "passive"))
      (node (ref "T2408") (pin "3") (pinfunction "D_3") (pintype "passive"))
    )
    (net (code "230") (name "Net-(T2501-D)") (class "Default")
      (node (ref "R2501") (pin "1") (pinfunction "1_1") (pintype "passive"))
      (node (ref "T2501") (pin "3") (pinfunction "D_3") (pintype "passive"))
      (node (ref "T2504") (pin "1") (pinfunction "G_1") (pintype "passive"))
    )
    (net (code "231") (name "Net-(T2502-D)") (class "Default")
      (node (ref "R2502") (pin "1") (pinfunction "1_1") (pintype "passive"))
      (node (ref "T2502") (pin "3") (pinfunction "D_3") (pintype "passive"))
      (node (ref "T2505") (pin "1") (pinfunction "G_1") (pintype "passive"))
    )
    (net (code "232") (name "Net-(T2503-D)") (class "Default")
      (node (ref "R2503") (pin "1") (pinfunction "1_1") (pintype "passive"))
      (node (ref "T2503") (pin "3") (pinfunction "D_3") (pintype "passive"))
      (node (ref "T2506") (pin "1") (pinfunction "G_1") (pintype "passive"))
    )
    (net (code "233") (name "Net-(T2507-D)") (class "Default")
      (node (ref "R2507") (pin "2") (pinfunction "2_2") (pintype "passive"))
      (node (ref "T2507") (pin "3") (pinfunction "D_3") (pintype "passive"))
      (node (ref "T2508") (pin "1") (pinfunction "G_1") (pintype "passive"))
    )
    (net (code "234") (name "Net-(T2507-G)") (class "Default")
      (node (ref "D2501") (pin "C") (pinfunction "C_C") (pintype "passive"))
      (node (ref "D2502") (pin "C") (pinfunction "C_C") (pintype "passive"))
      (node (ref "D2503") (pin "C") (pinfunction "C_C") (pintype "passive"))
      (node (ref "R2505") (pin "1") (pinfunction "1_1") (pintype "passive"))
      (node (ref "T2507") (pin "1") (pinfunction "G_1") (pintype "passive"))
    )
    (net (code "235") (name "Net-(T2508-D)") (class "Default")
      (node (ref "LED2504") (pin "C") (pinfunction "C_C") (pintype "passive"))
      (node (ref "T2508") (pin "3") (pinfunction "D_3") (pintype "passive"))
    )
    (net (code "236") (name "OBI_1") (class "Default")
      (node (ref "IC1201") (pin "139") (pinfunction "B2_FB1_MC13_139") (pintype "bidirectional"))
      (node (ref "IC801") (pin "36") (pinfunction "IO_L23P_6_36") (pintype "bidirectional"))
    )
    (net (code "237") (name "OBI_2") (class "Default")
      (node (ref "IC1201") (pin "52") (pinfunction "B1_FB12_MC2_52") (pintype "bidirectional"))
      (node (ref "IC801") (pin "4") (pinfunction "IO_L16P_7/VREF_7_4") (pintype "bidirectional"))
      (node (ref "TP1904") (pin "1") (pinfunction "TP_1") (pintype "passive"))
    )
    (net (code "238") (name "OBI_3") (class "Default")
      (node (ref "IC1201") (pin "51") (pinfunction "B1_FB12_MC1_51") (pintype "bidirectional"))
      (node (ref "IC801") (pin "10") (pinfunction "IO_L20P_7_10") (pintype "bidirectional"))
      (node (ref "TP1903") (pin "1") (pinfunction "TP_1") (pintype "passive"))
    )
    (net (code "239") (name "OBI_4") (class "Default")
      (node (ref "IC1201") (pin "45") (pinfunction "B1_FB10_MC2_45") (pintype "bidirectional"))
      (node (ref "IC801") (pin "11") (pinfunction "IO_L20N_7_11") (pintype "bidirectional"))
      (node (ref "TP1902") (pin "1") (pinfunction "TP_1") (pintype "passive"))
    )
    (net (code "240") (name "OBI_5") (class "Default")
      (node (ref "IC1201") (pin "43") (pinfunction "B1_FB8_MC16_43") (pintype "bidirectional"))
      (node (ref "IC801") (pin "12") (pinfunction "IO_L21P_7_12") (pintype "bidirectional"))
      (node (ref "TP1901") (pin "1") (pinfunction "TP_1") (pintype "passive"))
    )
    (net (code "241") (name "OBI_6") (class "Default")
      (node (ref "IC1201") (pin "140") (pinfunction "B2_FB1_MC12_140") (pintype "bidirectional"))
      (node (ref "IC801") (pin "29") (pinfunction "IO_L40N_6_29") (pintype "bidirectional"))
    )
    (net (code "242") (name "OBI_7") (class "Default")
      (node (ref "IC1201") (pin "22") (pinfunction "B1_FB11_MC3_22") (pintype "bidirectional"))
      (node (ref "IC601") (pin "21") (pinfunction "D7_21") (pintype "bidirectional"))
      (node (ref "IC801") (pin "50") (pinfunction "IO/VREF_6_50") (pintype "bidirectional"))
    )
    (net (code "243") (name "OBI_8") (class "Default")
      (node (ref "IC1201") (pin "21") (pinfunction "B1_FB11_MC4_21") (pintype "bidirectional"))
      (node (ref "IC601") (pin "20") (pinfunction "D6_20") (pintype "bidirectional"))
      (node (ref "IC801") (pin "48") (pinfunction "IO_L19N_6_48") (pintype "bidirectional"))
    )
    (net (code "244") (name "OBI_9") (class "Default")
      (node (ref "IC1201") (pin "20") (pinfunction "B1_FB11_MC5_20") (pintype "bidirectional"))
      (node (ref "IC601") (pin "19") (pinfunction "D5_19") (pintype "bidirectional"))
      (node (ref "IC801") (pin "46") (pinfunction "IO_L19P_6_46") (pintype "bidirectional"))
    )
    (net (code "245") (name "OBI_10") (class "Default")
      (node (ref "IC1201") (pin "19") (pinfunction "B1_FB11_MC12_19") (pintype "bidirectional"))
      (node (ref "IC601") (pin "18") (pinfunction "D4_18") (pintype "bidirectional"))
      (node (ref "IC801") (pin "45") (pinfunction "IO_L20N_6_45") (pintype "bidirectional"))
    )
    (net (code "246") (name "P1V2") (class "Default")
      (node (ref "C1117") (pin "1") (pinfunction "1_1") (pintype "passive"))
      (node (ref "C1118") (pin "1") (pinfunction "1_1") (pintype "passive"))
      (node (ref "C1119") (pin "1") (pinfunction "1_1") (pintype "passive"))
      (node (ref "C1120") (pin "1") (pinfunction "1_1") (pintype "passive"))
      (node (ref "IC801") (pin "174") (pinfunction "VCCINT_174") (pintype "input"))
      (node (ref "IC801") (pin "192") (pinfunction "VCCINT_192") (pintype "input"))
      (node (ref "IC801") (pin "70") (pinfunction "VCCINT_70") (pintype "input"))
      (node (ref "IC801") (pin "88") (pinfunction "VCCINT_88") (pintype "input"))
      (node (ref "J201") (pin "2") (pinfunction "2_2") (pintype "passive"))
    )
    (net (code "247") (name "P1V8") (class "Default")
      (node (ref "C1603") (pin "1") (pinfunction "1_1") (pintype "passive"))
      (node (ref "C1606") (pin "1") (pinfunction "1_1") (pintype "passive"))
      (node (ref "C1609") (pin "1") (pinfunction "1_1") (pintype "passive"))
      (node (ref "IC1201") (pin "1") (pinfunction "VCC_1") (pintype "power_in"))
      (node (ref "IC1201") (pin "37") (pinfunction "VCC_37") (pintype "power_in"))
      (node (ref "IC1201") (pin "84") (pinfunction "VCC_84") (pintype "power_in"))
      (node (ref "J204") (pin "2") (pinfunction "2_2") (pintype "passive"))
    )
    (net (code "248") (name "P2V5") (class "Default")
      (node (ref "C1114") (pin "1") (pinfunction "1_1") (pintype "passive"))
      (node (ref "C802") (pin "1") (pinfunction "1_1") (pintype "passive"))
      (node (ref "C803") (pin "1") (pinfunction "1_1") (pintype "passive"))
      (node (ref "C804") (pin "1") (pinfunction "1_1") (pintype "passive"))
      (node (ref "C805") (pin "1") (pinfunction "1_1") (pintype "passive"))
      (node (ref "C806") (pin "1") (pinfunction "1_1") (pintype "passive"))
      (node (ref "C807") (pin "1") (pinfunction "1_1") (pintype "passive"))
      (node (ref "C808") (pin "1") (pinfunction "1_1") (pintype "passive"))
      (node (ref "C809") (pin "1") (pinfunction "1_1") (pintype "passive"))
      (node (ref "C810") (pin "1") (pinfunction "1_1") (pintype "passive"))
      (node (ref "C811") (pin "1") (pinfunction "1_1") (pintype "passive"))
      (node (ref "IC801") (pin "121") (pinfunction "VCCAUX_121") (pintype "input"))
      (node (ref "IC801") (pin "142") (pinfunction "VCCAUX_142") (pintype "input"))
      (node (ref "IC801") (pin "17") (pinfunction "VCCAUX_17") (pintype "input"))
      (node (ref "IC801") (pin "173") (pinfunction "VCCAUX_173") (pintype "input"))
      (node (ref "IC801") (pin "193") (pinfunction "VCCAUX_193") (pintype "input"))
      (node (ref "IC801") (pin "38") (pinfunction "VCCAUX_38") (pintype "input"))
      (node (ref "IC801") (pin "69") (pinfunction "VCCAUX_69") (pintype "input"))
      (node (ref "IC801") (pin "84") (pinfunction "VCCO_4_84") (pintype "input"))
      (node (ref "IC801") (pin "89") (pinfunction "VCCAUX_89") (pintype "input"))
      (node (ref "IC801") (pin "98") (pinfunction "VCCO_4_98") (pintype "input"))
      (node (ref "IC802") (pin "19") (pinfunction "VCCO_19") (pintype "power_in"))
      (node (ref "IC802") (pin "20") (pinfunction "VCCJ_20") (pintype "power_in"))
      (node (ref "J202") (pin "2") (pinfunction "2_2") (pintype "passive"))
      (node (ref "J501") (pin "1") (pinfunction "1_1") (pintype "passive"))
      (node (ref "J801") (pin "10") (pinfunction "10_10") (pintype "passive"))
      (node (ref "J801") (pin "6") (pinfunction "6_6") (pintype "passive"))
      (node (ref "J801") (pin "8") (pinfunction "8_8") (pintype "passive"))
      (node (ref "R801") (pin "2") (pinfunction "2_2") (pintype "passive"))
      (node (ref "R802") (pin "2") (pinfunction "2_2") (pintype "passive"))
      (node (ref "R803") (pin "2") (pinfunction "2_2") (pintype "passive"))
      (node (ref "R804") (pin "2") (pinfunction "2_2") (pintype "passive"))
    )
    (net (code "249") (name "P3V3") (class "Default")
      (node (ref "C1101") (pin "1") (pinfunction "1_1") (pintype "passive"))
      (node (ref "C1102") (pin "1") (pinfunction "1_1") (pintype "passive"))
      (node (ref "C1103") (pin "1") (pinfunction "1_1") (pintype "passive"))
      (node (ref "C1104") (pin "1") (pinfunction "1_1") (pintype "passive"))
      (node (ref "C1105") (pin "1") (pinfunction "1_1") (pintype "passive"))
      (node (ref "C1106") (pin "1") (pinfunction "1_1") (pintype "passive"))
      (node (ref "C1107") (pin "1") (pinfunction "1_1") (pintype "passive"))
      (node (ref "C1108") (pin "1") (pinfunction "1_1") (pintype "passive"))
      (node (ref "C1109") (pin "1") (pinfunction "1_1") (pintype "passive"))
      (node (ref "C1110") (pin "1") (pinfunction "1_1") (pintype "passive"))
      (node (ref "C1111") (pin "1") (pinfunction "1_1") (pintype "passive"))
      (node (ref "C1112") (pin "1") (pinfunction "1_1") (pintype "passive"))
      (node (ref "C1113") (pin "1") (pinfunction "1_1") (pintype "passive"))
      (node (ref "C1115") (pin "1") (pinfunction "1_1") (pintype "passive"))
      (node (ref "C1116") (pin "1") (pinfunction "1_1") (pintype "passive"))
      (node (ref "C1401") (pin "2") (pinfunction "2_2") (pintype "passive"))
      (node (ref "C1602") (pin "1") (pinfunction "1_1") (pintype "passive"))
      (node (ref "C1605") (pin "1") (pinfunction "1_1") (pintype "passive"))
      (node (ref "C1608") (pin "1") (pinfunction "1_1") (pintype "passive"))
      (node (ref "C1611") (pin "1") (pinfunction "1_1") (pintype "passive"))
      (node (ref "C1801") (pin "2") (pinfunction "2_2") (pintype "passive"))
      (node (ref "C1802") (pin "2") (pinfunction "2_2") (pintype "passive"))
      (node (ref "C1803") (pin "1") (pinfunction "1_1") (pintype "passive"))
      (node (ref "C2002") (pin "1") (pinfunction "1_1") (pintype "passive"))
      (node (ref "C403") (pin "1") (pinfunction "1_1") (pintype "passive"))
      (node (ref "C601") (pin "1") (pinfunction "1_1") (pintype "passive"))
      (node (ref "C602") (pin "1") (pinfunction "1_1") (pintype "passive"))
      (node (ref "C603") (pin "1") (pinfunction "1_1") (pintype "passive"))
      (node (ref "C701") (pin "1") (pinfunction "1_1") (pintype "passive"))
      (node (ref "C702") (pin "1") (pinfunction "1_1") (pintype "passive"))
      (node (ref "C801") (pin "1") (pinfunction "1_1") (pintype "passive"))
      (node (ref "D1401") (pin "2") (pinfunction "K1_2") (pintype "passive"))
      (node (ref "D1402") (pin "2") (pinfunction "K1_2") (pintype "passive"))
      (node (ref "D401") (pin "C") (pinfunction "C_C") (pintype "passive"))
      (node (ref "IC1101") (pin "4") (pinfunction "VCC_4") (pintype "power_in"))
      (node (ref "IC1201") (pin "141") (pinfunction "VCC_IO_141") (pintype "power_in"))
      (node (ref "IC1201") (pin "27") (pinfunction "VCC_IO_27") (pintype "power_in"))
      (node (ref "IC1201") (pin "55") (pinfunction "VCC_IO_55") (pintype "power_in"))
      (node (ref "IC1201") (pin "8") (pinfunction "VAUX_8") (pintype "power_in"))
      (node (ref "IC1301") (pin "8") (pinfunction "VREF0_8") (pintype "input"))
      (node (ref "IC1302") (pin "8") (pinfunction "VREF0_8") (pintype "input"))
      (node (ref "IC1401") (pin "8") (pinfunction "V+_8") (pintype "power_in"))
      (node (ref "IC1801") (pin "14") (pinfunction "VCC_14") (pintype "power_in"))
      (node (ref "IC2001") (pin "14") (pinfunction "VCC_14") (pintype "power_in"))
      (node (ref "IC401") (pin "14") (pinfunction "VCC_14") (pintype "power_in"))
      (node (ref "IC601") (pin "32") (pinfunction "VCC_32") (pintype "power_in"))
      (node (ref "IC602") (pin "32") (pinfunction "VCC_32") (pintype "power_in"))
      (node (ref "IC603") (pin "32") (pinfunction "VCC_32") (pintype "power_in"))
      (node (ref "IC701") (pin "32") (pinfunction "VCC_32") (pintype "power_in"))
      (node (ref "IC702") (pin "8") (pinfunction "VCC_8") (pintype "power_in"))
      (node (ref "IC801") (pin "110") (pinfunction "VCCO_3_110") (pintype "input"))
      (node (ref "IC801") (pin "127") (pinfunction "VCCO_3_127") (pintype "input"))
      (node (ref "IC801") (pin "136") (pinfunction "VCCO_2_136") (pintype "input"))
      (node (ref "IC801") (pin "153") (pinfunction "VCCO_2_153") (pintype "input"))
      (node (ref "IC801") (pin "164") (pinfunction "VCCO_1_164") (pintype "input"))
      (node (ref "IC801") (pin "177") (pinfunction "VCCO_1_177") (pintype "input"))
      (node (ref "IC801") (pin "188") (pinfunction "VCCO_0_188") (pintype "input"))
      (node (ref "IC801") (pin "201") (pinfunction "VCCO_0_201") (pintype "input"))
      (node (ref "IC801") (pin "23") (pinfunction "VCCO_7_23") (pintype "input"))
      (node (ref "IC801") (pin "32") (pinfunction "VCCO_6_32") (pintype "input"))
      (node (ref "IC801") (pin "49") (pinfunction "VCCO_6_49") (pintype "input"))
      (node (ref "IC801") (pin "6") (pinfunction "VCCO_7_6") (pintype "input"))
      (node (ref "IC801") (pin "60") (pinfunction "VCCO_5_60") (pintype "input"))
      (node (ref "IC801") (pin "73") (pinfunction "VCCO_5_73") (pintype "input"))
      (node (ref "IC802") (pin "18") (pinfunction "VCCINIT_18") (pintype "power_in"))
      (node (ref "J1201") (pin "1") (pinfunction "1_1") (pintype "passive"))
      (node (ref "J1901") (pin "1") (pinfunction "1_1") (pintype "passive"))
      (node (ref "J1903") (pin "2") (pinfunction "2_2") (pintype "passive"))
      (node (ref "J205") (pin "2") (pinfunction "2_2") (pintype "passive"))
      (node (ref "LED1701") (pin "A") (pinfunction "A_A") (pintype "passive"))
      (node (ref "LED1702") (pin "A") (pinfunction "A_A") (pintype "passive"))
      (node (ref "LED1703") (pin "A") (pinfunction "A_A") (pintype "passive"))
      (node (ref "LED1704") (pin "A") (pinfunction "A_A") (pintype "passive"))
      (node (ref "LED1705") (pin "A") (pinfunction "A_A") (pintype "passive"))
      (node (ref "LED1706") (pin "A") (pinfunction "A_A") (pintype "passive"))
      (node (ref "LED1707") (pin "A") (pinfunction "A_A") (pintype "passive"))
      (node (ref "LED1708") (pin "A") (pinfunction "A_A") (pintype "passive"))
      (node (ref "LED1901") (pin "A") (pinfunction "A_A") (pintype "passive"))
      (node (ref "LED1902") (pin "A") (pinfunction "A_A") (pintype "passive"))
      (node (ref "R1301") (pin "2") (pinfunction "2_2") (pintype "passive"))
      (node (ref "R1302") (pin "2") (pinfunction "2_2") (pintype "passive"))
      (node (ref "R1401") (pin "2") (pinfunction "2_2") (pintype "passive"))
      (node (ref "R1403") (pin "2") (pinfunction "2_2") (pintype "passive"))
      (node (ref "R2103") (pin "1") (pinfunction "1_1") (pintype "passive"))
      (node (ref "R2104") (pin "1") (pinfunction "1_1") (pintype "passive"))
      (node (ref "R2107") (pin "2") (pinfunction "2_2") (pintype "passive"))
      (node (ref "R2108") (pin "2") (pinfunction "2_2") (pintype "passive"))
      (node (ref "R2111") (pin "1") (pinfunction "1_1") (pintype "passive"))
      (node (ref "R2112") (pin "1") (pinfunction "1_1") (pintype "passive"))
      (node (ref "R2115") (pin "1") (pinfunction "1_1") (pintype "passive"))
      (node (ref "R2116") (pin "1") (pinfunction "1_1") (pintype "passive"))
      (node (ref "R2119") (pin "1") (pinfunction "1_1") (pintype "passive"))
      (node (ref "R2120") (pin "1") (pinfunction "1_1") (pintype "passive"))
      (node (ref "R2203") (pin "1") (pinfunction "1_1") (pintype "passive"))
      (node (ref "R2204") (pin "1") (pinfunction "1_1") (pintype "passive"))
      (node (ref "R2205") (pin "1") (pinfunction "1_1") (pintype "passive"))
      (node (ref "R2206") (pin "1") (pinfunction "1_1") (pintype "passive"))
      (node (ref "R2303") (pin "1") (pinfunction "1_1") (pintype "passive"))
      (node (ref "R2304") (pin "1") (pinfunction "1_1") (pintype "passive"))
      (node (ref "R2307") (pin "1") (pinfunction "1_1") (pintype "passive"))
      (node (ref "R2308") (pin "1") (pinfunction "1_1") (pintype "passive"))
      (node (ref "R2311") (pin "1") (pinfunction "1_1") (pintype "passive"))
      (node (ref "R2312") (pin "1") (pinfunction "1_1") (pintype "passive"))
      (node (ref "R2315") (pin "1") (pinfunction "1_1") (pintype "passive"))
      (node (ref "R2316") (pin "1") (pinfunction "1_1") (pintype "passive"))
      (node (ref "R2407") (pin "1") (pinfunction "1_1") (pintype "passive"))
      (node (ref "R2408") (pin "1") (pinfunction "1_1") (pintype "passive"))
      (node (ref "R2507") (pin "1") (pinfunction "1_1") (pintype "passive"))
      (node (ref "R2509") (pin "1") (pinfunction "1_1") (pintype "passive"))
      (node (ref "R401") (pin "1") (pinfunction "1_1") (pintype "passive"))
      (node (ref "R402") (pin "1") (pinfunction "1_1") (pintype "passive"))
      (node (ref "R404") (pin "2") (pinfunction "2_2") (pintype "passive"))
      (node (ref "R406") (pin "2") (pinfunction "2_2") (pintype "passive"))
      (node (ref "R407") (pin "2") (pinfunction "2_2") (pintype "passive"))
      (node (ref "R701") (pin "2") (pinfunction "2_2") (pintype "passive"))
      (node (ref "R702") (pin "2") (pinfunction "2_2") (pintype "passive"))
      (node (ref "R703") (pin "2") (pinfunction "2_2") (pintype "passive"))
      (node (ref "R704") (pin "2") (pinfunction "2_2") (pintype "passive"))
      (node (ref "RN301") (pin "6") (pinfunction "2_6") (pintype "passive"))
      (node (ref "RN301") (pin "7") (pinfunction "2_7") (pintype "passive"))
      (node (ref "RN301") (pin "8") (pinfunction "2_8") (pintype "passive"))
      (node (ref "RN302") (pin "6") (pinfunction "2_6") (pintype "passive"))
      (node (ref "RN302") (pin "7") (pinfunction "2_7") (pintype "passive"))
      (node (ref "RN302") (pin "8") (pinfunction "2_8") (pintype "passive"))
      (node (ref "S1801") (pin "1") (pinfunction "A1_1") (pintype "passive"))
      (node (ref "S1801") (pin "3") (pinfunction "A1_3") (pintype "passive"))
      (node (ref "S1802") (pin "1") (pinfunction "A1_1") (pintype "passive"))
      (node (ref "S1802") (pin "3") (pinfunction "A1_3") (pintype "passive"))
      (node (ref "T2401") (pin "2") (pinfunction "S_2") (pintype "passive"))
      (node (ref "T2402") (pin "2") (pinfunction "S_2") (pintype "passive"))
      (node (ref "T2403") (pin "2") (pinfunction "S_2") (pintype "passive"))
      (node (ref "T2404") (pin "2") (pinfunction "S_2") (pintype "passive"))
      (node (ref "T2405") (pin "2") (pinfunction "S_2") (pintype "passive"))
      (node (ref "T2406") (pin "2") (pinfunction "S_2") (pintype "passive"))
      (node (ref "T2501") (pin "2") (pinfunction "S_2") (pintype "passive"))
      (node (ref "T2502") (pin "2") (pinfunction "S_2") (pintype "passive"))
      (node (ref "T2503") (pin "2") (pinfunction "S_2") (pintype "passive"))
      (node (ref "T2504") (pin "2") (pinfunction "S_2") (pintype "passive"))
      (node (ref "T2505") (pin "2") (pinfunction "S_2") (pintype "passive"))
      (node (ref "T2506") (pin "2") (pinfunction "S_2") (pintype "passive"))
    )
    (net (code "250") (name "P5V") (class "Default")
      (node (ref "C1301") (pin "1") (pinfunction "1_1") (pintype "passive"))
      (node (ref "C1302") (pin "1") (pinfunction "1_1") (pintype "passive"))
      (node (ref "IC1301") (pin "7") (pinfunction "VCC_7") (pintype "power_in"))
      (node (ref "IC1302") (pin "6") (pinfunction "A0_6") (pintype "input"))
      (node (ref "IC1302") (pin "7") (pinfunction "VCC_7") (pintype "power_in"))
      (node (ref "J203") (pin "2") (pinfunction "2_2") (pintype "passive"))
    )
    (net (code "251") (name "PWR_IN_PROT") (class "Default")
      (node (ref "C101") (pin "+") (pinfunction "+_+") (pintype "passive"))
      (node (ref "C201") (pin "1") (pinfunction "1_1") (pintype "passive"))
      (node (ref "C202") (pin "1") (pinfunction "1_1") (pintype "passive"))
      (node (ref "C203") (pin "1") (pinfunction "1_1") (pintype "passive"))
      (node (ref "C207") (pin "1") (pinfunction "1_1") (pintype "passive"))
      (node (ref "C208") (pin "1") (pinfunction "1_1") (pintype "passive"))
      (node (ref "C301") (pin "1") (pinfunction "1_1") (pintype "passive"))
      (node (ref "C303") (pin "1") (pinfunction "1_1") (pintype "passive"))
      (node (ref "D101") (pin "C") (pinfunction "C_C") (pintype "passive"))
      (node (ref "IC201") (pin "3") (pinfunction "IN_3") (pintype "power_in"))
      (node (ref "IC202") (pin "3") (pinfunction "IN_3") (pintype "power_in"))
      (node (ref "IC203") (pin "3") (pinfunction "IN_3") (pintype "power_in"))
      (node (ref "IC204") (pin "3") (pinfunction "IN_3") (pintype "power_in"))
      (node (ref "IC205") (pin "3") (pinfunction "IN_3") (pintype "power_in"))
      (node (ref "IC301") (pin "3") (pinfunction "IN_3") (pintype "power_in"))
      (node (ref "IC302") (pin "3") (pinfunction "IN_3") (pintype "power_in"))
    )
    (net (code "252") (name "RAM_IN_CS_N") (class "Default")
      (node (ref "IC601") (pin "22") (pinfunction "CE_22") (pintype "input"))
      (node (ref "IC801") (pin "117") (pinfunction "IO_L21N_3_117") (pintype "bidirectional"))
      (node (ref "R701") (pin "1") (pinfunction "1_1") (pintype "passive"))
    )
    (net (code "253") (name "RAM_OE_N") (class "Default")
      (node (ref "IC601") (pin "24") (pinfunction "OE_24") (pintype "input"))
      (node (ref "IC602") (pin "24") (pinfunction "OE_24") (pintype "input"))
      (node (ref "IC603") (pin "24") (pinfunction "OE_24") (pintype "input"))
      (node (ref "IC701") (pin "24") (pinfunction "OE_24") (pintype "input"))
      (node (ref "IC801") (pin "120") (pinfunction "IO_L22N_3_120") (pintype "bidirectional"))
    )
    (net (code "254") (name "RAM_OUT_CS_1_N") (class "Default")
      (node (ref "IC602") (pin "22") (pinfunction "CE_22") (pintype "input"))
      (node (ref "IC801") (pin "116") (pinfunction "IO_L21P_3_116") (pintype "bidirectional"))
      (node (ref "R702") (pin "1") (pinfunction "1_1") (pintype "passive"))
    )
    (net (code "255") (name "RAM_OUT_CS_2_N") (class "Default")
      (node (ref "IC603") (pin "22") (pinfunction "CE_22") (pintype "input"))
      (node (ref "IC801") (pin "147") (pinfunction "IO_L21N_2_147") (pintype "bidirectional"))
      (node (ref "R703") (pin "1") (pinfunction "1_1") (pintype "passive"))
    )
    (net (code "256") (name "RAM_WE_N") (class "Default")
      (node (ref "IC601") (pin "29") (pinfunction "WE_29") (pintype "input"))
      (node (ref "IC602") (pin "29") (pinfunction "WE_29") (pintype "input"))
      (node (ref "IC603") (pin "29") (pinfunction "WE_29") (pintype "input"))
      (node (ref "IC701") (pin "31") (pinfunction "WE_31") (pintype "input"))
      (node (ref "IC801") (pin "119") (pinfunction "IO_L22P_3_119") (pintype "bidirectional"))
      (node (ref "X1702") (pin "34") (pinfunction "34_34") (pintype "passive"))
    )
    (net (code "257") (name "RESET_SWITCH_N") (class "Default")
      (node (ref "R405") (pin "2") (pinfunction "2_2") (pintype "passive"))
      (node (ref "S401") (pin "1") (pinfunction "A1_1") (pintype "passive"))
      (node (ref "S401") (pin "3") (pinfunction "A1_3") (pintype "passive"))
      (node (ref "X1701") (pin "40") (pinfunction "40_40") (pintype "passive"))
    )
    (net (code "258") (name "ROM_CS_N") (class "Default")
      (node (ref "IC701") (pin "22") (pinfunction "CE_22") (pintype "input"))
      (node (ref "IC801") (pin "148") (pinfunction "IO_L20P_2_148") (pintype "bidirectional"))
      (node (ref "R704") (pin "1") (pinfunction "1_1") (pintype "passive"))
    )
    (net (code "259") (name "SP_1_DIO_1_ADJ") (class "Default")
      (node (ref "IC1201") (pin "102") (pinfunction "B4_FB16_MC3_102") (pintype "bidirectional"))
      (node (ref "R2301") (pin "2") (pinfunction "2_2") (pintype "passive"))
      (node (ref "X104") (pin "11") (pinfunction "11_11") (pintype "passive"))
    )
    (net (code "260") (name "SP_1_DIO_1_P3V3") (class "Default")
      (node (ref "IC1201") (pin "135") (pinfunction "B2_FB3_MC12_135") (pintype "bidirectional"))
      (node (ref "R2309") (pin "2") (pinfunction "2_2") (pintype "passive"))
      (node (ref "X104") (pin "15") (pinfunction "15_15") (pintype "passive"))
    )
    (net (code "261") (name "SP_1_DIO_2_ADJ") (class "Default")
      (node (ref "IC1201") (pin "105") (pinfunction "B4_FB14_MC5_105") (pintype "bidirectional"))
      (node (ref "R2305") (pin "2") (pinfunction "2_2") (pintype "passive"))
      (node (ref "X104") (pin "13") (pinfunction "13_13") (pintype "passive"))
    )
    (net (code "262") (name "SP_1_DIO_2_P3V3") (class "Default")
      (node (ref "IC1201") (pin "136") (pinfunction "B2_FB3_MC5_136") (pintype "bidirectional"))
      (node (ref "R2313") (pin "2") (pinfunction "2_2") (pintype "passive"))
      (node (ref "X104") (pin "17") (pinfunction "17_17") (pintype "passive"))
    )
    (net (code "263") (name "SP_1_FAIL_FPGA") (class "Default")
      (node (ref "IC601") (pin "14") (pinfunction "D1_14") (pintype "bidirectional"))
      (node (ref "IC801") (pin "63") (pinfunction "IO_63") (pintype "bidirectional"))
      (node (ref "R2117") (pin "2") (pinfunction "2_2") (pintype "passive"))
    )
    (net (code "264") (name "SP_1_TCK") (class "Default")
      (node (ref "IC1201") (pin "104") (pinfunction "B4_FB14_MC13_104") (pintype "bidirectional"))
      (node (ref "R2101") (pin "2") (pinfunction "2_2") (pintype "passive"))
      (node (ref "X104") (pin "1") (pinfunction "1_1") (pintype "passive"))
    )
    (net (code "265") (name "SP_1_TCK_FPGA") (class "Default")
      (node (ref "IC1201") (pin "9") (pinfunction "B2_FB4_MC1_9") (pintype "bidirectional"))
      (node (ref "IC801") (pin "76") (pinfunction "IO_L32P_5/GCLK2_76") (pintype "bidirectional"))
    )
    (net (code "266") (name "SP_1_TDI") (class "Default")
      (node (ref "D1401") (pin "3") (pinfunction "A1K2_3") (pintype "passive"))
      (node (ref "IC1401") (pin "3") (pinfunction "+IN_3") (pintype "input"))
      (node (ref "TP1401") (pin "1") (pinfunction "TP_1") (pintype "passive"))
      (node (ref "X104") (pin "5") (pinfunction "5_5") (pintype "passive"))
    )
    (net (code "267") (name "SP_1_TDI_COMP") (class "Default")
      (node (ref "IC1201") (pin "137") (pinfunction "B2_FB3_MC4_137") (pintype "bidirectional"))
      (node (ref "IC1401") (pin "6") (pinfunction "OUT_6") (pintype "output"))
      (node (ref "R2113") (pin "2") (pinfunction "2_2") (pintype "passive"))
      (node (ref "TP1405") (pin "1") (pinfunction "TP_1") (pintype "passive"))
    )
    (net (code "268") (name "SP_1_TDI_FPGA") (class "Default")
      (node (ref "IC1201") (pin "17") (pinfunction "B2_FB6_MC14_17") (pintype "bidirectional"))
      (node (ref "IC601") (pin "13") (pinfunction "D0_13") (pintype "bidirectional"))
      (node (ref "IC801") (pin "78") (pinfunction "IO/VREF_5_78") (pintype "bidirectional"))
    )
    (net (code "269") (name "SP_1_TDI_VREF") (class "Default")
      (node (ref "IC1301") (pin "1") (pinfunction "OUT0_1") (pintype "output"))
      (node (ref "IC1401") (pin "4") (pinfunction "-IN_4") (pintype "input"))
      (node (ref "R1401") (pin "1") (pinfunction "1_1") (pintype "passive"))
      (node (ref "R1402") (pin "2") (pinfunction "2_2") (pintype "passive"))
      (node (ref "TP1402") (pin "1") (pinfunction "TP_1") (pintype "passive"))
      (node (ref "X1701") (pin "2") (pinfunction "2_2") (pintype "passive"))
    )
    (net (code "270") (name "SP_1_TDO") (class "Default")
      (node (ref "IC1201") (pin "107") (pinfunction "B4_FB14_MC3_107") (pintype "bidirectional"))
      (node (ref "R2109") (pin "2") (pinfunction "2_2") (pintype "passive"))
      (node (ref "X104") (pin "7") (pinfunction "7_7") (pintype "passive"))
    )
    (net (code "271") (name "SP_1_TDO_FPGA") (class "Default")
      (node (ref "IC1201") (pin "11") (pinfunction "B2_FB4_MC3_11") (pintype "bidirectional"))
      (node (ref "IC801") (pin "68") (pinfunction "IO_L28N_5/D6_68") (pintype "bidirectional"))
    )
    (net (code "272") (name "SP_1_TMS") (class "Default")
      (node (ref "IC1201") (pin "103") (pinfunction "B4_FB16_MC1_103") (pintype "bidirectional"))
      (node (ref "R2105") (pin "2") (pinfunction "2_2") (pintype "passive"))
      (node (ref "X104") (pin "3") (pinfunction "3_3") (pintype "passive"))
    )
    (net (code "273") (name "SP_1_TMS_FPGA") (class "Default")
      (node (ref "IC1201") (pin "10") (pinfunction "B2_FB4_MC2_10") (pintype "bidirectional"))
      (node (ref "IC801") (pin "74") (pinfunction "IO_L31N_5/D4_74") (pintype "bidirectional"))
    )
    (net (code "274") (name "SP_1_TRST_FPGA") (class "Default")
      (node (ref "IC1201") (pin "12") (pinfunction "B2_FB4_MC4_12") (pintype "bidirectional"))
      (node (ref "IC801") (pin "65") (pinfunction "IO_L27N_5/VREF_5_65") (pintype "bidirectional"))
    )
    (net (code "275") (name "SP_1_TRST_N") (class "Default")
      (node (ref "IC1201") (pin "106") (pinfunction "B4_FB14_MC4_106") (pintype "bidirectional"))
      (node (ref "R2201") (pin "1") (pinfunction "1_1") (pintype "passive"))
      (node (ref "X104") (pin "9") (pinfunction "9_9") (pintype "passive"))
    )
    (net (code "276") (name "SP_1_VCC") (class "Default")
      (node (ref "C1601") (pin "1") (pinfunction "1_1") (pintype "passive"))
      (node (ref "C1604") (pin "1") (pinfunction "1_1") (pintype "passive"))
      (node (ref "IC1201") (pin "109") (pinfunction "VCC_IO_109") (pintype "power_in"))
      (node (ref "IC1201") (pin "127") (pinfunction "VCC_IO_127") (pintype "power_in"))
      (node (ref "J301") (pin "2") (pinfunction "2_2") (pintype "passive"))
    )
    (net (code "277") (name "SP_1_VCC_ADJ") (class "Default")
      (node (ref "IC301") (pin "1") (pinfunction "AJD_1") (pintype "passive"))
      (node (ref "R301") (pin "2") (pinfunction "2_2") (pintype "passive"))
      (node (ref "R302") (pin "2") (pinfunction "2_2") (pintype "passive"))
      (node (ref "R303") (pin "2") (pinfunction "2_2") (pintype "passive"))
      (node (ref "R304") (pin "1") (pinfunction "1_1") (pintype "passive"))
      (node (ref "R305") (pin "2") (pinfunction "2_2") (pintype "passive"))
    )
    (net (code "278") (name "SP_1_VCC_P1V5_SET") (class "Default")
      (node (ref "IC1201") (pin "134") (pinfunction "B2_FB3_MC16_134") (pintype "bidirectional"))
      (node (ref "RN301") (pin "3") (pinfunction "1_3") (pintype "passive"))
      (node (ref "T2401") (pin "1") (pinfunction "G_1") (pintype "passive"))
      (node (ref "T301") (pin "1") (pinfunction "G_1") (pintype "passive"))
    )
    (net (code "279") (name "SP_1_VCC_P1V5_SET_OR") (class "Default")
      (node (ref "D2403") (pin "A") (pinfunction "A_A") (pintype "passive"))
      (node (ref "R2404") (pin "2") (pinfunction "2_2") (pintype "passive"))
      (node (ref "T2404") (pin "3") (pinfunction "D_3") (pintype "passive"))
    )
    (net (code "280") (name "SP_1_VCC_P1V8_SET") (class "Default")
      (node (ref "IC1201") (pin "133") (pinfunction "B2_FB5_MC2_133") (pintype "bidirectional"))
      (node (ref "RN301") (pin "2") (pinfunction "1_2") (pintype "passive"))
      (node (ref "T2402") (pin "1") (pinfunction "G_1") (pintype "passive"))
      (node (ref "T302") (pin "1") (pinfunction "G_1") (pintype "passive"))
    )
    (net (code "281") (name "SP_1_VCC_P1V8_SET_OR") (class "Default")
      (node (ref "D2402") (pin "A") (pinfunction "A_A") (pintype "passive"))
      (node (ref "R2406") (pin "1") (pinfunction "1_1") (pintype "passive"))
      (node (ref "T2405") (pin "3") (pinfunction "D_3") (pintype "passive"))
    )
    (net (code "282") (name "SP_1_VCC_P2V5_SET") (class "Default")
      (node (ref "IC1201") (pin "132") (pinfunction "B2_FB5_MC3_132") (pintype "bidirectional"))
      (node (ref "RN301") (pin "1") (pinfunction "1_1") (pintype "passive"))
      (node (ref "T2403") (pin "1") (pinfunction "G_1") (pintype "passive"))
      (node (ref "T303") (pin "1") (pinfunction "G_1") (pintype "passive"))
    )
    (net (code "283") (name "SP_1_VCC_P2V5_SET_OR") (class "Default")
      (node (ref "D2401") (pin "A") (pinfunction "A_A") (pintype "passive"))
      (node (ref "R2409") (pin "1") (pinfunction "1_1") (pintype "passive"))
      (node (ref "T2406") (pin "3") (pinfunction "D_3") (pintype "passive"))
    )
    (net (code "284") (name "SP_2_DIO_1_ADJ") (class "Default")
      (node (ref "IC1201") (pin "87") (pinfunction "B3_FB23_MC5_87") (pintype "bidirectional"))
      (node (ref "R2302") (pin "2") (pinfunction "2_2") (pintype "passive"))
      (node (ref "X106") (pin "11") (pinfunction "11_11") (pintype "passive"))
    )
    (net (code "285") (name "SP_2_DIO_1_P3V3") (class "Default")
      (node (ref "IC1201") (pin "53") (pinfunction "B1_FB12_MC3_53") (pintype "bidirectional"))
      (node (ref "R2310") (pin "2") (pinfunction "2_2") (pintype "passive"))
      (node (ref "X106") (pin "15") (pinfunction "15_15") (pintype "passive"))
    )
    (net (code "286") (name "SP_2_DIO_2_ADJ") (class "Default")
      (node (ref "IC1201") (pin "85") (pinfunction "B3_FB23_MC3_85") (pintype "bidirectional"))
      (node (ref "R2306") (pin "2") (pinfunction "2_2") (pintype "passive"))
      (node (ref "X106") (pin "13") (pinfunction "13_13") (pintype "passive"))
    )
    (net (code "287") (name "SP_2_DIO_2_P3V3") (class "Default")
      (node (ref "IC1201") (pin "54") (pinfunction "B1_FB12_MC5_54") (pintype "bidirectional"))
      (node (ref "R2314") (pin "2") (pinfunction "2_2") (pintype "passive"))
      (node (ref "X106") (pin "17") (pinfunction "17_17") (pintype "passive"))
    )
    (net (code "288") (name "SP_2_FAIL_FPGA") (class "Default")
      (node (ref "IC601") (pin "17") (pinfunction "D3_17") (pintype "bidirectional"))
      (node (ref "IC801") (pin "62") (pinfunction "IO_L10N_5/VRP_5_62") (pintype "bidirectional"))
      (node (ref "R2118") (pin "2") (pinfunction "2_2") (pintype "passive"))
    )
    (net (code "289") (name "SP_2_TCK") (class "Default")
      (node (ref "IC1201") (pin "92") (pinfunction "B3_FB23_MC14_92") (pintype "bidirectional"))
      (node (ref "R2102") (pin "2") (pinfunction "2_2") (pintype "passive"))
      (node (ref "X106") (pin "1") (pinfunction "1_1") (pintype "passive"))
    )
    (net (code "290") (name "SP_2_TCK_FPGA") (class "Default")
      (node (ref "IC1201") (pin "13") (pinfunction "B2_FB6_MC2_13") (pintype "bidirectional"))
      (node (ref "IC801") (pin "77") (pinfunction "IO_L32N_5/GCLK3_77") (pintype "bidirectional"))
    )
    (net (code "291") (name "SP_2_TDI") (class "Default")
      (node (ref "D1402") (pin "3") (pinfunction "A1K2_3") (pintype "passive"))
      (node (ref "IC1401") (pin "1") (pinfunction "+IN_1") (pintype "input"))
      (node (ref "TP1403") (pin "1") (pinfunction "TP_1") (pintype "passive"))
      (node (ref "X106") (pin "5") (pinfunction "5_5") (pintype "passive"))
    )
    (net (code "292") (name "SP_2_TDI_COMP") (class "Default")
      (node (ref "IC1201") (pin "138") (pinfunction "B2_FB3_MC3_138") (pintype "bidirectional"))
      (node (ref "IC1401") (pin "7") (pinfunction "OUT_7") (pintype "output"))
      (node (ref "R2114") (pin "2") (pinfunction "2_2") (pintype "passive"))
      (node (ref "TP1406") (pin "1") (pinfunction "TP_1") (pintype "passive"))
    )
    (net (code "293") (name "SP_2_TDI_FPGA") (class "Default")
      (node (ref "IC1201") (pin "18") (pinfunction "B2_FB6_MC16_18") (pintype "bidirectional"))
      (node (ref "IC601") (pin "15") (pinfunction "D2_15") (pintype "bidirectional"))
      (node (ref "IC801") (pin "71") (pinfunction "IO_71") (pintype "bidirectional"))
    )
    (net (code "294") (name "SP_2_TDI_VREF") (class "Default")
      (node (ref "IC1302") (pin "1") (pinfunction "OUT0_1") (pintype "output"))
      (node (ref "IC1401") (pin "2") (pinfunction "-IN_2") (pintype "input"))
      (node (ref "R1403") (pin "1") (pinfunction "1_1") (pintype "passive"))
      (node (ref "R1404") (pin "2") (pinfunction "2_2") (pintype "passive"))
      (node (ref "TP1404") (pin "1") (pinfunction "TP_1") (pintype "passive"))
      (node (ref "X1701") (pin "4") (pinfunction "4_4") (pintype "passive"))
    )
    (net (code "295") (name "SP_2_TDO") (class "Default")
      (node (ref "IC1201") (pin "88") (pinfunction "B3_FB23_MC12_88") (pintype "bidirectional"))
      (node (ref "R2110") (pin "2") (pinfunction "2_2") (pintype "passive"))
      (node (ref "X106") (pin "7") (pinfunction "7_7") (pintype "passive"))
    )
    (net (code "296") (name "SP_2_TDO_FPGA") (class "Default")
      (node (ref "IC1201") (pin "15") (pinfunction "B2_FB6_MC4_15") (pintype "bidirectional"))
      (node (ref "IC801") (pin "67") (pinfunction "IO_L28P_5/D7_67") (pintype "bidirectional"))
    )
    (net (code "297") (name "SP_2_TMS") (class "Default")
      (node (ref "IC1201") (pin "91") (pinfunction "B3_FB23_MC13_91") (pintype "bidirectional"))
      (node (ref "R2106") (pin "2") (pinfunction "2_2") (pintype "passive"))
      (node (ref "X106") (pin "3") (pinfunction "3_3") (pintype "passive"))
    )
    (net (code "298") (name "SP_2_TMS_FPGA") (class "Default")
      (node (ref "IC1201") (pin "14") (pinfunction "B2_FB6_MC3_14") (pintype "bidirectional"))
      (node (ref "IC801") (pin "72") (pinfunction "IO_L31P_5/D5_72") (pintype "bidirectional"))
    )
    (net (code "299") (name "SP_2_TRST_FPGA") (class "Default")
      (node (ref "IC1201") (pin "16") (pinfunction "B2_FB6_MC13_16") (pintype "bidirectional"))
      (node (ref "IC801") (pin "64") (pinfunction "IO_L27P_5_64") (pintype "bidirectional"))
    )
    (net (code "300") (name "SP_2_TRST_N") (class "Default")
      (node (ref "IC1201") (pin "86") (pinfunction "B3_FB23_MC4_86") (pintype "bidirectional"))
      (node (ref "R2202") (pin "1") (pinfunction "1_1") (pintype "passive"))
      (node (ref "X106") (pin "9") (pinfunction "9_9") (pintype "passive"))
    )
    (net (code "301") (name "SP_2_VCC") (class "Default")
      (node (ref "C1607") (pin "1") (pinfunction "1_1") (pintype "passive"))
      (node (ref "C1610") (pin "1") (pinfunction "1_1") (pintype "passive"))
      (node (ref "IC1201") (pin "73") (pinfunction "VCC_IO_73") (pintype "power_in"))
      (node (ref "IC1201") (pin "93") (pinfunction "VCC_IO_93") (pintype "power_in"))
      (node (ref "J302") (pin "2") (pinfunction "2_2") (pintype "passive"))
    )
    (net (code "302") (name "SP_2_VCC_ADJ") (class "Default")
      (node (ref "IC302") (pin "1") (pinfunction "AJD_1") (pintype "passive"))
      (node (ref "R306") (pin "2") (pinfunction "2_2") (pintype "passive"))
      (node (ref "R307") (pin "2") (pinfunction "2_2") (pintype "passive"))
      (node (ref "R308") (pin "2") (pinfunction "2_2") (pintype "passive"))
      (node (ref "R309") (pin "2") (pinfunction "2_2") (pintype "passive"))
      (node (ref "R310") (pin "1") (pinfunction "1_1") (pintype "passive"))
    )
    (net (code "303") (name "SP_2_VCC_P1V5_SET") (class "Default")
      (node (ref "IC1201") (pin "131") (pinfunction "B2_FB5_MC13_131") (pintype "bidirectional"))
      (node (ref "RN302") (pin "3") (pinfunction "1_3") (pintype "passive"))
      (node (ref "T2501") (pin "1") (pinfunction "G_1") (pintype "passive"))
      (node (ref "T304") (pin "1") (pinfunction "G_1") (pintype "passive"))
    )
    (net (code "304") (name "SP_2_VCC_P1V5_SET_OR") (class "Default")
      (node (ref "D2503") (pin "A") (pinfunction "A_A") (pintype "passive"))
      (node (ref "R2504") (pin "2") (pinfunction "2_2") (pintype "passive"))
      (node (ref "T2504") (pin "3") (pinfunction "D_3") (pintype "passive"))
    )
    (net (code "305") (name "SP_2_VCC_P1V8_SET") (class "Default")
      (node (ref "IC1201") (pin "130") (pinfunction "B2_FB5_MC15_130") (pintype "bidirectional"))
      (node (ref "RN302") (pin "2") (pinfunction "1_2") (pintype "passive"))
      (node (ref "T2502") (pin "1") (pinfunction "G_1") (pintype "passive"))
      (node (ref "T305") (pin "1") (pinfunction "G_1") (pintype "passive"))
    )
    (net (code "306") (name "SP_2_VCC_P1V8_SET_OR") (class "Default")
      (node (ref "D2502") (pin "A") (pinfunction "A_A") (pintype "passive"))
      (node (ref "R2506") (pin "1") (pinfunction "1_1") (pintype "passive"))
      (node (ref "T2505") (pin "3") (pinfunction "D_3") (pintype "passive"))
    )
    (net (code "307") (name "SP_2_VCC_P2V5_SET") (class "Default")
      (node (ref "IC1201") (pin "129") (pinfunction "B2_FB5_MC16_129") (pintype "bidirectional"))
      (node (ref "RN302") (pin "1") (pinfunction "1_1") (pintype "passive"))
      (node (ref "T2503") (pin "1") (pinfunction "G_1") (pintype "passive"))
      (node (ref "T306") (pin "1") (pinfunction "G_1") (pintype "passive"))
    )
    (net (code "308") (name "SP_2_VCC_P2V5_SET_OR") (class "Default")
      (node (ref "D2501") (pin "A") (pinfunction "A_A") (pintype "passive"))
      (node (ref "R2508") (pin "1") (pinfunction "1_1") (pintype "passive"))
      (node (ref "T2506") (pin "3") (pinfunction "D_3") (pintype "passive"))
    )
    (net (code "309") (name "ST_1_IN") (class "Default")
      (node (ref "IC401") (pin "12") (pinfunction "I0_12") (pintype "input"))
      (node (ref "IC401") (pin "13") (pinfunction "I1_13") (pintype "input"))
      (node (ref "R401") (pin "2") (pinfunction "2_2") (pintype "passive"))
      (node (ref "X1701") (pin "18") (pinfunction "18_18") (pintype "passive"))
    )
    (net (code "310") (name "ST_1_OUT") (class "Default")
      (node (ref "IC401") (pin "11") (pinfunction "O_11") (pintype "output"))
      (node (ref "IC801") (pin "166") (pinfunction "IO_L10N_1/VREF_1_166") (pintype "bidirectional"))
      (node (ref "X1701") (pin "22") (pinfunction "22_22") (pintype "passive"))
    )
    (net (code "311") (name "ST_2_IN") (class "Default")
      (node (ref "IC401") (pin "8") (pinfunction "I0_8") (pintype "input"))
      (node (ref "IC401") (pin "9") (pinfunction "I1_9") (pintype "input"))
      (node (ref "R402") (pin "2") (pinfunction "2_2") (pintype "passive"))
      (node (ref "X1701") (pin "20") (pinfunction "20_20") (pintype "passive"))
    )
    (net (code "312") (name "ST_2_OUT") (class "Default")
      (node (ref "IC401") (pin "10") (pinfunction "O_10") (pintype "output"))
      (node (ref "IC801") (pin "165") (pinfunction "IO_L10P_1_165") (pintype "bidirectional"))
      (node (ref "X1701") (pin "24") (pinfunction "24_24") (pintype "passive"))
    )
    (net (code "313") (name "SYS_RESET_N") (class "Default")
      (node (ref "IC1201") (pin "35") (pinfunction "B1_FB7_MC1(CDRST)_35") (pintype "bidirectional"))
      (node (ref "IC801") (pin "182") (pinfunction "IO_182") (pintype "bidirectional"))
      (node (ref "R1707") (pin "1") (pinfunction "1_1") (pintype "passive"))
      (node (ref "R407") (pin "1") (pinfunction "1_1") (pintype "passive"))
      (node (ref "T401") (pin "3") (pinfunction "D_3") (pintype "passive"))
      (node (ref "X1701") (pin "38") (pinfunction "38_38") (pintype "passive"))
    )
    (net (code "314") (name "TEST_1_TCK") (class "Default")
      (node (ref "IC801") (pin "159") (pinfunction "TCK_159") (pintype "input"))
      (node (ref "IC802") (pin "6") (pinfunction "TCK_6") (pintype "input"))
      (node (ref "R501") (pin "2") (pinfunction "2_2") (pintype "passive"))
      (node (ref "X501") (pin "1") (pinfunction "1_1") (pintype "passive"))
      (node (ref "X502") (pin "1") (pinfunction "1_1") (pintype "passive"))
    )
    (net (code "315") (name "TEST_1_TDI") (class "Default")
      (node (ref "IC801") (pin "208") (pinfunction "TDI_208") (pintype "input"))
      (node (ref "RN501") (pin "2") (pinfunction "1_2") (pintype "passive"))
      (node (ref "X501") (pin "7") (pinfunction "7_7") (pintype "passive"))
      (node (ref "X502") (pin "7") (pinfunction "7_7") (pintype "passive"))
    )
    (net (code "316") (name "TEST_1_TDO") (class "Default")
      (node (ref "IC802") (pin "17") (pinfunction "TDO_17") (pintype "output"))
      (node (ref "RN501") (pin "3") (pinfunction "1_3") (pintype "passive"))
      (node (ref "X501") (pin "5") (pinfunction "5_5") (pintype "passive"))
      (node (ref "X502") (pin "5") (pinfunction "5_5") (pintype "passive"))
    )
    (net (code "317") (name "TEST_1_TMS") (class "Default")
      (node (ref "IC801") (pin "160") (pinfunction "TMS_160") (pintype "input"))
      (node (ref "IC802") (pin "5") (pinfunction "TMS_5") (pintype "input"))
      (node (ref "R502") (pin "2") (pinfunction "2_2") (pintype "passive"))
      (node (ref "X501") (pin "3") (pinfunction "3_3") (pintype "passive"))
      (node (ref "X502") (pin "3") (pinfunction "3_3") (pintype "passive"))
    )
    (net (code "318") (name "TEST_1_VREF") (class "Default")
      (node (ref "J501") (pin "2") (pinfunction "2_2") (pintype "passive"))
      (node (ref "RN501") (pin "6") (pinfunction "2_6") (pintype "passive"))
      (node (ref "RN501") (pin "7") (pinfunction "2_7") (pintype "passive"))
      (node (ref "X501") (pin "10") (pinfunction "10_10") (pintype "passive"))
      (node (ref "X502") (pin "10") (pinfunction "10_10") (pintype "passive"))
    )
    (net (code "319") (name "TEST_2_TCK") (class "Default")
      (node (ref "IC1201") (pin "67") (pinfunction "TCK_67") (pintype "input"))
      (node (ref "R1201") (pin "2") (pinfunction "2_2") (pintype "passive"))
      (node (ref "X1201") (pin "1") (pinfunction "1_1") (pintype "passive"))
      (node (ref "X1202") (pin "1") (pinfunction "1_1") (pintype "passive"))
    )
    (net (code "320") (name "TEST_2_TDI") (class "Default")
      (node (ref "IC1201") (pin "63") (pinfunction "TDI_63") (pintype "input"))
      (node (ref "RN1201") (pin "2") (pinfunction "1_2") (pintype "passive"))
      (node (ref "X1201") (pin "7") (pinfunction "7_7") (pintype "passive"))
      (node (ref "X1202") (pin "7") (pinfunction "7_7") (pintype "passive"))
    )
    (net (code "321") (name "TEST_2_TDO") (class "Default")
      (node (ref "IC1201") (pin "122") (pinfunction "TDO_122") (pintype "output"))
      (node (ref "RN1201") (pin "3") (pinfunction "1_3") (pintype "passive"))
      (node (ref "X1201") (pin "5") (pinfunction "5_5") (pintype "passive"))
      (node (ref "X1202") (pin "5") (pinfunction "5_5") (pintype "passive"))
    )
    (net (code "322") (name "TEST_2_TMS") (class "Default")
      (node (ref "IC1201") (pin "65") (pinfunction "TMS_65") (pintype "input"))
      (node (ref "R1202") (pin "2") (pinfunction "2_2") (pintype "passive"))
      (node (ref "X1201") (pin "3") (pinfunction "3_3") (pintype "passive"))
      (node (ref "X1202") (pin "3") (pinfunction "3_3") (pintype "passive"))
    )
    (net (code "323") (name "TEST_2_VREF") (class "Default")
      (node (ref "J1201") (pin "2") (pinfunction "2_2") (pintype "passive"))
      (node (ref "RN1201") (pin "6") (pinfunction "2_6") (pintype "passive"))
      (node (ref "RN1201") (pin "7") (pinfunction "2_7") (pintype "passive"))
      (node (ref "X1201") (pin "10") (pinfunction "10_10") (pintype "passive"))
      (node (ref "X1202") (pin "10") (pinfunction "10_10") (pintype "passive"))
    )
    (net (code "324") (name "TEST_TDI_PROM") (class "Default")
      (node (ref "IC802") (pin "4") (pinfunction "TDI_4") (pintype "input"))
      (node (ref "J801") (pin "2") (pinfunction "2_2") (pintype "passive"))
      (node (ref "R801") (pin "1") (pinfunction "1_1") (pintype "passive"))
    )
    (net (code "325") (name "TEST_TDO_FPGA") (class "Default")
      (node (ref "IC801") (pin "158") (pinfunction "TDO_158") (pintype "output"))
      (node (ref "J801") (pin "1") (pinfunction "1_1") (pintype "passive"))
    )
    (net (code "326") (name "UART_CTS") (class "Default")
      (node (ref "IC801") (pin "199") (pinfunction "IO_L25N_0_199") (pintype "bidirectional"))
      (node (ref "X102") (pin "4") (pinfunction "4_4") (pintype "passive"))
    )
    (net (code "327") (name "UART_RTS") (class "Default")
      (node (ref "IC801") (pin "198") (pinfunction "IO_L25P_0_198") (pintype "bidirectional"))
      (node (ref "X102") (pin "2") (pinfunction "2_2") (pintype "passive"))
    )
    (net (code "328") (name "UART_RXD") (class "Default")
      (node (ref "IC801") (pin "203") (pinfunction "IO_L01P_0/VRN_0_203") (pintype "bidirectional"))
      (node (ref "X102") (pin "8") (pinfunction "8_8") (pintype "passive"))
    )
    (net (code "329") (name "UART_TXD") (class "Default")
      (node (ref "IC801") (pin "200") (pinfunction "IO/VREF_0_200") (pintype "bidirectional"))
      (node (ref "X102") (pin "6") (pinfunction "6_6") (pintype "passive"))
    )
    (net (code "330") (name "unconnected-(FD1801-NC-Pad1)") (class "Default")
      (node (ref "FD1801") (pin "1") (pinfunction "NC_1") (pintype "no_connect"))
    )
    (net (code "331") (name "unconnected-(FD1802-NC-Pad1)") (class "Default")
      (node (ref "FD1802") (pin "1") (pinfunction "NC_1") (pintype "no_connect"))
    )
    (net (code "332") (name "unconnected-(H201-MOUNT-PadH1)") (class "Default")
      (node (ref "H201") (pin "H1") (pinfunction "MOUNT_H1") (pintype "passive"))
    )
    (net (code "333") (name "unconnected-(H202-MOUNT-PadH1)") (class "Default")
      (node (ref "H202") (pin "H1") (pinfunction "MOUNT_H1") (pintype "passive"))
    )
    (net (code "334") (name "unconnected-(H203-MOUNT-PadH1)") (class "Default")
      (node (ref "H203") (pin "H1") (pinfunction "MOUNT_H1") (pintype "passive"))
    )
    (net (code "335") (name "unconnected-(IC801B-IO-Pad189)") (class "Default")
      (node (ref "IC801") (pin "189") (pinfunction "IO_189") (pintype "bidirectional"))
    )
    (net (code "336") (name "unconnected-(IC801B-IO-Pad197)") (class "Default")
      (node (ref "IC801") (pin "197") (pinfunction "IO_197") (pintype "bidirectional"))
    )
    (net (code "337") (name "unconnected-(IC801B-IO_L01N_0{slash}VRP_0-Pad204)") (class "Default")
      (node (ref "IC801") (pin "204") (pinfunction "IO_L01N_0/VRP_0_204") (pintype "bidirectional"))
    )
    (net (code "338") (name "unconnected-(IC801B-IO_L27N_0-Pad196)") (class "Default")
      (node (ref "IC801") (pin "196") (pinfunction "IO_L27N_0_196") (pintype "bidirectional"))
    )
    (net (code "339") (name "unconnected-(IC801B-IO_L27P_0-Pad194)") (class "Default")
      (node (ref "IC801") (pin "194") (pinfunction "IO_L27P_0_194") (pintype "bidirectional"))
    )
    (net (code "340") (name "unconnected-(IC801B-IO_L30N_0-Pad191)") (class "Default")
      (node (ref "IC801") (pin "191") (pinfunction "IO_L30N_0_191") (pintype "bidirectional"))
    )
    (net (code "341") (name "unconnected-(IC801B-IO_L30P_0-Pad190)") (class "Default")
      (node (ref "IC801") (pin "190") (pinfunction "IO_L30P_0_190") (pintype "bidirectional"))
    )
    (net (code "342") (name "unconnected-(IC801B-IO_L31N_0-Pad187)") (class "Default")
      (node (ref "IC801") (pin "187") (pinfunction "IO_L31N_0_187") (pintype "bidirectional"))
    )
    (net (code "343") (name "unconnected-(IC801B-IO_L31P_0{slash}VREF_0-Pad185)") (class "Default")
      (node (ref "IC801") (pin "185") (pinfunction "IO_L31P_0/VREF_0_185") (pintype "bidirectional"))
    )
    (net (code "344") (name "unconnected-(IC801B-IO_L32N_0{slash}GCLK7-Pad184)") (class "Default")
      (node (ref "IC801") (pin "184") (pinfunction "IO_L32N_0/GCLK7_184") (pintype "bidirectional"))
    )
    (net (code "345") (name "unconnected-(IC801B-IO_L32P_0{slash}GCLK6-Pad183)") (class "Default")
      (node (ref "IC801") (pin "183") (pinfunction "IO_L32P_0/GCLK6_183") (pintype "bidirectional"))
    )
    (net (code "346") (name "unconnected-(IC801B-IO{slash}VREF_0-Pad205)") (class "Default")
      (node (ref "IC801") (pin "205") (pinfunction "IO/VREF_0_205") (pintype "bidirectional"))
    )
    (net (code "347") (name "unconnected-(IC801C-IO-Pad167)") (class "Default")
      (node (ref "IC801") (pin "167") (pinfunction "IO_167") (pintype "bidirectional"))
    )
    (net (code "348") (name "unconnected-(IC801C-IO-Pad175)") (class "Default")
      (node (ref "IC801") (pin "175") (pinfunction "IO_175") (pintype "bidirectional"))
    )
    (net (code "349") (name "unconnected-(IC801C-IO_L01N_1{slash}VRP_1-Pad162)") (class "Default")
      (node (ref "IC801") (pin "162") (pinfunction "IO_L01N_1/VRP_1_162") (pintype "bidirectional"))
    )
    (net (code "350") (name "unconnected-(IC801C-IO_L01P_1{slash}VRN_1-Pad161)") (class "Default")
      (node (ref "IC801") (pin "161") (pinfunction "IO_L01P_1/VRN_1_161") (pintype "bidirectional"))
    )
    (net (code "351") (name "unconnected-(IC801C-IO_L27N_1-Pad169)") (class "Default")
      (node (ref "IC801") (pin "169") (pinfunction "IO_L27N_1_169") (pintype "bidirectional"))
    )
    (net (code "352") (name "unconnected-(IC801C-IO_L27P_1-Pad168)") (class "Default")
      (node (ref "IC801") (pin "168") (pinfunction "IO_L27P_1_168") (pintype "bidirectional"))
    )
    (net (code "353") (name "unconnected-(IC801C-IO_L28N_1-Pad172)") (class "Default")
      (node (ref "IC801") (pin "172") (pinfunction "IO_L28N_1_172") (pintype "bidirectional"))
    )
    (net (code "354") (name "unconnected-(IC801C-IO_L28P_1-Pad171)") (class "Default")
      (node (ref "IC801") (pin "171") (pinfunction "IO_L28P_1_171") (pintype "bidirectional"))
    )
    (net (code "355") (name "unconnected-(IC801C-IO_L31N_1{slash}VREF_1-Pad178)") (class "Default")
      (node (ref "IC801") (pin "178") (pinfunction "IO_L31N_1/VREF_1_178") (pintype "bidirectional"))
    )
    (net (code "356") (name "unconnected-(IC801C-IO_L31P_1-Pad176)") (class "Default")
      (node (ref "IC801") (pin "176") (pinfunction "IO_L31P_1_176") (pintype "bidirectional"))
    )
    (net (code "357") (name "unconnected-(IC801C-IO_L32P_1{slash}GCLK4-Pad180)") (class "Default")
      (node (ref "IC801") (pin "180") (pinfunction "IO_L32P_1/GCLK4_180") (pintype "bidirectional"))
    )
    (net (code "358") (name "unconnected-(IC801D-IO_L01N_2{slash}VRP_2-Pad156)") (class "Default")
      (node (ref "IC801") (pin "156") (pinfunction "IO_L01N_2/VRP_2_156") (pintype "bidirectional"))
    )
    (net (code "359") (name "unconnected-(IC801D-IO_L01P_2{slash}VRN_2-Pad155)") (class "Default")
      (node (ref "IC801") (pin "155") (pinfunction "IO_L01P_2/VRN_2_155") (pintype "bidirectional"))
    )
    (net (code "360") (name "unconnected-(IC801F-IO-Pad93)") (class "Default")
      (node (ref "IC801") (pin "93") (pinfunction "IO_93") (pintype "bidirectional"))
    )
    (net (code "361") (name "unconnected-(IC801F-IO_L01N_4{slash}VRP_4-Pad101)") (class "Default")
      (node (ref "IC801") (pin "101") (pinfunction "IO_L01N_4/VRP_4_101") (pintype "bidirectional"))
    )
    (net (code "362") (name "unconnected-(IC801F-IO_L01P_4{slash}VRN_4-Pad100)") (class "Default")
      (node (ref "IC801") (pin "100") (pinfunction "IO_L01P_4/VRN_4_100") (pintype "bidirectional"))
    )
    (net (code "363") (name "unconnected-(IC801F-IO_L25N_4-Pad95)") (class "Default")
      (node (ref "IC801") (pin "95") (pinfunction "IO_L25N_4_95") (pintype "bidirectional"))
    )
    (net (code "364") (name "unconnected-(IC801F-IO_L25P_4-Pad94)") (class "Default")
      (node (ref "IC801") (pin "94") (pinfunction "IO_L25P_4_94") (pintype "bidirectional"))
    )
    (net (code "365") (name "unconnected-(IC801F-IO_L27P_4{slash}D1-Pad90)") (class "Default")
      (node (ref "IC801") (pin "90") (pinfunction "IO_L27P_4/D1_90") (pintype "bidirectional"))
    )
    (net (code "366") (name "unconnected-(IC801F-IO_L30N_4{slash}D2-Pad87)") (class "Default")
      (node (ref "IC801") (pin "87") (pinfunction "IO_L30N_4/D2_87") (pintype "bidirectional"))
    )
    (net (code "367") (name "unconnected-(IC801F-IO_L30P_4{slash}D3-Pad86)") (class "Default")
      (node (ref "IC801") (pin "86") (pinfunction "IO_L30P_4/D3_86") (pintype "bidirectional"))
    )
    (net (code "368") (name "unconnected-(IC801F-IO_L32P_4{slash}GCLK0-Pad79)") (class "Default")
      (node (ref "IC801") (pin "79") (pinfunction "IO_L32P_4/GCLK0_79") (pintype "bidirectional"))
    )
    (net (code "369") (name "unconnected-(IC801F-IO{slash}VREF_4-Pad85)") (class "Default")
      (node (ref "IC801") (pin "85") (pinfunction "IO/VREF_4_85") (pintype "bidirectional"))
    )
    (net (code "370") (name "unconnected-(IC801F-IO{slash}VREF_4-Pad102)") (class "Default")
      (node (ref "IC801") (pin "102") (pinfunction "IO/VREF_4_102") (pintype "bidirectional"))
    )
    (net (code "371") (name "unconnected-(IC801H-IO_L21P_6-Pad42)") (class "Default")
      (node (ref "IC801") (pin "42") (pinfunction "IO_L21P_6_42") (pintype "bidirectional"))
    )
    (net (code "372") (name "unconnected-(IC801H-IO_L39P_6-Pad31)") (class "Default")
      (node (ref "IC801") (pin "31") (pinfunction "IO_L39P_6_31") (pintype "bidirectional"))
    )
    (net (code "373") (name "unconnected-(IC801H-IO_L40P_6{slash}VREF_6-Pad28)") (class "Default")
      (node (ref "IC801") (pin "28") (pinfunction "IO_L40P_6/VREF_6_28") (pintype "bidirectional"))
    )
    (net (code "374") (name "unconnected-(IC801I-IO_L16N_7-Pad5)") (class "Default")
      (node (ref "IC801") (pin "5") (pinfunction "IO_L16N_7_5") (pintype "bidirectional"))
    )
    (net (code "375") (name "unconnected-(IC801I-IO_L19N_7{slash}VREF_7-Pad9)") (class "Default")
      (node (ref "IC801") (pin "9") (pinfunction "IO_L19N_7/VREF_7_9") (pintype "bidirectional"))
    )
    (net (code "376") (name "unconnected-(IC801I-IO_L19P_7-Pad7)") (class "Default")
      (node (ref "IC801") (pin "7") (pinfunction "IO_L19P_7_7") (pintype "bidirectional"))
    )
    (net (code "377") (name "unconnected-(IC801I-IO_L21N_7-Pad13)") (class "Default")
      (node (ref "IC801") (pin "13") (pinfunction "IO_L21N_7_13") (pintype "bidirectional"))
    )
    (net (code "378") (name "unconnected-(IC801I-IO_L22N_7-Pad16)") (class "Default")
      (node (ref "IC801") (pin "16") (pinfunction "IO_L22N_7_16") (pintype "bidirectional"))
    )
    (net (code "379") (name "unconnected-(IC801I-IO_L22P_7-Pad15)") (class "Default")
      (node (ref "IC801") (pin "15") (pinfunction "IO_L22P_7_15") (pintype "bidirectional"))
    )
    (net (code "380") (name "unconnected-(IC801I-IO_L23N_7-Pad19)") (class "Default")
      (node (ref "IC801") (pin "19") (pinfunction "IO_L23N_7_19") (pintype "bidirectional"))
    )
    (net (code "381") (name "unconnected-(IC801I-IO_L23P_7-Pad18)") (class "Default")
      (node (ref "IC801") (pin "18") (pinfunction "IO_L23P_7_18") (pintype "bidirectional"))
    )
    (net (code "382") (name "unconnected-(IC801I-IO_L24N_7-Pad21)") (class "Default")
      (node (ref "IC801") (pin "21") (pinfunction "IO_L24N_7_21") (pintype "bidirectional"))
    )
    (net (code "383") (name "unconnected-(IC801I-IO_L24P_7-Pad20)") (class "Default")
      (node (ref "IC801") (pin "20") (pinfunction "IO_L24P_7_20") (pintype "bidirectional"))
    )
    (net (code "384") (name "unconnected-(IC801I-IO_L39N_7-Pad24)") (class "Default")
      (node (ref "IC801") (pin "24") (pinfunction "IO_L39N_7_24") (pintype "bidirectional"))
    )
    (net (code "385") (name "unconnected-(IC801I-IO_L39P_7-Pad22)") (class "Default")
      (node (ref "IC801") (pin "22") (pinfunction "IO_L39P_7_22") (pintype "bidirectional"))
    )
    (net (code "386") (name "unconnected-(IC801I-IO_L40N_7{slash}VREF_7-Pad27)") (class "Default")
      (node (ref "IC801") (pin "27") (pinfunction "IO_L40N_7/VREF_7_27") (pintype "bidirectional"))
    )
    (net (code "387") (name "unconnected-(IC801I-IO_L40P_7-Pad26)") (class "Default")
      (node (ref "IC801") (pin "26") (pinfunction "IO_L40P_7_26") (pintype "bidirectional"))
    )
    (net (code "388") (name "unconnected-(IC802-~{CEO}-Pad13)") (class "Default")
      (node (ref "IC802") (pin "13") (pinfunction "~{CEO}_13") (pintype "output"))
    )
    (net (code "389") (name "unconnected-(IC1101-OE-Pad1)") (class "Default")
      (node (ref "IC1101") (pin "1") (pinfunction "OE_1") (pintype "input"))
    )
    (net (code "390") (name "unconnected-(IC1201B-B1_FB7_MC15(GCK0)-Pad30)") (class "Default")
      (node (ref "IC1201") (pin "30") (pinfunction "B1_FB7_MC15(GCK0)_30") (pintype "bidirectional"))
    )
    (net (code "391") (name "unconnected-(IC1201D-B3_FB19_MC3-Pad74)") (class "Default")
      (node (ref "IC1201") (pin "74") (pinfunction "B3_FB19_MC3_74") (pintype "bidirectional"))
    )
    (net (code "392") (name "unconnected-(IC1201D-B3_FB19_MC4-Pad75)") (class "Default")
      (node (ref "IC1201") (pin "75") (pinfunction "B3_FB19_MC4_75") (pintype "bidirectional"))
    )
    (net (code "393") (name "unconnected-(IC1201D-B3_FB19_MC5-Pad76)") (class "Default")
      (node (ref "IC1201") (pin "76") (pinfunction "B3_FB19_MC5_76") (pintype "bidirectional"))
    )
    (net (code "394") (name "unconnected-(IC1201D-B3_FB19_MC12-Pad77)") (class "Default")
      (node (ref "IC1201") (pin "77") (pinfunction "B3_FB19_MC12_77") (pintype "bidirectional"))
    )
    (net (code "395") (name "unconnected-(IC1201D-B3_FB19_MC13-Pad78)") (class "Default")
      (node (ref "IC1201") (pin "78") (pinfunction "B3_FB19_MC13_78") (pintype "bidirectional"))
    )
    (net (code "396") (name "unconnected-(IC1201D-B3_FB19_MC14-Pad79)") (class "Default")
      (node (ref "IC1201") (pin "79") (pinfunction "B3_FB19_MC14_79") (pintype "bidirectional"))
    )
    (net (code "397") (name "unconnected-(IC1201D-B3_FB20_MC1-Pad71)") (class "Default")
      (node (ref "IC1201") (pin "71") (pinfunction "B3_FB20_MC1_71") (pintype "bidirectional"))
    )
    (net (code "398") (name "unconnected-(IC1201D-B3_FB20_MC2-Pad70)") (class "Default")
      (node (ref "IC1201") (pin "70") (pinfunction "B3_FB20_MC2_70") (pintype "bidirectional"))
    )
    (net (code "399") (name "unconnected-(IC1201D-B3_FB20_MC3-Pad69)") (class "Default")
      (node (ref "IC1201") (pin "69") (pinfunction "B3_FB20_MC3_69") (pintype "bidirectional"))
    )
    (net (code "400") (name "unconnected-(IC1201D-B3_FB20_MC4-Pad68)") (class "Default")
      (node (ref "IC1201") (pin "68") (pinfunction "B3_FB20_MC4_68") (pintype "bidirectional"))
    )
    (net (code "401") (name "unconnected-(IC1201D-B3_FB20_MC5-Pad66)") (class "Default")
      (node (ref "IC1201") (pin "66") (pinfunction "B3_FB20_MC5_66") (pintype "bidirectional"))
    )
    (net (code "402") (name "unconnected-(IC1201D-B3_FB20_MC13-Pad64)") (class "Default")
      (node (ref "IC1201") (pin "64") (pinfunction "B3_FB20_MC13_64") (pintype "bidirectional"))
    )
    (net (code "403") (name "unconnected-(IC1201D-B3_FB21_MC1-Pad80)") (class "Default")
      (node (ref "IC1201") (pin "80") (pinfunction "B3_FB21_MC1_80") (pintype "bidirectional"))
    )
    (net (code "404") (name "unconnected-(IC1201D-B3_FB21_MC3-Pad81)") (class "Default")
      (node (ref "IC1201") (pin "81") (pinfunction "B3_FB21_MC3_81") (pintype "bidirectional"))
    )
    (net (code "405") (name "unconnected-(IC1201D-B3_FB21_MC12-Pad82)") (class "Default")
      (node (ref "IC1201") (pin "82") (pinfunction "B3_FB21_MC12_82") (pintype "bidirectional"))
    )
    (net (code "406") (name "unconnected-(IC1201D-B3_FB21_MC15-Pad83)") (class "Default")
      (node (ref "IC1201") (pin "83") (pinfunction "B3_FB21_MC15_83") (pintype "bidirectional"))
    )
    (net (code "407") (name "unconnected-(IC1201D-B3_FB22_MC2-Pad61)") (class "Default")
      (node (ref "IC1201") (pin "61") (pinfunction "B3_FB22_MC2_61") (pintype "bidirectional"))
    )
    (net (code "408") (name "unconnected-(IC1201D-B3_FB22_MC12-Pad60)") (class "Default")
      (node (ref "IC1201") (pin "60") (pinfunction "B3_FB22_MC12_60") (pintype "bidirectional"))
    )
    (net (code "409") (name "unconnected-(IC1201D-B3_FB22_MC14-Pad59)") (class "Default")
      (node (ref "IC1201") (pin "59") (pinfunction "B3_FB22_MC14_59") (pintype "bidirectional"))
    )
    (net (code "410") (name "unconnected-(IC1201D-B3_FB24_MC2-Pad58)") (class "Default")
      (node (ref "IC1201") (pin "58") (pinfunction "B3_FB24_MC2_58") (pintype "bidirectional"))
    )
    (net (code "411") (name "unconnected-(IC1201D-B3_FB24_MC12-Pad57)") (class "Default")
      (node (ref "IC1201") (pin "57") (pinfunction "B3_FB24_MC12_57") (pintype "bidirectional"))
    )
    (net (code "412") (name "unconnected-(IC1201D-B3_FB24_MC14-Pad56)") (class "Default")
      (node (ref "IC1201") (pin "56") (pinfunction "B3_FB24_MC14_56") (pintype "bidirectional"))
    )
    (net (code "413") (name "unconnected-(IC1201E-B4_FB13_MC3-Pad112)") (class "Default")
      (node (ref "IC1201") (pin "112") (pinfunction "B4_FB13_MC3_112") (pintype "bidirectional"))
    )
    (net (code "414") (name "unconnected-(IC1201E-B4_FB13_MC4-Pad113)") (class "Default")
      (node (ref "IC1201") (pin "113") (pinfunction "B4_FB13_MC4_113") (pintype "bidirectional"))
    )
    (net (code "415") (name "unconnected-(IC1201E-B4_FB13_MC12-Pad114)") (class "Default")
      (node (ref "IC1201") (pin "114") (pinfunction "B4_FB13_MC12_114") (pintype "bidirectional"))
    )
    (net (code "416") (name "unconnected-(IC1201E-B4_FB13_MC13-Pad115)") (class "Default")
      (node (ref "IC1201") (pin "115") (pinfunction "B4_FB13_MC13_115") (pintype "bidirectional"))
    )
    (net (code "417") (name "unconnected-(IC1201E-B4_FB14_MC1-Pad111)") (class "Default")
      (node (ref "IC1201") (pin "111") (pinfunction "B4_FB14_MC1_111") (pintype "bidirectional"))
    )
    (net (code "418") (name "unconnected-(IC1201E-B4_FB14_MC2-Pad110)") (class "Default")
      (node (ref "IC1201") (pin "110") (pinfunction "B4_FB14_MC2_110") (pintype "bidirectional"))
    )
    (net (code "419") (name "unconnected-(IC1201E-B4_FB15_MC2-Pad116)") (class "Default")
      (node (ref "IC1201") (pin "116") (pinfunction "B4_FB15_MC2_116") (pintype "bidirectional"))
    )
    (net (code "420") (name "unconnected-(IC1201E-B4_FB15_MC5-Pad117)") (class "Default")
      (node (ref "IC1201") (pin "117") (pinfunction "B4_FB15_MC5_117") (pintype "bidirectional"))
    )
    (net (code "421") (name "unconnected-(IC1201E-B4_FB15_MC13-Pad118)") (class "Default")
      (node (ref "IC1201") (pin "118") (pinfunction "B4_FB15_MC13_118") (pintype "bidirectional"))
    )
    (net (code "422") (name "unconnected-(IC1201E-B4_FB15_MC15-Pad119)") (class "Default")
      (node (ref "IC1201") (pin "119") (pinfunction "B4_FB15_MC15_119") (pintype "bidirectional"))
    )
    (net (code "423") (name "unconnected-(IC1201E-B4_FB15_MC16-Pad120)") (class "Default")
      (node (ref "IC1201") (pin "120") (pinfunction "B4_FB15_MC16_120") (pintype "bidirectional"))
    )
    (net (code "424") (name "unconnected-(IC1201E-B4_FB16_MC14-Pad101)") (class "Default")
      (node (ref "IC1201") (pin "101") (pinfunction "B4_FB16_MC14_101") (pintype "bidirectional"))
    )
    (net (code "425") (name "unconnected-(IC1201E-B4_FB16_MC16-Pad100)") (class "Default")
      (node (ref "IC1201") (pin "100") (pinfunction "B4_FB16_MC16_100") (pintype "bidirectional"))
    )
    (net (code "426") (name "unconnected-(IC1201E-B4_FB17_MC2-Pad121)") (class "Default")
      (node (ref "IC1201") (pin "121") (pinfunction "B4_FB17_MC2_121") (pintype "bidirectional"))
    )
    (net (code "427") (name "unconnected-(IC1201E-B4_FB17_MC12-Pad124)") (class "Default")
      (node (ref "IC1201") (pin "124") (pinfunction "B4_FB17_MC12_124") (pintype "bidirectional"))
    )
    (net (code "428") (name "unconnected-(IC1201E-B4_FB17_MC13-Pad125)") (class "Default")
      (node (ref "IC1201") (pin "125") (pinfunction "B4_FB17_MC13_125") (pintype "bidirectional"))
    )
    (net (code "429") (name "unconnected-(IC1201E-B4_FB17_MC14-Pad126)") (class "Default")
      (node (ref "IC1201") (pin "126") (pinfunction "B4_FB17_MC14_126") (pintype "bidirectional"))
    )
    (net (code "430") (name "unconnected-(IC1201E-B4_FB17_MC16-Pad128)") (class "Default")
      (node (ref "IC1201") (pin "128") (pinfunction "B4_FB17_MC16_128") (pintype "bidirectional"))
    )
    (net (code "431") (name "unconnected-(IC1201E-B4_FB18_MC3-Pad98)") (class "Default")
      (node (ref "IC1201") (pin "98") (pinfunction "B4_FB18_MC3_98") (pintype "bidirectional"))
    )
    (net (code "432") (name "unconnected-(IC1201E-B4_FB18_MC4-Pad97)") (class "Default")
      (node (ref "IC1201") (pin "97") (pinfunction "B4_FB18_MC4_97") (pintype "bidirectional"))
    )
    (net (code "433") (name "unconnected-(IC1201E-B4_FB18_MC5-Pad96)") (class "Default")
      (node (ref "IC1201") (pin "96") (pinfunction "B4_FB18_MC5_96") (pintype "bidirectional"))
    )
    (net (code "434") (name "unconnected-(IC1201E-B4_FB18_MC12-Pad95)") (class "Default")
      (node (ref "IC1201") (pin "95") (pinfunction "B4_FB18_MC12_95") (pintype "bidirectional"))
    )
    (net (code "435") (name "unconnected-(IC1201E-B4_FB18_MC13-Pad94)") (class "Default")
      (node (ref "IC1201") (pin "94") (pinfunction "B4_FB18_MC13_94") (pintype "bidirectional"))
    )
    (net (code "436") (name "unconnected-(J801-Pad4)") (class "Default")
      (node (ref "J801") (pin "4") (pinfunction "4_4") (pintype "passive"))
    )
    (net (code "437") (name "unconnected-(J801-Pad12)") (class "Default")
      (node (ref "J801") (pin "12") (pinfunction "12_12") (pintype "passive"))
    )
    (net (code "438") (name "unconnected-(X102-Pad10)") (class "Default")
      (node (ref "X102") (pin "10") (pinfunction "10_10") (pintype "passive"))
    )
    (net (code "439") (name "unconnected-(X104-Pad19)") (class "Default")
      (node (ref "X104") (pin "19") (pinfunction "19_19") (pintype "passive"))
    )
    (net (code "440") (name "unconnected-(X104-Pad21)") (class "Default")
      (node (ref "X104") (pin "21") (pinfunction "21_21") (pintype "passive"))
    )
    (net (code "441") (name "unconnected-(X104-Pad23)") (class "Default")
      (node (ref "X104") (pin "23") (pinfunction "23_23") (pintype "passive"))
    )
    (net (code "442") (name "unconnected-(X104-Pad25)") (class "Default")
      (node (ref "X104") (pin "25") (pinfunction "25_25") (pintype "passive"))
    )
    (net (code "443") (name "unconnected-(X106-Pad19)") (class "Default")
      (node (ref "X106") (pin "19") (pinfunction "19_19") (pintype "passive"))
    )
    (net (code "444") (name "unconnected-(X106-Pad21)") (class "Default")
      (node (ref "X106") (pin "21") (pinfunction "21_21") (pintype "passive"))
    )
    (net (code "445") (name "unconnected-(X106-Pad23)") (class "Default")
      (node (ref "X106") (pin "23") (pinfunction "23_23") (pintype "passive"))
    )
    (net (code "446") (name "unconnected-(X106-Pad25)") (class "Default")
      (node (ref "X106") (pin "25") (pinfunction "25_25") (pintype "passive"))
    )
    (net (code "447") (name "unconnected-(X501-Pad9)") (class "Default")
      (node (ref "X501") (pin "9") (pinfunction "9_9") (pintype "passive"))
    )
    (net (code "448") (name "unconnected-(X502-Pad9)") (class "Default")
      (node (ref "X502") (pin "9") (pinfunction "9_9") (pintype "passive"))
    )
    (net (code "449") (name "unconnected-(X1201-Pad9)") (class "Default")
      (node (ref "X1201") (pin "9") (pinfunction "9_9") (pintype "passive"))
    )
    (net (code "450") (name "unconnected-(X1202-Pad9)") (class "Default")
      (node (ref "X1202") (pin "9") (pinfunction "9_9") (pintype "passive"))
    )
    (net (code "451") (name "unconnected-(X1701-Pad6)") (class "Default")
      (node (ref "X1701") (pin "6") (pinfunction "6_6") (pintype "passive"))
    )
    (net (code "452") (name "unconnected-(X1701-Pad8)") (class "Default")
      (node (ref "X1701") (pin "8") (pinfunction "8_8") (pintype "passive"))
    )
    (net (code "453") (name "unconnected-(X1701-Pad10)") (class "Default")
      (node (ref "X1701") (pin "10") (pinfunction "10_10") (pintype "passive"))
    )
    (net (code "454") (name "unconnected-(X1701-Pad12)") (class "Default")
      (node (ref "X1701") (pin "12") (pinfunction "12_12") (pintype "passive"))
    )
    (net (code "455") (name "unconnected-(X1702-Pad36)") (class "Default")
      (node (ref "X1702") (pin "36") (pinfunction "36_36") (pintype "passive"))
    )
    (net (code "456") (name "unconnected-(X1702-Pad38)") (class "Default")
      (node (ref "X1702") (pin "38") (pinfunction "38_38") (pintype "passive"))
    )
  )
)
